# 2.net
KiCad netlist of a schematic drawn in Altium Designer
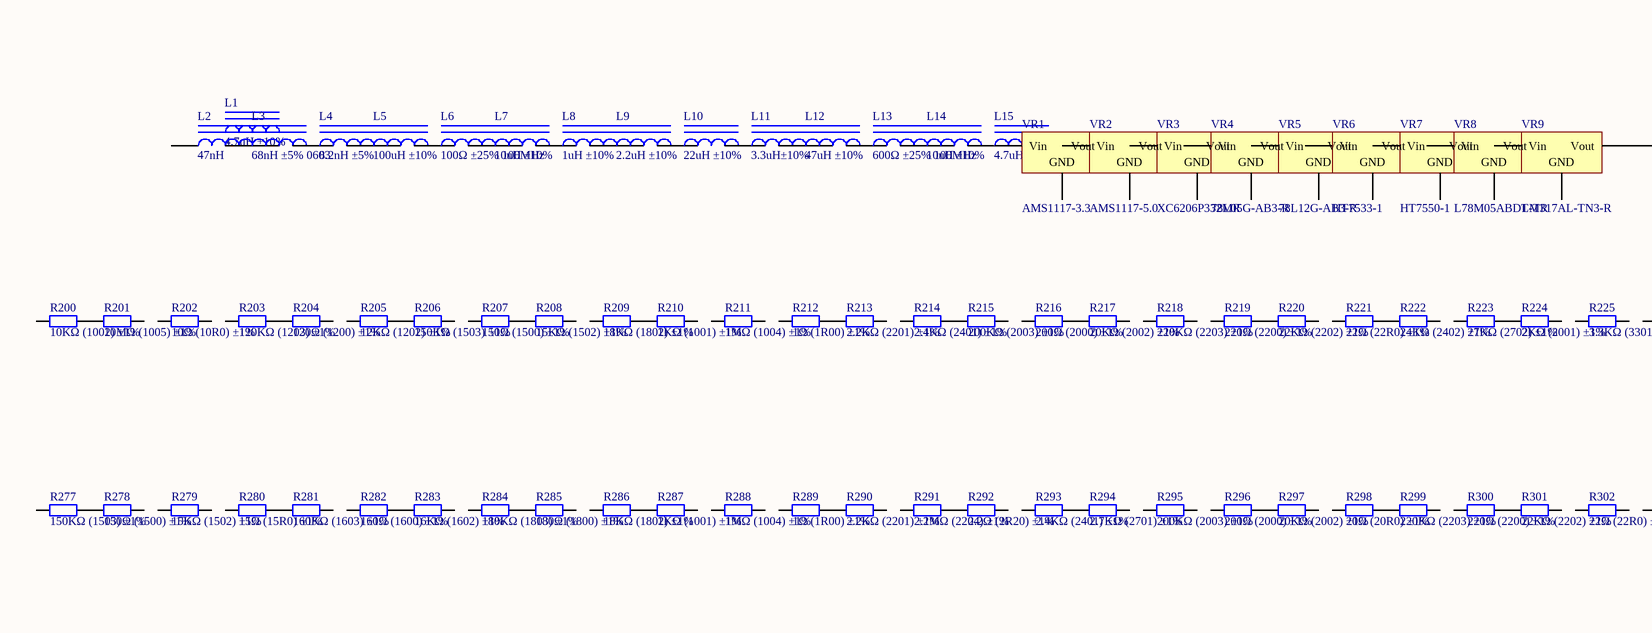
[diagram p0: 2.SchDoc, left]
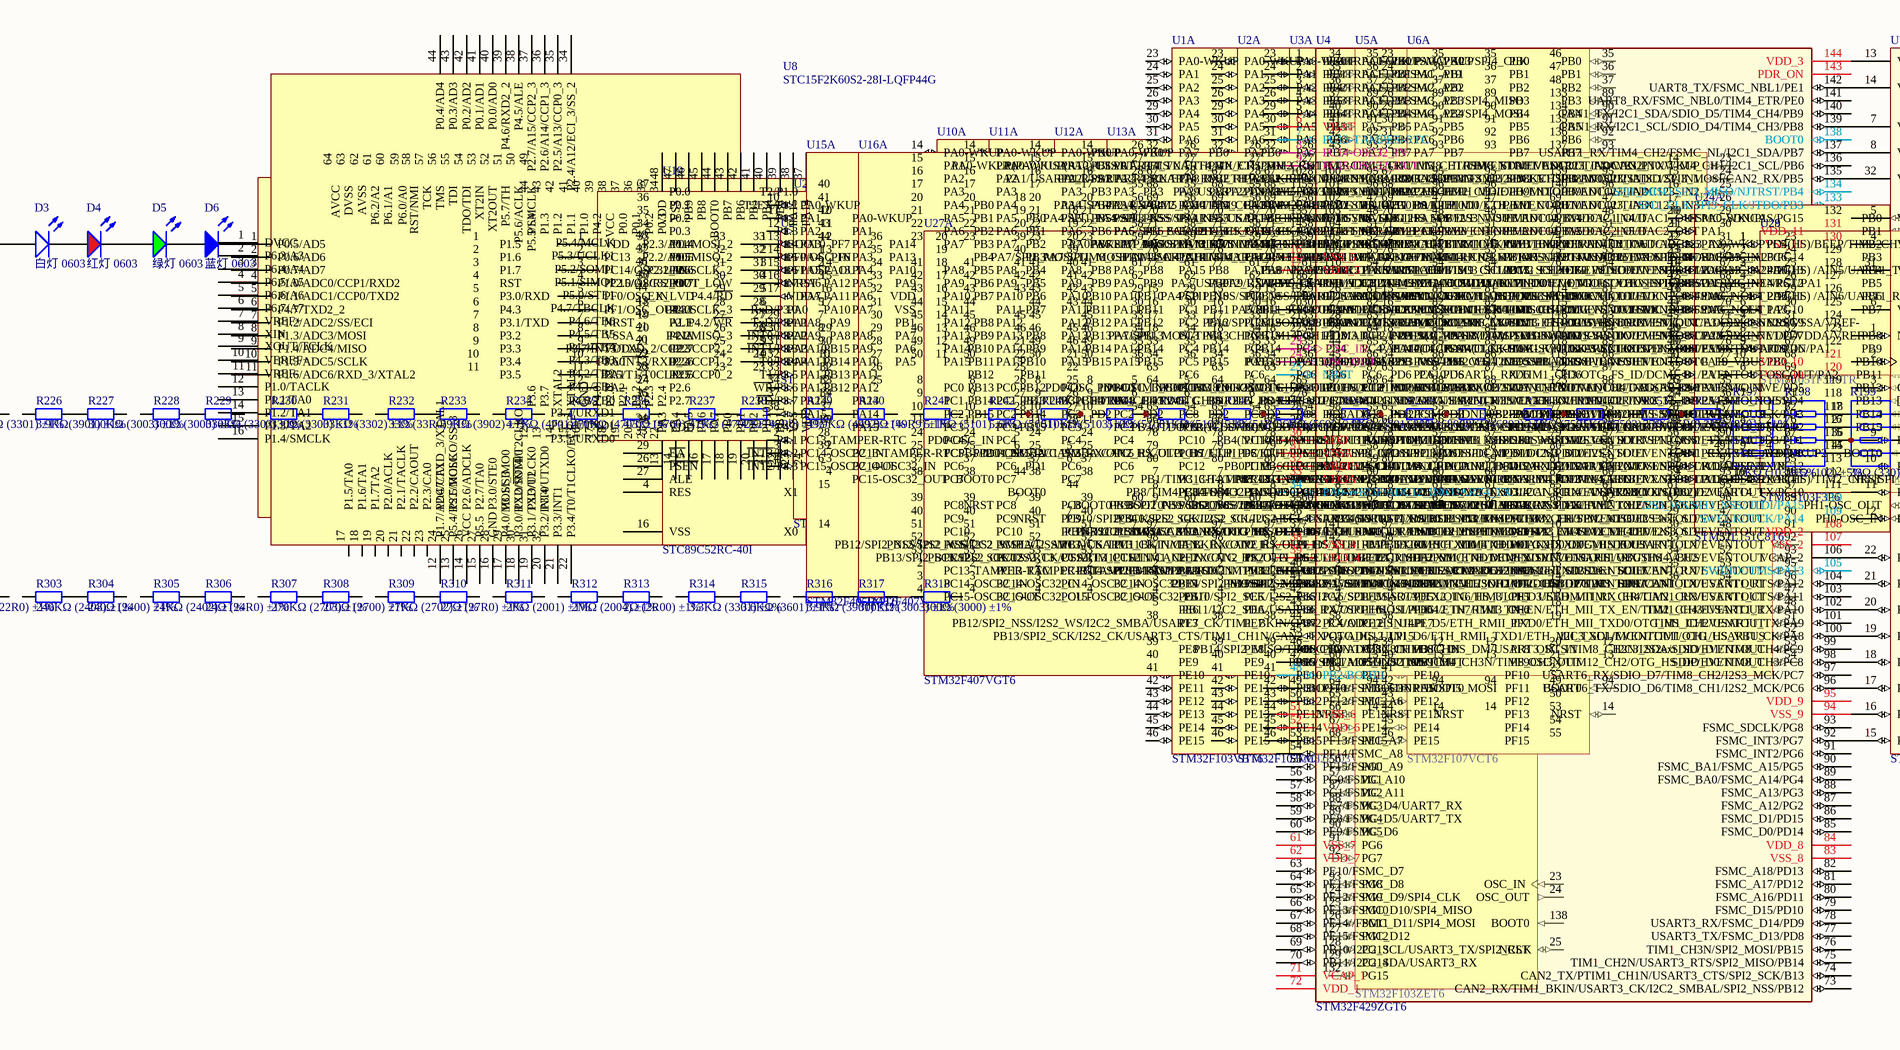
[diagram p1: 2.SchDoc, middle]
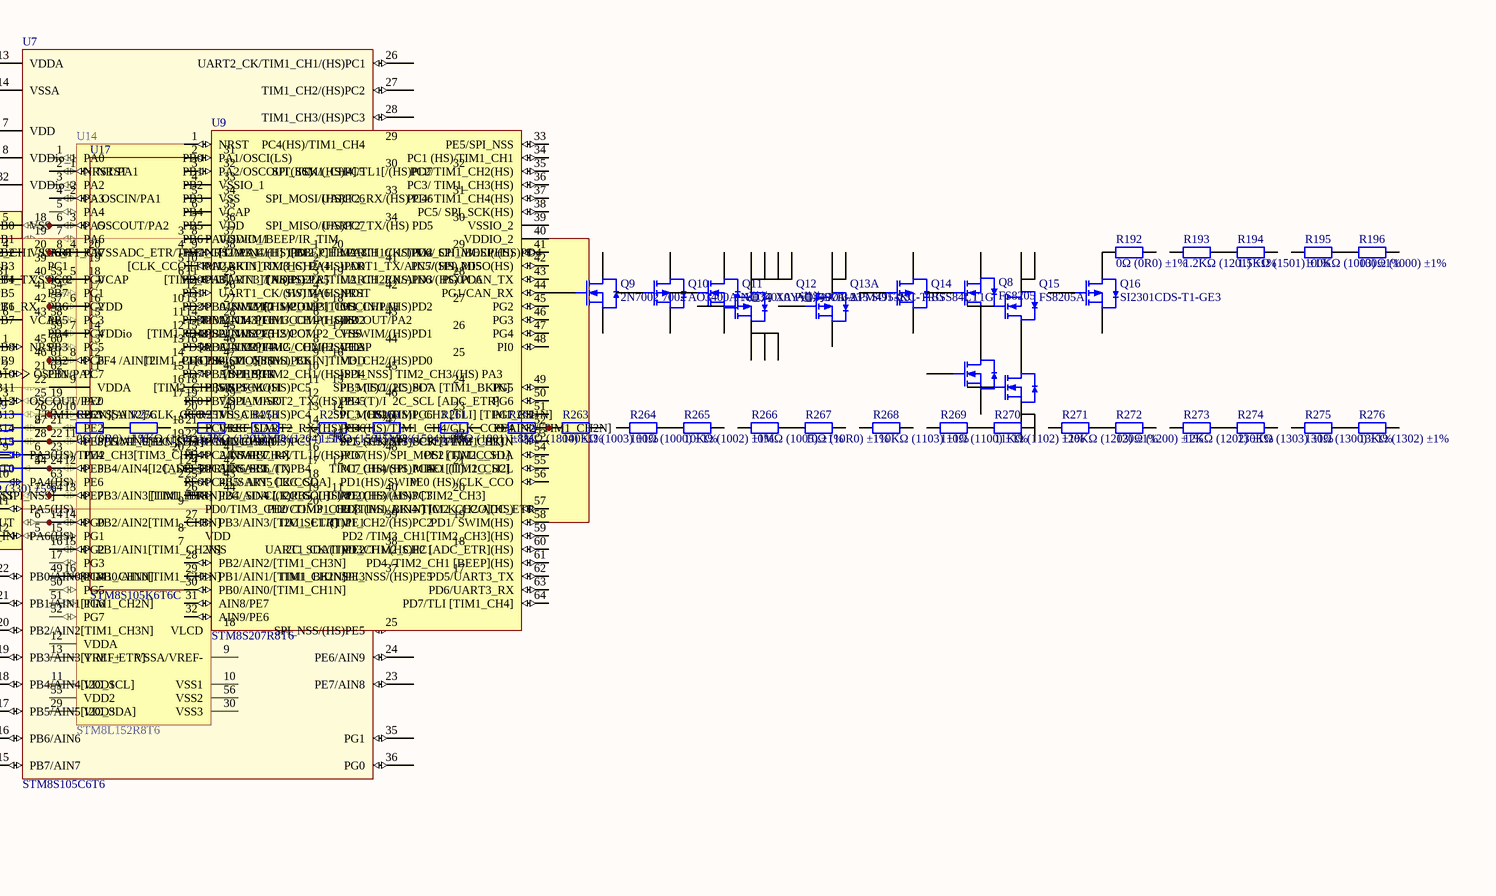
[diagram p2: 2.SchDoc, right]

(export (version "E")
  (design (tool "Eeschema 10.0.6"))
  (components
    (comp (ref "D3")
      (value "白灯 0603")
      (footprint "LC-0603_LED_S1")
      (description "发光二极管")
      (libsource (lib "Miscellaneous Devices LC") (part "0603 白灯"))
    )
    (comp (ref "D4")
      (value "红灯 0603")
      (footprint "LC-0603_LED_S1")
      (description "发光二极管")
      (libsource (lib "Miscellaneous Devices LC") (part "0603 红灯"))
    )
    (comp (ref "D5")
      (value "绿灯 0603")
      (footprint "LC-0603_LED_S1")
      (description "发光二极管")
      (libsource (lib "Miscellaneous Devices LC") (part "0603 绿灯"))
    )
    (comp (ref "D6")
      (value "蓝灯 0603")
      (footprint "LC-0603_LED_S1")
      (description "发光二极管")
      (libsource (lib "Miscellaneous Devices LC") (part "0603 蓝灯"))
    )
    (comp (ref "D7")
      (value "黄灯 0603")
      (footprint "LC-0603_LED_S1")
      (description "发光二极管")
      (libsource (lib "Miscellaneous Devices LC") (part "0603 黄灯"))
    )
    (comp (ref "D8")
      (value "白灯 0805")
      (footprint "LC-0805_LED_S1")
      (description "发光二极管")
      (libsource (lib "Miscellaneous Devices LC") (part "0805 白灯"))
    )
    (comp (ref "D9")
      (value "红灯 0805")
      (footprint "LC-0805_LED_S1")
      (description "发光二极管")
      (libsource (lib "Miscellaneous Devices LC") (part "0805 红灯"))
    )
    (comp (ref "D10")
      (value "翠绿 0805")
      (footprint "LC-0805_LED_S1")
      (description "发光二极管")
      (libsource (lib "Miscellaneous Devices LC") (part "0805 翠绿"))
    )
    (comp (ref "D11")
      (value "蓝灯 0805")
      (footprint "LC-0805_LED_S1")
      (description "发光二极管")
      (libsource (lib "Miscellaneous Devices LC") (part "0805 蓝灯"))
    )
    (comp (ref "D12")
      (value "黄灯 0805")
      (footprint "LC-0805_LED_S1")
      (description "发光二极管")
      (libsource (lib "Miscellaneous Devices LC") (part "0805 黄灯"))
    )
    (comp (ref "L1")
      (value "4.7uH ±10%")
      (footprint "LC-0603_L")
      (description "贴片电感")
      (libsource (lib "Miscellaneous Devices LC") (part "0603 4.7uH 10%"))
    )
    (comp (ref "L2")
      (value "47nH")
      (footprint "LC-0603_L")
      (description "贴片电感")
      (libsource (lib "Miscellaneous Devices LC") (part "0603 47nH"))
    )
    (comp (ref "L3")
      (value "68nH ±5% 0603")
      (footprint "LC-0603_L")
      (description "贴片电感")
      (libsource (lib "Miscellaneous Devices LC") (part "0603 68nH 5% 0603"))
    )
    (comp (ref "L4")
      (value "8.2nH ±5%")
      (footprint "LC-0603_L")
      (description "贴片电感")
      (libsource (lib "Miscellaneous Devices LC") (part "0603 8.2nH 5%"))
    )
    (comp (ref "L5")
      (value "100uH ±10%")
      (footprint "LC-0805_L")
      (description "贴片电感")
      (libsource (lib "Miscellaneous Devices LC") (part "0805 100uH 10%"))
    )
    (comp (ref "L6")
      (value "100Ω ±25% 100MHz")
      (footprint "LC-0805_L")
      (description "贴片磁珠")
      (libsource (lib "Miscellaneous Devices LC") (part "0805 100Ω 25% 100MHz"))
    )
    (comp (ref "L7")
      (value "10uH ±10%")
      (footprint "LC-0805_L")
      (description "贴片电感")
      (libsource (lib "Miscellaneous Devices LC") (part "0805 10uH 10%"))
    )
    (comp (ref "L8")
      (value "1uH ±10%")
      (footprint "LC-0805_L")
      (description "贴片电感")
      (libsource (lib "Miscellaneous Devices LC") (part "0805 1uH 10%"))
    )
    (comp (ref "L9")
      (value "2.2uH ±10%")
      (footprint "LC-0805_L")
      (description "贴片电感")
      (libsource (lib "Miscellaneous Devices LC") (part "0805 2.2uH 10%"))
    )
    (comp (ref "L10")
      (value "22uH ±10%")
      (footprint "LC-0805_L")
      (description "贴片电感")
      (libsource (lib "Miscellaneous Devices LC") (part "0805 22uH 10%"))
    )
    (comp (ref "L11")
      (value "3.3uH±10%")
      (footprint "LC-0805_L")
      (description "贴片电感")
      (libsource (lib "Miscellaneous Devices LC") (part "0805 3.3uH10%"))
    )
    (comp (ref "L12")
      (value "47uH ±10%")
      (footprint "LC-0805_L")
      (description "贴片电感")
      (libsource (lib "Miscellaneous Devices LC") (part "0805 47uH 10%"))
    )
    (comp (ref "L13")
      (value "600Ω ±25% 100MHz")
      (footprint "LC-0805_L")
      (description "贴片磁珠")
      (libsource (lib "Miscellaneous Devices LC") (part "0805 600Ω 25% 100MHz"))
    )
    (comp (ref "L14")
      (value "10uH ±10%")
      (footprint "LC-1206_L")
      (description "贴片电感")
      (libsource (lib "Miscellaneous Devices LC") (part "1206 10uH 10%"))
    )
    (comp (ref "L15")
      (value "4.7uH  ±10%")
      (footprint "LC-1206_L")
      (description "贴片电感")
      (libsource (lib "Miscellaneous Devices LC") (part "1206 4.7uH  10%"))
    )
    (comp (ref "Q8")
      (value "FS8205")
      (footprint "LC-SOT-23-6")
      (description "MOS(场效应管)")
      (libsource (lib "Miscellaneous Devices LC") (part "FS8205"))
    )
    (comp (ref "Q9")
      (value "2N7002 7002")
      (footprint "LC-SOT-23(SOT-23-3)")
      (description "MOS(场效应管)")
      (libsource (lib "Miscellaneous Devices LC") (part "2N7002 7002"))
    )
    (comp (ref "Q10")
      (value "AO3400A N道沟 X0YV1T SOT-23")
      (footprint "LC-SOT-23(SOT-23-3)")
      (description "MOS(场效应管)")
      (libsource (lib "Miscellaneous Devices LC") (part "AO3400A N道沟 X0YV1T SOT-23"))
    )
    (comp (ref "Q11")
      (value "AO3401A P道沟 X13A15 SOT-23")
      (footprint "LC-SOT-23(SOT-23-3)")
      (description "MOS(场效应管)")
      (libsource (lib "Miscellaneous Devices LC") (part "AO3401A P道沟 X13A15 SOT-23"))
    )
    (comp (ref "Q12")
      (value "AO4407A")
      (footprint "LC-SOIC-8_150mil")
      (description "MOS(场效应管)")
      (libsource (lib "Miscellaneous Devices LC") (part "AO4407A"))
    )
    (comp (ref "Q13")
      (value "APM4953KC-TRG")
      (footprint "LC-SOP-8_150mil")
      (description "MOS(场效应管)")
      (libsource (lib "Miscellaneous Devices LC") (part "APM4953KC-TRG"))
    )
    (comp (ref "Q14")
      (value "BSS84LT1G")
      (footprint "LC-SOT-23(SOT-23-3)")
      (description "MOS(场效应管)")
      (libsource (lib "Miscellaneous Devices LC") (part "BSS84LT1G"))
    )
    (comp (ref "Q15")
      (value "FS8205A")
      (footprint "LC-TSSOP-8_3x4.4x065P")
      (description "MOS(场效应管)")
      (libsource (lib "Miscellaneous Devices LC") (part "FS8205A"))
    )
    (comp (ref "Q16")
      (value "SI2301CDS-T1-GE3")
      (footprint "LC-SOT-23(SOT-23-3)")
      (description "MOS(场效应管)")
      (libsource (lib "Miscellaneous Devices LC") (part "SI2301CDS-T1-GE3"))
    )
    (comp (ref "R192")
      (value "0Ω (0R0) ±1%")
      (footprint "LC-0402_R")
      (description "贴片电阻")
      (libsource (lib "Miscellaneous Devices LC") (part "0402 0Ω (0R0) 1%"))
    )
    (comp (ref "R193")
      (value "1.2KΩ (1201) ±1%")
      (footprint "LC-0402_R")
      (description "贴片电阻")
      (libsource (lib "Miscellaneous Devices LC") (part "0402 1.2KΩ (1201) 1%"))
    )
    (comp (ref "R194")
      (value "1.5KΩ (1501) ±1%")
      (footprint "LC-0402_R")
      (description "贴片电阻")
      (libsource (lib "Miscellaneous Devices LC") (part "0402 1.5KΩ (1501) 1%"))
    )
    (comp (ref "R195")
      (value "100KΩ (1003) ±1%")
      (footprint "LC-0402_R")
      (description "贴片电阻")
      (libsource (lib "Miscellaneous Devices LC") (part "0402 100KΩ (1003) 1%"))
    )
    (comp (ref "R196")
      (value "100Ω (1000) ±1%")
      (footprint "LC-0402_R")
      (description "贴片电阻")
      (libsource (lib "Miscellaneous Devices LC") (part "0402 100Ω (1000) 1%"))
    )
    (comp (ref "R197")
      (value "10KΩ (103) ±5%")
      (footprint "LC-0402_Rx4")
      (description "贴片排阻")
      (libsource (lib "Miscellaneous Devices LC") (part "0402*4 10KΩ (103) 5%"))
    )
    (comp (ref "R198")
      (value "1KΩ (102) ±5%")
      (footprint "LC-0402_Rx4")
      (description "贴片排阻")
      (libsource (lib "Miscellaneous Devices LC") (part "0402*4 1KΩ (102) 5%"))
    )
    (comp (ref "R199")
      (value "33Ω (330) ±5%")
      (footprint "LC-0402_Rx4")
      (description "贴片排阻")
      (libsource (lib "Miscellaneous Devices LC") (part "0402*4 33Ω (330) 5%"))
    )
    (comp (ref "R200")
      (value "10KΩ (1002) ±1%")
      (footprint "LC-0402_R")
      (description "贴片电阻")
      (libsource (lib "Miscellaneous Devices LC") (part "0402 10KΩ (1002) 1%"))
    )
    (comp (ref "R201")
      (value "10MΩ (1005) ±1%")
      (footprint "LC-0402_R")
      (description "贴片电阻")
      (libsource (lib "Miscellaneous Devices LC") (part "0402 10MΩ (1005) 1%"))
    )
    (comp (ref "R202")
      (value "10Ω (10R0) ±1%")
      (footprint "LC-0402_R")
      (description "贴片电阻")
      (libsource (lib "Miscellaneous Devices LC") (part "0402 10Ω (10R0) 1%"))
    )
    (comp (ref "R203")
      (value "120KΩ (1203) ±1%")
      (footprint "LC-0402_R")
      (description "贴片电阻")
      (libsource (lib "Miscellaneous Devices LC") (part "0402 120KΩ (1203) 1%"))
    )
    (comp (ref "R204")
      (value "120Ω (1200) ±1%")
      (footprint "LC-0402_R")
      (description "贴片电阻")
      (libsource (lib "Miscellaneous Devices LC") (part "0402 120Ω (1200) 1%"))
    )
    (comp (ref "R205")
      (value "12KΩ (1202) ±1%")
      (footprint "LC-0402_R")
      (description "贴片电阻")
      (libsource (lib "Miscellaneous Devices LC") (part "0402 12KΩ (1202) 1%"))
    )
    (comp (ref "R206")
      (value "150KΩ (1503) ±1%")
      (footprint "LC-0402_R")
      (description "贴片电阻")
      (libsource (lib "Miscellaneous Devices LC") (part "0402 150KΩ (1503) 1%"))
    )
    (comp (ref "R207")
      (value "150Ω (1500) ±1%")
      (footprint "LC-0402_R")
      (description "贴片电阻")
      (libsource (lib "Miscellaneous Devices LC") (part "0402 150Ω (1500) 1%"))
    )
    (comp (ref "R208")
      (value "15KΩ (1502) ±1%")
      (footprint "LC-0402_R")
      (description "贴片电阻")
      (libsource (lib "Miscellaneous Devices LC") (part "0402 15KΩ (1502) 1%"))
    )
    (comp (ref "R209")
      (value "18KΩ (1802) ±1%")
      (footprint "LC-0402_R")
      (description "贴片电阻")
      (libsource (lib "Miscellaneous Devices LC") (part "0402 18KΩ (1802) 1%"))
    )
    (comp (ref "R210")
      (value "1KΩ (1001) ±1%")
      (footprint "LC-0402_R")
      (description "贴片电阻")
      (libsource (lib "Miscellaneous Devices LC") (part "0402 1KΩ (1001) 1%"))
    )
    (comp (ref "R211")
      (value "1MΩ (1004) ±1%")
      (footprint "LC-0402_R")
      (description "贴片电阻")
      (libsource (lib "Miscellaneous Devices LC") (part "0402 1MΩ (1004) 1%"))
    )
    (comp (ref "R212")
      (value "1Ω (1R00) ±1%")
      (footprint "LC-0402_R")
      (description "贴片电阻")
      (libsource (lib "Miscellaneous Devices LC") (part "0402 1Ω (1R00) 1%"))
    )
    (comp (ref "R213")
      (value "2.2KΩ (2201) ±1%")
      (footprint "LC-0402_R")
      (description "贴片电阻")
      (libsource (lib "Miscellaneous Devices LC") (part "0402 2.2KΩ (2201) 1%"))
    )
    (comp (ref "R214")
      (value "2.4KΩ (2401) ±1%")
      (footprint "LC-0402_R")
      (description "贴片电阻")
      (libsource (lib "Miscellaneous Devices LC") (part "0402 2.4KΩ (2401) 1%"))
    )
    (comp (ref "R215")
      (value "200KΩ (2003) ±1%")
      (footprint "LC-0402_R")
      (description "贴片电阻")
      (libsource (lib "Miscellaneous Devices LC") (part "0402 200KΩ (2003) 1%"))
    )
    (comp (ref "R216")
      (value "200Ω (2000) ±1%")
      (footprint "LC-0402_R")
      (description "贴片电阻")
      (libsource (lib "Miscellaneous Devices LC") (part "0402 200Ω (2000) 1%"))
    )
    (comp (ref "R217")
      (value "20KΩ (2002) ±1%")
      (footprint "LC-0402_R")
      (description "贴片电阻")
      (libsource (lib "Miscellaneous Devices LC") (part "0402 20KΩ (2002) 1%"))
    )
    (comp (ref "R218")
      (value "220KΩ (2203) ±1%")
      (footprint "LC-0402_R")
      (description "贴片电阻")
      (libsource (lib "Miscellaneous Devices LC") (part "0402 220KΩ (2203) 1%"))
    )
    (comp (ref "R219")
      (value "220Ω (2200) ±1%")
      (footprint "LC-0402_R")
      (description "贴片电阻")
      (libsource (lib "Miscellaneous Devices LC") (part "0402 220Ω (2200) 1%"))
    )
    (comp (ref "R220")
      (value "22KΩ (2202) ±1%")
      (footprint "LC-0402_R")
      (description "贴片电阻")
      (libsource (lib "Miscellaneous Devices LC") (part "0402 22KΩ (2202) 1%"))
    )
    (comp (ref "R221")
      (value "22Ω (22R0) ±1%")
      (footprint "LC-0402_R")
      (description "贴片电阻")
      (libsource (lib "Miscellaneous Devices LC") (part "0402 22Ω (22R0) 1%"))
    )
    (comp (ref "R222")
      (value "24KΩ (2402) ±1%")
      (footprint "LC-0402_R")
      (description "贴片电阻")
      (libsource (lib "Miscellaneous Devices LC") (part "0402 24KΩ (2402) 1%"))
    )
    (comp (ref "R223")
      (value "27KΩ (2702) ±1%")
      (footprint "LC-0402_R")
      (description "贴片电阻")
      (libsource (lib "Miscellaneous Devices LC") (part "0402 27KΩ (2702) 1%"))
    )
    (comp (ref "R224")
      (value "2KΩ (2001) ±1%")
      (footprint "LC-0402_R")
      (description "贴片电阻")
      (libsource (lib "Miscellaneous Devices LC") (part "0402 2KΩ (2001) 1%"))
    )
    (comp (ref "R225")
      (value "3.3KΩ (3301) ±1%")
      (footprint "LC-0402_R")
      (description "贴片电阻")
      (libsource (lib "Miscellaneous Devices LC") (part "0402 3.3KΩ (3301) 1%"))
    )
    (comp (ref "R226")
      (value "3.9KΩ(3901) ±1%")
      (footprint "LC-0402_R")
      (description "贴片电阻")
      (libsource (lib "Miscellaneous Devices LC") (part "0402 3.9KΩ(3901) 1%"))
    )
    (comp (ref "R227")
      (value "300KΩ (3003) ±1%")
      (footprint "LC-0402_R")
      (description "贴片电阻")
      (libsource (lib "Miscellaneous Devices LC") (part "0402 300KΩ (3003) 1%"))
    )
    (comp (ref "R228")
      (value "300Ω (3000) ±1%")
      (footprint "LC-0402_R")
      (description "贴片电阻")
      (libsource (lib "Miscellaneous Devices LC") (part "0402 300Ω (3000) 1%"))
    )
    (comp (ref "R229")
      (value "330KΩ (3303) ±1%")
      (footprint "LC-0402_R")
      (description "贴片电阻")
      (libsource (lib "Miscellaneous Devices LC") (part "0402 330KΩ (3303) 1%"))
    )
    (comp (ref "R230")
      (value "330Ω (3300) ±1%")
      (footprint "LC-0402_R")
      (description "贴片电阻")
      (libsource (lib "Miscellaneous Devices LC") (part "0402 330Ω (3300) 1%"))
    )
    (comp (ref "R231")
      (value "33KΩ (3302) ±1%")
      (footprint "LC-0402_R")
      (description "贴片电阻")
      (libsource (lib "Miscellaneous Devices LC") (part "0402 33KΩ (3302) 1%"))
    )
    (comp (ref "R232")
      (value "33Ω (33R0) ±1%")
      (footprint "LC-0402_R")
      (description "贴片电阻")
      (libsource (lib "Miscellaneous Devices LC") (part "0402 33Ω (33R0) 1%"))
    )
    (comp (ref "R233")
      (value "39KΩ (3902) ±1%")
      (footprint "LC-0402_R")
      (description "贴片电阻")
      (libsource (lib "Miscellaneous Devices LC") (part "0402 39KΩ (3902) 1%"))
    )
    (comp (ref "R234")
      (value "4.7KΩ (4701) ±1%")
      (footprint "LC-0402_R")
      (description "贴片电阻")
      (libsource (lib "Miscellaneous Devices LC") (part "0402 4.7KΩ (4701) 1%"))
    )
    (comp (ref "R235")
      (value "470KΩ (4703) ±1%")
      (footprint "LC-0402_R")
      (description "贴片电阻")
      (libsource (lib "Miscellaneous Devices LC") (part "0402 470KΩ (4703) 1%"))
    )
    (comp (ref "R236")
      (value "470Ω (4700) ±1%")
      (footprint "LC-0402_R")
      (description "贴片电阻")
      (libsource (lib "Miscellaneous Devices LC") (part "0402 470Ω (4700) 1%"))
    )
    (comp (ref "R237")
      (value "47KΩ (4702) ±1%")
      (footprint "LC-0402_R")
      (description "贴片电阻")
      (libsource (lib "Miscellaneous Devices LC") (part "0402 47KΩ (4702) 1%"))
    )
    (comp (ref "R238")
      (value "47Ω (47R0) ±1%")
      (footprint "LC-0402_R")
      (description "贴片电阻")
      (libsource (lib "Miscellaneous Devices LC") (part "0402 47Ω (47R0) 1%"))
    )
    (comp (ref "R239")
      (value "49.9KΩ (4992) ±1%")
      (footprint "LC-0402_R")
      (description "贴片电阻")
      (libsource (lib "Miscellaneous Devices LC") (part "0402 49.9KΩ (4992) 1%"))
    )
    (comp (ref "R240")
      (value "49.9Ω (49R9) ±1%")
      (footprint "LC-0402_R")
      (description "贴片电阻")
      (libsource (lib "Miscellaneous Devices LC") (part "0402 49.9Ω (49R9) 1%"))
    )
    (comp (ref "R241")
      (value "5.1KΩ (5101) ±1%")
      (footprint "LC-0402_R")
      (description "贴片电阻")
      (libsource (lib "Miscellaneous Devices LC") (part "0402 5.1KΩ (5101) 1%"))
    )
    (comp (ref "R242")
      (value "5.6KΩ (5601) ±1%")
      (footprint "LC-0402_R")
      (description "贴片电阻")
      (libsource (lib "Miscellaneous Devices LC") (part "0402 5.6KΩ (5601) 1%"))
    )
    (comp (ref "R243")
      (value "510KΩ (5103) ±1%")
      (footprint "LC-0402_R")
      (description "贴片电阻")
      (libsource (lib "Miscellaneous Devices LC") (part "0402 510KΩ (5103) 1%"))
    )
    (comp (ref "R244")
      (value "510Ω (5100) ±1%")
      (footprint "LC-0402_R")
      (description "贴片电阻")
      (libsource (lib "Miscellaneous Devices LC") (part "0402 510Ω (5100) 1%"))
    )
    (comp (ref "R245")
      (value "51KΩ (5102) ±1%")
      (footprint "LC-0402_R")
      (description "贴片电阻")
      (libsource (lib "Miscellaneous Devices LC") (part "0402 51KΩ (5102) 1%"))
    )
    (comp (ref "R246")
      (value "51Ω (51R0) ±1%")
      (footprint "LC-0402_R")
      (description "贴片电阻")
      (libsource (lib "Miscellaneous Devices LC") (part "0402 51Ω (51R0) 1%"))
    )
    (comp (ref "R247")
      (value "56KΩ (5602) ±1%")
      (footprint "LC-0402_R")
      (description "贴片电阻")
      (libsource (lib "Miscellaneous Devices LC") (part "0402 56KΩ (5602) 1%"))
    )
    (comp (ref "R248")
      (value "6.8KΩ (6801) ±1%")
      (footprint "LC-0402_R")
      (description "贴片电阻")
      (libsource (lib "Miscellaneous Devices LC") (part "0402 6.8KΩ (6801) 1%"))
    )
    (comp (ref "R249")
      (value "680Ω (6800) ±1%")
      (footprint "LC-0402_R")
      (description "贴片电阻")
      (libsource (lib "Miscellaneous Devices LC") (part "0402 680Ω (6800) 1%"))
    )
    (comp (ref "R250")
      (value "68KΩ (6802) ±1%")
      (footprint "LC-0402_R")
      (description "贴片电阻")
      (libsource (lib "Miscellaneous Devices LC") (part "0402 68KΩ (6802) 1%"))
    )
    (comp (ref "R251")
      (value "7.5KΩ (7501) ±1%")
      (footprint "LC-0402_R")
      (description "贴片电阻")
      (libsource (lib "Miscellaneous Devices LC") (part "0402 7.5KΩ (7501) 1%"))
    )
    (comp (ref "R252")
      (value "75KΩ (7502) ±1%")
      (footprint "LC-0402_R")
      (description "贴片电阻")
      (libsource (lib "Miscellaneous Devices LC") (part "0402 75KΩ (7502) 1%"))
    )
    (comp (ref "R253")
      (value "75Ω (75R0) ±1%")
      (footprint "LC-0402_R")
      (description "贴片电阻")
      (libsource (lib "Miscellaneous Devices LC") (part "0402 75Ω (75R0) 1%"))
    )
    (comp (ref "R254")
      (value "8.2KΩ (8201) ±1%")
      (footprint "LC-0402_R")
      (description "贴片电阻")
      (libsource (lib "Miscellaneous Devices LC") (part "0402 8.2KΩ (8201) 1%"))
    )
    (comp (ref "R255")
      (value "0Ω (0R0) ±1%")
      (footprint "LC-0603_R")
      (description "贴片电阻")
      (libsource (lib "Miscellaneous Devices LC") (part "0603 0Ω (0R0) 1%"))
    )
    (comp (ref "R256")
      (value "1.1KΩ (1101) ±1%")
      (footprint "LC-0603_R")
      (description "贴片电阻")
      (libsource (lib "Miscellaneous Devices LC") (part "0603 1.1KΩ (1101) 1%"))
    )
    (comp (ref "R257")
      (value "1.2KΩ (1201) ±1%")
      (footprint "LC-0603_R")
      (description "贴片电阻")
      (libsource (lib "Miscellaneous Devices LC") (part "0603 1.2KΩ (1201) 1%"))
    )
    (comp (ref "R258")
      (value "1.2MΩ (1204) ±1%")
      (footprint "LC-0603_R")
      (description "贴片电阻")
      (libsource (lib "Miscellaneous Devices LC") (part "0603 1.2MΩ (1204) 1%"))
    )
    (comp (ref "R259")
      (value "1.5KΩ (1501) ±1%")
      (footprint "LC-0603_R")
      (description "贴片电阻")
      (libsource (lib "Miscellaneous Devices LC") (part "0603 1.5KΩ (1501) 1%"))
    )
    (comp (ref "R260")
      (value "1.5MΩ (1504) ±1%")
      (footprint "LC-0603_R")
      (description "贴片电阻")
      (libsource (lib "Miscellaneous Devices LC") (part "0603 1.5MΩ (1504) 1%"))
    )
    (comp (ref "R261")
      (value "1.8KΩ (1801) ±1%")
      (footprint "LC-0603_R")
      (description "贴片电阻")
      (libsource (lib "Miscellaneous Devices LC") (part "0603 1.8KΩ (1801) 1%"))
    )
    (comp (ref "R262")
      (value "1.8MΩ (1804) ±1%")
      (footprint "LC-0603_R")
      (description "贴片电阻")
      (libsource (lib "Miscellaneous Devices LC") (part "0603 1.8MΩ (1804) 1%"))
    )
    (comp (ref "R263")
      (value "100KΩ (1003) ±1%")
      (footprint "LC-0603_R")
      (description "贴片电阻")
      (libsource (lib "Miscellaneous Devices LC") (part "0603 100KΩ (1003) 1%"))
    )
    (comp (ref "R264")
      (value "100Ω (1000) ±1%")
      (footprint "LC-0603_R")
      (description "贴片电阻")
      (libsource (lib "Miscellaneous Devices LC") (part "0603 100Ω (1000) 1%"))
    )
    (comp (ref "R265")
      (value "10KΩ (1002) ±1%")
      (footprint "LC-0603_R")
      (description "贴片电阻")
      (libsource (lib "Miscellaneous Devices LC") (part "0603 10KΩ (1002) 1%"))
    )
    (comp (ref "R266")
      (value "10MΩ (1005) ±1%")
      (footprint "LC-0603_R")
      (description "贴片电阻")
      (libsource (lib "Miscellaneous Devices LC") (part "0603 10MΩ (1005) 1%"))
    )
    (comp (ref "R267")
      (value "10Ω (10R0) ±1%")
      (footprint "LC-0603_R")
      (description "贴片电阻")
      (libsource (lib "Miscellaneous Devices LC") (part "0603 10Ω (10R0) 1%"))
    )
    (comp (ref "R268")
      (value "110KΩ (1103) ±1%")
      (footprint "LC-0603_R")
      (description "贴片电阻")
      (libsource (lib "Miscellaneous Devices LC") (part "0603 110KΩ (1103) 1%"))
    )
    (comp (ref "R269")
      (value "110Ω (1100) ±1%")
      (footprint "LC-0603_R")
      (description "贴片电阻")
      (libsource (lib "Miscellaneous Devices LC") (part "0603 110Ω (1100) 1%"))
    )
    (comp (ref "R270")
      (value "11KΩ (1102) ±1%")
      (footprint "LC-0603_R")
      (description "贴片电阻")
      (libsource (lib "Miscellaneous Devices LC") (part "0603 11KΩ (1102) 1%"))
    )
    (comp (ref "R271")
      (value "120KΩ (1203) ±1%")
      (footprint "LC-0603_R")
      (description "贴片电阻")
      (libsource (lib "Miscellaneous Devices LC") (part "0603 120KΩ (1203) 1%"))
    )
    (comp (ref "R272")
      (value "120Ω (1200) ±1%")
      (footprint "LC-0603_R")
      (description "贴片电阻")
      (libsource (lib "Miscellaneous Devices LC") (part "0603 120Ω (1200) 1%"))
    )
    (comp (ref "R273")
      (value "12KΩ (1202) ±1%")
      (footprint "LC-0603_R")
      (description "贴片电阻")
      (libsource (lib "Miscellaneous Devices LC") (part "0603 12KΩ (1202) 1%"))
    )
    (comp (ref "R274")
      (value "130KΩ (1303) ±1%")
      (footprint "LC-0603_R")
      (description "贴片电阻")
      (libsource (lib "Miscellaneous Devices LC") (part "0603 130KΩ (1303) 1%"))
    )
    (comp (ref "R275")
      (value "130Ω (1300) ±1%")
      (footprint "LC-0603_R")
      (description "贴片电阻")
      (libsource (lib "Miscellaneous Devices LC") (part "0603 130Ω (1300) 1%"))
    )
    (comp (ref "R276")
      (value "13KΩ (1302) ±1%")
      (footprint "LC-0603_R")
      (description "贴片电阻")
      (libsource (lib "Miscellaneous Devices LC") (part "0603 13KΩ (1302) 1%"))
    )
    (comp (ref "R277")
      (value "150KΩ (1503) ±1%")
      (footprint "LC-0603_R")
      (description "贴片电阻")
      (libsource (lib "Miscellaneous Devices LC") (part "0603 150KΩ (1503) 1%"))
    )
    (comp (ref "R278")
      (value "150Ω (1500) ±1%")
      (footprint "LC-0603_R")
      (description "贴片电阻")
      (libsource (lib "Miscellaneous Devices LC") (part "0603 150Ω (1500) 1%"))
    )
    (comp (ref "R279")
      (value "15KΩ (1502) ±1%")
      (footprint "LC-0603_R")
      (description "贴片电阻")
      (libsource (lib "Miscellaneous Devices LC") (part "0603 15KΩ (1502) 1%"))
    )
    (comp (ref "R280")
      (value "15Ω (15R0) ±1%")
      (footprint "LC-0603_R")
      (description "贴片电阻")
      (libsource (lib "Miscellaneous Devices LC") (part "0603 15Ω (15R0) 1%"))
    )
    (comp (ref "R281")
      (value "160KΩ (1603) ±1%")
      (footprint "LC-0603_R")
      (description "贴片电阻")
      (libsource (lib "Miscellaneous Devices LC") (part "0603 160KΩ (1603) 1%"))
    )
    (comp (ref "R282")
      (value "160Ω (1600) ±1%")
      (footprint "LC-0603_R")
      (description "贴片电阻")
      (libsource (lib "Miscellaneous Devices LC") (part "0603 160Ω (1600) 1%"))
    )
    (comp (ref "R283")
      (value "16KΩ (1602) ±1%")
      (footprint "LC-0603_R")
      (description "贴片电阻")
      (libsource (lib "Miscellaneous Devices LC") (part "0603 16KΩ (1602) 1%"))
    )
    (comp (ref "R284")
      (value "180KΩ (1803) ±1%")
      (footprint "LC-0603_R")
      (description "贴片电阻")
      (libsource (lib "Miscellaneous Devices LC") (part "0603 180KΩ (1803) 1%"))
    )
    (comp (ref "R285")
      (value "180Ω (1800) ±1%")
      (footprint "LC-0603_R")
      (description "贴片电阻")
      (libsource (lib "Miscellaneous Devices LC") (part "0603 180Ω (1800) 1%"))
    )
    (comp (ref "R286")
      (value "18KΩ (1802) ±1%")
      (footprint "LC-0603_R")
      (description "贴片电阻")
      (libsource (lib "Miscellaneous Devices LC") (part "0603 18KΩ (1802) 1%"))
    )
    (comp (ref "R287")
      (value "1KΩ (1001) ±1%")
      (footprint "LC-0603_R")
      (description "贴片电阻")
      (libsource (lib "Miscellaneous Devices LC") (part "0603 1KΩ (1001) 1%"))
    )
    (comp (ref "R288")
      (value "1MΩ (1004) ±1%")
      (footprint "LC-0603_R")
      (description "贴片电阻")
      (libsource (lib "Miscellaneous Devices LC") (part "0603 1MΩ (1004) 1%"))
    )
    (comp (ref "R289")
      (value "1Ω (1R00) ±1%")
      (footprint "LC-0603_R")
      (description "贴片电阻")
      (libsource (lib "Miscellaneous Devices LC") (part "0603 1Ω (1R00) 1%"))
    )
    (comp (ref "R290")
      (value "2.2KΩ (2201) ±1%")
      (footprint "LC-0603_R")
      (description "贴片电阻")
      (libsource (lib "Miscellaneous Devices LC") (part "0603 2.2KΩ (2201) 1%"))
    )
    (comp (ref "R291")
      (value "2.2MΩ (2204) ±1%")
      (footprint "LC-0603_R")
      (description "贴片电阻")
      (libsource (lib "Miscellaneous Devices LC") (part "0603 2.2MΩ (2204) 1%"))
    )
    (comp (ref "R292")
      (value "2.2Ω (2R20) ±1%")
      (footprint "LC-0603_R")
      (description "贴片电阻")
      (libsource (lib "Miscellaneous Devices LC") (part "0603 2.2Ω (2R20) 1%"))
    )
    (comp (ref "R293")
      (value "2.4KΩ (2401) ±1%")
      (footprint "LC-0603_R")
      (description "贴片电阻")
      (libsource (lib "Miscellaneous Devices LC") (part "0603 2.4KΩ (2401) 1%"))
    )
    (comp (ref "R294")
      (value "2.7KΩ (2701) ±1%")
      (footprint "LC-0603_R")
      (description "贴片电阻")
      (libsource (lib "Miscellaneous Devices LC") (part "0603 2.7KΩ (2701) 1%"))
    )
    (comp (ref "R295")
      (value "200KΩ (2003) ±1%")
      (footprint "LC-0603_R")
      (description "贴片电阻")
      (libsource (lib "Miscellaneous Devices LC") (part "0603 200KΩ (2003) 1%"))
    )
    (comp (ref "R296")
      (value "200Ω (2000) ±1%")
      (footprint "LC-0603_R")
      (description "贴片电阻")
      (libsource (lib "Miscellaneous Devices LC") (part "0603 200Ω (2000) 1%"))
    )
    (comp (ref "R297")
      (value "20KΩ (2002) ±1%")
      (footprint "LC-0603_R")
      (description "贴片电阻")
      (libsource (lib "Miscellaneous Devices LC") (part "0603 20KΩ (2002) 1%"))
    )
    (comp (ref "R298")
      (value "20Ω (20R0) ±1%")
      (footprint "LC-0603_R")
      (description "贴片电阻")
      (libsource (lib "Miscellaneous Devices LC") (part "0603 20Ω (20R0) 1%"))
    )
    (comp (ref "R299")
      (value "220KΩ (2203) ±1%")
      (footprint "LC-0603_R")
      (description "贴片电阻")
      (libsource (lib "Miscellaneous Devices LC") (part "0603 220KΩ (2203) 1%"))
    )
    (comp (ref "R300")
      (value "220Ω (2200) ±1%")
      (footprint "LC-0603_R")
      (description "贴片电阻")
      (libsource (lib "Miscellaneous Devices LC") (part "0603 220Ω (2200) 1%"))
    )
    (comp (ref "R301")
      (value "22KΩ (2202) ±1%")
      (footprint "LC-0603_R")
      (description "贴片电阻")
      (libsource (lib "Miscellaneous Devices LC") (part "0603 22KΩ (2202) 1%"))
    )
    (comp (ref "R302")
      (value "22Ω (22R0) ±1%")
      (footprint "LC-0603_R")
      (description "贴片电阻")
      (libsource (lib "Miscellaneous Devices LC") (part "0603 22Ω (22R0) 1%"))
    )
    (comp (ref "R303")
      (value "240KΩ (2403) ±1%")
      (footprint "LC-0603_R")
      (description "贴片电阻")
      (libsource (lib "Miscellaneous Devices LC") (part "0603 240KΩ (2403) 1%"))
    )
    (comp (ref "R304")
      (value "240Ω (2400) ±1%")
      (footprint "LC-0603_R")
      (description "贴片电阻")
      (libsource (lib "Miscellaneous Devices LC") (part "0603 240Ω (2400) 1%"))
    )
    (comp (ref "R305")
      (value "24KΩ (2402) ±1%")
      (footprint "LC-0603_R")
      (description "贴片电阻")
      (libsource (lib "Miscellaneous Devices LC") (part "0603 24KΩ (2402) 1%"))
    )
    (comp (ref "R306")
      (value "24Ω (24R0) ±1%")
      (footprint "LC-0603_R")
      (description "贴片电阻")
      (libsource (lib "Miscellaneous Devices LC") (part "0603 24Ω (24R0) 1%"))
    )
    (comp (ref "R307")
      (value "270KΩ (2703) ±1%")
      (footprint "LC-0603_R")
      (description "贴片电阻")
      (libsource (lib "Miscellaneous Devices LC") (part "0603 270KΩ (2703) 1%"))
    )
    (comp (ref "R308")
      (value "270Ω (2700) ±1%")
      (footprint "LC-0603_R")
      (description "贴片电阻")
      (libsource (lib "Miscellaneous Devices LC") (part "0603 270Ω (2700) 1%"))
    )
    (comp (ref "R309")
      (value "27KΩ (2702) ±1%")
      (footprint "LC-0603_R")
      (description "贴片电阻")
      (libsource (lib "Miscellaneous Devices LC") (part "0603 27KΩ (2702) 1%"))
    )
    (comp (ref "R310")
      (value "27Ω (27R0) ±1%")
      (footprint "LC-0603_R")
      (description "贴片电阻")
      (libsource (lib "Miscellaneous Devices LC") (part "0603 27Ω (27R0) 1%"))
    )
    (comp (ref "R311")
      (value "2KΩ (2001) ±1%")
      (footprint "LC-0603_R")
      (description "贴片电阻")
      (libsource (lib "Miscellaneous Devices LC") (part "0603 2KΩ (2001) 1%"))
    )
    (comp (ref "R312")
      (value "2MΩ (2004) ±1%")
      (footprint "LC-0603_R")
      (description "贴片电阻")
      (libsource (lib "Miscellaneous Devices LC") (part "0603 2MΩ (2004) 1%"))
    )
    (comp (ref "R313")
      (value "2Ω (2R00) ±1%")
      (footprint "LC-0603_R")
      (description "贴片电阻")
      (libsource (lib "Miscellaneous Devices LC") (part "0603 2Ω (2R00) 1%"))
    )
    (comp (ref "R314")
      (value "3.3KΩ (3301) ±1%")
      (footprint "LC-0603_R")
      (description "贴片电阻")
      (libsource (lib "Miscellaneous Devices LC") (part "0603 3.3KΩ (3301) 1%"))
    )
    (comp (ref "R315")
      (value "3.6KΩ (3601) ±1%")
      (footprint "LC-0603_R")
      (description "贴片电阻")
      (libsource (lib "Miscellaneous Devices LC") (part "0603 3.6KΩ (3601) 1%"))
    )
    (comp (ref "R316")
      (value "3.9KΩ (3901) ±1%")
      (footprint "LC-0603_R")
      (description "贴片电阻")
      (libsource (lib "Miscellaneous Devices LC") (part "0603 3.9KΩ (3901) 1%"))
    )
    (comp (ref "R317")
      (value "300KΩ (3003) ±1%")
      (footprint "LC-0603_R")
      (description "贴片电阻")
      (libsource (lib "Miscellaneous Devices LC") (part "0603 300KΩ (3003) 1%"))
    )
    (comp (ref "R318")
      (value "300Ω (3000) ±1%")
      (footprint "LC-0603_R")
      (description "贴片电阻")
      (libsource (lib "Miscellaneous Devices LC") (part "0603 300Ω (3000) 1%"))
    )
    (comp (ref "U1")
      (value "STM32F103VBT6")
      (footprint "LC-LQFP-100_14x14x05P")
      (description "ARM")
      (libsource (lib "Miscellaneous Devices LC") (part "STM32F103VBT6"))
    )
    (comp (ref "U2")
      (value "STM32F103VCT6")
      (footprint "LC-LQFP-100_14x14x05P")
      (description "ARM")
      (libsource (lib "Miscellaneous Devices LC") (part "STM32F103VCT6"))
    )
    (comp (ref "U3")
      (value "STM32F103VET6")
      (footprint "LC-LQFP-100_14x14x05P")
      (description "ARM")
      (libsource (lib "Miscellaneous Devices LC") (part "STM32F103VET6"))
    )
    (comp (ref "U4")
      (value "STM32F429ZGT6")
      (footprint "LC-LQFP-144_20x20x05P")
      (description "ARM")
      (libsource (lib "Miscellaneous Devices LC") (part "STM32F429ZGT6"))
    )
    (comp (ref "U5")
      (value "STM32F103ZET6")
      (footprint "LC-LQFP-144_20x20x05P")
      (description "ARM")
      (libsource (lib "Miscellaneous Devices LC") (part "STM32F103ZET6"))
    )
    (comp (ref "U6")
      (value "STM32F107VCT6")
      (footprint "LC-LQFP-100_14x14x05P")
      (description "ARM")
      (libsource (lib "Miscellaneous Devices LC") (part "STM32F107VCT6"))
    )
    (comp (ref "U7")
      (value "STM8S105C6T6")
      (footprint "LC-LQFP-48_7x7x05P")
      (description "MCU")
      (libsource (lib "Miscellaneous Devices LC") (part "STM8S105C6T6"))
    )
    (comp (ref "U8")
      (value "STC15F2K60S2-28I-LQFP44G")
      (footprint "LC-LQFP-44_10x10x08P")
      (description "MCU")
      (libsource (lib "Miscellaneous Devices LC") (part "STC15F2K60S2-28I-LQFP44G"))
    )
    (comp (ref "U9")
      (value "STM8S207R8T6")
      (footprint "LC-LQFP-64_10x10x05P")
      (description "MCU")
      (libsource (lib "Miscellaneous Devices LC") (part "STM8S207R8T6"))
    )
    (comp (ref "U10")
      (value "STM32F103R8T6")
      (footprint "LC-LQFP-64_10x10x05P")
      (description "ARM")
      (libsource (lib "Miscellaneous Devices LC") (part "STM32F103R8T6"))
    )
    (comp (ref "U11")
      (value "STM32F103RBT6")
      (footprint "LC-LQFP-64_10x10x05P")
      (description "ARM")
      (libsource (lib "Miscellaneous Devices LC") (part "STM32F103RBT6"))
    )
    (comp (ref "U12")
      (value "STM32F103RCT6")
      (footprint "LC-LQFP-64_10x10x05P")
      (description "ARM")
      (libsource (lib "Miscellaneous Devices LC") (part "STM32F103RCT6"))
    )
    (comp (ref "U13")
      (value "STM32F103RET6")
      (footprint "LC-LQFP-64_10x10x05P")
      (description "ARM")
      (libsource (lib "Miscellaneous Devices LC") (part "STM32F103RET6"))
    )
    (comp (ref "U14")
      (value "STM8L152R8T6")
      (footprint "LC-LQFP-64_10x10x05P")
      (description "MCU")
      (libsource (lib "Miscellaneous Devices LC") (part "STM8L152R8T6"))
    )
    (comp (ref "U15")
      (value "STM32F405RGT6")
      (footprint "LC-LQFP-64_10x10x05P")
      (description "ARM")
      (libsource (lib "Miscellaneous Devices LC") (part "STM32F405RGT6"))
    )
    (comp (ref "U16")
      (value "STM32F407VET6")
      (footprint "LC-LQFP-100_14x14x05P")
      (description "ARM")
      (libsource (lib "Miscellaneous Devices LC") (part "STM32F407VET6"))
    )
    (comp (ref "U17")
      (value "STM8S105K6T6C")
      (footprint "LC-LQFP-32_7x7x08P")
      (description "MCU")
      (libsource (lib "Miscellaneous Devices LC") (part "STM8S105K6T6C"))
    )
    (comp (ref "U18")
      (value "MSP430F149IPMRG4")
      (footprint "LC-LQFP-64_10x10x05P_Q2")
      (description "MCU")
      (libsource (lib "Miscellaneous Devices LC") (part "MSP430F149IPMRG4"))
    )
    (comp (ref "U19")
      (value "STC89C52RC-40I")
      (footprint "LC-LQFP-44_10x10x08P")
      (description "MCU")
      (libsource (lib "Miscellaneous Devices LC") (part "STC89C52RC-40I"))
    )
    (comp (ref "U20")
      (value "STM32F103C8T6")
      (footprint "LC-LQFP-48_7x7x05P")
      (description "ARM")
      (libsource (lib "Miscellaneous Devices LC") (part "STM32F103C8T6"))
    )
    (comp (ref "U21")
      (value "STM32F030C8T6")
      (footprint "LC-LQFP-48_7x7x05P")
      (description "ARM")
      (libsource (lib "Miscellaneous Devices LC") (part "STM32F030C8T6"))
    )
    (comp (ref "U22")
      (value "STC12C5A60S2-35I")
      (footprint "LC-LQFP-44_10x10x08P")
      (description "MCU")
      (libsource (lib "Miscellaneous Devices LC") (part "STC12C5A60S2-35I"))
    )
    (comp (ref "U23")
      (value "STM32F103CBT6")
      (footprint "LC-LQFP-48_7x7x05P")
      (description "ARM")
      (libsource (lib "Miscellaneous Devices LC") (part "STM32F103CBT6"))
    )
    (comp (ref "U24")
      (value "STM32L151C8T6")
      (footprint "LC-LQFP-48_7x7x05P")
      (description "ARM")
      (libsource (lib "Miscellaneous Devices LC") (part "STM32L151C8T6"))
    )
    (comp (ref "U25")
      (value "STM8L101F3P6")
      (footprint "LC-TSSOP-20")
      (description "MCU")
      (libsource (lib "Miscellaneous Devices LC") (part "STM8L101F3P6"))
    )
    (comp (ref "U26")
      (value "STM32F030F4P6")
      (footprint "LC-TSSOP-20")
      (description "ARM")
      (libsource (lib "Miscellaneous Devices LC") (part "STM32F030F4P6"))
    )
    (comp (ref "U27")
      (value "STM32F407VGT6")
      (footprint "LC-LQFP-100_14x14x05P")
      (description "ARM")
      (libsource (lib "Miscellaneous Devices LC") (part "STM32F407VGT6"))
    )
    (comp (ref "U28")
      (value "STM8S103F3P6")
      (footprint "LC-TSSOP-20")
      (description "MCU")
      (libsource (lib "Miscellaneous Devices LC") (part "STM8S103F3P6"))
    )
    (comp (ref "U29")
      (value "STM8L051F3P6TR")
      (footprint "LC-TSSOP-20")
      (description "MCU")
      (libsource (lib "Miscellaneous Devices LC") (part "STM8L051F3P6TR"))
    )
    (comp (ref "U30")
      (value "STM8S003F3P6")
      (footprint "LC-TSSOP-20")
      (description "MCU")
      (libsource (lib "Miscellaneous Devices LC") (part "STM8S003F3P6"))
    )
    (comp (ref "VR1")
      (value "AMS1117-3.3")
      (footprint "LC-SOT-223")
      (description "低压差线性稳压(LDO)")
      (libsource (lib "Miscellaneous Devices LC") (part "SOT-223 AMS1117-3.3"))
    )
    (comp (ref "VR2")
      (value "AMS1117-5.0")
      (footprint "LC-SOT-223")
      (description "低压差线性稳压(LDO)")
      (libsource (lib "Miscellaneous Devices LC") (part "SOT-223 AMS1117-5.0"))
    )
    (comp (ref "VR3")
      (value "XC6206P332MR")
      (footprint "LC-SOT-23(SOT-23-3)")
      (description "低压差线性稳压(LDO)")
      (libsource (lib "Miscellaneous Devices LC") (part "SOT-23 XC6206P332MR"))
    )
    (comp (ref "VR4")
      (value "78L05G-AB3-R")
      (footprint "LC-SOT-89(SOT-89-3)")
      (description "低压差线性稳压(LDO)")
      (libsource (lib "Miscellaneous Devices LC") (part "SOT-89 78L05G-AB3-R"))
    )
    (comp (ref "VR5")
      (value "78L12G-AB3-R")
      (footprint "LC-SOT-89(SOT-89-3)")
      (description "低压差线性稳压(LDO)")
      (libsource (lib "Miscellaneous Devices LC") (part "SOT-89 78L12G-AB3-R"))
    )
    (comp (ref "VR6")
      (value "HT7533-1")
      (footprint "LC-SOT-89(SOT-89-3)")
      (description "低压差线性稳压(LDO)")
      (libsource (lib "Miscellaneous Devices LC") (part "SOT-89 HT7533-1"))
    )
    (comp (ref "VR7")
      (value "HT7550-1")
      (footprint "LC-SOT-89(SOT-89-3)")
      (description "低压差线性稳压(LDO)")
      (libsource (lib "Miscellaneous Devices LC") (part "SOT-89 HT7550-1"))
    )
    (comp (ref "VR8")
      (value "L78M05ABDT-TR")
      (footprint "LC-TO-252-2-180")
      (description "低压差线性稳压(LDO)")
      (libsource (lib "Miscellaneous Devices LC") (part "TO-252-2 L78M05ABDT-TR"))
    )
    (comp (ref "VR9")
      (value "LM317AL-TN3-R")
      (footprint "LC-TO-252-2-180")
      (description "低压差线性稳压(LDO)")
      (libsource (lib "Miscellaneous Devices LC") (part "TO-252-2 LM317AL-TN3-R"))
    )
  )
  (nets
    (net (code "1") (name "Net-(D4-PadK)") (class "Default")
      (node (ref "D4") (pin "K") (pinfunction "K_K") (pintype "passive"))
      (node (ref "D5") (pin "A") (pinfunction "A_A") (pintype "passive"))
    )
    (net (code "2") (name "Net-(D6-PadK)") (class "Default")
      (node (ref "D6") (pin "K") (pinfunction "K_K") (pintype "passive"))
      (node (ref "D7") (pin "A") (pinfunction "A_A") (pintype "passive"))
    )
    (net (code "3") (name "Net-(D8-PadK)") (class "Default")
      (node (ref "D8") (pin "K") (pinfunction "K_K") (pintype "passive"))
      (node (ref "D9") (pin "A") (pinfunction "A_A") (pintype "passive"))
    )
    (net (code "4") (name "Net-(D10-PadK)") (class "Default")
      (node (ref "D10") (pin "K") (pinfunction "K_K") (pintype "passive"))
      (node (ref "D11") (pin "A") (pinfunction "A_A") (pintype "passive"))
    )
    (net (code "5") (name "Net-(D11-PadK)") (class "Default")
      (node (ref "D11") (pin "K") (pinfunction "K_K") (pintype "passive"))
      (node (ref "D12") (pin "A") (pinfunction "A_A") (pintype "passive"))
    )
    (net (code "6") (name "Net-(Q8-D-Pad2)") (class "Default")
      (node (ref "Q8") (pin "2") (pinfunction "D_2") (pintype "passive"))
      (node (ref "Q8") (pin "5") (pinfunction "D_5") (pintype "passive"))
    )
    (net (code "7") (name "Net-(Q9-G)") (class "Default")
      (node (ref "Q9") (pin "1") (pinfunction "G_1") (pintype "passive"))
      (node (ref "U9") (pin "44") (pinfunction "PG1/CAN_RX_44") (pintype "bidirectional"))
    )
    (net (code "8") (name "Net-(Q15-D-Pad1)") (class "Default")
      (node (ref "Q15") (pin "1") (pinfunction "D_1") (pintype "passive"))
      (node (ref "Q15") (pin "8") (pinfunction "D_8") (pintype "passive"))
    )
    (net (code "9") (name "Net-(Q16-D)") (class "Default")
      (node (ref "Q16") (pin "3") (pinfunction "D_3") (pintype "passive"))
      (node (ref "R192") (pin "1") (pinfunction "1_1") (pintype "passive"))
    )
    (net (code "10") (name "Net-(R193-Pad2)") (class "Default")
      (node (ref "R193") (pin "2") (pinfunction "2_2") (pintype "passive"))
      (node (ref "R194") (pin "1") (pinfunction "1_1") (pintype "passive"))
    )
    (net (code "11") (name "Net-(R195-Pad2)") (class "Default")
      (node (ref "R195") (pin "2") (pinfunction "2_2") (pintype "passive"))
      (node (ref "R196") (pin "1") (pinfunction "1_1") (pintype "passive"))
    )
    (net (code "12") (name "Net-(R200-Pad2)") (class "Default")
      (node (ref "R200") (pin "2") (pinfunction "2_2") (pintype "passive"))
      (node (ref "R201") (pin "1") (pinfunction "1_1") (pintype "passive"))
    )
    (net (code "13") (name "Net-(R203-Pad2)") (class "Default")
      (node (ref "R203") (pin "2") (pinfunction "2_2") (pintype "passive"))
      (node (ref "R204") (pin "1") (pinfunction "1_1") (pintype "passive"))
    )
    (net (code "14") (name "Net-(R205-Pad2)") (class "Default")
      (node (ref "R205") (pin "2") (pinfunction "2_2") (pintype "passive"))
      (node (ref "R206") (pin "1") (pinfunction "1_1") (pintype "passive"))
    )
    (net (code "15") (name "Net-(R207-Pad2)") (class "Default")
      (node (ref "R207") (pin "2") (pinfunction "2_2") (pintype "passive"))
      (node (ref "R208") (pin "1") (pinfunction "1_1") (pintype "passive"))
    )
    (net (code "16") (name "Net-(R209-Pad2)") (class "Default")
      (node (ref "R209") (pin "2") (pinfunction "2_2") (pintype "passive"))
      (node (ref "R210") (pin "1") (pinfunction "1_1") (pintype "passive"))
    )
    (net (code "17") (name "Net-(R212-Pad2)") (class "Default")
      (node (ref "R212") (pin "2") (pinfunction "2_2") (pintype "passive"))
      (node (ref "R213") (pin "1") (pinfunction "1_1") (pintype "passive"))
    )
    (net (code "18") (name "Net-(R214-Pad2)") (class "Default")
      (node (ref "R214") (pin "2") (pinfunction "2_2") (pintype "passive"))
      (node (ref "R215") (pin "1") (pinfunction "1_1") (pintype "passive"))
    )
    (net (code "19") (name "Net-(R216-Pad2)") (class "Default")
      (node (ref "R216") (pin "2") (pinfunction "2_2") (pintype "passive"))
      (node (ref "R217") (pin "1") (pinfunction "1_1") (pintype "passive"))
    )
    (net (code "20") (name "Net-(R219-Pad2)") (class "Default")
      (node (ref "R219") (pin "2") (pinfunction "2_2") (pintype "passive"))
      (node (ref "R220") (pin "1") (pinfunction "1_1") (pintype "passive"))
    )
    (net (code "21") (name "Net-(R221-Pad2)") (class "Default")
      (node (ref "R221") (pin "2") (pinfunction "2_2") (pintype "passive"))
      (node (ref "R222") (pin "1") (pinfunction "1_1") (pintype "passive"))
    )
    (net (code "22") (name "Net-(R223-Pad2)") (class "Default")
      (node (ref "R223") (pin "2") (pinfunction "2_2") (pintype "passive"))
      (node (ref "R224") (pin "1") (pinfunction "1_1") (pintype "passive"))
    )
    (net (code "23") (name "Net-(R226-Pad2)") (class "Default")
      (node (ref "R226") (pin "2") (pinfunction "2_2") (pintype "passive"))
      (node (ref "R227") (pin "1") (pinfunction "1_1") (pintype "passive"))
    )
    (net (code "24") (name "Net-(R228-Pad2)") (class "Default")
      (node (ref "R228") (pin "2") (pinfunction "2_2") (pintype "passive"))
      (node (ref "R229") (pin "1") (pinfunction "1_1") (pintype "passive"))
    )
    (net (code "25") (name "Net-(R230-Pad2)") (class "Default")
      (node (ref "R230") (pin "2") (pinfunction "2_2") (pintype "passive"))
      (node (ref "R231") (pin "1") (pinfunction "1_1") (pintype "passive"))
    )
    (net (code "26") (name "Net-(R232-Pad2)") (class "Default")
      (node (ref "R232") (pin "2") (pinfunction "2_2") (pintype "passive"))
      (node (ref "R233") (pin "1") (pinfunction "1_1") (pintype "passive"))
    )
    (net (code "27") (name "Net-(R235-Pad2)") (class "Default")
      (node (ref "R235") (pin "2") (pinfunction "2_2") (pintype "passive"))
      (node (ref "R236") (pin "1") (pinfunction "1_1") (pintype "passive"))
    )
    (net (code "28") (name "Net-(R237-Pad2)") (class "Default")
      (node (ref "R237") (pin "2") (pinfunction "2_2") (pintype "passive"))
      (node (ref "R238") (pin "1") (pinfunction "1_1") (pintype "passive"))
    )
    (net (code "29") (name "Net-(R239-Pad2)") (class "Default")
      (node (ref "R239") (pin "2") (pinfunction "2_2") (pintype "passive"))
      (node (ref "R240") (pin "1") (pinfunction "1_1") (pintype "passive"))
    )
    (net (code "30") (name "Net-(R255-Pad2)") (class "Default")
      (node (ref "R255") (pin "2") (pinfunction "2_2") (pintype "passive"))
      (node (ref "R256") (pin "1") (pinfunction "1_1") (pintype "passive"))
    )
    (net (code "31") (name "Net-(R257-Pad2)") (class "Default")
      (node (ref "R257") (pin "2") (pinfunction "2_2") (pintype "passive"))
      (node (ref "R258") (pin "1") (pinfunction "1_1") (pintype "passive"))
    )
    (net (code "32") (name "Net-(R259-Pad2)") (class "Default")
      (node (ref "R259") (pin "2") (pinfunction "2_2") (pintype "passive"))
      (node (ref "R260") (pin "1") (pinfunction "1_1") (pintype "passive"))
    )
    (net (code "33") (name "Net-(R264-Pad2)") (class "Default")
      (node (ref "R264") (pin "2") (pinfunction "2_2") (pintype "passive"))
      (node (ref "R265") (pin "1") (pinfunction "1_1") (pintype "passive"))
    )
    (net (code "34") (name "Net-(R266-Pad2)") (class "Default")
      (node (ref "R266") (pin "2") (pinfunction "2_2") (pintype "passive"))
      (node (ref "R267") (pin "1") (pinfunction "1_1") (pintype "passive"))
    )
    (net (code "35") (name "Net-(R269-Pad2)") (class "Default")
      (node (ref "R269") (pin "2") (pinfunction "2_2") (pintype "passive"))
      (node (ref "R270") (pin "1") (pinfunction "1_1") (pintype "passive"))
    )
    (net (code "36") (name "Net-(R271-Pad2)") (class "Default")
      (node (ref "R271") (pin "2") (pinfunction "2_2") (pintype "passive"))
      (node (ref "R272") (pin "1") (pinfunction "1_1") (pintype "passive"))
    )
    (net (code "37") (name "Net-(R273-Pad2)") (class "Default")
      (node (ref "R273") (pin "2") (pinfunction "2_2") (pintype "passive"))
      (node (ref "R274") (pin "1") (pinfunction "1_1") (pintype "passive"))
    )
    (net (code "38") (name "Net-(R275-Pad2)") (class "Default")
      (node (ref "R275") (pin "2") (pinfunction "2_2") (pintype "passive"))
      (node (ref "R276") (pin "1") (pinfunction "1_1") (pintype "passive"))
    )
    (net (code "39") (name "Net-(R277-Pad2)") (class "Default")
      (node (ref "R277") (pin "2") (pinfunction "2_2") (pintype "passive"))
      (node (ref "R278") (pin "1") (pinfunction "1_1") (pintype "passive"))
    )
    (net (code "40") (name "Net-(R280-Pad2)") (class "Default")
      (node (ref "R280") (pin "2") (pinfunction "2_2") (pintype "passive"))
      (node (ref "R281") (pin "1") (pinfunction "1_1") (pintype "passive"))
    )
    (net (code "41") (name "Net-(R282-Pad2)") (class "Default")
      (node (ref "R282") (pin "2") (pinfunction "2_2") (pintype "passive"))
      (node (ref "R283") (pin "1") (pinfunction "1_1") (pintype "passive"))
    )
    (net (code "42") (name "Net-(R284-Pad2)") (class "Default")
      (node (ref "R284") (pin "2") (pinfunction "2_2") (pintype "passive"))
      (node (ref "R285") (pin "1") (pinfunction "1_1") (pintype "passive"))
    )
    (net (code "43") (name "Net-(R286-Pad2)") (class "Default")
      (node (ref "R286") (pin "2") (pinfunction "2_2") (pintype "passive"))
      (node (ref "R287") (pin "1") (pinfunction "1_1") (pintype "passive"))
    )
    (net (code "44") (name "Net-(R289-Pad2)") (class "Default")
      (node (ref "R289") (pin "2") (pinfunction "2_2") (pintype "passive"))
      (node (ref "R290") (pin "1") (pinfunction "1_1") (pintype "passive"))
    )
    (net (code "45") (name "Net-(R291-Pad2)") (class "Default")
      (node (ref "R291") (pin "2") (pinfunction "2_2") (pintype "passive"))
      (node (ref "R292") (pin "1") (pinfunction "1_1") (pintype "passive"))
    )
    (net (code "46") (name "Net-(R293-Pad2)") (class "Default")
      (node (ref "R293") (pin "2") (pinfunction "2_2") (pintype "passive"))
      (node (ref "R294") (pin "1") (pinfunction "1_1") (pintype "passive"))
    )
    (net (code "47") (name "Net-(R296-Pad2)") (class "Default")
      (node (ref "R296") (pin "2") (pinfunction "2_2") (pintype "passive"))
      (node (ref "R297") (pin "1") (pinfunction "1_1") (pintype "passive"))
    )
    (net (code "48") (name "Net-(R298-Pad2)") (class "Default")
      (node (ref "R298") (pin "2") (pinfunction "2_2") (pintype "passive"))
      (node (ref "R299") (pin "1") (pinfunction "1_1") (pintype "passive"))
    )
    (net (code "49") (name "Net-(R300-Pad2)") (class "Default")
      (node (ref "R300") (pin "2") (pinfunction "2_2") (pintype "passive"))
      (node (ref "R301") (pin "1") (pinfunction "1_1") (pintype "passive"))
    )
    (net (code "50") (name "Net-(R303-Pad2)") (class "Default")
      (node (ref "R303") (pin "2") (pinfunction "2_2") (pintype "passive"))
      (node (ref "R304") (pin "1") (pinfunction "1_1") (pintype "passive"))
    )
    (net (code "51") (name "Net-(R305-Pad2)") (class "Default")
      (node (ref "R305") (pin "2") (pinfunction "2_2") (pintype "passive"))
      (node (ref "R306") (pin "1") (pinfunction "1_1") (pintype "passive"))
    )
    (net (code "52") (name "Net-(R307-Pad2)") (class "Default")
      (node (ref "R307") (pin "2") (pinfunction "2_2") (pintype "passive"))
      (node (ref "R308") (pin "1") (pinfunction "1_1") (pintype "passive"))
    )
    (net (code "53") (name "Net-(R309-Pad2)") (class "Default")
      (node (ref "R309") (pin "2") (pinfunction "2_2") (pintype "passive"))
      (node (ref "R310") (pin "1") (pinfunction "1_1") (pintype "passive"))
    )
    (net (code "54") (name "Net-(R312-Pad2)") (class "Default")
      (node (ref "R312") (pin "2") (pinfunction "2_2") (pintype "passive"))
      (node (ref "R313") (pin "1") (pinfunction "1_1") (pintype "passive"))
    )
    (net (code "55") (name "Net-(R314-Pad2)") (class "Default")
      (node (ref "R314") (pin "2") (pinfunction "2_2") (pintype "passive"))
      (node (ref "R315") (pin "1") (pinfunction "1_1") (pintype "passive"))
    )
    (net (code "56") (name "Net-(R316-Pad2)") (class "Default")
      (node (ref "R316") (pin "2") (pinfunction "2_2") (pintype "passive"))
      (node (ref "R317") (pin "1") (pinfunction "1_1") (pintype "passive"))
    )
    (net (code "57") (name "Net-(U1A-BOOT0)") (class "Default")
      (node (ref "U1") (pin "94") (pinfunction "BOOT0_94") (pintype "input"))
      (node (ref "U6") (pin "42") (pinfunction "PE11_42") (pintype "bidirectional"))
    )
    (net (code "58") (name "Net-(U1A-NRST)") (class "Default")
      (node (ref "U1") (pin "14") (pinfunction "NRST_14") (pintype "bidirectional"))
      (node (ref "U6") (pin "44") (pinfunction "PE13_44") (pintype "bidirectional"))
    )
    (net (code "59") (name "Net-(U1A-OSC_IN)") (class "Default")
      (node (ref "U1") (pin "12") (pinfunction "OSC_IN_12") (pintype "input"))
      (node (ref "U6") (pin "39") (pinfunction "PE8_39") (pintype "bidirectional"))
    )
    (net (code "60") (name "Net-(U1A-OSC_OUT)") (class "Default")
      (node (ref "U1") (pin "13") (pinfunction "OSC_OUT_13") (pintype "output"))
      (node (ref "U6") (pin "40") (pinfunction "PE9_40") (pintype "bidirectional"))
    )
    (net (code "61") (name "Net-(U1A-PB0)") (class "Default")
      (node (ref "U1") (pin "35") (pinfunction "PB0_35") (pintype "bidirectional"))
      (node (ref "U6") (pin "23") (pinfunction "PA0-WKUP_23") (pintype "bidirectional"))
    )
    (net (code "62") (name "Net-(U1A-PB1)") (class "Default")
      (node (ref "U1") (pin "36") (pinfunction "PB1_36") (pintype "bidirectional"))
      (node (ref "U6") (pin "24") (pinfunction "PA1_24") (pintype "bidirectional"))
    )
    (net (code "63") (name "Net-(U1A-PB2)") (class "Default")
      (node (ref "U1") (pin "37") (pinfunction "PB2_37") (pintype "bidirectional"))
      (node (ref "U6") (pin "25") (pinfunction "PA2_25") (pintype "bidirectional"))
    )
    (net (code "64") (name "Net-(U1A-PB3)") (class "Default")
      (node (ref "U1") (pin "89") (pinfunction "PB3_89") (pintype "bidirectional"))
      (node (ref "U6") (pin "26") (pinfunction "PA3_26") (pintype "bidirectional"))
    )
    (net (code "65") (name "Net-(U1A-PB4)") (class "Default")
      (node (ref "U1") (pin "90") (pinfunction "PB4_90") (pintype "bidirectional"))
      (node (ref "U6") (pin "29") (pinfunction "PA4_29") (pintype "bidirectional"))
    )
    (net (code "66") (name "Net-(U1A-PB5)") (class "Default")
      (node (ref "U1") (pin "91") (pinfunction "PB5_91") (pintype "bidirectional"))
      (node (ref "U6") (pin "30") (pinfunction "PA5_30") (pintype "bidirectional"))
    )
    (net (code "67") (name "Net-(U1A-PB6)") (class "Default")
      (node (ref "U1") (pin "92") (pinfunction "PB6_92") (pintype "bidirectional"))
      (node (ref "U6") (pin "31") (pinfunction "PA6_31") (pintype "bidirectional"))
    )
    (net (code "68") (name "Net-(U1A-PB7)") (class "Default")
      (node (ref "U1") (pin "93") (pinfunction "PB7_93") (pintype "bidirectional"))
      (node (ref "U6") (pin "32") (pinfunction "PA7_32") (pintype "bidirectional"))
    )
    (net (code "69") (name "Net-(U1A-PB8)") (class "Default")
      (node (ref "U1") (pin "95") (pinfunction "PB8_95") (pintype "bidirectional"))
      (node (ref "U6") (pin "67") (pinfunction "PA8_67") (pintype "bidirectional"))
    )
    (net (code "70") (name "Net-(U1A-PB9)") (class "Default")
      (node (ref "U1") (pin "96") (pinfunction "PB9_96") (pintype "bidirectional"))
      (node (ref "U6") (pin "68") (pinfunction "PA9_68") (pintype "bidirectional"))
    )
    (net (code "71") (name "Net-(U1A-PB10)") (class "Default")
      (node (ref "U1") (pin "47") (pinfunction "PB10_47") (pintype "bidirectional"))
      (node (ref "U6") (pin "69") (pinfunction "PA10_69") (pintype "bidirectional"))
    )
    (net (code "72") (name "Net-(U1A-PB11)") (class "Default")
      (node (ref "U1") (pin "48") (pinfunction "PB11_48") (pintype "bidirectional"))
      (node (ref "U6") (pin "70") (pinfunction "PA11_70") (pintype "bidirectional"))
    )
    (net (code "73") (name "Net-(U1A-PB12)") (class "Default")
      (node (ref "U1") (pin "51") (pinfunction "PB12_51") (pintype "bidirectional"))
      (node (ref "U6") (pin "71") (pinfunction "PA12_71") (pintype "bidirectional"))
    )
    (net (code "74") (name "Net-(U1A-PB13)") (class "Default")
      (node (ref "U1") (pin "52") (pinfunction "PB13_52") (pintype "bidirectional"))
      (node (ref "U6") (pin "72") (pinfunction "PA13_72") (pintype "bidirectional"))
    )
    (net (code "75") (name "Net-(U1A-PB14)") (class "Default")
      (node (ref "U1") (pin "53") (pinfunction "PB14_53") (pintype "bidirectional"))
      (node (ref "U6") (pin "76") (pinfunction "PA14_76") (pintype "bidirectional"))
    )
    (net (code "76") (name "Net-(U1A-PB15)") (class "Default")
      (node (ref "U1") (pin "54") (pinfunction "PB15_54") (pintype "bidirectional"))
      (node (ref "U6") (pin "77") (pinfunction "PA15_77") (pintype "bidirectional"))
    )
    (net (code "77") (name "Net-(U1A-PD0)") (class "Default")
      (node (ref "U1") (pin "81") (pinfunction "PD0_81") (pintype "bidirectional"))
      (node (ref "U6") (pin "15") (pinfunction "PC0_15") (pintype "bidirectional"))
    )
    (net (code "78") (name "Net-(U1A-PD1)") (class "Default")
      (node (ref "U1") (pin "82") (pinfunction "PD1_82") (pintype "bidirectional"))
      (node (ref "U6") (pin "16") (pinfunction "PC1_16") (pintype "bidirectional"))
    )
    (net (code "79") (name "Net-(U1A-PD2)") (class "Default")
      (node (ref "U1") (pin "83") (pinfunction "PD2_83") (pintype "bidirectional"))
      (node (ref "U6") (pin "17") (pinfunction "PC2_17") (pintype "bidirectional"))
    )
    (net (code "80") (name "Net-(U1A-PD3)") (class "Default")
      (node (ref "U1") (pin "84") (pinfunction "PD3_84") (pintype "bidirectional"))
      (node (ref "U6") (pin "18") (pinfunction "PC3_18") (pintype "bidirectional"))
    )
    (net (code "81") (name "Net-(U1A-PD4)") (class "Default")
      (node (ref "U1") (pin "85") (pinfunction "PD4_85") (pintype "bidirectional"))
      (node (ref "U6") (pin "33") (pinfunction "PC4_33") (pintype "bidirectional"))
    )
    (net (code "82") (name "Net-(U1A-PD5)") (class "Default")
      (node (ref "U1") (pin "86") (pinfunction "PD5_86") (pintype "bidirectional"))
      (node (ref "U6") (pin "34") (pinfunction "PC5_34") (pintype "bidirectional"))
    )
    (net (code "83") (name "Net-(U1A-PD6)") (class "Default")
      (node (ref "U1") (pin "87") (pinfunction "PD6_87") (pintype "bidirectional"))
      (node (ref "U6") (pin "63") (pinfunction "PC6_63") (pintype "bidirectional"))
    )
    (net (code "84") (name "Net-(U1A-PD7)") (class "Default")
      (node (ref "U1") (pin "88") (pinfunction "PD7_88") (pintype "bidirectional"))
      (node (ref "U6") (pin "64") (pinfunction "PC7_64") (pintype "bidirectional"))
    )
    (net (code "85") (name "Net-(U1A-PD8)") (class "Default")
      (node (ref "R248") (pin "2") (pinfunction "2_2") (pintype "passive"))
      (node (ref "U1") (pin "55") (pinfunction "PD8_55") (pintype "bidirectional"))
      (node (ref "U6") (pin "65") (pinfunction "PC8_65") (pintype "bidirectional"))
    )
    (net (code "86") (name "Net-(U1A-PD9)") (class "Default")
      (node (ref "U1") (pin "56") (pinfunction "PD9_56") (pintype "bidirectional"))
      (node (ref "U6") (pin "66") (pinfunction "PC9_66") (pintype "bidirectional"))
    )
    (net (code "87") (name "Net-(U1A-PD10)") (class "Default")
      (node (ref "U1") (pin "57") (pinfunction "PD10_57") (pintype "bidirectional"))
      (node (ref "U6") (pin "78") (pinfunction "PC10_78") (pintype "bidirectional"))
    )
    (net (code "88") (name "Net-(U1A-PD11)") (class "Default")
      (node (ref "U1") (pin "58") (pinfunction "PD11_58") (pintype "bidirectional"))
      (node (ref "U6") (pin "79") (pinfunction "PC11_79") (pintype "bidirectional"))
    )
    (net (code "89") (name "Net-(U1A-PD12)") (class "Default")
      (node (ref "U1") (pin "59") (pinfunction "PD12_59") (pintype "bidirectional"))
      (node (ref "U6") (pin "80") (pinfunction "PC12_80") (pintype "bidirectional"))
    )
    (net (code "90") (name "Net-(U1A-PD13)") (class "Default")
      (node (ref "U1") (pin "60") (pinfunction "PD13_60") (pintype "bidirectional"))
      (node (ref "U6") (pin "7") (pinfunction "PC13-TAMPER-RTC_7") (pintype "bidirectional"))
    )
    (net (code "91") (name "Net-(U1A-PD14)") (class "Default")
      (node (ref "U1") (pin "61") (pinfunction "PD14_61") (pintype "bidirectional"))
      (node (ref "U6") (pin "8") (pinfunction "PC14-OSC32_IN_8") (pintype "bidirectional"))
    )
    (net (code "92") (name "Net-(U1A-PD15)") (class "Default")
      (node (ref "U1") (pin "62") (pinfunction "PD15_62") (pintype "bidirectional"))
      (node (ref "U6") (pin "9") (pinfunction "PC15-OSC32_OUT_9") (pintype "bidirectional"))
    )
    (net (code "93") (name "Net-(U2A-PC8)") (class "Default")
      (node (ref "R246") (pin "1") (pinfunction "1_1") (pintype "passive"))
      (node (ref "U2") (pin "65") (pinfunction "PC8_65") (pintype "bidirectional"))
    )
    (net (code "94") (name "Net-(U2A-PD8)") (class "Default")
      (node (ref "R249") (pin "2") (pinfunction "2_2") (pintype "passive"))
      (node (ref "R250") (pin "1") (pinfunction "1_1") (pintype "passive"))
      (node (ref "U2") (pin "55") (pinfunction "PD8_55") (pintype "bidirectional"))
    )
    (net (code "95") (name "Net-(U3A-PD8)") (class "Default")
      (node (ref "R250") (pin "2") (pinfunction "2_2") (pintype "passive"))
      (node (ref "U3") (pin "55") (pinfunction "PD8_55") (pintype "bidirectional"))
    )
    (net (code "96") (name "Net-(U4-CAN1_RX{slash}FSMC_D2{slash}PD0)") (class "Default")
      (node (ref "R198") (pin "5") (pinfunction "5_5") (pintype "passive"))
      (node (ref "U4") (pin "114") (pinfunction "CAN1_RX/FSMC_D2/PD0_114") (pintype "bidirectional"))
    )
    (net (code "97") (name "Net-(U4-CAN1_RX{slash}I2C1_SCL{slash}SDIO_D4{slash}TIM4_CH3{slash}PB8)") (class "Default")
      (node (ref "U4") (pin "139") (pinfunction "CAN1_RX/I2C1_SCL/SDIO_D4/TIM4_CH3/PB8_139") (pintype "bidirectional"))
      (node (ref "U7") (pin "7") (pinfunction "VDD_7") (pintype "power_in"))
    )
    (net (code "98") (name "Net-(U4-CAN1_TX{slash}FSMC_D3{slash}PD1)") (class "Default")
      (node (ref "R198") (pin "6") (pinfunction "6_6") (pintype "passive"))
      (node (ref "U4") (pin "115") (pinfunction "CAN1_TX/FSMC_D3/PD1_115") (pintype "bidirectional"))
      (node (ref "U7") (pin "9") (pinfunction "PA3(HS)/TIM2_CH3[TIM3_CH1]_9") (pintype "bidirectional"))
    )
    (net (code "99") (name "Net-(U4-FSMC_INT3{slash}PG7)") (class "Default")
      (node (ref "U4") (pin "92") (pinfunction "FSMC_INT3/PG7_92") (pintype "bidirectional"))
      (node (ref "U7") (pin "15") (pinfunction "PB7/AIN7_15") (pintype "bidirectional"))
    )
    (net (code "100") (name "Net-(U4-FSMC_NCE2{slash}FSMC_NE1{slash}PD7)") (class "Default")
      (node (ref "U4") (pin "123") (pinfunction "FSMC_NCE2/FSMC_NE1/PD7_123") (pintype "bidirectional"))
      (node (ref "U7") (pin "1") (pinfunction "NRST_1") (pintype "bidirectional"))
    )
    (net (code "101") (name "Net-(U4-FSMC_NE3{slash}FSMC_NCE4_1{slash}PG10)") (class "Default")
      (node (ref "U4") (pin "125") (pinfunction "FSMC_NE3/FSMC_NCE4_1/PG10_125") (pintype "bidirectional"))
      (node (ref "U7") (pin "6") (pinfunction "VCAP_6") (pintype "power_in"))
    )
    (net (code "102") (name "Net-(U4-FSMC_SDCKE1{slash}SPI1_MOSI{slash}I2S3_SD{slash}SPI3_MOSI{slash}CAN2_RX{slash}PB5)") (class "Default")
      (node (ref "U4") (pin "135") (pinfunction "FSMC_SDCKE1/SPI1_MOSI/I2S3_SD/SPI3_MOSI/CAN2_RX/PB5_135") (pintype "bidirectional"))
      (node (ref "U7") (pin "32") (pinfunction "VDDio_2_32") (pintype "power_in"))
    )
    (net (code "103") (name "Net-(U4-FSMC_SDNCAS{slash}PG15)") (class "Default")
      (node (ref "U4") (pin "132") (pinfunction "FSMC_SDNCAS/PG15_132") (pintype "passive"))
      (node (ref "U7") (pin "5") (pinfunction "VSS_5") (pintype "power_in"))
    )
    (net (code "104") (name "Net-(U4-I2C3_SCL{slash}MCO1{slash}TIM1_CH1{slash}USART1_CK{slash}PA8)") (class "Default")
      (node (ref "U4") (pin "100") (pinfunction "I2C3_SCL/MCO1/TIM1_CH1/USART1_CK/PA8_100") (pintype "bidirectional"))
      (node (ref "U7") (pin "19") (pinfunction "PB3/AIN3[TIM1_ETR]_19") (pintype "bidirectional"))
    )
    (net (code "105") (name "Net-(U4-SDIO_CMD{slash}UART5_RX{slash}{slash}TIM3_ETR{slash}PD2)") (class "Default")
      (node (ref "R198") (pin "7") (pinfunction "7_7") (pintype "passive"))
      (node (ref "U4") (pin "116") (pinfunction "SDIO_CMD/UART5_RX//TIM3_ETR/PD2_116") (pintype "bidirectional"))
    )
    (net (code "106") (name "Net-(U4-SDIO_D0{slash}TIM8_CH3{slash}PC8)") (class "Default")
      (node (ref "U4") (pin "98") (pinfunction "SDIO_D0/TIM8_CH3/PC8_98") (pintype "bidirectional"))
      (node (ref "U7") (pin "18") (pinfunction "PB4/AIN4[I2C_SCL]_18") (pintype "bidirectional"))
    )
    (net (code "107") (name "Net-(U4-SPI2_CLK{slash}FSMC_CLK{slash}PD3)") (class "Default")
      (node (ref "R198") (pin "8") (pinfunction "8_8") (pintype "passive"))
      (node (ref "U4") (pin "117") (pinfunction "SPI2_CLK/FSMC_CLK/PD3_117") (pintype "bidirectional"))
    )
    (net (code "108") (name "Net-(U4-SPI3_MOSI{slash}SDIO_CK{slash}UART5_TX{slash}PC12)") (class "Default")
      (node (ref "U4") (pin "113") (pinfunction "SPI3_MOSI/SDIO_CK/UART5_TX/PC12_113") (pintype "bidirectional"))
      (node (ref "U7") (pin "10") (pinfunction "PA4(HS)_10") (pintype "bidirectional"))
    )
    (net (code "109") (name "Net-(U4-SPI6_CLK{slash}FSMC_A24{slash}PG13)") (class "Default")
      (node (ref "U4") (pin "128") (pinfunction "SPI6_CLK/FSMC_A24/PG13_128") (pintype "bidirectional"))
      (node (ref "U7") (pin "31") (pinfunction "VSSio_2_31") (pintype "power_in"))
    )
    (net (code "110") (name "Net-(U4-SWCLK{slash}JTCK{slash}PA14)") (class "Default")
      (node (ref "U4") (pin "109") (pinfunction "SWCLK/JTCK/PA14_109") (pintype "bidirectional"))
      (node (ref "U7") (pin "12") (pinfunction "PA6(HS)_12") (pintype "bidirectional"))
    )
    (net (code "111") (name "Net-(U4-TIM1_CH3{slash}USART1_RX{slash}PA10)") (class "Default")
      (node (ref "U4") (pin "102") (pinfunction "TIM1_CH3/USART1_RX/PA10_102") (pintype "bidirectional"))
      (node (ref "U7") (pin "20") (pinfunction "PB2/AIN2[TIM1_CH3N]_20") (pintype "bidirectional"))
    )
    (net (code "112") (name "Net-(U4-UART8_TX{slash}FSMC_NBL1{slash}PE1)") (class "Default")
      (node (ref "U4") (pin "142") (pinfunction "UART8_TX/FSMC_NBL1/PE1_142") (pintype "bidirectional"))
      (node (ref "U7") (pin "14") (pinfunction "VSSA_14") (pintype "power_in"))
    )
    (net (code "113") (name "Net-(U4-USART1_RX{slash}TIM4_CH2{slash}FSMC_NL{slash}I2C1_SDA{slash}PB7)") (class "Default")
      (node (ref "U4") (pin "137") (pinfunction "USART1_RX/TIM4_CH2/FSMC_NL/I2C1_SDA/PB7_137") (pintype "bidirectional"))
      (node (ref "U7") (pin "8") (pinfunction "VDDio_1_8") (pintype "power_in"))
    )
    (net (code "114") (name "Net-(U4-USART2_TX{slash}FSMC_NWE{slash}PD5)") (class "Default")
      (node (ref "U4") (pin "119") (pinfunction "USART2_TX/FSMC_NWE/PD5_119") (pintype "bidirectional"))
      (node (ref "U7") (pin "3") (pinfunction "OSCOUT/PA2_3") (pintype "bidirectional"))
    )
    (net (code "115") (name "Net-(U4-USART3_TX{slash}SDIO_D2{slash}UART4_TX{slash}PC10)") (class "Default")
      (node (ref "U4") (pin "111") (pinfunction "USART3_TX/SDIO_D2/UART4_TX/PC10_111") (pintype "bidirectional"))
      (node (ref "U7") (pin "11") (pinfunction "PA5(HS)_11") (pintype "bidirectional"))
    )
    (net (code "116") (name "Net-(U4-USART6_TX{slash}SDIO_D6{slash}TIM8_CH1{slash}I2S2_MCK{slash}PC6)") (class "Default")
      (node (ref "U4") (pin "96") (pinfunction "USART6_TX/SDIO_D6/TIM8_CH1/I2S2_MCK/PC6_96") (pintype "bidirectional"))
      (node (ref "U7") (pin "17") (pinfunction "PB5/AIN5[I2C_SDA]_17") (pintype "bidirectional"))
    )
    (net (code "117") (name "Net-(U4-USBDP{slash}TIM1_ETR{slash}CAN1_TX{slash}USART1_RTS{slash}PA12)") (class "Default")
      (node (ref "U4") (pin "104") (pinfunction "USBDP/TIM1_ETR/CAN1_TX/USART1_RTS/PA12_104") (pintype "bidirectional"))
      (node (ref "U7") (pin "21") (pinfunction "PB1/AIN1[TIM1_CH2N]_21") (pintype "bidirectional"))
    )
    (net (code "118") (name "Net-(U4-VCAP_2)") (class "Default")
      (node (ref "U4") (pin "106") (pinfunction "VCAP_2_106") (pintype "tri_state"))
      (node (ref "U7") (pin "22") (pinfunction "PB0/AIN0[TIM1_CH1N]_22") (pintype "bidirectional"))
    )
    (net (code "119") (name "Net-(U4-VDD_3)") (class "Default")
      (node (ref "U4") (pin "144") (pinfunction "VDD_3_144") (pintype "power_in"))
      (node (ref "U7") (pin "13") (pinfunction "VDDA_13") (pintype "power_in"))
    )
    (net (code "120") (name "Net-(U4-VDD_10)") (class "Default")
      (node (ref "U4") (pin "121") (pinfunction "VDD_10_121") (pintype "power_in"))
      (node (ref "U7") (pin "2") (pinfunction "OSCIN/PA1_2") (pintype "bidirectional"))
    )
    (net (code "121") (name "Net-(U4-VSS_9)") (class "Default")
      (node (ref "U4") (pin "94") (pinfunction "VSS_9_94") (pintype "power_in"))
      (node (ref "U7") (pin "16") (pinfunction "PB6/AIN6_16") (pintype "bidirectional"))
    )
    (net (code "122") (name "Net-(U4-VSS_11)") (class "Default")
      (node (ref "U4") (pin "130") (pinfunction "VSS_11_130") (pintype "power_in"))
      (node (ref "U7") (pin "4") (pinfunction "VSSio_1_4") (pintype "power_in"))
    )
    (net (code "123") (name "Net-(U5A-PC8)") (class "Default")
      (node (ref "R248") (pin "1") (pinfunction "1_1") (pintype "passive"))
      (node (ref "U5") (pin "98") (pinfunction "PC8_98") (pintype "bidirectional"))
    )
    (net (code "124") (name "Net-(U5A-PD8)") (class "Default")
      (node (ref "R251") (pin "2") (pinfunction "2_2") (pintype "passive"))
      (node (ref "R252") (pin "1") (pinfunction "1_1") (pintype "passive"))
      (node (ref "U5") (pin "77") (pinfunction "PD8_77") (pintype "bidirectional"))
    )
    (net (code "125") (name "Net-(U6A-PD8)") (class "Default")
      (node (ref "R252") (pin "2") (pinfunction "2_2") (pintype "passive"))
      (node (ref "U6") (pin "55") (pinfunction "PD8_55") (pintype "bidirectional"))
    )
    (net (code "126") (name "Net-(U7-UART2_RX{slash}(HS)_PD6)") (class "Default")
      (node (ref "R260") (pin "2") (pinfunction "2_2") (pintype "passive"))
      (node (ref "U7") (pin "47") (pinfunction "UART2_RX/(HS)_PD6_47") (pintype "bidirectional"))
    )
    (net (code "127") (name "Net-(U9-PE4)") (class "Default")
      (node (ref "R262") (pin "2") (pinfunction "2_2") (pintype "passive"))
      (node (ref "R263") (pin "1") (pinfunction "1_1") (pintype "passive"))
      (node (ref "U9") (pin "52") (pinfunction "PE4_52") (pintype "bidirectional"))
    )
    (net (code "128") (name "Net-(U9-VREF)") (class "Default")
      (node (ref "R257") (pin "1") (pinfunction "1_1") (pintype "passive"))
      (node (ref "U9") (pin "21") (pinfunction "VREF_21") (pintype "power_in"))
    )
    (net (code "129") (name "Net-(U10A-BOOT0)") (class "Default")
      (node (ref "U1") (pin "9") (pinfunction "PC15-OSC32_OUT_9") (pintype "bidirectional"))
      (node (ref "U10") (pin "60") (pinfunction "BOOT0_60") (pintype "input"))
    )
    (net (code "130") (name "Net-(U10A-NRST)") (class "Default")
      (node (ref "U1") (pin "97") (pinfunction "PE0_97") (pintype "bidirectional"))
      (node (ref "U10") (pin "7") (pinfunction "NRST_7") (pintype "bidirectional"))
    )
    (net (code "131") (name "Net-(U10A-PB0)") (class "Default")
      (node (ref "U1") (pin "32") (pinfunction "PA7_32") (pintype "bidirectional"))
      (node (ref "U10") (pin "26") (pinfunction "PB0_26") (pintype "bidirectional"))
    )
    (net (code "132") (name "Net-(U10A-PB2)") (class "Default")
      (node (ref "U1") (pin "67") (pinfunction "PA8_67") (pintype "bidirectional"))
      (node (ref "U10") (pin "28") (pinfunction "PB2_28") (pintype "bidirectional"))
    )
    (net (code "133") (name "Net-(U10A-PB3)") (class "Default")
      (node (ref "U1") (pin "68") (pinfunction "PA9_68") (pintype "bidirectional"))
      (node (ref "U10") (pin "55") (pinfunction "PB3_55") (pintype "bidirectional"))
    )
    (net (code "134") (name "Net-(U10A-PB4)") (class "Default")
      (node (ref "U1") (pin "69") (pinfunction "PA10_69") (pintype "bidirectional"))
      (node (ref "U10") (pin "56") (pinfunction "PB4_56") (pintype "bidirectional"))
    )
    (net (code "135") (name "Net-(U10A-PB5)") (class "Default")
      (node (ref "U1") (pin "70") (pinfunction "PA11_70") (pintype "bidirectional"))
      (node (ref "U10") (pin "57") (pinfunction "PB5_57") (pintype "bidirectional"))
    )
    (net (code "136") (name "Net-(U10A-PB6)") (class "Default")
      (node (ref "U1") (pin "71") (pinfunction "PA12_71") (pintype "bidirectional"))
      (node (ref "U10") (pin "58") (pinfunction "PB6_58") (pintype "bidirectional"))
    )
    (net (code "137") (name "Net-(U10A-PB7)") (class "Default")
      (node (ref "U1") (pin "72") (pinfunction "PA13_72") (pintype "bidirectional"))
      (node (ref "U10") (pin "59") (pinfunction "PB7_59") (pintype "bidirectional"))
    )
    (net (code "138") (name "Net-(U10A-PB8)") (class "Default")
      (node (ref "U1") (pin "77") (pinfunction "PA15_77") (pintype "bidirectional"))
      (node (ref "U10") (pin "61") (pinfunction "PB8_61") (pintype "bidirectional"))
    )
    (net (code "139") (name "Net-(U10A-PB10)") (class "Default")
      (node (ref "U1") (pin "15") (pinfunction "PC0_15") (pintype "bidirectional"))
      (node (ref "U10") (pin "29") (pinfunction "PB10_29") (pintype "bidirectional"))
    )
    (net (code "140") (name "Net-(U10A-PB11)") (class "Default")
      (node (ref "U1") (pin "16") (pinfunction "PC1_16") (pintype "bidirectional"))
      (node (ref "U10") (pin "30") (pinfunction "PB11_30") (pintype "bidirectional"))
    )
    (net (code "141") (name "Net-(U10A-PB12)") (class "Default")
      (node (ref "U1") (pin "17") (pinfunction "PC2_17") (pintype "bidirectional"))
      (node (ref "U10") (pin "33") (pinfunction "PB12_33") (pintype "bidirectional"))
    )
    (net (code "142") (name "Net-(U10A-PB13)") (class "Default")
      (node (ref "U1") (pin "18") (pinfunction "PC3_18") (pintype "bidirectional"))
      (node (ref "U10") (pin "34") (pinfunction "PB13_34") (pintype "bidirectional"))
    )
    (net (code "143") (name "Net-(U10A-PB14)") (class "Default")
      (node (ref "U1") (pin "33") (pinfunction "PC4_33") (pintype "bidirectional"))
      (node (ref "U10") (pin "35") (pinfunction "PB14_35") (pintype "bidirectional"))
    )
    (net (code "144") (name "Net-(U10A-PB15)") (class "Default")
      (node (ref "U1") (pin "34") (pinfunction "PC5_34") (pintype "bidirectional"))
      (node (ref "U10") (pin "36") (pinfunction "PB15_36") (pintype "bidirectional"))
    )
    (net (code "145") (name "Net-(U10A-PC2)") (class "Default")
      (node (ref "R241") (pin "1") (pinfunction "1_1") (pintype "passive"))
      (node (ref "U10") (pin "10") (pinfunction "PC2_10") (pintype "bidirectional"))
    )
    (net (code "146") (name "Net-(U10A-PC15-OSC32_OUT)") (class "Default")
      (node (ref "R318") (pin "1") (pinfunction "1_1") (pintype "passive"))
      (node (ref "U10") (pin "4") (pinfunction "PC15-OSC32_OUT_4") (pintype "bidirectional"))
    )
    (net (code "147") (name "Net-(U10A-PD0-OSC_IN)") (class "Default")
      (node (ref "U1") (pin "64") (pinfunction "PC7_64") (pintype "bidirectional"))
      (node (ref "U10") (pin "5") (pinfunction "PD0-OSC_IN_5") (pintype "bidirectional"))
    )
    (net (code "148") (name "Net-(U10A-PD2)") (class "Default")
      (node (ref "R244") (pin "2") (pinfunction "2_2") (pintype "passive"))
      (node (ref "R245") (pin "1") (pinfunction "1_1") (pintype "passive"))
      (node (ref "U1") (pin "65") (pinfunction "PC8_65") (pintype "bidirectional"))
      (node (ref "U10") (pin "54") (pinfunction "PD2_54") (pintype "bidirectional"))
    )
    (net (code "149") (name "Net-(U11A-PA7)") (class "Default")
      (node (ref "U11") (pin "23") (pinfunction "PA7_23") (pintype "bidirectional"))
      (node (ref "U26") (pin "20") (pinfunction "PA14_20") (pintype "passive"))
    )
    (net (code "150") (name "Net-(U11A-PA8)") (class "Default")
      (node (ref "U11") (pin "41") (pinfunction "PA8_41") (pintype "bidirectional"))
      (node (ref "U26") (pin "18") (pinfunction "PA10_18") (pintype "passive"))
    )
    (net (code "151") (name "Net-(U11A-PA9)") (class "Default")
      (node (ref "U11") (pin "42") (pinfunction "PA9_42") (pintype "bidirectional"))
      (node (ref "U26") (pin "17") (pinfunction "PA9_17") (pintype "passive"))
    )
    (net (code "152") (name "Net-(U11A-PA10)") (class "Default")
      (node (ref "U11") (pin "43") (pinfunction "PA10_43") (pintype "bidirectional"))
      (node (ref "U26") (pin "16") (pinfunction "VDD_16") (pintype "passive"))
    )
    (net (code "153") (name "Net-(U11A-PA11)") (class "Default")
      (node (ref "U11") (pin "44") (pinfunction "PA11_44") (pintype "bidirectional"))
      (node (ref "U26") (pin "15") (pinfunction "VSS_15") (pintype "passive"))
    )
    (net (code "154") (name "Net-(U11A-PA12)") (class "Default")
      (node (ref "U11") (pin "45") (pinfunction "PA12_45") (pintype "bidirectional"))
      (node (ref "U26") (pin "14") (pinfunction "PB1_14") (pintype "passive"))
    )
    (net (code "155") (name "Net-(U11A-PA13)") (class "Default")
      (node (ref "U11") (pin "46") (pinfunction "PA13_46") (pintype "bidirectional"))
      (node (ref "U26") (pin "13") (pinfunction "PA7_13") (pintype "passive"))
    )
    (net (code "156") (name "Net-(U11A-PA14)") (class "Default")
      (node (ref "U11") (pin "49") (pinfunction "PA14_49") (pintype "bidirectional"))
      (node (ref "U26") (pin "12") (pinfunction "PA6_12") (pintype "passive"))
    )
    (net (code "157") (name "Net-(U11A-PA15)") (class "Default")
      (node (ref "U11") (pin "50") (pinfunction "PA15_50") (pintype "bidirectional"))
      (node (ref "U26") (pin "11") (pinfunction "PA5_11") (pintype "passive"))
    )
    (net (code "158") (name "Net-(U11A-PC2)") (class "Default")
      (node (ref "R241") (pin "2") (pinfunction "2_2") (pintype "passive"))
      (node (ref "U11") (pin "10") (pinfunction "PC2_10") (pintype "bidirectional"))
    )
    (net (code "159") (name "Net-(U11A-PC15-OSC32_OUT)") (class "Default")
      (node (ref "R318") (pin "2") (pinfunction "2_2") (pintype "passive"))
      (node (ref "U11") (pin "4") (pinfunction "PC15-OSC32_OUT_4") (pintype "bidirectional"))
    )
    (net (code "160") (name "Net-(U11A-PD2)") (class "Default")
      (node (ref "R245") (pin "2") (pinfunction "2_2") (pintype "passive"))
      (node (ref "U11") (pin "54") (pinfunction "PD2_54") (pintype "bidirectional"))
    )
    (net (code "161") (name "Net-(U12A-BOOT0)") (class "Default")
      (node (ref "U12") (pin "60") (pinfunction "BOOT0_60") (pintype "input"))
      (node (ref "U3") (pin "9") (pinfunction "PC15-OSC32_OUT_9") (pintype "bidirectional"))
    )
    (net (code "162") (name "Net-(U12A-NRST)") (class "Default")
      (node (ref "U12") (pin "7") (pinfunction "NRST_7") (pintype "bidirectional"))
      (node (ref "U3") (pin "97") (pinfunction "PE0_97") (pintype "bidirectional"))
    )
    (net (code "163") (name "Net-(U12A-PA4)") (class "Default")
      (node (ref "U12") (pin "20") (pinfunction "PA4_20") (pintype "bidirectional"))
      (node (ref "U20") (pin "18") (pinfunction "PB0_18") (pintype "bidirectional"))
    )
    (net (code "164") (name "Net-(U12A-PA5)") (class "Default")
      (node (ref "U12") (pin "21") (pinfunction "PA5_21") (pintype "bidirectional"))
      (node (ref "U20") (pin "19") (pinfunction "PB1_19") (pintype "bidirectional"))
    )
    (net (code "165") (name "Net-(U12A-PA6)") (class "Default")
      (node (ref "U12") (pin "22") (pinfunction "PA6_22") (pintype "bidirectional"))
      (node (ref "U20") (pin "20") (pinfunction "PB2_20") (pintype "bidirectional"))
    )
    (net (code "166") (name "Net-(U12A-PA7)") (class "Default")
      (node (ref "U12") (pin "23") (pinfunction "PA7_23") (pintype "bidirectional"))
      (node (ref "U20") (pin "39") (pinfunction "PB3_39") (pintype "bidirectional"))
    )
    (net (code "167") (name "Net-(U12A-PA8)") (class "Default")
      (node (ref "U12") (pin "41") (pinfunction "PA8_41") (pintype "bidirectional"))
      (node (ref "U20") (pin "41") (pinfunction "PB5_41") (pintype "bidirectional"))
    )
    (net (code "168") (name "Net-(U12A-PA9)") (class "Default")
      (node (ref "U12") (pin "42") (pinfunction "PA9_42") (pintype "bidirectional"))
      (node (ref "U20") (pin "42") (pinfunction "PB6_42") (pintype "bidirectional"))
    )
    (net (code "169") (name "Net-(U12A-PA10)") (class "Default")
      (node (ref "U12") (pin "43") (pinfunction "PA10_43") (pintype "bidirectional"))
      (node (ref "U20") (pin "43") (pinfunction "PB7_43") (pintype "bidirectional"))
    )
    (net (code "170") (name "Net-(U12A-PA12)") (class "Default")
      (node (ref "U12") (pin "45") (pinfunction "PA12_45") (pintype "bidirectional"))
      (node (ref "U20") (pin "45") (pinfunction "PB8_45") (pintype "bidirectional"))
    )
    (net (code "171") (name "Net-(U12A-PA13)") (class "Default")
      (node (ref "U12") (pin "46") (pinfunction "PA13_46") (pintype "bidirectional"))
      (node (ref "U20") (pin "46") (pinfunction "PB9_46") (pintype "bidirectional"))
    )
    (net (code "172") (name "Net-(U12A-PA14)") (class "Default")
      (node (ref "U12") (pin "49") (pinfunction "PA14_49") (pintype "bidirectional"))
      (node (ref "U20") (pin "21") (pinfunction "PB10_21") (pintype "bidirectional"))
    )
    (net (code "173") (name "Net-(U12A-PA15)") (class "Default")
      (node (ref "U12") (pin "50") (pinfunction "PA15_50") (pintype "bidirectional"))
      (node (ref "U20") (pin "22") (pinfunction "PB11_22") (pintype "bidirectional"))
    )
    (net (code "174") (name "Net-(U12A-PB0)") (class "Default")
      (node (ref "U12") (pin "26") (pinfunction "PB0_26") (pintype "bidirectional"))
      (node (ref "U3") (pin "32") (pinfunction "PA7_32") (pintype "bidirectional"))
    )
    (net (code "175") (name "Net-(U12A-PB2)") (class "Default")
      (node (ref "U12") (pin "28") (pinfunction "PB2_28") (pintype "bidirectional"))
      (node (ref "U3") (pin "67") (pinfunction "PA8_67") (pintype "bidirectional"))
    )
    (net (code "176") (name "Net-(U12A-PB3)") (class "Default")
      (node (ref "U12") (pin "55") (pinfunction "PB3_55") (pintype "bidirectional"))
      (node (ref "U3") (pin "68") (pinfunction "PA9_68") (pintype "bidirectional"))
    )
    (net (code "177") (name "Net-(U12A-PB4)") (class "Default")
      (node (ref "U12") (pin "56") (pinfunction "PB4_56") (pintype "bidirectional"))
      (node (ref "U3") (pin "69") (pinfunction "PA10_69") (pintype "bidirectional"))
    )
    (net (code "178") (name "Net-(U12A-PB5)") (class "Default")
      (node (ref "U12") (pin "57") (pinfunction "PB5_57") (pintype "bidirectional"))
      (node (ref "U3") (pin "70") (pinfunction "PA11_70") (pintype "bidirectional"))
    )
    (net (code "179") (name "Net-(U12A-PB6)") (class "Default")
      (node (ref "U12") (pin "58") (pinfunction "PB6_58") (pintype "bidirectional"))
      (node (ref "U3") (pin "71") (pinfunction "PA12_71") (pintype "bidirectional"))
    )
    (net (code "180") (name "Net-(U12A-PB7)") (class "Default")
      (node (ref "U12") (pin "59") (pinfunction "PB7_59") (pintype "bidirectional"))
      (node (ref "U3") (pin "72") (pinfunction "PA13_72") (pintype "bidirectional"))
    )
    (net (code "181") (name "Net-(U12A-PB8)") (class "Default")
      (node (ref "U12") (pin "61") (pinfunction "PB8_61") (pintype "bidirectional"))
      (node (ref "U3") (pin "77") (pinfunction "PA15_77") (pintype "bidirectional"))
    )
    (net (code "182") (name "Net-(U12A-PB10)") (class "Default")
      (node (ref "U12") (pin "29") (pinfunction "PB10_29") (pintype "bidirectional"))
      (node (ref "U3") (pin "15") (pinfunction "PC0_15") (pintype "bidirectional"))
    )
    (net (code "183") (name "Net-(U12A-PB11)") (class "Default")
      (node (ref "U12") (pin "30") (pinfunction "PB11_30") (pintype "bidirectional"))
      (node (ref "U3") (pin "16") (pinfunction "PC1_16") (pintype "bidirectional"))
    )
    (net (code "184") (name "Net-(U12A-PB12)") (class "Default")
      (node (ref "U12") (pin "33") (pinfunction "PB12_33") (pintype "bidirectional"))
      (node (ref "U3") (pin "17") (pinfunction "PC2_17") (pintype "bidirectional"))
    )
    (net (code "185") (name "Net-(U12A-PB13)") (class "Default")
      (node (ref "U12") (pin "34") (pinfunction "PB13_34") (pintype "bidirectional"))
      (node (ref "U3") (pin "18") (pinfunction "PC3_18") (pintype "bidirectional"))
    )
    (net (code "186") (name "Net-(U12A-PB14)") (class "Default")
      (node (ref "U12") (pin "35") (pinfunction "PB14_35") (pintype "bidirectional"))
      (node (ref "U3") (pin "33") (pinfunction "PC4_33") (pintype "bidirectional"))
    )
    (net (code "187") (name "Net-(U12A-PB15)") (class "Default")
      (node (ref "U12") (pin "36") (pinfunction "PB15_36") (pintype "bidirectional"))
      (node (ref "U3") (pin "34") (pinfunction "PC5_34") (pintype "bidirectional"))
    )
    (net (code "188") (name "Net-(U12A-PC0)") (class "Default")
      (node (ref "U12") (pin "8") (pinfunction "PC0_8") (pintype "bidirectional"))
      (node (ref "U20") (pin "26") (pinfunction "PB13_26") (pintype "bidirectional"))
    )
    (net (code "189") (name "Net-(U12A-PC1)") (class "Default")
      (node (ref "U12") (pin "9") (pinfunction "PC1_9") (pintype "bidirectional"))
      (node (ref "U20") (pin "27") (pinfunction "PB14_27") (pintype "bidirectional"))
    )
    (net (code "190") (name "Net-(U12A-PC2)") (class "Default")
      (node (ref "R242") (pin "2") (pinfunction "2_2") (pintype "passive"))
      (node (ref "R243") (pin "1") (pinfunction "1_1") (pintype "passive"))
      (node (ref "U12") (pin "10") (pinfunction "PC2_10") (pintype "bidirectional"))
      (node (ref "U20") (pin "28") (pinfunction "PB15_28") (pintype "bidirectional"))
    )
    (net (code "191") (name "Net-(U12A-PC4)") (class "Default")
      (node (ref "U12") (pin "24") (pinfunction "PC4_24") (pintype "bidirectional"))
      (node (ref "U20") (pin "5") (pinfunction "PD0-OSC_IN_5") (pintype "bidirectional"))
    )
    (net (code "192") (name "Net-(U12A-PC5)") (class "Default")
      (node (ref "U12") (pin "25") (pinfunction "PC5_25") (pintype "bidirectional"))
      (node (ref "U20") (pin "6") (pinfunction "PD1_6") (pintype "bidirectional"))
    )
    (net (code "193") (name "Net-(U12A-PC7)") (class "Default")
      (node (ref "U12") (pin "38") (pinfunction "PC7_38") (pintype "bidirectional"))
      (node (ref "U20") (pin "44") (pinfunction "BOOT0_44") (pintype "input"))
    )
    (net (code "194") (name "Net-(U12A-PC8)") (class "Default")
      (node (ref "U12") (pin "39") (pinfunction "PC8_39") (pintype "bidirectional"))
      (node (ref "U20") (pin "7") (pinfunction "NRST_7") (pintype "bidirectional"))
    )
    (net (code "195") (name "Net-(U12A-PD0-OSC_IN)") (class "Default")
      (node (ref "U12") (pin "5") (pinfunction "PD0-OSC_IN_5") (pintype "bidirectional"))
      (node (ref "U3") (pin "64") (pinfunction "PC7_64") (pintype "bidirectional"))
    )
    (net (code "196") (name "Net-(U12A-PD2)") (class "Default")
      (node (ref "R246") (pin "2") (pinfunction "2_2") (pintype "passive"))
      (node (ref "R247") (pin "1") (pinfunction "1_1") (pintype "passive"))
      (node (ref "U12") (pin "54") (pinfunction "PD2_54") (pintype "bidirectional"))
      (node (ref "U3") (pin "65") (pinfunction "PC8_65") (pintype "bidirectional"))
    )
    (net (code "197") (name "Net-(U13A-PA5)") (class "Default")
      (node (ref "U13") (pin "21") (pinfunction "PA5_21") (pintype "bidirectional"))
      (node (ref "U23") (pin "18") (pinfunction "PB0_18") (pintype "bidirectional"))
    )
    (net (code "198") (name "Net-(U13A-PA6)") (class "Default")
      (node (ref "U13") (pin "22") (pinfunction "PA6_22") (pintype "bidirectional"))
      (node (ref "U23") (pin "19") (pinfunction "PB1_19") (pintype "bidirectional"))
    )
    (net (code "199") (name "Net-(U13A-PA7)") (class "Default")
      (node (ref "U13") (pin "23") (pinfunction "PA7_23") (pintype "bidirectional"))
      (node (ref "U23") (pin "20") (pinfunction "PB2_20") (pintype "bidirectional"))
    )
    (net (code "200") (name "Net-(U13A-PA8)") (class "Default")
      (node (ref "U13") (pin "41") (pinfunction "PA8_41") (pintype "bidirectional"))
      (node (ref "U23") (pin "40") (pinfunction "PB4_40") (pintype "bidirectional"))
    )
    (net (code "201") (name "Net-(U13A-PA9)") (class "Default")
      (node (ref "U13") (pin "42") (pinfunction "PA9_42") (pintype "bidirectional"))
      (node (ref "U23") (pin "41") (pinfunction "PB5_41") (pintype "bidirectional"))
    )
    (net (code "202") (name "Net-(U13A-PA10)") (class "Default")
      (node (ref "U13") (pin "43") (pinfunction "PA10_43") (pintype "bidirectional"))
      (node (ref "U23") (pin "42") (pinfunction "PB6_42") (pintype "bidirectional"))
    )
    (net (code "203") (name "Net-(U13A-PA11)") (class "Default")
      (node (ref "U13") (pin "44") (pinfunction "PA11_44") (pintype "bidirectional"))
      (node (ref "U23") (pin "43") (pinfunction "PB7_43") (pintype "bidirectional"))
    )
    (net (code "204") (name "Net-(U13A-PA13)") (class "Default")
      (node (ref "U13") (pin "46") (pinfunction "PA13_46") (pintype "bidirectional"))
      (node (ref "U23") (pin "45") (pinfunction "PB8_45") (pintype "bidirectional"))
    )
    (net (code "205") (name "Net-(U13A-PA14)") (class "Default")
      (node (ref "U13") (pin "49") (pinfunction "PA14_49") (pintype "bidirectional"))
      (node (ref "U23") (pin "46") (pinfunction "PB9_46") (pintype "bidirectional"))
    )
    (net (code "206") (name "Net-(U13A-PA15)") (class "Default")
      (node (ref "U13") (pin "50") (pinfunction "PA15_50") (pintype "bidirectional"))
      (node (ref "U23") (pin "21") (pinfunction "PB10_21") (pintype "bidirectional"))
    )
    (net (code "207") (name "Net-(U13A-PC0)") (class "Default")
      (node (ref "U13") (pin "8") (pinfunction "PC0_8") (pintype "bidirectional"))
      (node (ref "U23") (pin "25") (pinfunction "PB12_25") (pintype "bidirectional"))
    )
    (net (code "208") (name "Net-(U13A-PC1)") (class "Default")
      (node (ref "U13") (pin "9") (pinfunction "PC1_9") (pintype "bidirectional"))
      (node (ref "U23") (pin "26") (pinfunction "PB13_26") (pintype "bidirectional"))
    )
    (net (code "209") (name "Net-(U13A-PC2)") (class "Default")
      (node (ref "R243") (pin "2") (pinfunction "2_2") (pintype "passive"))
      (node (ref "U13") (pin "10") (pinfunction "PC2_10") (pintype "bidirectional"))
      (node (ref "U23") (pin "27") (pinfunction "PB14_27") (pintype "bidirectional"))
    )
    (net (code "210") (name "Net-(U13A-PC3)") (class "Default")
      (node (ref "U13") (pin "11") (pinfunction "PC3_11") (pintype "bidirectional"))
      (node (ref "U23") (pin "28") (pinfunction "PB15_28") (pintype "bidirectional"))
    )
    (net (code "211") (name "Net-(U13A-PC5)") (class "Default")
      (node (ref "U13") (pin "25") (pinfunction "PC5_25") (pintype "bidirectional"))
      (node (ref "U23") (pin "5") (pinfunction "PD0-OSC_IN_5") (pintype "bidirectional"))
    )
    (net (code "212") (name "Net-(U13A-PC6)") (class "Default")
      (node (ref "U13") (pin "37") (pinfunction "PC6_37") (pintype "bidirectional"))
      (node (ref "U23") (pin "6") (pinfunction "PD1_6") (pintype "bidirectional"))
    )
    (net (code "213") (name "Net-(U13A-PC9)") (class "Default")
      (node (ref "U13") (pin "40") (pinfunction "PC9_40") (pintype "bidirectional"))
      (node (ref "U23") (pin "7") (pinfunction "NRST_7") (pintype "bidirectional"))
    )
    (net (code "214") (name "Net-(U13A-PD2)") (class "Default")
      (node (ref "R247") (pin "2") (pinfunction "2_2") (pintype "passive"))
      (node (ref "U13") (pin "54") (pinfunction "PD2_54") (pintype "bidirectional"))
    )
    (net (code "215") (name "Net-(U14-NRST{slash}PA1)") (class "Default")
      (node (ref "U14") (pin "2") (pinfunction "NRST/PA1_2") (pintype "bidirectional"))
      (node (ref "U17") (pin "1") (pinfunction "NRST_1") (pintype "bidirectional"))
    )
    (net (code "216") (name "Net-(U14-PA3)") (class "Default")
      (node (ref "U14") (pin "4") (pinfunction "PA3_4") (pintype "bidirectional"))
      (node (ref "U17") (pin "2") (pinfunction "OSCIN/PA1_2") (pintype "bidirectional"))
    )
    (net (code "217") (name "Net-(U14-PA5)") (class "Default")
      (node (ref "U14") (pin "6") (pinfunction "PA5_6") (pintype "bidirectional"))
      (node (ref "U17") (pin "3") (pinfunction "OSCOUT/PA2_3") (pintype "bidirectional"))
      (node (ref "U24") (pin "18") (pinfunction "PB0_18") (pintype "bidirectional"))
    )
    (net (code "218") (name "Net-(U14-PA6)") (class "Default")
      (node (ref "U14") (pin "7") (pinfunction "PA6_7") (pintype "bidirectional"))
      (node (ref "U24") (pin "19") (pinfunction "PB1_19") (pintype "bidirectional"))
    )
    (net (code "219") (name "Net-(U14-PA7)") (class "Default")
      (node (ref "U14") (pin "8") (pinfunction "PA7_8") (pintype "bidirectional"))
      (node (ref "U17") (pin "4") (pinfunction "VSS_4") (pintype "power_in"))
      (node (ref "U24") (pin "20") (pinfunction "PB2_20") (pintype "bidirectional"))
    )
    (net (code "220") (name "Net-(U14-PC0)") (class "Default")
      (node (ref "U14") (pin "53") (pinfunction "PC0_53") (pintype "bidirectional"))
      (node (ref "U17") (pin "5") (pinfunction "VCAP_5") (pintype "power_in"))
      (node (ref "U24") (pin "40") (pinfunction "PB4_40") (pintype "bidirectional"))
    )
    (net (code "221") (name "Net-(U14-PC1)") (class "Default")
      (node (ref "U14") (pin "54") (pinfunction "PC1_54") (pintype "bidirectional"))
      (node (ref "U24") (pin "41") (pinfunction "PB5_41") (pintype "bidirectional"))
    )
    (net (code "222") (name "Net-(U14-PC2)") (class "Default")
      (node (ref "U14") (pin "57") (pinfunction "PC2_57") (pintype "bidirectional"))
      (node (ref "U17") (pin "6") (pinfunction "VDD_6") (pintype "power_in"))
      (node (ref "U24") (pin "42") (pinfunction "PB6_42") (pintype "bidirectional"))
    )
    (net (code "223") (name "Net-(U14-PC3)") (class "Default")
      (node (ref "U14") (pin "58") (pinfunction "PC3_58") (pintype "bidirectional"))
      (node (ref "U24") (pin "43") (pinfunction "PB7_43") (pintype "bidirectional"))
    )
    (net (code "224") (name "Net-(U14-PC4)") (class "Default")
      (node (ref "U14") (pin "59") (pinfunction "PC4_59") (pintype "bidirectional"))
      (node (ref "U17") (pin "7") (pinfunction "VDDio_7") (pintype "power_in"))
    )
    (net (code "225") (name "Net-(U14-PC5)") (class "Default")
      (node (ref "U14") (pin "60") (pinfunction "PC5_60") (pintype "bidirectional"))
      (node (ref "U24") (pin "45") (pinfunction "PB8_45") (pintype "bidirectional"))
    )
    (net (code "226") (name "Net-(U14-PC6)") (class "Default")
      (node (ref "U14") (pin "61") (pinfunction "PC6_61") (pintype "bidirectional"))
      (node (ref "U17") (pin "8") (pinfunction "PF4_/AIN12_8") (pintype "bidirectional"))
      (node (ref "U24") (pin "46") (pinfunction "PB9_46") (pintype "bidirectional"))
    )
    (net (code "227") (name "Net-(U14-PC7)") (class "Default")
      (node (ref "U14") (pin "62") (pinfunction "PC7_62") (pintype "bidirectional"))
      (node (ref "U24") (pin "21") (pinfunction "PB10_21") (pintype "bidirectional"))
    )
    (net (code "228") (name "Net-(U14-PE0)") (class "Default")
      (node (ref "U14") (pin "19") (pinfunction "PE0_19") (pintype "bidirectional"))
      (node (ref "U24") (pin "25") (pinfunction "PB12_25") (pintype "bidirectional"))
    )
    (net (code "229") (name "Net-(U14-PE1)") (class "Default")
      (node (ref "U14") (pin "20") (pinfunction "PE1_20") (pintype "bidirectional"))
      (node (ref "U17") (pin "10") (pinfunction "VSSA_10") (pintype "power_in"))
      (node (ref "U24") (pin "26") (pinfunction "PB13_26") (pintype "bidirectional"))
    )
    (net (code "230") (name "Net-(U14-PE2)") (class "Default")
      (node (ref "R199") (pin "8") (pinfunction "8_8") (pintype "passive"))
      (node (ref "U14") (pin "21") (pinfunction "PE2_21") (pintype "bidirectional"))
      (node (ref "U24") (pin "27") (pinfunction "PB14_27") (pintype "bidirectional"))
    )
    (net (code "231") (name "Net-(U14-PE3)") (class "Default")
      (node (ref "R199") (pin "7") (pinfunction "7_7") (pintype "passive"))
      (node (ref "U14") (pin "22") (pinfunction "PE3_22") (pintype "bidirectional"))
      (node (ref "U17") (pin "11") (pinfunction "PB5/AIN5[I2C_SDA]_11") (pintype "bidirectional"))
      (node (ref "U24") (pin "28") (pinfunction "PB15_28") (pintype "bidirectional"))
    )
    (net (code "232") (name "Net-(U14-PE4)") (class "Default")
      (node (ref "R199") (pin "6") (pinfunction "6_6") (pintype "passive"))
      (node (ref "U14") (pin "23") (pinfunction "PE4_23") (pintype "bidirectional"))
    )
    (net (code "233") (name "Net-(U14-PE5)") (class "Default")
      (node (ref "R199") (pin "5") (pinfunction "5_5") (pintype "passive"))
      (node (ref "U14") (pin "24") (pinfunction "PE5_24") (pintype "bidirectional"))
      (node (ref "U17") (pin "12") (pinfunction "PB4/AIN4[I2C_SCL]_12") (pintype "bidirectional"))
      (node (ref "U24") (pin "44") (pinfunction "BOOT0_44") (pintype "input"))
    )
    (net (code "234") (name "Net-(U14-PE7)") (class "Default")
      (node (ref "U14") (pin "64") (pinfunction "PE7_64") (pintype "bidirectional"))
      (node (ref "U17") (pin "13") (pinfunction "PB3/AIN3[TIM1_ETR]_13") (pintype "bidirectional"))
      (node (ref "U24") (pin "7") (pinfunction "NRST_7") (pintype "bidirectional"))
    )
    (net (code "235") (name "Net-(U14-PG0)") (class "Default")
      (node (ref "U14") (pin "14") (pinfunction "PG0_14") (pintype "bidirectional"))
      (node (ref "U17") (pin "14") (pinfunction "PB2/AIN2[TIM1_CH3N]_14") (pintype "bidirectional"))
      (node (ref "U24") (pin "6") (pinfunction "PH1-OSC_OUT_6") (pintype "bidirectional"))
    )
    (net (code "236") (name "Net-(U14-PG1)") (class "Default")
      (node (ref "U14") (pin "15") (pinfunction "PG1_15") (pintype "bidirectional"))
      (node (ref "U24") (pin "5") (pinfunction "PH0-OSC_IN_5") (pintype "bidirectional"))
    )
    (net (code "237") (name "Net-(U14-PG2)") (class "Default")
      (node (ref "U14") (pin "16") (pinfunction "PG2_16") (pintype "bidirectional"))
      (node (ref "U17") (pin "15") (pinfunction "PB1/AIN1[TIM1_CH2N]_15") (pintype "bidirectional"))
    )
    (net (code "238") (name "Net-(U14-PG4)") (class "Default")
      (node (ref "U14") (pin "49") (pinfunction "PG4_49") (pintype "bidirectional"))
      (node (ref "U17") (pin "16") (pinfunction "PB0/AIN0[TIM1_CH1N]_16") (pintype "bidirectional"))
    )
    (net (code "239") (name "Net-(U15A-PB2-BOOT1(PB2){slash}EVENTOUT)") (class "Default")
      (node (ref "R253") (pin "2") (pinfunction "2_2") (pintype "passive"))
      (node (ref "R254") (pin "1") (pinfunction "1_1") (pintype "passive"))
      (node (ref "U15") (pin "28") (pinfunction "PB2-BOOT1(PB2)/EVENTOUT_28") (pintype "bidirectional"))
    )
    (net (code "240") (name "Net-(U16A-PB2-BOOT1(PB2){slash}EVENTOUT)") (class "Default")
      (node (ref "R254") (pin "2") (pinfunction "2_2") (pintype "passive"))
      (node (ref "U16") (pin "37") (pinfunction "PB2-BOOT1(PB2)/EVENTOUT_37") (pintype "bidirectional"))
    )
    (net (code "241") (name "Net-(U17-VDDA)") (class "Default")
      (node (ref "U17") (pin "9") (pinfunction "VDDA_9") (pintype "power_in"))
      (node (ref "U24") (pin "22") (pinfunction "PB11_22") (pintype "bidirectional"))
    )
    (net (code "242") (name "Net-(U25-PC0{slash}I2C_SDA)") (class "Default")
      (node (ref "R256") (pin "2") (pinfunction "2_2") (pintype "passive"))
      (node (ref "U25") (pin "18") (pinfunction "PC0/I2C_SDA_18") (pintype "bidirectional"))
    )
    (net (code "243") (name "Net-(U27A-PA13(JTMS-SWDIO){slash}JTMS-SWDIO{slash}EVENTOUT)") (class "Default")
      (node (ref "R197") (pin "8") (pinfunction "8_8") (pintype "passive"))
      (node (ref "U27") (pin "72") (pinfunction "PA13(JTMS-SWDIO)/JTMS-SWDIO/EVENTOUT_72") (pintype "bidirectional"))
    )
    (net (code "244") (name "Net-(U27A-PA14(JTCK-SWCLK){slash}JTCK-SWCLK{slash}EVENTOUT)") (class "Default")
      (node (ref "R197") (pin "7") (pinfunction "7_7") (pintype "passive"))
      (node (ref "U27") (pin "76") (pinfunction "PA14(JTCK-SWCLK)/JTCK-SWCLK/EVENTOUT_76") (pintype "bidirectional"))
    )
    (net (code "245") (name "Net-(U27A-PA15(JTDI){slash}JTDI{slash}SPI3_NSS{slash}I2S3_WS{slash}TIM2_CH1_ETR{slash}SPI1_NSS{slash}EVENTOUT)") (class "Default")
      (node (ref "R197") (pin "6") (pinfunction "6_6") (pintype "passive"))
      (node (ref "U27") (pin "77") (pinfunction "PA15(JTDI)/JTDI/SPI3_NSS/I2S3_WS/TIM2_CH1_ETR/SPI1_NSS/EVENTOUT_77") (pintype "bidirectional"))
    )
    (net (code "246") (name "Net-(U28-NRST)") (class "Default")
      (node (ref "U28") (pin "4") (pinfunction "NRST_4") (pintype "bidirectional"))
      (node (ref "U29") (pin "7") (pinfunction "VSS/VSSA/VREF-_7") (pintype "passive"))
    )
    (net (code "247") (name "Net-(U28-OSCIN{slash}PA1)") (class "Default")
      (node (ref "U28") (pin "5") (pinfunction "OSCIN/PA1_5") (pintype "bidirectional"))
      (node (ref "U29") (pin "9") (pinfunction "PD0_9") (pintype "passive"))
    )
    (net (code "248") (name "Net-(U28-PD4(HS){slash}BEEP{slash}TIM2_CH1__{slash}UART1_CK)") (class "Default")
      (node (ref "U28") (pin "1") (pinfunction "PD4(HS)/BEEP/TIM2_CH1__/UART1_CK_1") (pintype "bidirectional"))
      (node (ref "U29") (pin "1") (pinfunction "PC5_1") (pintype "passive"))
    )
    (net (code "249") (name "Net-(U28-PD5(HS)_{slash}AIN5{slash}UART1_TX)") (class "Default")
      (node (ref "U28") (pin "2") (pinfunction "PD5(HS)_/AIN5/UART1_TX_2") (pintype "bidirectional"))
      (node (ref "U29") (pin "3") (pinfunction "PA0_3") (pintype "passive"))
    )
    (net (code "250") (name "Net-(U28-PD6(HS)_{slash}AIN6{slash}UART1_RX)") (class "Default")
      (node (ref "U28") (pin "3") (pinfunction "PD6(HS)_/AIN6/UART1_RX_3") (pintype "bidirectional"))
      (node (ref "U29") (pin "5") (pinfunction "PA2_5") (pintype "passive"))
    )
    (net (code "251") (name "Net-(U30-PC4_(HS){slash}TIM1_CH4{slash}CLK_CCO{slash}AIN2{slash}[TIM1_CH2N])") (class "Default")
      (node (ref "R258") (pin "2") (pinfunction "2_2") (pintype "passive"))
      (node (ref "U30") (pin "14") (pinfunction "PC4_(HS)/TIM1_CH4/CLK_CCO/AIN2/[TIM1_CH2N]_14") (pintype "passive"))
    )
    (net (code "252") (name "Net-(VR1-Vout)") (class "Default")
      (node (ref "VR1") (pin "2") (pinfunction "Vout_2") (pintype "passive"))
      (node (ref "VR3") (pin "3") (pinfunction "Vin_3") (pintype "passive"))
    )
    (net (code "253") (name "Net-(VR9-Vout)") (class "Default")
      (node (ref "D3") (pin "A") (pinfunction "A_A") (pintype "passive"))
      (node (ref "VR9") (pin "2") (pinfunction "Vout_2") (pintype "passive"))
    )
    (net (code "254") (name "unconnected-(D3-PadK)") (class "Default")
      (node (ref "D3") (pin "K") (pinfunction "K_K") (pintype "passive"))
    )
    (net (code "255") (name "unconnected-(D4-PadA)") (class "Default")
      (node (ref "D4") (pin "A") (pinfunction "A_A") (pintype "passive"))
    )
    (net (code "256") (name "unconnected-(D5-PadK)") (class "Default")
      (node (ref "D5") (pin "K") (pinfunction "K_K") (pintype "passive"))
    )
    (net (code "257") (name "unconnected-(D6-PadA)") (class "Default")
      (node (ref "D6") (pin "A") (pinfunction "A_A") (pintype "passive"))
    )
    (net (code "258") (name "unconnected-(D7-PadK)") (class "Default")
      (node (ref "D7") (pin "K") (pinfunction "K_K") (pintype "passive"))
    )
    (net (code "259") (name "unconnected-(D8-PadA)") (class "Default")
      (node (ref "D8") (pin "A") (pinfunction "A_A") (pintype "passive"))
    )
    (net (code "260") (name "unconnected-(D9-PadK)") (class "Default")
      (node (ref "D9") (pin "K") (pinfunction "K_K") (pintype "passive"))
    )
    (net (code "261") (name "unconnected-(D10-PadA)") (class "Default")
      (node (ref "D10") (pin "A") (pinfunction "A_A") (pintype "passive"))
    )
    (net (code "262") (name "unconnected-(D12-PadK)") (class "Default")
      (node (ref "D12") (pin "K") (pinfunction "K_K") (pintype "passive"))
    )
    (net (code "263") (name "unconnected-(L1-Pad1)") (class "Default")
      (node (ref "L1") (pin "1") (pinfunction "1_1") (pintype "passive"))
    )
    (net (code "264") (name "unconnected-(L1-Pad2)") (class "Default")
      (node (ref "L1") (pin "2") (pinfunction "2_2") (pintype "passive"))
    )
    (net (code "265") (name "unconnected-(L2-Pad1)") (class "Default")
      (node (ref "L2") (pin "1") (pinfunction "1_1") (pintype "passive"))
    )
    (net (code "266") (name "unconnected-(L2-Pad2)") (class "Default")
      (node (ref "L2") (pin "2") (pinfunction "2_2") (pintype "passive"))
    )
    (net (code "267") (name "unconnected-(L3-Pad1)") (class "Default")
      (node (ref "L3") (pin "1") (pinfunction "1_1") (pintype "passive"))
    )
    (net (code "268") (name "unconnected-(L3-Pad2)") (class "Default")
      (node (ref "L3") (pin "2") (pinfunction "2_2") (pintype "passive"))
    )
    (net (code "269") (name "unconnected-(L4-Pad1)") (class "Default")
      (node (ref "L4") (pin "1") (pinfunction "1_1") (pintype "passive"))
    )
    (net (code "270") (name "unconnected-(L4-Pad2)") (class "Default")
      (node (ref "L4") (pin "2") (pinfunction "2_2") (pintype "passive"))
    )
    (net (code "271") (name "unconnected-(L5-Pad1)") (class "Default")
      (node (ref "L5") (pin "1") (pinfunction "1_1") (pintype "passive"))
    )
    (net (code "272") (name "unconnected-(L5-Pad2)") (class "Default")
      (node (ref "L5") (pin "2") (pinfunction "2_2") (pintype "passive"))
    )
    (net (code "273") (name "unconnected-(L6-Pad1)") (class "Default")
      (node (ref "L6") (pin "1") (pinfunction "1_1") (pintype "passive"))
    )
    (net (code "274") (name "unconnected-(L6-Pad2)") (class "Default")
      (node (ref "L6") (pin "2") (pinfunction "2_2") (pintype "passive"))
    )
    (net (code "275") (name "unconnected-(L7-Pad1)") (class "Default")
      (node (ref "L7") (pin "1") (pinfunction "1_1") (pintype "passive"))
    )
    (net (code "276") (name "unconnected-(L7-Pad2)") (class "Default")
      (node (ref "L7") (pin "2") (pinfunction "2_2") (pintype "passive"))
    )
    (net (code "277") (name "unconnected-(L8-Pad1)") (class "Default")
      (node (ref "L8") (pin "1") (pinfunction "1_1") (pintype "passive"))
    )
    (net (code "278") (name "unconnected-(L8-Pad2)") (class "Default")
      (node (ref "L8") (pin "2") (pinfunction "2_2") (pintype "passive"))
    )
    (net (code "279") (name "unconnected-(L9-Pad1)") (class "Default")
      (node (ref "L9") (pin "1") (pinfunction "1_1") (pintype "passive"))
    )
    (net (code "280") (name "unconnected-(L9-Pad2)") (class "Default")
      (node (ref "L9") (pin "2") (pinfunction "2_2") (pintype "passive"))
    )
    (net (code "281") (name "unconnected-(L10-Pad1)") (class "Default")
      (node (ref "L10") (pin "1") (pinfunction "1_1") (pintype "passive"))
    )
    (net (code "282") (name "unconnected-(L10-Pad2)") (class "Default")
      (node (ref "L10") (pin "2") (pinfunction "2_2") (pintype "passive"))
    )
    (net (code "283") (name "unconnected-(L11-Pad1)") (class "Default")
      (node (ref "L11") (pin "1") (pinfunction "1_1") (pintype "passive"))
    )
    (net (code "284") (name "unconnected-(L11-Pad2)") (class "Default")
      (node (ref "L11") (pin "2") (pinfunction "2_2") (pintype "passive"))
    )
    (net (code "285") (name "unconnected-(L12-Pad1)") (class "Default")
      (node (ref "L12") (pin "1") (pinfunction "1_1") (pintype "passive"))
    )
    (net (code "286") (name "unconnected-(L12-Pad2)") (class "Default")
      (node (ref "L12") (pin "2") (pinfunction "2_2") (pintype "passive"))
    )
    (net (code "287") (name "unconnected-(L13-Pad1)") (class "Default")
      (node (ref "L13") (pin "1") (pinfunction "1_1") (pintype "passive"))
    )
    (net (code "288") (name "unconnected-(L13-Pad2)") (class "Default")
      (node (ref "L13") (pin "2") (pinfunction "2_2") (pintype "passive"))
    )
    (net (code "289") (name "unconnected-(L14-Pad1)") (class "Default")
      (node (ref "L14") (pin "1") (pinfunction "1_1") (pintype "passive"))
    )
    (net (code "290") (name "unconnected-(L14-Pad2)") (class "Default")
      (node (ref "L14") (pin "2") (pinfunction "2_2") (pintype "passive"))
    )
    (net (code "291") (name "unconnected-(L15-Pad1)") (class "Default")
      (node (ref "L15") (pin "1") (pinfunction "1_1") (pintype "passive"))
    )
    (net (code "292") (name "unconnected-(L15-Pad2)") (class "Default")
      (node (ref "L15") (pin "2") (pinfunction "2_2") (pintype "passive"))
    )
    (net (code "293") (name "unconnected-(Q8-G-Pad1)") (class "Default")
      (node (ref "Q8") (pin "1") (pinfunction "G_1") (pintype "passive"))
    )
    (net (code "294") (name "unconnected-(Q8-G-Pad4)") (class "Default")
      (node (ref "Q8") (pin "4") (pinfunction "G_4") (pintype "passive"))
    )
    (net (code "295") (name "unconnected-(Q8-S-Pad1)") (class "Default")
      (node (ref "Q8") (pin "1") (pinfunction "S_1") (pintype "passive"))
    )
    (net (code "296") (name "unconnected-(Q8-S-Pad3)") (class "Default")
      (node (ref "Q8") (pin "3") (pinfunction "S_3") (pintype "passive"))
    )
    (net (code "297") (name "unconnected-(Q9-D-Pad3)") (class "Default")
      (node (ref "Q9") (pin "3") (pinfunction "D_3") (pintype "passive"))
    )
    (net (code "298") (name "unconnected-(Q9-S-Pad2)") (class "Default")
      (node (ref "Q9") (pin "2") (pinfunction "S_2") (pintype "passive"))
    )
    (net (code "299") (name "unconnected-(Q10-D-Pad3)") (class "Default")
      (node (ref "Q10") (pin "3") (pinfunction "D_3") (pintype "passive"))
    )
    (net (code "300") (name "unconnected-(Q10-G-Pad1)") (class "Default")
      (node (ref "Q10") (pin "1") (pinfunction "G_1") (pintype "passive"))
    )
    (net (code "301") (name "unconnected-(Q10-S-Pad2)") (class "Default")
      (node (ref "Q10") (pin "2") (pinfunction "S_2") (pintype "passive"))
    )
    (net (code "302") (name "unconnected-(Q11-D-Pad3)") (class "Default")
      (node (ref "Q11") (pin "3") (pinfunction "D_3") (pintype "passive"))
    )
    (net (code "303") (name "unconnected-(Q11-G-Pad1)") (class "Default")
      (node (ref "Q11") (pin "1") (pinfunction "G_1") (pintype "passive"))
    )
    (net (code "304") (name "unconnected-(Q11-S-Pad2)") (class "Default")
      (node (ref "Q11") (pin "2") (pinfunction "S_2") (pintype "passive"))
    )
    (net (code "305") (name "unconnected-(Q12-D-Pad5)") (class "Default")
      (node (ref "Q12") (pin "5") (pinfunction "D_5") (pintype "passive"))
    )
    (net (code "306") (name "unconnected-(Q12-D-Pad6)") (class "Default")
      (node (ref "Q12") (pin "6") (pinfunction "D_6") (pintype "passive"))
    )
    (net (code "307") (name "unconnected-(Q12-D-Pad7)") (class "Default")
      (node (ref "Q12") (pin "7") (pinfunction "D_7") (pintype "passive"))
    )
    (net (code "308") (name "unconnected-(Q12-D-Pad8)") (class "Default")
      (node (ref "Q12") (pin "8") (pinfunction "D_8") (pintype "passive"))
    )
    (net (code "309") (name "unconnected-(Q12-G-Pad4)") (class "Default")
      (node (ref "Q12") (pin "4") (pinfunction "G_4") (pintype "passive"))
    )
    (net (code "310") (name "unconnected-(Q12-S-Pad1)") (class "Default")
      (node (ref "Q12") (pin "1") (pinfunction "S_1") (pintype "passive"))
    )
    (net (code "311") (name "unconnected-(Q12-S-Pad2)") (class "Default")
      (node (ref "Q12") (pin "2") (pinfunction "S_2") (pintype "passive"))
    )
    (net (code "312") (name "unconnected-(Q12-S-Pad3)") (class "Default")
      (node (ref "Q12") (pin "3") (pinfunction "S_3") (pintype "passive"))
    )
    (net (code "313") (name "unconnected-(Q13A-D-Pad7)") (class "Default")
      (node (ref "Q13") (pin "7") (pinfunction "D_7") (pintype "passive"))
    )
    (net (code "314") (name "unconnected-(Q13A-D-Pad8)") (class "Default")
      (node (ref "Q13") (pin "8") (pinfunction "D_8") (pintype "passive"))
    )
    (net (code "315") (name "unconnected-(Q13A-G-Pad2)") (class "Default")
      (node (ref "Q13") (pin "2") (pinfunction "G_2") (pintype "passive"))
    )
    (net (code "316") (name "unconnected-(Q13A-S-Pad1)") (class "Default")
      (node (ref "Q13") (pin "1") (pinfunction "S_1") (pintype "passive"))
    )
    (net (code "317") (name "unconnected-(Q14-D-Pad3)") (class "Default")
      (node (ref "Q14") (pin "3") (pinfunction "D_3") (pintype "passive"))
    )
    (net (code "318") (name "unconnected-(Q14-G-Pad1)") (class "Default")
      (node (ref "Q14") (pin "1") (pinfunction "G_1") (pintype "passive"))
    )
    (net (code "319") (name "unconnected-(Q14-S-Pad2)") (class "Default")
      (node (ref "Q14") (pin "2") (pinfunction "S_2") (pintype "passive"))
    )
    (net (code "320") (name "unconnected-(Q15-G-Pad4)") (class "Default")
      (node (ref "Q15") (pin "4") (pinfunction "G_4") (pintype "passive"))
    )
    (net (code "321") (name "unconnected-(Q15-G-Pad5)") (class "Default")
      (node (ref "Q15") (pin "5") (pinfunction "G_5") (pintype "passive"))
    )
    (net (code "322") (name "unconnected-(Q15-S-Pad2)") (class "Default")
      (node (ref "Q15") (pin "2") (pinfunction "S_2") (pintype "passive"))
    )
    (net (code "323") (name "unconnected-(Q15-S-Pad3)") (class "Default")
      (node (ref "Q15") (pin "3") (pinfunction "S_3") (pintype "passive"))
    )
    (net (code "324") (name "unconnected-(Q15-S-Pad6)") (class "Default")
      (node (ref "Q15") (pin "6") (pinfunction "S_6") (pintype "passive"))
    )
    (net (code "325") (name "unconnected-(Q15-S-Pad7)") (class "Default")
      (node (ref "Q15") (pin "7") (pinfunction "S_7") (pintype "passive"))
    )
    (net (code "326") (name "unconnected-(Q16-G-Pad1)") (class "Default")
      (node (ref "Q16") (pin "1") (pinfunction "G_1") (pintype "passive"))
    )
    (net (code "327") (name "unconnected-(Q16-S-Pad2)") (class "Default")
      (node (ref "Q16") (pin "2") (pinfunction "S_2") (pintype "passive"))
    )
    (net (code "328") (name "unconnected-(R192-Pad2)") (class "Default")
      (node (ref "R192") (pin "2") (pinfunction "2_2") (pintype "passive"))
    )
    (net (code "329") (name "unconnected-(R193-Pad1)") (class "Default")
      (node (ref "R193") (pin "1") (pinfunction "1_1") (pintype "passive"))
    )
    (net (code "330") (name "unconnected-(R194-Pad2)") (class "Default")
      (node (ref "R194") (pin "2") (pinfunction "2_2") (pintype "passive"))
    )
    (net (code "331") (name "unconnected-(R195-Pad1)") (class "Default")
      (node (ref "R195") (pin "1") (pinfunction "1_1") (pintype "passive"))
    )
    (net (code "332") (name "unconnected-(R196-Pad2)") (class "Default")
      (node (ref "R196") (pin "2") (pinfunction "2_2") (pintype "passive"))
    )
    (net (code "333") (name "unconnected-(R197-Pad1)") (class "Default")
      (node (ref "R197") (pin "1") (pinfunction "1_1") (pintype "passive"))
    )
    (net (code "334") (name "unconnected-(R197-Pad2)") (class "Default")
      (node (ref "R197") (pin "2") (pinfunction "2_2") (pintype "passive"))
    )
    (net (code "335") (name "unconnected-(R197-Pad3)") (class "Default")
      (node (ref "R197") (pin "3") (pinfunction "3_3") (pintype "passive"))
    )
    (net (code "336") (name "unconnected-(R197-Pad4)") (class "Default")
      (node (ref "R197") (pin "4") (pinfunction "4_4") (pintype "passive"))
    )
    (net (code "337") (name "unconnected-(R197-Pad5)") (class "Default")
      (node (ref "R197") (pin "5") (pinfunction "5_5") (pintype "passive"))
    )
    (net (code "338") (name "unconnected-(R198-Pad1)") (class "Default")
      (node (ref "R198") (pin "1") (pinfunction "1_1") (pintype "passive"))
    )
    (net (code "339") (name "unconnected-(R198-Pad2)") (class "Default")
      (node (ref "R198") (pin "2") (pinfunction "2_2") (pintype "passive"))
    )
    (net (code "340") (name "unconnected-(R198-Pad3)") (class "Default")
      (node (ref "R198") (pin "3") (pinfunction "3_3") (pintype "passive"))
    )
    (net (code "341") (name "unconnected-(R198-Pad4)") (class "Default")
      (node (ref "R198") (pin "4") (pinfunction "4_4") (pintype "passive"))
    )
    (net (code "342") (name "unconnected-(R199-Pad1)") (class "Default")
      (node (ref "R199") (pin "1") (pinfunction "1_1") (pintype "passive"))
    )
    (net (code "343") (name "unconnected-(R199-Pad2)") (class "Default")
      (node (ref "R199") (pin "2") (pinfunction "2_2") (pintype "passive"))
    )
    (net (code "344") (name "unconnected-(R199-Pad3)") (class "Default")
      (node (ref "R199") (pin "3") (pinfunction "3_3") (pintype "passive"))
    )
    (net (code "345") (name "unconnected-(R199-Pad4)") (class "Default")
      (node (ref "R199") (pin "4") (pinfunction "4_4") (pintype "passive"))
    )
    (net (code "346") (name "unconnected-(R200-Pad1)") (class "Default")
      (node (ref "R200") (pin "1") (pinfunction "1_1") (pintype "passive"))
    )
    (net (code "347") (name "unconnected-(R201-Pad2)") (class "Default")
      (node (ref "R201") (pin "2") (pinfunction "2_2") (pintype "passive"))
    )
    (net (code "348") (name "unconnected-(R202-Pad1)") (class "Default")
      (node (ref "R202") (pin "1") (pinfunction "1_1") (pintype "passive"))
    )
    (net (code "349") (name "unconnected-(R202-Pad2)") (class "Default")
      (node (ref "R202") (pin "2") (pinfunction "2_2") (pintype "passive"))
    )
    (net (code "350") (name "unconnected-(R203-Pad1)") (class "Default")
      (node (ref "R203") (pin "1") (pinfunction "1_1") (pintype "passive"))
    )
    (net (code "351") (name "unconnected-(R204-Pad2)") (class "Default")
      (node (ref "R204") (pin "2") (pinfunction "2_2") (pintype "passive"))
    )
    (net (code "352") (name "unconnected-(R205-Pad1)") (class "Default")
      (node (ref "R205") (pin "1") (pinfunction "1_1") (pintype "passive"))
    )
    (net (code "353") (name "unconnected-(R206-Pad2)") (class "Default")
      (node (ref "R206") (pin "2") (pinfunction "2_2") (pintype "passive"))
    )
    (net (code "354") (name "unconnected-(R207-Pad1)") (class "Default")
      (node (ref "R207") (pin "1") (pinfunction "1_1") (pintype "passive"))
    )
    (net (code "355") (name "unconnected-(R208-Pad2)") (class "Default")
      (node (ref "R208") (pin "2") (pinfunction "2_2") (pintype "passive"))
    )
    (net (code "356") (name "unconnected-(R209-Pad1)") (class "Default")
      (node (ref "R209") (pin "1") (pinfunction "1_1") (pintype "passive"))
    )
    (net (code "357") (name "unconnected-(R210-Pad2)") (class "Default")
      (node (ref "R210") (pin "2") (pinfunction "2_2") (pintype "passive"))
    )
    (net (code "358") (name "unconnected-(R211-Pad1)") (class "Default")
      (node (ref "R211") (pin "1") (pinfunction "1_1") (pintype "passive"))
    )
    (net (code "359") (name "unconnected-(R211-Pad2)") (class "Default")
      (node (ref "R211") (pin "2") (pinfunction "2_2") (pintype "passive"))
    )
    (net (code "360") (name "unconnected-(R212-Pad1)") (class "Default")
      (node (ref "R212") (pin "1") (pinfunction "1_1") (pintype "passive"))
    )
    (net (code "361") (name "unconnected-(R213-Pad2)") (class "Default")
      (node (ref "R213") (pin "2") (pinfunction "2_2") (pintype "passive"))
    )
    (net (code "362") (name "unconnected-(R214-Pad1)") (class "Default")
      (node (ref "R214") (pin "1") (pinfunction "1_1") (pintype "passive"))
    )
    (net (code "363") (name "unconnected-(R215-Pad2)") (class "Default")
      (node (ref "R215") (pin "2") (pinfunction "2_2") (pintype "passive"))
    )
    (net (code "364") (name "unconnected-(R216-Pad1)") (class "Default")
      (node (ref "R216") (pin "1") (pinfunction "1_1") (pintype "passive"))
    )
    (net (code "365") (name "unconnected-(R217-Pad2)") (class "Default")
      (node (ref "R217") (pin "2") (pinfunction "2_2") (pintype "passive"))
    )
    (net (code "366") (name "unconnected-(R218-Pad1)") (class "Default")
      (node (ref "R218") (pin "1") (pinfunction "1_1") (pintype "passive"))
    )
    (net (code "367") (name "unconnected-(R218-Pad2)") (class "Default")
      (node (ref "R218") (pin "2") (pinfunction "2_2") (pintype "passive"))
    )
    (net (code "368") (name "unconnected-(R219-Pad1)") (class "Default")
      (node (ref "R219") (pin "1") (pinfunction "1_1") (pintype "passive"))
    )
    (net (code "369") (name "unconnected-(R220-Pad2)") (class "Default")
      (node (ref "R220") (pin "2") (pinfunction "2_2") (pintype "passive"))
    )
    (net (code "370") (name "unconnected-(R221-Pad1)") (class "Default")
      (node (ref "R221") (pin "1") (pinfunction "1_1") (pintype "passive"))
    )
    (net (code "371") (name "unconnected-(R222-Pad2)") (class "Default")
      (node (ref "R222") (pin "2") (pinfunction "2_2") (pintype "passive"))
    )
    (net (code "372") (name "unconnected-(R223-Pad1)") (class "Default")
      (node (ref "R223") (pin "1") (pinfunction "1_1") (pintype "passive"))
    )
    (net (code "373") (name "unconnected-(R224-Pad2)") (class "Default")
      (node (ref "R224") (pin "2") (pinfunction "2_2") (pintype "passive"))
    )
    (net (code "374") (name "unconnected-(R225-Pad1)") (class "Default")
      (node (ref "R225") (pin "1") (pinfunction "1_1") (pintype "passive"))
    )
    (net (code "375") (name "unconnected-(R225-Pad2)") (class "Default")
      (node (ref "R225") (pin "2") (pinfunction "2_2") (pintype "passive"))
    )
    (net (code "376") (name "unconnected-(R226-Pad1)") (class "Default")
      (node (ref "R226") (pin "1") (pinfunction "1_1") (pintype "passive"))
    )
    (net (code "377") (name "unconnected-(R227-Pad2)") (class "Default")
      (node (ref "R227") (pin "2") (pinfunction "2_2") (pintype "passive"))
    )
    (net (code "378") (name "unconnected-(R228-Pad1)") (class "Default")
      (node (ref "R228") (pin "1") (pinfunction "1_1") (pintype "passive"))
    )
    (net (code "379") (name "unconnected-(R229-Pad2)") (class "Default")
      (node (ref "R229") (pin "2") (pinfunction "2_2") (pintype "passive"))
    )
    (net (code "380") (name "unconnected-(R230-Pad1)") (class "Default")
      (node (ref "R230") (pin "1") (pinfunction "1_1") (pintype "passive"))
    )
    (net (code "381") (name "unconnected-(R231-Pad2)") (class "Default")
      (node (ref "R231") (pin "2") (pinfunction "2_2") (pintype "passive"))
    )
    (net (code "382") (name "unconnected-(R232-Pad1)") (class "Default")
      (node (ref "R232") (pin "1") (pinfunction "1_1") (pintype "passive"))
    )
    (net (code "383") (name "unconnected-(R233-Pad2)") (class "Default")
      (node (ref "R233") (pin "2") (pinfunction "2_2") (pintype "passive"))
    )
    (net (code "384") (name "unconnected-(R234-Pad1)") (class "Default")
      (node (ref "R234") (pin "1") (pinfunction "1_1") (pintype "passive"))
    )
    (net (code "385") (name "unconnected-(R234-Pad2)") (class "Default")
      (node (ref "R234") (pin "2") (pinfunction "2_2") (pintype "passive"))
    )
    (net (code "386") (name "unconnected-(R235-Pad1)") (class "Default")
      (node (ref "R235") (pin "1") (pinfunction "1_1") (pintype "passive"))
    )
    (net (code "387") (name "unconnected-(R236-Pad2)") (class "Default")
      (node (ref "R236") (pin "2") (pinfunction "2_2") (pintype "passive"))
    )
    (net (code "388") (name "unconnected-(R237-Pad1)") (class "Default")
      (node (ref "R237") (pin "1") (pinfunction "1_1") (pintype "passive"))
    )
    (net (code "389") (name "unconnected-(R238-Pad2)") (class "Default")
      (node (ref "R238") (pin "2") (pinfunction "2_2") (pintype "passive"))
    )
    (net (code "390") (name "unconnected-(R239-Pad1)") (class "Default")
      (node (ref "R239") (pin "1") (pinfunction "1_1") (pintype "passive"))
    )
    (net (code "391") (name "unconnected-(R240-Pad2)") (class "Default")
      (node (ref "R240") (pin "2") (pinfunction "2_2") (pintype "passive"))
    )
    (net (code "392") (name "unconnected-(R242-Pad1)") (class "Default")
      (node (ref "R242") (pin "1") (pinfunction "1_1") (pintype "passive"))
    )
    (net (code "393") (name "unconnected-(R244-Pad1)") (class "Default")
      (node (ref "R244") (pin "1") (pinfunction "1_1") (pintype "passive"))
    )
    (net (code "394") (name "unconnected-(R249-Pad1)") (class "Default")
      (node (ref "R249") (pin "1") (pinfunction "1_1") (pintype "passive"))
    )
    (net (code "395") (name "unconnected-(R251-Pad1)") (class "Default")
      (node (ref "R251") (pin "1") (pinfunction "1_1") (pintype "passive"))
    )
    (net (code "396") (name "unconnected-(R253-Pad1)") (class "Default")
      (node (ref "R253") (pin "1") (pinfunction "1_1") (pintype "passive"))
    )
    (net (code "397") (name "unconnected-(R255-Pad1)") (class "Default")
      (node (ref "R255") (pin "1") (pinfunction "1_1") (pintype "passive"))
    )
    (net (code "398") (name "unconnected-(R259-Pad1)") (class "Default")
      (node (ref "R259") (pin "1") (pinfunction "1_1") (pintype "passive"))
    )
    (net (code "399") (name "unconnected-(R261-Pad1)") (class "Default")
      (node (ref "R261") (pin "1") (pinfunction "1_1") (pintype "passive"))
    )
    (net (code "400") (name "unconnected-(R261-Pad2)") (class "Default")
      (node (ref "R261") (pin "2") (pinfunction "2_2") (pintype "passive"))
    )
    (net (code "401") (name "unconnected-(R262-Pad1)") (class "Default")
      (node (ref "R262") (pin "1") (pinfunction "1_1") (pintype "passive"))
    )
    (net (code "402") (name "unconnected-(R263-Pad2)") (class "Default")
      (node (ref "R263") (pin "2") (pinfunction "2_2") (pintype "passive"))
    )
    (net (code "403") (name "unconnected-(R264-Pad1)") (class "Default")
      (node (ref "R264") (pin "1") (pinfunction "1_1") (pintype "passive"))
    )
    (net (code "404") (name "unconnected-(R265-Pad2)") (class "Default")
      (node (ref "R265") (pin "2") (pinfunction "2_2") (pintype "passive"))
    )
    (net (code "405") (name "unconnected-(R266-Pad1)") (class "Default")
      (node (ref "R266") (pin "1") (pinfunction "1_1") (pintype "passive"))
    )
    (net (code "406") (name "unconnected-(R267-Pad2)") (class "Default")
      (node (ref "R267") (pin "2") (pinfunction "2_2") (pintype "passive"))
    )
    (net (code "407") (name "unconnected-(R268-Pad1)") (class "Default")
      (node (ref "R268") (pin "1") (pinfunction "1_1") (pintype "passive"))
    )
    (net (code "408") (name "unconnected-(R268-Pad2)") (class "Default")
      (node (ref "R268") (pin "2") (pinfunction "2_2") (pintype "passive"))
    )
    (net (code "409") (name "unconnected-(R269-Pad1)") (class "Default")
      (node (ref "R269") (pin "1") (pinfunction "1_1") (pintype "passive"))
    )
    (net (code "410") (name "unconnected-(R270-Pad2)") (class "Default")
      (node (ref "R270") (pin "2") (pinfunction "2_2") (pintype "passive"))
    )
    (net (code "411") (name "unconnected-(R271-Pad1)") (class "Default")
      (node (ref "R271") (pin "1") (pinfunction "1_1") (pintype "passive"))
    )
    (net (code "412") (name "unconnected-(R272-Pad2)") (class "Default")
      (node (ref "R272") (pin "2") (pinfunction "2_2") (pintype "passive"))
    )
    (net (code "413") (name "unconnected-(R273-Pad1)") (class "Default")
      (node (ref "R273") (pin "1") (pinfunction "1_1") (pintype "passive"))
    )
    (net (code "414") (name "unconnected-(R274-Pad2)") (class "Default")
      (node (ref "R274") (pin "2") (pinfunction "2_2") (pintype "passive"))
    )
    (net (code "415") (name "unconnected-(R275-Pad1)") (class "Default")
      (node (ref "R275") (pin "1") (pinfunction "1_1") (pintype "passive"))
    )
    (net (code "416") (name "unconnected-(R276-Pad2)") (class "Default")
      (node (ref "R276") (pin "2") (pinfunction "2_2") (pintype "passive"))
    )
    (net (code "417") (name "unconnected-(R277-Pad1)") (class "Default")
      (node (ref "R277") (pin "1") (pinfunction "1_1") (pintype "passive"))
    )
    (net (code "418") (name "unconnected-(R278-Pad2)") (class "Default")
      (node (ref "R278") (pin "2") (pinfunction "2_2") (pintype "passive"))
    )
    (net (code "419") (name "unconnected-(R279-Pad1)") (class "Default")
      (node (ref "R279") (pin "1") (pinfunction "1_1") (pintype "passive"))
    )
    (net (code "420") (name "unconnected-(R279-Pad2)") (class "Default")
      (node (ref "R279") (pin "2") (pinfunction "2_2") (pintype "passive"))
    )
    (net (code "421") (name "unconnected-(R280-Pad1)") (class "Default")
      (node (ref "R280") (pin "1") (pinfunction "1_1") (pintype "passive"))
    )
    (net (code "422") (name "unconnected-(R281-Pad2)") (class "Default")
      (node (ref "R281") (pin "2") (pinfunction "2_2") (pintype "passive"))
    )
    (net (code "423") (name "unconnected-(R282-Pad1)") (class "Default")
      (node (ref "R282") (pin "1") (pinfunction "1_1") (pintype "passive"))
    )
    (net (code "424") (name "unconnected-(R283-Pad2)") (class "Default")
      (node (ref "R283") (pin "2") (pinfunction "2_2") (pintype "passive"))
    )
    (net (code "425") (name "unconnected-(R284-Pad1)") (class "Default")
      (node (ref "R284") (pin "1") (pinfunction "1_1") (pintype "passive"))
    )
    (net (code "426") (name "unconnected-(R285-Pad2)") (class "Default")
      (node (ref "R285") (pin "2") (pinfunction "2_2") (pintype "passive"))
    )
    (net (code "427") (name "unconnected-(R286-Pad1)") (class "Default")
      (node (ref "R286") (pin "1") (pinfunction "1_1") (pintype "passive"))
    )
    (net (code "428") (name "unconnected-(R287-Pad2)") (class "Default")
      (node (ref "R287") (pin "2") (pinfunction "2_2") (pintype "passive"))
    )
    (net (code "429") (name "unconnected-(R288-Pad1)") (class "Default")
      (node (ref "R288") (pin "1") (pinfunction "1_1") (pintype "passive"))
    )
    (net (code "430") (name "unconnected-(R288-Pad2)") (class "Default")
      (node (ref "R288") (pin "2") (pinfunction "2_2") (pintype "passive"))
    )
    (net (code "431") (name "unconnected-(R289-Pad1)") (class "Default")
      (node (ref "R289") (pin "1") (pinfunction "1_1") (pintype "passive"))
    )
    (net (code "432") (name "unconnected-(R290-Pad2)") (class "Default")
      (node (ref "R290") (pin "2") (pinfunction "2_2") (pintype "passive"))
    )
    (net (code "433") (name "unconnected-(R291-Pad1)") (class "Default")
      (node (ref "R291") (pin "1") (pinfunction "1_1") (pintype "passive"))
    )
    (net (code "434") (name "unconnected-(R292-Pad2)") (class "Default")
      (node (ref "R292") (pin "2") (pinfunction "2_2") (pintype "passive"))
    )
    (net (code "435") (name "unconnected-(R293-Pad1)") (class "Default")
      (node (ref "R293") (pin "1") (pinfunction "1_1") (pintype "passive"))
    )
    (net (code "436") (name "unconnected-(R294-Pad2)") (class "Default")
      (node (ref "R294") (pin "2") (pinfunction "2_2") (pintype "passive"))
    )
    (net (code "437") (name "unconnected-(R295-Pad1)") (class "Default")
      (node (ref "R295") (pin "1") (pinfunction "1_1") (pintype "passive"))
    )
    (net (code "438") (name "unconnected-(R295-Pad2)") (class "Default")
      (node (ref "R295") (pin "2") (pinfunction "2_2") (pintype "passive"))
    )
    (net (code "439") (name "unconnected-(R296-Pad1)") (class "Default")
      (node (ref "R296") (pin "1") (pinfunction "1_1") (pintype "passive"))
    )
    (net (code "440") (name "unconnected-(R297-Pad2)") (class "Default")
      (node (ref "R297") (pin "2") (pinfunction "2_2") (pintype "passive"))
    )
    (net (code "441") (name "unconnected-(R298-Pad1)") (class "Default")
      (node (ref "R298") (pin "1") (pinfunction "1_1") (pintype "passive"))
    )
    (net (code "442") (name "unconnected-(R299-Pad2)") (class "Default")
      (node (ref "R299") (pin "2") (pinfunction "2_2") (pintype "passive"))
    )
    (net (code "443") (name "unconnected-(R300-Pad1)") (class "Default")
      (node (ref "R300") (pin "1") (pinfunction "1_1") (pintype "passive"))
    )
    (net (code "444") (name "unconnected-(R301-Pad2)") (class "Default")
      (node (ref "R301") (pin "2") (pinfunction "2_2") (pintype "passive"))
    )
    (net (code "445") (name "unconnected-(R302-Pad1)") (class "Default")
      (node (ref "R302") (pin "1") (pinfunction "1_1") (pintype "passive"))
    )
    (net (code "446") (name "unconnected-(R302-Pad2)") (class "Default")
      (node (ref "R302") (pin "2") (pinfunction "2_2") (pintype "passive"))
    )
    (net (code "447") (name "unconnected-(R303-Pad1)") (class "Default")
      (node (ref "R303") (pin "1") (pinfunction "1_1") (pintype "passive"))
    )
    (net (code "448") (name "unconnected-(R304-Pad2)") (class "Default")
      (node (ref "R304") (pin "2") (pinfunction "2_2") (pintype "passive"))
    )
    (net (code "449") (name "unconnected-(R305-Pad1)") (class "Default")
      (node (ref "R305") (pin "1") (pinfunction "1_1") (pintype "passive"))
    )
    (net (code "450") (name "unconnected-(R306-Pad2)") (class "Default")
      (node (ref "R306") (pin "2") (pinfunction "2_2") (pintype "passive"))
    )
    (net (code "451") (name "unconnected-(R307-Pad1)") (class "Default")
      (node (ref "R307") (pin "1") (pinfunction "1_1") (pintype "passive"))
    )
    (net (code "452") (name "unconnected-(R308-Pad2)") (class "Default")
      (node (ref "R308") (pin "2") (pinfunction "2_2") (pintype "passive"))
    )
    (net (code "453") (name "unconnected-(R309-Pad1)") (class "Default")
      (node (ref "R309") (pin "1") (pinfunction "1_1") (pintype "passive"))
    )
    (net (code "454") (name "unconnected-(R310-Pad2)") (class "Default")
      (node (ref "R310") (pin "2") (pinfunction "2_2") (pintype "passive"))
    )
    (net (code "455") (name "unconnected-(R311-Pad1)") (class "Default")
      (node (ref "R311") (pin "1") (pinfunction "1_1") (pintype "passive"))
    )
    (net (code "456") (name "unconnected-(R311-Pad2)") (class "Default")
      (node (ref "R311") (pin "2") (pinfunction "2_2") (pintype "passive"))
    )
    (net (code "457") (name "unconnected-(R312-Pad1)") (class "Default")
      (node (ref "R312") (pin "1") (pinfunction "1_1") (pintype "passive"))
    )
    (net (code "458") (name "unconnected-(R313-Pad2)") (class "Default")
      (node (ref "R313") (pin "2") (pinfunction "2_2") (pintype "passive"))
    )
    (net (code "459") (name "unconnected-(R314-Pad1)") (class "Default")
      (node (ref "R314") (pin "1") (pinfunction "1_1") (pintype "passive"))
    )
    (net (code "460") (name "unconnected-(R315-Pad2)") (class "Default")
      (node (ref "R315") (pin "2") (pinfunction "2_2") (pintype "passive"))
    )
    (net (code "461") (name "unconnected-(R316-Pad1)") (class "Default")
      (node (ref "R316") (pin "1") (pinfunction "1_1") (pintype "passive"))
    )
    (net (code "462") (name "unconnected-(R317-Pad2)") (class "Default")
      (node (ref "R317") (pin "2") (pinfunction "2_2") (pintype "passive"))
    )
    (net (code "463") (name "unconnected-(U1A-PA0-WKUP-Pad23)") (class "Default")
      (node (ref "U1") (pin "23") (pinfunction "PA0-WKUP_23") (pintype "bidirectional"))
    )
    (net (code "464") (name "unconnected-(U1A-PA1-Pad24)") (class "Default")
      (node (ref "U1") (pin "24") (pinfunction "PA1_24") (pintype "bidirectional"))
    )
    (net (code "465") (name "unconnected-(U1A-PA2-Pad25)") (class "Default")
      (node (ref "U1") (pin "25") (pinfunction "PA2_25") (pintype "bidirectional"))
    )
    (net (code "466") (name "unconnected-(U1A-PA3-Pad26)") (class "Default")
      (node (ref "U1") (pin "26") (pinfunction "PA3_26") (pintype "bidirectional"))
    )
    (net (code "467") (name "unconnected-(U1A-PA4-Pad29)") (class "Default")
      (node (ref "U1") (pin "29") (pinfunction "PA4_29") (pintype "bidirectional"))
    )
    (net (code "468") (name "unconnected-(U1A-PA5-Pad30)") (class "Default")
      (node (ref "U1") (pin "30") (pinfunction "PA5_30") (pintype "bidirectional"))
    )
    (net (code "469") (name "unconnected-(U1A-PA6-Pad31)") (class "Default")
      (node (ref "U1") (pin "31") (pinfunction "PA6_31") (pintype "bidirectional"))
    )
    (net (code "470") (name "unconnected-(U1A-PA14-Pad76)") (class "Default")
      (node (ref "U1") (pin "76") (pinfunction "PA14_76") (pintype "bidirectional"))
    )
    (net (code "471") (name "unconnected-(U1A-PC6-Pad63)") (class "Default")
      (node (ref "U1") (pin "63") (pinfunction "PC6_63") (pintype "bidirectional"))
    )
    (net (code "472") (name "unconnected-(U1A-PC9-Pad66)") (class "Default")
      (node (ref "U1") (pin "66") (pinfunction "PC9_66") (pintype "bidirectional"))
    )
    (net (code "473") (name "unconnected-(U1A-PC10-Pad78)") (class "Default")
      (node (ref "U1") (pin "78") (pinfunction "PC10_78") (pintype "bidirectional"))
    )
    (net (code "474") (name "unconnected-(U1A-PC11-Pad79)") (class "Default")
      (node (ref "U1") (pin "79") (pinfunction "PC11_79") (pintype "bidirectional"))
    )
    (net (code "475") (name "unconnected-(U1A-PC12-Pad80)") (class "Default")
      (node (ref "U1") (pin "80") (pinfunction "PC12_80") (pintype "bidirectional"))
    )
    (net (code "476") (name "unconnected-(U1A-PC13-TAMPER-RTC-Pad7)") (class "Default")
      (node (ref "U1") (pin "7") (pinfunction "PC13-TAMPER-RTC_7") (pintype "bidirectional"))
    )
    (net (code "477") (name "unconnected-(U1A-PC14-OSC32_IN-Pad8)") (class "Default")
      (node (ref "U1") (pin "8") (pinfunction "PC14-OSC32_IN_8") (pintype "bidirectional"))
    )
    (net (code "478") (name "unconnected-(U1A-PE1-Pad98)") (class "Default")
      (node (ref "U1") (pin "98") (pinfunction "PE1_98") (pintype "bidirectional"))
    )
    (net (code "479") (name "unconnected-(U1A-PE2-Pad1)") (class "Default")
      (node (ref "U1") (pin "1") (pinfunction "PE2_1") (pintype "bidirectional"))
    )
    (net (code "480") (name "unconnected-(U1A-PE3-Pad2)") (class "Default")
      (node (ref "U1") (pin "2") (pinfunction "PE3_2") (pintype "bidirectional"))
    )
    (net (code "481") (name "unconnected-(U1A-PE4-Pad3)") (class "Default")
      (node (ref "U1") (pin "3") (pinfunction "PE4_3") (pintype "bidirectional"))
    )
    (net (code "482") (name "unconnected-(U1A-PE5-Pad4)") (class "Default")
      (node (ref "U1") (pin "4") (pinfunction "PE5_4") (pintype "bidirectional"))
    )
    (net (code "483") (name "unconnected-(U1A-PE6-Pad5)") (class "Default")
      (node (ref "U1") (pin "5") (pinfunction "PE6_5") (pintype "bidirectional"))
    )
    (net (code "484") (name "unconnected-(U1A-PE7-Pad38)") (class "Default")
      (node (ref "U1") (pin "38") (pinfunction "PE7_38") (pintype "bidirectional"))
    )
    (net (code "485") (name "unconnected-(U1A-PE8-Pad39)") (class "Default")
      (node (ref "U1") (pin "39") (pinfunction "PE8_39") (pintype "bidirectional"))
    )
    (net (code "486") (name "unconnected-(U1A-PE9-Pad40)") (class "Default")
      (node (ref "U1") (pin "40") (pinfunction "PE9_40") (pintype "bidirectional"))
    )
    (net (code "487") (name "unconnected-(U1A-PE10-Pad41)") (class "Default")
      (node (ref "U1") (pin "41") (pinfunction "PE10_41") (pintype "bidirectional"))
    )
    (net (code "488") (name "unconnected-(U1A-PE11-Pad42)") (class "Default")
      (node (ref "U1") (pin "42") (pinfunction "PE11_42") (pintype "bidirectional"))
    )
    (net (code "489") (name "unconnected-(U1A-PE12-Pad43)") (class "Default")
      (node (ref "U1") (pin "43") (pinfunction "PE12_43") (pintype "bidirectional"))
    )
    (net (code "490") (name "unconnected-(U1A-PE13-Pad44)") (class "Default")
      (node (ref "U1") (pin "44") (pinfunction "PE13_44") (pintype "bidirectional"))
    )
    (net (code "491") (name "unconnected-(U1A-PE14-Pad45)") (class "Default")
      (node (ref "U1") (pin "45") (pinfunction "PE14_45") (pintype "bidirectional"))
    )
    (net (code "492") (name "unconnected-(U1A-PE15-Pad46)") (class "Default")
      (node (ref "U1") (pin "46") (pinfunction "PE15_46") (pintype "bidirectional"))
    )
    (net (code "493") (name "unconnected-(U2A-BOOT0-Pad94)") (class "Default")
      (node (ref "U2") (pin "94") (pinfunction "BOOT0_94") (pintype "input"))
    )
    (net (code "494") (name "unconnected-(U2A-NRST-Pad14)") (class "Default")
      (node (ref "U2") (pin "14") (pinfunction "NRST_14") (pintype "bidirectional"))
    )
    (net (code "495") (name "unconnected-(U2A-OSC_IN-Pad12)") (class "Default")
      (node (ref "U2") (pin "12") (pinfunction "OSC_IN_12") (pintype "input"))
    )
    (net (code "496") (name "unconnected-(U2A-OSC_OUT-Pad13)") (class "Default")
      (node (ref "U2") (pin "13") (pinfunction "OSC_OUT_13") (pintype "output"))
    )
    (net (code "497") (name "unconnected-(U2A-PA0-WKUP-Pad23)") (class "Default")
      (node (ref "U2") (pin "23") (pinfunction "PA0-WKUP_23") (pintype "bidirectional"))
    )
    (net (code "498") (name "unconnected-(U2A-PA1-Pad24)") (class "Default")
      (node (ref "U2") (pin "24") (pinfunction "PA1_24") (pintype "bidirectional"))
    )
    (net (code "499") (name "unconnected-(U2A-PA2-Pad25)") (class "Default")
      (node (ref "U2") (pin "25") (pinfunction "PA2_25") (pintype "bidirectional"))
    )
    (net (code "500") (name "unconnected-(U2A-PA3-Pad26)") (class "Default")
      (node (ref "U2") (pin "26") (pinfunction "PA3_26") (pintype "bidirectional"))
    )
    (net (code "501") (name "unconnected-(U2A-PA4-Pad29)") (class "Default")
      (node (ref "U2") (pin "29") (pinfunction "PA4_29") (pintype "bidirectional"))
    )
    (net (code "502") (name "unconnected-(U2A-PA5-Pad30)") (class "Default")
      (node (ref "U2") (pin "30") (pinfunction "PA5_30") (pintype "bidirectional"))
    )
    (net (code "503") (name "unconnected-(U2A-PA6-Pad31)") (class "Default")
      (node (ref "U2") (pin "31") (pinfunction "PA6_31") (pintype "bidirectional"))
    )
    (net (code "504") (name "unconnected-(U2A-PA7-Pad32)") (class "Default")
      (node (ref "U2") (pin "32") (pinfunction "PA7_32") (pintype "bidirectional"))
    )
    (net (code "505") (name "unconnected-(U2A-PA8-Pad67)") (class "Default")
      (node (ref "U2") (pin "67") (pinfunction "PA8_67") (pintype "bidirectional"))
    )
    (net (code "506") (name "unconnected-(U2A-PA9-Pad68)") (class "Default")
      (node (ref "U2") (pin "68") (pinfunction "PA9_68") (pintype "bidirectional"))
    )
    (net (code "507") (name "unconnected-(U2A-PA10-Pad69)") (class "Default")
      (node (ref "U2") (pin "69") (pinfunction "PA10_69") (pintype "bidirectional"))
    )
    (net (code "508") (name "unconnected-(U2A-PA11-Pad70)") (class "Default")
      (node (ref "U2") (pin "70") (pinfunction "PA11_70") (pintype "bidirectional"))
    )
    (net (code "509") (name "unconnected-(U2A-PA12-Pad71)") (class "Default")
      (node (ref "U2") (pin "71") (pinfunction "PA12_71") (pintype "bidirectional"))
    )
    (net (code "510") (name "unconnected-(U2A-PA13-Pad72)") (class "Default")
      (node (ref "U2") (pin "72") (pinfunction "PA13_72") (pintype "bidirectional"))
    )
    (net (code "511") (name "unconnected-(U2A-PA14-Pad76)") (class "Default")
      (node (ref "U2") (pin "76") (pinfunction "PA14_76") (pintype "bidirectional"))
    )
    (net (code "512") (name "unconnected-(U2A-PA15-Pad77)") (class "Default")
      (node (ref "U2") (pin "77") (pinfunction "PA15_77") (pintype "bidirectional"))
    )
    (net (code "513") (name "unconnected-(U2A-PB0-Pad35)") (class "Default")
      (node (ref "U2") (pin "35") (pinfunction "PB0_35") (pintype "bidirectional"))
    )
    (net (code "514") (name "unconnected-(U2A-PB1-Pad36)") (class "Default")
      (node (ref "U2") (pin "36") (pinfunction "PB1_36") (pintype "bidirectional"))
    )
    (net (code "515") (name "unconnected-(U2A-PB2-Pad37)") (class "Default")
      (node (ref "U2") (pin "37") (pinfunction "PB2_37") (pintype "bidirectional"))
    )
    (net (code "516") (name "unconnected-(U2A-PB3-Pad89)") (class "Default")
      (node (ref "U2") (pin "89") (pinfunction "PB3_89") (pintype "bidirectional"))
    )
    (net (code "517") (name "unconnected-(U2A-PB4-Pad90)") (class "Default")
      (node (ref "U2") (pin "90") (pinfunction "PB4_90") (pintype "bidirectional"))
    )
    (net (code "518") (name "unconnected-(U2A-PB5-Pad91)") (class "Default")
      (node (ref "U2") (pin "91") (pinfunction "PB5_91") (pintype "bidirectional"))
    )
    (net (code "519") (name "unconnected-(U2A-PB6-Pad92)") (class "Default")
      (node (ref "U2") (pin "92") (pinfunction "PB6_92") (pintype "bidirectional"))
    )
    (net (code "520") (name "unconnected-(U2A-PB7-Pad93)") (class "Default")
      (node (ref "U2") (pin "93") (pinfunction "PB7_93") (pintype "bidirectional"))
    )
    (net (code "521") (name "unconnected-(U2A-PB8-Pad95)") (class "Default")
      (node (ref "U2") (pin "95") (pinfunction "PB8_95") (pintype "bidirectional"))
    )
    (net (code "522") (name "unconnected-(U2A-PB9-Pad96)") (class "Default")
      (node (ref "U2") (pin "96") (pinfunction "PB9_96") (pintype "bidirectional"))
    )
    (net (code "523") (name "unconnected-(U2A-PB10-Pad47)") (class "Default")
      (node (ref "U2") (pin "47") (pinfunction "PB10_47") (pintype "bidirectional"))
    )
    (net (code "524") (name "unconnected-(U2A-PB11-Pad48)") (class "Default")
      (node (ref "U2") (pin "48") (pinfunction "PB11_48") (pintype "bidirectional"))
    )
    (net (code "525") (name "unconnected-(U2A-PB12-Pad51)") (class "Default")
      (node (ref "U2") (pin "51") (pinfunction "PB12_51") (pintype "bidirectional"))
    )
    (net (code "526") (name "unconnected-(U2A-PB13-Pad52)") (class "Default")
      (node (ref "U2") (pin "52") (pinfunction "PB13_52") (pintype "bidirectional"))
    )
    (net (code "527") (name "unconnected-(U2A-PB14-Pad53)") (class "Default")
      (node (ref "U2") (pin "53") (pinfunction "PB14_53") (pintype "bidirectional"))
    )
    (net (code "528") (name "unconnected-(U2A-PB15-Pad54)") (class "Default")
      (node (ref "U2") (pin "54") (pinfunction "PB15_54") (pintype "bidirectional"))
    )
    (net (code "529") (name "unconnected-(U2A-PC0-Pad15)") (class "Default")
      (node (ref "U2") (pin "15") (pinfunction "PC0_15") (pintype "bidirectional"))
    )
    (net (code "530") (name "unconnected-(U2A-PC1-Pad16)") (class "Default")
      (node (ref "U2") (pin "16") (pinfunction "PC1_16") (pintype "bidirectional"))
    )
    (net (code "531") (name "unconnected-(U2A-PC2-Pad17)") (class "Default")
      (node (ref "U2") (pin "17") (pinfunction "PC2_17") (pintype "bidirectional"))
    )
    (net (code "532") (name "unconnected-(U2A-PC3-Pad18)") (class "Default")
      (node (ref "U2") (pin "18") (pinfunction "PC3_18") (pintype "bidirectional"))
    )
    (net (code "533") (name "unconnected-(U2A-PC4-Pad33)") (class "Default")
      (node (ref "U2") (pin "33") (pinfunction "PC4_33") (pintype "bidirectional"))
    )
    (net (code "534") (name "unconnected-(U2A-PC5-Pad34)") (class "Default")
      (node (ref "U2") (pin "34") (pinfunction "PC5_34") (pintype "bidirectional"))
    )
    (net (code "535") (name "unconnected-(U2A-PC6-Pad63)") (class "Default")
      (node (ref "U2") (pin "63") (pinfunction "PC6_63") (pintype "bidirectional"))
    )
    (net (code "536") (name "unconnected-(U2A-PC7-Pad64)") (class "Default")
      (node (ref "U2") (pin "64") (pinfunction "PC7_64") (pintype "bidirectional"))
    )
    (net (code "537") (name "unconnected-(U2A-PC9-Pad66)") (class "Default")
      (node (ref "U2") (pin "66") (pinfunction "PC9_66") (pintype "bidirectional"))
    )
    (net (code "538") (name "unconnected-(U2A-PC10-Pad78)") (class "Default")
      (node (ref "U2") (pin "78") (pinfunction "PC10_78") (pintype "bidirectional"))
    )
    (net (code "539") (name "unconnected-(U2A-PC11-Pad79)") (class "Default")
      (node (ref "U2") (pin "79") (pinfunction "PC11_79") (pintype "bidirectional"))
    )
    (net (code "540") (name "unconnected-(U2A-PC12-Pad80)") (class "Default")
      (node (ref "U2") (pin "80") (pinfunction "PC12_80") (pintype "bidirectional"))
    )
    (net (code "541") (name "unconnected-(U2A-PC13-TAMPER-RTC-Pad7)") (class "Default")
      (node (ref "U2") (pin "7") (pinfunction "PC13-TAMPER-RTC_7") (pintype "bidirectional"))
    )
    (net (code "542") (name "unconnected-(U2A-PC14-OSC32_IN-Pad8)") (class "Default")
      (node (ref "U2") (pin "8") (pinfunction "PC14-OSC32_IN_8") (pintype "bidirectional"))
    )
    (net (code "543") (name "unconnected-(U2A-PC15-OSC32_OUT-Pad9)") (class "Default")
      (node (ref "U2") (pin "9") (pinfunction "PC15-OSC32_OUT_9") (pintype "bidirectional"))
    )
    (net (code "544") (name "unconnected-(U2A-PD0-Pad81)") (class "Default")
      (node (ref "U2") (pin "81") (pinfunction "PD0_81") (pintype "bidirectional"))
    )
    (net (code "545") (name "unconnected-(U2A-PD1-Pad82)") (class "Default")
      (node (ref "U2") (pin "82") (pinfunction "PD1_82") (pintype "bidirectional"))
    )
    (net (code "546") (name "unconnected-(U2A-PD2-Pad83)") (class "Default")
      (node (ref "U2") (pin "83") (pinfunction "PD2_83") (pintype "bidirectional"))
    )
    (net (code "547") (name "unconnected-(U2A-PD3-Pad84)") (class "Default")
      (node (ref "U2") (pin "84") (pinfunction "PD3_84") (pintype "bidirectional"))
    )
    (net (code "548") (name "unconnected-(U2A-PD4-Pad85)") (class "Default")
      (node (ref "U2") (pin "85") (pinfunction "PD4_85") (pintype "bidirectional"))
    )
    (net (code "549") (name "unconnected-(U2A-PD5-Pad86)") (class "Default")
      (node (ref "U2") (pin "86") (pinfunction "PD5_86") (pintype "bidirectional"))
    )
    (net (code "550") (name "unconnected-(U2A-PD6-Pad87)") (class "Default")
      (node (ref "U2") (pin "87") (pinfunction "PD6_87") (pintype "bidirectional"))
    )
    (net (code "551") (name "unconnected-(U2A-PD7-Pad88)") (class "Default")
      (node (ref "U2") (pin "88") (pinfunction "PD7_88") (pintype "bidirectional"))
    )
    (net (code "552") (name "unconnected-(U2A-PD9-Pad56)") (class "Default")
      (node (ref "U2") (pin "56") (pinfunction "PD9_56") (pintype "bidirectional"))
    )
    (net (code "553") (name "unconnected-(U2A-PD10-Pad57)") (class "Default")
      (node (ref "U2") (pin "57") (pinfunction "PD10_57") (pintype "bidirectional"))
    )
    (net (code "554") (name "unconnected-(U2A-PD11-Pad58)") (class "Default")
      (node (ref "U2") (pin "58") (pinfunction "PD11_58") (pintype "bidirectional"))
    )
    (net (code "555") (name "unconnected-(U2A-PD12-Pad59)") (class "Default")
      (node (ref "U2") (pin "59") (pinfunction "PD12_59") (pintype "bidirectional"))
    )
    (net (code "556") (name "unconnected-(U2A-PD13-Pad60)") (class "Default")
      (node (ref "U2") (pin "60") (pinfunction "PD13_60") (pintype "bidirectional"))
    )
    (net (code "557") (name "unconnected-(U2A-PD14-Pad61)") (class "Default")
      (node (ref "U2") (pin "61") (pinfunction "PD14_61") (pintype "bidirectional"))
    )
    (net (code "558") (name "unconnected-(U2A-PD15-Pad62)") (class "Default")
      (node (ref "U2") (pin "62") (pinfunction "PD15_62") (pintype "bidirectional"))
    )
    (net (code "559") (name "unconnected-(U2A-PE0-Pad97)") (class "Default")
      (node (ref "U2") (pin "97") (pinfunction "PE0_97") (pintype "bidirectional"))
    )
    (net (code "560") (name "unconnected-(U2A-PE1-Pad98)") (class "Default")
      (node (ref "U2") (pin "98") (pinfunction "PE1_98") (pintype "bidirectional"))
    )
    (net (code "561") (name "unconnected-(U2A-PE2-Pad1)") (class "Default")
      (node (ref "U2") (pin "1") (pinfunction "PE2_1") (pintype "bidirectional"))
    )
    (net (code "562") (name "unconnected-(U2A-PE3-Pad2)") (class "Default")
      (node (ref "U2") (pin "2") (pinfunction "PE3_2") (pintype "bidirectional"))
    )
    (net (code "563") (name "unconnected-(U2A-PE4-Pad3)") (class "Default")
      (node (ref "U2") (pin "3") (pinfunction "PE4_3") (pintype "bidirectional"))
    )
    (net (code "564") (name "unconnected-(U2A-PE5-Pad4)") (class "Default")
      (node (ref "U2") (pin "4") (pinfunction "PE5_4") (pintype "bidirectional"))
    )
    (net (code "565") (name "unconnected-(U2A-PE6-Pad5)") (class "Default")
      (node (ref "U2") (pin "5") (pinfunction "PE6_5") (pintype "bidirectional"))
    )
    (net (code "566") (name "unconnected-(U2A-PE7-Pad38)") (class "Default")
      (node (ref "U2") (pin "38") (pinfunction "PE7_38") (pintype "bidirectional"))
    )
    (net (code "567") (name "unconnected-(U2A-PE8-Pad39)") (class "Default")
      (node (ref "U2") (pin "39") (pinfunction "PE8_39") (pintype "bidirectional"))
    )
    (net (code "568") (name "unconnected-(U2A-PE9-Pad40)") (class "Default")
      (node (ref "U2") (pin "40") (pinfunction "PE9_40") (pintype "bidirectional"))
    )
    (net (code "569") (name "unconnected-(U2A-PE10-Pad41)") (class "Default")
      (node (ref "U2") (pin "41") (pinfunction "PE10_41") (pintype "bidirectional"))
    )
    (net (code "570") (name "unconnected-(U2A-PE11-Pad42)") (class "Default")
      (node (ref "U2") (pin "42") (pinfunction "PE11_42") (pintype "bidirectional"))
    )
    (net (code "571") (name "unconnected-(U2A-PE12-Pad43)") (class "Default")
      (node (ref "U2") (pin "43") (pinfunction "PE12_43") (pintype "bidirectional"))
    )
    (net (code "572") (name "unconnected-(U2A-PE13-Pad44)") (class "Default")
      (node (ref "U2") (pin "44") (pinfunction "PE13_44") (pintype "bidirectional"))
    )
    (net (code "573") (name "unconnected-(U2A-PE14-Pad45)") (class "Default")
      (node (ref "U2") (pin "45") (pinfunction "PE14_45") (pintype "bidirectional"))
    )
    (net (code "574") (name "unconnected-(U2A-PE15-Pad46)") (class "Default")
      (node (ref "U2") (pin "46") (pinfunction "PE15_46") (pintype "bidirectional"))
    )
    (net (code "575") (name "unconnected-(U3A-BOOT0-Pad94)") (class "Default")
      (node (ref "U3") (pin "94") (pinfunction "BOOT0_94") (pintype "input"))
    )
    (net (code "576") (name "unconnected-(U3A-NRST-Pad14)") (class "Default")
      (node (ref "U3") (pin "14") (pinfunction "NRST_14") (pintype "bidirectional"))
    )
    (net (code "577") (name "unconnected-(U3A-OSC_IN-Pad12)") (class "Default")
      (node (ref "U3") (pin "12") (pinfunction "OSC_IN_12") (pintype "input"))
    )
    (net (code "578") (name "unconnected-(U3A-OSC_OUT-Pad13)") (class "Default")
      (node (ref "U3") (pin "13") (pinfunction "OSC_OUT_13") (pintype "output"))
    )
    (net (code "579") (name "unconnected-(U3A-PA0-WKUP-Pad23)") (class "Default")
      (node (ref "U3") (pin "23") (pinfunction "PA0-WKUP_23") (pintype "bidirectional"))
    )
    (net (code "580") (name "unconnected-(U3A-PA1-Pad24)") (class "Default")
      (node (ref "U3") (pin "24") (pinfunction "PA1_24") (pintype "bidirectional"))
    )
    (net (code "581") (name "unconnected-(U3A-PA2-Pad25)") (class "Default")
      (node (ref "U3") (pin "25") (pinfunction "PA2_25") (pintype "bidirectional"))
    )
    (net (code "582") (name "unconnected-(U3A-PA3-Pad26)") (class "Default")
      (node (ref "U3") (pin "26") (pinfunction "PA3_26") (pintype "bidirectional"))
    )
    (net (code "583") (name "unconnected-(U3A-PA4-Pad29)") (class "Default")
      (node (ref "U3") (pin "29") (pinfunction "PA4_29") (pintype "bidirectional"))
    )
    (net (code "584") (name "unconnected-(U3A-PA5-Pad30)") (class "Default")
      (node (ref "U3") (pin "30") (pinfunction "PA5_30") (pintype "bidirectional"))
    )
    (net (code "585") (name "unconnected-(U3A-PA6-Pad31)") (class "Default")
      (node (ref "U3") (pin "31") (pinfunction "PA6_31") (pintype "bidirectional"))
    )
    (net (code "586") (name "unconnected-(U3A-PA14-Pad76)") (class "Default")
      (node (ref "U3") (pin "76") (pinfunction "PA14_76") (pintype "bidirectional"))
    )
    (net (code "587") (name "unconnected-(U3A-PB0-Pad35)") (class "Default")
      (node (ref "U3") (pin "35") (pinfunction "PB0_35") (pintype "bidirectional"))
    )
    (net (code "588") (name "unconnected-(U3A-PB1-Pad36)") (class "Default")
      (node (ref "U3") (pin "36") (pinfunction "PB1_36") (pintype "bidirectional"))
    )
    (net (code "589") (name "unconnected-(U3A-PB2-Pad37)") (class "Default")
      (node (ref "U3") (pin "37") (pinfunction "PB2_37") (pintype "bidirectional"))
    )
    (net (code "590") (name "unconnected-(U3A-PB3-Pad89)") (class "Default")
      (node (ref "U3") (pin "89") (pinfunction "PB3_89") (pintype "bidirectional"))
    )
    (net (code "591") (name "unconnected-(U3A-PB4-Pad90)") (class "Default")
      (node (ref "U3") (pin "90") (pinfunction "PB4_90") (pintype "bidirectional"))
    )
    (net (code "592") (name "unconnected-(U3A-PB5-Pad91)") (class "Default")
      (node (ref "U3") (pin "91") (pinfunction "PB5_91") (pintype "bidirectional"))
    )
    (net (code "593") (name "unconnected-(U3A-PB6-Pad92)") (class "Default")
      (node (ref "U3") (pin "92") (pinfunction "PB6_92") (pintype "bidirectional"))
    )
    (net (code "594") (name "unconnected-(U3A-PB7-Pad93)") (class "Default")
      (node (ref "U3") (pin "93") (pinfunction "PB7_93") (pintype "bidirectional"))
    )
    (net (code "595") (name "unconnected-(U3A-PB8-Pad95)") (class "Default")
      (node (ref "U3") (pin "95") (pinfunction "PB8_95") (pintype "bidirectional"))
    )
    (net (code "596") (name "unconnected-(U3A-PB9-Pad96)") (class "Default")
      (node (ref "U3") (pin "96") (pinfunction "PB9_96") (pintype "bidirectional"))
    )
    (net (code "597") (name "unconnected-(U3A-PB10-Pad47)") (class "Default")
      (node (ref "U3") (pin "47") (pinfunction "PB10_47") (pintype "bidirectional"))
    )
    (net (code "598") (name "unconnected-(U3A-PB11-Pad48)") (class "Default")
      (node (ref "U3") (pin "48") (pinfunction "PB11_48") (pintype "bidirectional"))
    )
    (net (code "599") (name "unconnected-(U3A-PB12-Pad51)") (class "Default")
      (node (ref "U3") (pin "51") (pinfunction "PB12_51") (pintype "bidirectional"))
    )
    (net (code "600") (name "unconnected-(U3A-PB13-Pad52)") (class "Default")
      (node (ref "U3") (pin "52") (pinfunction "PB13_52") (pintype "bidirectional"))
    )
    (net (code "601") (name "unconnected-(U3A-PB14-Pad53)") (class "Default")
      (node (ref "U3") (pin "53") (pinfunction "PB14_53") (pintype "bidirectional"))
    )
    (net (code "602") (name "unconnected-(U3A-PB15-Pad54)") (class "Default")
      (node (ref "U3") (pin "54") (pinfunction "PB15_54") (pintype "bidirectional"))
    )
    (net (code "603") (name "unconnected-(U3A-PC6-Pad63)") (class "Default")
      (node (ref "U3") (pin "63") (pinfunction "PC6_63") (pintype "bidirectional"))
    )
    (net (code "604") (name "unconnected-(U3A-PC9-Pad66)") (class "Default")
      (node (ref "U3") (pin "66") (pinfunction "PC9_66") (pintype "bidirectional"))
    )
    (net (code "605") (name "unconnected-(U3A-PC10-Pad78)") (class "Default")
      (node (ref "U3") (pin "78") (pinfunction "PC10_78") (pintype "bidirectional"))
    )
    (net (code "606") (name "unconnected-(U3A-PC11-Pad79)") (class "Default")
      (node (ref "U3") (pin "79") (pinfunction "PC11_79") (pintype "bidirectional"))
    )
    (net (code "607") (name "unconnected-(U3A-PC12-Pad80)") (class "Default")
      (node (ref "U3") (pin "80") (pinfunction "PC12_80") (pintype "bidirectional"))
    )
    (net (code "608") (name "unconnected-(U3A-PC13-TAMPER-RTC-Pad7)") (class "Default")
      (node (ref "U3") (pin "7") (pinfunction "PC13-TAMPER-RTC_7") (pintype "bidirectional"))
    )
    (net (code "609") (name "unconnected-(U3A-PC14-OSC32_IN-Pad8)") (class "Default")
      (node (ref "U3") (pin "8") (pinfunction "PC14-OSC32_IN_8") (pintype "bidirectional"))
    )
    (net (code "610") (name "unconnected-(U3A-PD0-Pad81)") (class "Default")
      (node (ref "U3") (pin "81") (pinfunction "PD0_81") (pintype "bidirectional"))
    )
    (net (code "611") (name "unconnected-(U3A-PD1-Pad82)") (class "Default")
      (node (ref "U3") (pin "82") (pinfunction "PD1_82") (pintype "bidirectional"))
    )
    (net (code "612") (name "unconnected-(U3A-PD2-Pad83)") (class "Default")
      (node (ref "U3") (pin "83") (pinfunction "PD2_83") (pintype "bidirectional"))
    )
    (net (code "613") (name "unconnected-(U3A-PD3-Pad84)") (class "Default")
      (node (ref "U3") (pin "84") (pinfunction "PD3_84") (pintype "bidirectional"))
    )
    (net (code "614") (name "unconnected-(U3A-PD4-Pad85)") (class "Default")
      (node (ref "U3") (pin "85") (pinfunction "PD4_85") (pintype "bidirectional"))
    )
    (net (code "615") (name "unconnected-(U3A-PD5-Pad86)") (class "Default")
      (node (ref "U3") (pin "86") (pinfunction "PD5_86") (pintype "bidirectional"))
    )
    (net (code "616") (name "unconnected-(U3A-PD6-Pad87)") (class "Default")
      (node (ref "U3") (pin "87") (pinfunction "PD6_87") (pintype "bidirectional"))
    )
    (net (code "617") (name "unconnected-(U3A-PD7-Pad88)") (class "Default")
      (node (ref "U3") (pin "88") (pinfunction "PD7_88") (pintype "bidirectional"))
    )
    (net (code "618") (name "unconnected-(U3A-PD9-Pad56)") (class "Default")
      (node (ref "U3") (pin "56") (pinfunction "PD9_56") (pintype "bidirectional"))
    )
    (net (code "619") (name "unconnected-(U3A-PD10-Pad57)") (class "Default")
      (node (ref "U3") (pin "57") (pinfunction "PD10_57") (pintype "bidirectional"))
    )
    (net (code "620") (name "unconnected-(U3A-PD11-Pad58)") (class "Default")
      (node (ref "U3") (pin "58") (pinfunction "PD11_58") (pintype "bidirectional"))
    )
    (net (code "621") (name "unconnected-(U3A-PD12-Pad59)") (class "Default")
      (node (ref "U3") (pin "59") (pinfunction "PD12_59") (pintype "bidirectional"))
    )
    (net (code "622") (name "unconnected-(U3A-PD13-Pad60)") (class "Default")
      (node (ref "U3") (pin "60") (pinfunction "PD13_60") (pintype "bidirectional"))
    )
    (net (code "623") (name "unconnected-(U3A-PD14-Pad61)") (class "Default")
      (node (ref "U3") (pin "61") (pinfunction "PD14_61") (pintype "bidirectional"))
    )
    (net (code "624") (name "unconnected-(U3A-PD15-Pad62)") (class "Default")
      (node (ref "U3") (pin "62") (pinfunction "PD15_62") (pintype "bidirectional"))
    )
    (net (code "625") (name "unconnected-(U3A-PE1-Pad98)") (class "Default")
      (node (ref "U3") (pin "98") (pinfunction "PE1_98") (pintype "bidirectional"))
    )
    (net (code "626") (name "unconnected-(U3A-PE2-Pad1)") (class "Default")
      (node (ref "U3") (pin "1") (pinfunction "PE2_1") (pintype "bidirectional"))
    )
    (net (code "627") (name "unconnected-(U3A-PE3-Pad2)") (class "Default")
      (node (ref "U3") (pin "2") (pinfunction "PE3_2") (pintype "bidirectional"))
    )
    (net (code "628") (name "unconnected-(U3A-PE4-Pad3)") (class "Default")
      (node (ref "U3") (pin "3") (pinfunction "PE4_3") (pintype "bidirectional"))
    )
    (net (code "629") (name "unconnected-(U3A-PE5-Pad4)") (class "Default")
      (node (ref "U3") (pin "4") (pinfunction "PE5_4") (pintype "bidirectional"))
    )
    (net (code "630") (name "unconnected-(U3A-PE6-Pad5)") (class "Default")
      (node (ref "U3") (pin "5") (pinfunction "PE6_5") (pintype "bidirectional"))
    )
    (net (code "631") (name "unconnected-(U3A-PE7-Pad38)") (class "Default")
      (node (ref "U3") (pin "38") (pinfunction "PE7_38") (pintype "bidirectional"))
    )
    (net (code "632") (name "unconnected-(U3A-PE8-Pad39)") (class "Default")
      (node (ref "U3") (pin "39") (pinfunction "PE8_39") (pintype "bidirectional"))
    )
    (net (code "633") (name "unconnected-(U3A-PE9-Pad40)") (class "Default")
      (node (ref "U3") (pin "40") (pinfunction "PE9_40") (pintype "bidirectional"))
    )
    (net (code "634") (name "unconnected-(U3A-PE10-Pad41)") (class "Default")
      (node (ref "U3") (pin "41") (pinfunction "PE10_41") (pintype "bidirectional"))
    )
    (net (code "635") (name "unconnected-(U3A-PE11-Pad42)") (class "Default")
      (node (ref "U3") (pin "42") (pinfunction "PE11_42") (pintype "bidirectional"))
    )
    (net (code "636") (name "unconnected-(U3A-PE12-Pad43)") (class "Default")
      (node (ref "U3") (pin "43") (pinfunction "PE12_43") (pintype "bidirectional"))
    )
    (net (code "637") (name "unconnected-(U3A-PE13-Pad44)") (class "Default")
      (node (ref "U3") (pin "44") (pinfunction "PE13_44") (pintype "bidirectional"))
    )
    (net (code "638") (name "unconnected-(U3A-PE14-Pad45)") (class "Default")
      (node (ref "U3") (pin "45") (pinfunction "PE14_45") (pintype "bidirectional"))
    )
    (net (code "639") (name "unconnected-(U3A-PE15-Pad46)") (class "Default")
      (node (ref "U3") (pin "46") (pinfunction "PE15_46") (pintype "bidirectional"))
    )
    (net (code "640") (name "unconnected-(U4-BOOT0-Pad138)") (class "Default")
      (node (ref "U4") (pin "138") (pinfunction "BOOT0_138") (pintype "bidirectional"))
    )
    (net (code "641") (name "unconnected-(U4-CAN1_TX{slash}I2C1_SDA{slash}SDIO_D5{slash}TIM4_CH4{slash}PB9-Pad140)") (class "Default")
      (node (ref "U4") (pin "140") (pinfunction "CAN1_TX/I2C1_SDA/SDIO_D5/TIM4_CH4/PB9_140") (pintype "bidirectional"))
    )
    (net (code "642") (name "unconnected-(U4-CAN2_RX{slash}TIM1_BKIN{slash}USART3_CK{slash}I2C2_SMBAL{slash}SPI2_NSS{slash}PB12-Pad73)") (class "Default")
      (node (ref "U4") (pin "73") (pinfunction "CAN2_RX/TIM1_BKIN/USART3_CK/I2C2_SMBAL/SPI2_NSS/PB12_73") (pintype "bidirectional"))
    )
    (net (code "643") (name "unconnected-(U4-CAN2_TX{slash}PTIM1_CH1N{slash}USART3_CTS{slash}SPI2_SCK{slash}B13-Pad74)") (class "Default")
      (node (ref "U4") (pin "74") (pinfunction "CAN2_TX/PTIM1_CH1N/USART3_CTS/SPI2_SCK/B13_74") (pintype "bidirectional"))
    )
    (net (code "644") (name "unconnected-(U4-FSMC_A12{slash}PG2-Pad87)") (class "Default")
      (node (ref "U4") (pin "87") (pinfunction "FSMC_A12/PG2_87") (pintype "bidirectional"))
    )
    (net (code "645") (name "unconnected-(U4-FSMC_A13{slash}PG3-Pad88)") (class "Default")
      (node (ref "U4") (pin "88") (pinfunction "FSMC_A13/PG3_88") (pintype "bidirectional"))
    )
    (net (code "646") (name "unconnected-(U4-FSMC_A16{slash}PD11-Pad80)") (class "Default")
      (node (ref "U4") (pin "80") (pinfunction "FSMC_A16/PD11_80") (pintype "bidirectional"))
    )
    (net (code "647") (name "unconnected-(U4-FSMC_A17{slash}PD12-Pad81)") (class "Default")
      (node (ref "U4") (pin "81") (pinfunction "FSMC_A17/PD12_81") (pintype "bidirectional"))
    )
    (net (code "648") (name "unconnected-(U4-FSMC_A18{slash}PD13-Pad82)") (class "Default")
      (node (ref "U4") (pin "82") (pinfunction "FSMC_A18/PD13_82") (pintype "bidirectional"))
    )
    (net (code "649") (name "unconnected-(U4-FSMC_BA0{slash}FSMC_A14{slash}PG4-Pad89)") (class "Default")
      (node (ref "U4") (pin "89") (pinfunction "FSMC_BA0/FSMC_A14/PG4_89") (pintype "bidirectional"))
    )
    (net (code "650") (name "unconnected-(U4-FSMC_BA1{slash}FSMC_A15{slash}PG5-Pad90)") (class "Default")
      (node (ref "U4") (pin "90") (pinfunction "FSMC_BA1/FSMC_A15/PG5_90") (pintype "bidirectional"))
    )
    (net (code "651") (name "unconnected-(U4-FSMC_D0{slash}PD14-Pad85)") (class "Default")
      (node (ref "U4") (pin "85") (pinfunction "FSMC_D0/PD14_85") (pintype "bidirectional"))
    )
    (net (code "652") (name "unconnected-(U4-FSMC_D1{slash}PD15-Pad86)") (class "Default")
      (node (ref "U4") (pin "86") (pinfunction "FSMC_D1/PD15_86") (pintype "bidirectional"))
    )
    (net (code "653") (name "unconnected-(U4-FSMC_D15{slash}PD10-Pad79)") (class "Default")
      (node (ref "U4") (pin "79") (pinfunction "FSMC_D15/PD10_79") (pintype "bidirectional"))
    )
    (net (code "654") (name "unconnected-(U4-FSMC_INT2{slash}PG6-Pad91)") (class "Default")
      (node (ref "U4") (pin "91") (pinfunction "FSMC_INT2/PG6_91") (pintype "bidirectional"))
    )
    (net (code "655") (name "unconnected-(U4-FSMC_NCE4_2{slash}PG11-Pad126)") (class "Default")
      (node (ref "U4") (pin "126") (pinfunction "FSMC_NCE4_2/PG11_126") (pintype "bidirectional"))
    )
    (net (code "656") (name "unconnected-(U4-FSMC_NOE{slash}PD4-Pad118)") (class "Default")
      (node (ref "U4") (pin "118") (pinfunction "FSMC_NOE/PD4_118") (pintype "bidirectional"))
    )
    (net (code "657") (name "unconnected-(U4-FSMC_SDCLK{slash}PG8-Pad93)") (class "Default")
      (node (ref "U4") (pin "93") (pinfunction "FSMC_SDCLK/PG8_93") (pintype "bidirectional"))
    )
    (net (code "658") (name "unconnected-(U4-FSMC_SDNE1{slash}USART1_TX{slash}CAN2_TX{slash}TIM4_CH1{slash}I2C1_SCL{slash}PB6-Pad136)") (class "Default")
      (node (ref "U4") (pin "136") (pinfunction "FSMC_SDNE1/USART1_TX/CAN2_TX/TIM4_CH1/I2C1_SCL/PB6_136") (pintype "bidirectional"))
    )
    (net (code "659") (name "unconnected-(U4-I2C3_SDA{slash}SDIO_D1{slash}TIM8_CH4{slash}PC9-Pad99)") (class "Default")
      (node (ref "U4") (pin "99") (pinfunction "I2C3_SDA/SDIO_D1/TIM8_CH4/PC9_99") (pintype "bidirectional"))
    )
    (net (code "660") (name "unconnected-(U4-I2S3_WS{slash}SPI3_NSS{slash}{slash}JTDI{slash}PA15-Pad110)") (class "Default")
      (node (ref "U4") (pin "110") (pinfunction "I2S3_WS/SPI3_NSS//JTDI/PA15_110") (pintype "bidirectional"))
    )
    (net (code "661") (name "unconnected-(U4-NRST-Pad25)") (class "Default")
      (node (ref "U4") (pin "25") (pinfunction "NRST_25") (pintype "bidirectional"))
    )
    (net (code "662") (name "unconnected-(U4-OSC_IN-Pad23)") (class "Default")
      (node (ref "U4") (pin "23") (pinfunction "OSC_IN_23") (pintype "input"))
    )
    (net (code "663") (name "unconnected-(U4-OSC_OUT-Pad24)") (class "Default")
      (node (ref "U4") (pin "24") (pinfunction "OSC_OUT_24") (pintype "output"))
    )
    (net (code "664") (name "unconnected-(U4-PA0-WKUP{slash}ADC12_IN0{slash}UART4_TX-Pad34)") (class "Default")
      (node (ref "U4") (pin "34") (pinfunction "PA0-WKUP/ADC12_IN0/UART4_TX_34") (pintype "bidirectional"))
    )
    (net (code "665") (name "unconnected-(U4-PA1{slash}USART2_RTS{slash}ADC12_IN1{slash}UART4_RX-Pad35)") (class "Default")
      (node (ref "U4") (pin "35") (pinfunction "PA1/USART2_RTS/ADC12_IN1/UART4_RX_35") (pintype "bidirectional"))
    )
    (net (code "666") (name "unconnected-(U4-PA2{slash}USART2_TX{slash}ADC12_IN2{slash}TIM2_CH3-Pad36)") (class "Default")
      (node (ref "U4") (pin "36") (pinfunction "PA2/USART2_TX/ADC12_IN2/TIM2_CH3_36") (pintype "bidirectional"))
    )
    (net (code "667") (name "unconnected-(U4-PA3{slash}USART2_RX{slash}ADC12_IN3{slash}TIM2_CH4-Pad37)") (class "Default")
      (node (ref "U4") (pin "37") (pinfunction "PA3/USART2_RX/ADC12_IN3/TIM2_CH4_37") (pintype "bidirectional"))
    )
    (net (code "668") (name "unconnected-(U4-PA4{slash}SPI1_NSS{slash}USART2_CK{slash}ADC12_IN4-Pad40)") (class "Default")
      (node (ref "U4") (pin "40") (pinfunction "PA4/SPI1_NSS/USART2_CK/ADC12_IN4_40") (pintype "bidirectional"))
    )
    (net (code "669") (name "unconnected-(U4-PA5{slash}SPI1_SCK{slash}ADC12_IN5-Pad41)") (class "Default")
      (node (ref "U4") (pin "41") (pinfunction "PA5/SPI1_SCK/ADC12_IN5_41") (pintype "bidirectional"))
    )
    (net (code "670") (name "unconnected-(U4-PA6{slash}SPI1_MISO{slash}ADC12_IN6{slash}TIM3_CH1-Pad42)") (class "Default")
      (node (ref "U4") (pin "42") (pinfunction "PA6/SPI1_MISO/ADC12_IN6/TIM3_CH1_42") (pintype "bidirectional"))
    )
    (net (code "671") (name "unconnected-(U4-PA7{slash}SPI1_MOSI{slash}ADC12_IN7{slash}TIM3_CH2-Pad43)") (class "Default")
      (node (ref "U4") (pin "43") (pinfunction "PA7/SPI1_MOSI/ADC12_IN7/TIM3_CH2_43") (pintype "bidirectional"))
    )
    (net (code "672") (name "unconnected-(U4-PB0{slash}ADC_IN8{slash}TIM3_CH3-Pad46)") (class "Default")
      (node (ref "U4") (pin "46") (pinfunction "PB0/ADC_IN8/TIM3_CH3_46") (pintype "bidirectional"))
    )
    (net (code "673") (name "unconnected-(U4-PB1{slash}ADC_IN9{slash}TIM3_CH4-Pad47)") (class "Default")
      (node (ref "U4") (pin "47") (pinfunction "PB1/ADC_IN9/TIM3_CH4_47") (pintype "bidirectional"))
    )
    (net (code "674") (name "unconnected-(U4-PB2{slash}BOOT1-Pad48)") (class "Default")
      (node (ref "U4") (pin "48") (pinfunction "PB2/BOOT1_48") (pintype "bidirectional"))
    )
    (net (code "675") (name "unconnected-(U4-PB10{slash}I2C2_SCL{slash}USART3_TX{slash}SPI2_CLK-Pad69)") (class "Default")
      (node (ref "U4") (pin "69") (pinfunction "PB10/I2C2_SCL/USART3_TX/SPI2_CLK_69") (pintype "bidirectional"))
    )
    (net (code "676") (name "unconnected-(U4-PB11{slash}I2C2_SDA{slash}USART3_RX-Pad70)") (class "Default")
      (node (ref "U4") (pin "70") (pinfunction "PB11/I2C2_SDA/USART3_RX_70") (pintype "bidirectional"))
    )
    (net (code "677") (name "unconnected-(U4-PC0{slash}ADC12_IN10{slash}FSMC_SDNWE-Pad26)") (class "Default")
      (node (ref "U4") (pin "26") (pinfunction "PC0/ADC12_IN10/FSMC_SDNWE_26") (pintype "bidirectional"))
    )
    (net (code "678") (name "unconnected-(U4-PC1{slash}ADC12_IN11-Pad27)") (class "Default")
      (node (ref "U4") (pin "27") (pinfunction "PC1/ADC12_IN11_27") (pintype "bidirectional"))
    )
    (net (code "679") (name "unconnected-(U4-PC2{slash}ADC12_IN12{slash}FSMC_SDNE0{slash}SPI2_MISO-Pad28)") (class "Default")
      (node (ref "U4") (pin "28") (pinfunction "PC2/ADC12_IN12/FSMC_SDNE0/SPI2_MISO_28") (pintype "bidirectional"))
    )
    (net (code "680") (name "unconnected-(U4-PC3{slash}ADC12_IN13{slash}FSMC_SDCKE0{slash}SPI2_MOSI-Pad29)") (class "Default")
      (node (ref "U4") (pin "29") (pinfunction "PC3/ADC12_IN13/FSMC_SDCKE0/SPI2_MOSI_29") (pintype "bidirectional"))
    )
    (net (code "681") (name "unconnected-(U4-PC4{slash}ADC12_IN14-Pad44)") (class "Default")
      (node (ref "U4") (pin "44") (pinfunction "PC4/ADC12_IN14_44") (pintype "bidirectional"))
    )
    (net (code "682") (name "unconnected-(U4-PC5{slash}ADC12_IN15-Pad45)") (class "Default")
      (node (ref "U4") (pin "45") (pinfunction "PC5/ADC12_IN15_45") (pintype "bidirectional"))
    )
    (net (code "683") (name "unconnected-(U4-PC13-TAMPER-RTC-Pad7)") (class "Default")
      (node (ref "U4") (pin "7") (pinfunction "PC13-TAMPER-RTC_7") (pintype "bidirectional"))
    )
    (net (code "684") (name "unconnected-(U4-PC14-OSC32_IN-Pad8)") (class "Default")
      (node (ref "U4") (pin "8") (pinfunction "PC14-OSC32_IN_8") (pintype "bidirectional"))
    )
    (net (code "685") (name "unconnected-(U4-PC15-OSC32_OUT-Pad9)") (class "Default")
      (node (ref "U4") (pin "9") (pinfunction "PC15-OSC32_OUT_9") (pintype "bidirectional"))
    )
    (net (code "686") (name "unconnected-(U4-PDR_ON-Pad143)") (class "Default")
      (node (ref "U4") (pin "143") (pinfunction "PDR_ON_143") (pintype "power_in"))
    )
    (net (code "687") (name "unconnected-(U4-PE2{slash}TRACECLK{slash}FSMC_A23{slash}SPI4_CLK-Pad1)") (class "Default")
      (node (ref "U4") (pin "1") (pinfunction "PE2/TRACECLK/FSMC_A23/SPI4_CLK_1") (pintype "bidirectional"))
    )
    (net (code "688") (name "unconnected-(U4-PE3{slash}TRACED0{slash}FSMC_A19-Pad2)") (class "Default")
      (node (ref "U4") (pin "2") (pinfunction "PE3/TRACED0/FSMC_A19_2") (pintype "bidirectional"))
    )
    (net (code "689") (name "unconnected-(U4-PE4{slash}TRACED1{slash}FSMC_A20-Pad3)") (class "Default")
      (node (ref "U4") (pin "3") (pinfunction "PE4/TRACED1/FSMC_A20_3") (pintype "bidirectional"))
    )
    (net (code "690") (name "unconnected-(U4-PE5{slash}TRACED2{slash}FSMC_A21{slash}SPI4_MISO-Pad4)") (class "Default")
      (node (ref "U4") (pin "4") (pinfunction "PE5/TRACED2/FSMC_A21/SPI4_MISO_4") (pintype "bidirectional"))
    )
    (net (code "691") (name "unconnected-(U4-PE6{slash}TRACED3{slash}FSMC_A22{slash}SPI4_MOSI-Pad5)") (class "Default")
      (node (ref "U4") (pin "5") (pinfunction "PE6/TRACED3/FSMC_A22/SPI4_MOSI_5") (pintype "bidirectional"))
    )
    (net (code "692") (name "unconnected-(U4-PE7{slash}FSMC_D4{slash}UART7_RX-Pad58)") (class "Default")
      (node (ref "U4") (pin "58") (pinfunction "PE7/FSMC_D4/UART7_RX_58") (pintype "bidirectional"))
    )
    (net (code "693") (name "unconnected-(U4-PE8{slash}FSMC_D5{slash}UART7_TX-Pad59)") (class "Default")
      (node (ref "U4") (pin "59") (pinfunction "PE8/FSMC_D5/UART7_TX_59") (pintype "bidirectional"))
    )
    (net (code "694") (name "unconnected-(U4-PE9{slash}FSMC_D6-Pad60)") (class "Default")
      (node (ref "U4") (pin "60") (pinfunction "PE9/FSMC_D6_60") (pintype "bidirectional"))
    )
    (net (code "695") (name "unconnected-(U4-PE10{slash}FSMC_D7-Pad63)") (class "Default")
      (node (ref "U4") (pin "63") (pinfunction "PE10/FSMC_D7_63") (pintype "bidirectional"))
    )
    (net (code "696") (name "unconnected-(U4-PE11{slash}FSMC_D8-Pad64)") (class "Default")
      (node (ref "U4") (pin "64") (pinfunction "PE11/FSMC_D8_64") (pintype "bidirectional"))
    )
    (net (code "697") (name "unconnected-(U4-PE12{slash}FSMC_D9{slash}SPI4_CLK-Pad65)") (class "Default")
      (node (ref "U4") (pin "65") (pinfunction "PE12/FSMC_D9/SPI4_CLK_65") (pintype "bidirectional"))
    )
    (net (code "698") (name "unconnected-(U4-PE13{slash}FSMC_D10{slash}SPI4_MISO-Pad66)") (class "Default")
      (node (ref "U4") (pin "66") (pinfunction "PE13/FSMC_D10/SPI4_MISO_66") (pintype "bidirectional"))
    )
    (net (code "699") (name "unconnected-(U4-PE14{slash}{slash}FSMC_D11{slash}SPI4_MOSI-Pad67)") (class "Default")
      (node (ref "U4") (pin "67") (pinfunction "PE14//FSMC_D11/SPI4_MOSI_67") (pintype "bidirectional"))
    )
    (net (code "700") (name "unconnected-(U4-PE15{slash}FSMC_D12-Pad68)") (class "Default")
      (node (ref "U4") (pin "68") (pinfunction "PE15/FSMC_D12_68") (pintype "bidirectional"))
    )
    (net (code "701") (name "unconnected-(U4-PF0{slash}FSMC_A0{slash}I2C2_SDA-Pad10)") (class "Default")
      (node (ref "U4") (pin "10") (pinfunction "PF0/FSMC_A0/I2C2_SDA_10") (pintype "bidirectional"))
    )
    (net (code "702") (name "unconnected-(U4-PF1{slash}FSMC_A1{slash}I2C2_SCL-Pad11)") (class "Default")
      (node (ref "U4") (pin "11") (pinfunction "PF1/FSMC_A1/I2C2_SCL_11") (pintype "bidirectional"))
    )
    (net (code "703") (name "unconnected-(U4-PF2{slash}FSMC_A2-Pad12)") (class "Default")
      (node (ref "U4") (pin "12") (pinfunction "PF2/FSMC_A2_12") (pintype "bidirectional"))
    )
    (net (code "704") (name "unconnected-(U4-PF3{slash}FSMC_A3-Pad13)") (class "Default")
      (node (ref "U4") (pin "13") (pinfunction "PF3/FSMC_A3_13") (pintype "bidirectional"))
    )
    (net (code "705") (name "unconnected-(U4-PF4{slash}FSMC_A4-Pad14)") (class "Default")
      (node (ref "U4") (pin "14") (pinfunction "PF4/FSMC_A4_14") (pintype "bidirectional"))
    )
    (net (code "706") (name "unconnected-(U4-PF5{slash}FSMC_A5-Pad15)") (class "Default")
      (node (ref "U4") (pin "15") (pinfunction "PF5/FSMC_A5_15") (pintype "bidirectional"))
    )
    (net (code "707") (name "unconnected-(U4-PF6{slash}ADC3_IN4{slash}FSMC_NIORD{slash}UART7_RX-Pad18)") (class "Default")
      (node (ref "U4") (pin "18") (pinfunction "PF6/ADC3_IN4/FSMC_NIORD/UART7_RX_18") (pintype "bidirectional"))
    )
    (net (code "708") (name "unconnected-(U4-PF7{slash}ADC3_IN5{slash}FSMC_NREG{slash}UART7_TX{slash}SPI5_SCK-Pad19)") (class "Default")
      (node (ref "U4") (pin "19") (pinfunction "PF7/ADC3_IN5/FSMC_NREG/UART7_TX/SPI5_SCK_19") (pintype "bidirectional"))
    )
    (net (code "709") (name "unconnected-(U4-PF8{slash}ADC3_IN6{slash}FSMC_NIOWR{slash}SPI5_MISO-Pad20)") (class "Default")
      (node (ref "U4") (pin "20") (pinfunction "PF8/ADC3_IN6/FSMC_NIOWR/SPI5_MISO_20") (pintype "bidirectional"))
    )
    (net (code "710") (name "unconnected-(U4-PF9{slash}ADC3_IN7{slash}FSMC_CD{slash}SPI5_MOSI-Pad21)") (class "Default")
      (node (ref "U4") (pin "21") (pinfunction "PF9/ADC3_IN7/FSMC_CD/SPI5_MOSI_21") (pintype "bidirectional"))
    )
    (net (code "711") (name "unconnected-(U4-PF10{slash}ADC3_IN8{slash}FSMC_INTR-Pad22)") (class "Default")
      (node (ref "U4") (pin "22") (pinfunction "PF10/ADC3_IN8/FSMC_INTR_22") (pintype "bidirectional"))
    )
    (net (code "712") (name "unconnected-(U4-PF11{slash}FSMC_SDNRAS{slash}SPI5_MOSI-Pad49)") (class "Default")
      (node (ref "U4") (pin "49") (pinfunction "PF11/FSMC_SDNRAS/SPI5_MOSI_49") (pintype "bidirectional"))
    )
    (net (code "713") (name "unconnected-(U4-PF12{slash}FSMC_A6-Pad50)") (class "Default")
      (node (ref "U4") (pin "50") (pinfunction "PF12/FSMC_A6_50") (pintype "bidirectional"))
    )
    (net (code "714") (name "unconnected-(U4-PF13{slash}FSMC_A7-Pad53)") (class "Default")
      (node (ref "U4") (pin "53") (pinfunction "PF13/FSMC_A7_53") (pintype "bidirectional"))
    )
    (net (code "715") (name "unconnected-(U4-PF14{slash}FSMC_A8-Pad54)") (class "Default")
      (node (ref "U4") (pin "54") (pinfunction "PF14/FSMC_A8_54") (pintype "bidirectional"))
    )
    (net (code "716") (name "unconnected-(U4-PF15{slash}FSMC_A9-Pad55)") (class "Default")
      (node (ref "U4") (pin "55") (pinfunction "PF15/FSMC_A9_55") (pintype "bidirectional"))
    )
    (net (code "717") (name "unconnected-(U4-PG0{slash}FSMC_A10-Pad56)") (class "Default")
      (node (ref "U4") (pin "56") (pinfunction "PG0/FSMC_A10_56") (pintype "bidirectional"))
    )
    (net (code "718") (name "unconnected-(U4-PG1{slash}FSMC_A11-Pad57)") (class "Default")
      (node (ref "U4") (pin "57") (pinfunction "PG1/FSMC_A11_57") (pintype "bidirectional"))
    )
    (net (code "719") (name "unconnected-(U4-SPI1_CLK{slash}SPI3_CLK{slash}JTDO{slash}PB3-Pad133)") (class "Default")
      (node (ref "U4") (pin "133") (pinfunction "SPI1_CLK/SPI3_CLK/JTDO/PB3_133") (pintype "bidirectional"))
    )
    (net (code "720") (name "unconnected-(U4-SPI1_MISO{slash}SPI3_MISO{slash}NJTRST{slash}PB4-Pad134)") (class "Default")
      (node (ref "U4") (pin "134") (pinfunction "SPI1_MISO/SPI3_MISO/NJTRST/PB4_134") (pintype "bidirectional"))
    )
    (net (code "721") (name "unconnected-(U4-SPI6_MISO{slash}FSMC_NE4{slash}PG12-Pad127)") (class "Default")
      (node (ref "U4") (pin "127") (pinfunction "SPI6_MISO/FSMC_NE4/PG12_127") (pintype "bidirectional"))
    )
    (net (code "722") (name "unconnected-(U4-SWDIO{slash}JTMS{slash}PA13-Pad105)") (class "Default")
      (node (ref "U4") (pin "105") (pinfunction "SWDIO/JTMS/PA13_105") (pintype "bidirectional"))
    )
    (net (code "723") (name "unconnected-(U4-TIM1_CH2N{slash}USART3_RTS{slash}SPI2_MISO{slash}PB14-Pad75)") (class "Default")
      (node (ref "U4") (pin "75") (pinfunction "TIM1_CH2N/USART3_RTS/SPI2_MISO/PB14_75") (pintype "bidirectional"))
    )
    (net (code "724") (name "unconnected-(U4-TIM1_CH2{slash}USART1_TX{slash}PA9-Pad101)") (class "Default")
      (node (ref "U4") (pin "101") (pinfunction "TIM1_CH2/USART1_TX/PA9_101") (pintype "bidirectional"))
    )
    (net (code "725") (name "unconnected-(U4-TIM1_CH3N{slash}SPI2_MOSI{slash}PB15-Pad76)") (class "Default")
      (node (ref "U4") (pin "76") (pinfunction "TIM1_CH3N/SPI2_MOSI/PB15_76") (pintype "bidirectional"))
    )
    (net (code "726") (name "unconnected-(U4-UART8_RX{slash}FSMC_NBL0{slash}TIM4_ETR{slash}PE0-Pad141)") (class "Default")
      (node (ref "U4") (pin "141") (pinfunction "UART8_RX/FSMC_NBL0/TIM4_ETR/PE0_141") (pintype "bidirectional"))
    )
    (net (code "727") (name "unconnected-(U4-USART2_RX{slash}SPI3_MOSI{slash}FSMC_NWAIT{slash}PD6-Pad122)") (class "Default")
      (node (ref "U4") (pin "122") (pinfunction "USART2_RX/SPI3_MOSI/FSMC_NWAIT/PD6_122") (pintype "bidirectional"))
    )
    (net (code "728") (name "unconnected-(U4-USART3_RX{slash}FSMC_D14{slash}PD9-Pad78)") (class "Default")
      (node (ref "U4") (pin "78") (pinfunction "USART3_RX/FSMC_D14/PD9_78") (pintype "bidirectional"))
    )
    (net (code "729") (name "unconnected-(U4-USART3_RX{slash}SDIO_D3{slash}UART4_RX{slash}PC11-Pad112)") (class "Default")
      (node (ref "U4") (pin "112") (pinfunction "USART3_RX/SDIO_D3/UART4_RX/PC11_112") (pintype "bidirectional"))
    )
    (net (code "730") (name "unconnected-(U4-USART3_TX{slash}FSMC_D13{slash}PD8-Pad77)") (class "Default")
      (node (ref "U4") (pin "77") (pinfunction "USART3_TX/FSMC_D13/PD8_77") (pintype "bidirectional"))
    )
    (net (code "731") (name "unconnected-(U4-USART6_RX{slash}FSMC_NCE3{slash}FSMC_NE2{slash}PG9-Pad124)") (class "Default")
      (node (ref "U4") (pin "124") (pinfunction "USART6_RX/FSMC_NCE3/FSMC_NE2/PG9_124") (pintype "bidirectional"))
    )
    (net (code "732") (name "unconnected-(U4-USART6_RX{slash}SDIO_D7{slash}TIM8_CH2{slash}I2S3_MCK{slash}PC7-Pad97)") (class "Default")
      (node (ref "U4") (pin "97") (pinfunction "USART6_RX/SDIO_D7/TIM8_CH2/I2S3_MCK/PC7_97") (pintype "bidirectional"))
    )
    (net (code "733") (name "unconnected-(U4-USART6_TX{slash}SPI6_MOSI{slash}FSMC_A25{slash}PG14-Pad129)") (class "Default")
      (node (ref "U4") (pin "129") (pinfunction "USART6_TX/SPI6_MOSI/FSMC_A25/PG14_129") (pintype "bidirectional"))
    )
    (net (code "734") (name "unconnected-(U4-USBDM{slash}TIM1_CH4{slash}CAN1_RX{slash}USART1_CTS{slash}PA11-Pad103)") (class "Default")
      (node (ref "U4") (pin "103") (pinfunction "USBDM/TIM1_CH4/CAN1_RX/USART1_CTS/PA11_103") (pintype "bidirectional"))
    )
    (net (code "735") (name "unconnected-(U4-VBAT-Pad6)") (class "Default")
      (node (ref "U4") (pin "6") (pinfunction "VBAT_6") (pintype "power_in"))
    )
    (net (code "736") (name "unconnected-(U4-VCAP_1-Pad71)") (class "Default")
      (node (ref "U4") (pin "71") (pinfunction "VCAP_1_71") (pintype "power_in"))
    )
    (net (code "737") (name "unconnected-(U4-VDD-Pad30)") (class "Default")
      (node (ref "U4") (pin "30") (pinfunction "VDD_30") (pintype "power_in"))
    )
    (net (code "738") (name "unconnected-(U4-VDDA-Pad33)") (class "Default")
      (node (ref "U4") (pin "33") (pinfunction "VDDA_33") (pintype "power_in"))
    )
    (net (code "739") (name "unconnected-(U4-VDD_1-Pad72)") (class "Default")
      (node (ref "U4") (pin "72") (pinfunction "VDD_1_72") (pintype "power_in"))
    )
    (net (code "740") (name "unconnected-(U4-VDD_2-Pad108)") (class "Default")
      (node (ref "U4") (pin "108") (pinfunction "VDD_2_108") (pintype "power_in"))
    )
    (net (code "741") (name "unconnected-(U4-VDD_4-Pad39)") (class "Default")
      (node (ref "U4") (pin "39") (pinfunction "VDD_4_39") (pintype "power_in"))
    )
    (net (code "742") (name "unconnected-(U4-VDD_5-Pad17)") (class "Default")
      (node (ref "U4") (pin "17") (pinfunction "VDD_5_17") (pintype "power_in"))
    )
    (net (code "743") (name "unconnected-(U4-VDD_6-Pad52)") (class "Default")
      (node (ref "U4") (pin "52") (pinfunction "VDD_6_52") (pintype "power_in"))
    )
    (net (code "744") (name "unconnected-(U4-VDD_7-Pad62)") (class "Default")
      (node (ref "U4") (pin "62") (pinfunction "VDD_7_62") (pintype "power_in"))
    )
    (net (code "745") (name "unconnected-(U4-VDD_8-Pad84)") (class "Default")
      (node (ref "U4") (pin "84") (pinfunction "VDD_8_84") (pintype "power_in"))
    )
    (net (code "746") (name "unconnected-(U4-VDD_9-Pad95)") (class "Default")
      (node (ref "U4") (pin "95") (pinfunction "VDD_9_95") (pintype "power_in"))
    )
    (net (code "747") (name "unconnected-(U4-VDD_11-Pad131)") (class "Default")
      (node (ref "U4") (pin "131") (pinfunction "VDD_11_131") (pintype "power_in"))
    )
    (net (code "748") (name "unconnected-(U4-VREF+-Pad32)") (class "Default")
      (node (ref "U4") (pin "32") (pinfunction "VREF+_32") (pintype "power_in"))
    )
    (net (code "749") (name "unconnected-(U4-VSSA-Pad31)") (class "Default")
      (node (ref "U4") (pin "31") (pinfunction "VSSA_31") (pintype "power_in"))
    )
    (net (code "750") (name "unconnected-(U4-VSS_2-Pad107)") (class "Default")
      (node (ref "U4") (pin "107") (pinfunction "VSS_2_107") (pintype "power_in"))
    )
    (net (code "751") (name "unconnected-(U4-VSS_4-Pad38)") (class "Default")
      (node (ref "U4") (pin "38") (pinfunction "VSS_4_38") (pintype "power_in"))
    )
    (net (code "752") (name "unconnected-(U4-VSS_5-Pad16)") (class "Default")
      (node (ref "U4") (pin "16") (pinfunction "VSS_5_16") (pintype "power_in"))
    )
    (net (code "753") (name "unconnected-(U4-VSS_6-Pad51)") (class "Default")
      (node (ref "U4") (pin "51") (pinfunction "VSS_6_51") (pintype "power_in"))
    )
    (net (code "754") (name "unconnected-(U4-VSS_7-Pad61)") (class "Default")
      (node (ref "U4") (pin "61") (pinfunction "VSS_7_61") (pintype "power_in"))
    )
    (net (code "755") (name "unconnected-(U4-VSS_8-Pad83)") (class "Default")
      (node (ref "U4") (pin "83") (pinfunction "VSS_8_83") (pintype "power_in"))
    )
    (net (code "756") (name "unconnected-(U4-VSS_10-Pad120)") (class "Default")
      (node (ref "U4") (pin "120") (pinfunction "VSS_10_120") (pintype "power_in"))
    )
    (net (code "757") (name "unconnected-(U5A-BOOT0-Pad138)") (class "Default")
      (node (ref "U5") (pin "138") (pinfunction "BOOT0_138") (pintype "input"))
    )
    (net (code "758") (name "unconnected-(U5A-NRST-Pad25)") (class "Default")
      (node (ref "U5") (pin "25") (pinfunction "NRST_25") (pintype "bidirectional"))
    )
    (net (code "759") (name "unconnected-(U5A-OSC_IN-Pad23)") (class "Default")
      (node (ref "U5") (pin "23") (pinfunction "OSC_IN_23") (pintype "input"))
    )
    (net (code "760") (name "unconnected-(U5A-OSC_OUT-Pad24)") (class "Default")
      (node (ref "U5") (pin "24") (pinfunction "OSC_OUT_24") (pintype "output"))
    )
    (net (code "761") (name "unconnected-(U5A-PA0-WKUP-Pad34)") (class "Default")
      (node (ref "U5") (pin "34") (pinfunction "PA0-WKUP_34") (pintype "bidirectional"))
    )
    (net (code "762") (name "unconnected-(U5A-PA1-Pad35)") (class "Default")
      (node (ref "U5") (pin "35") (pinfunction "PA1_35") (pintype "bidirectional"))
    )
    (net (code "763") (name "unconnected-(U5A-PA2-Pad36)") (class "Default")
      (node (ref "U5") (pin "36") (pinfunction "PA2_36") (pintype "bidirectional"))
    )
    (net (code "764") (name "unconnected-(U5A-PA3-Pad37)") (class "Default")
      (node (ref "U5") (pin "37") (pinfunction "PA3_37") (pintype "bidirectional"))
    )
    (net (code "765") (name "unconnected-(U5A-PA4-Pad40)") (class "Default")
      (node (ref "U5") (pin "40") (pinfunction "PA4_40") (pintype "bidirectional"))
    )
    (net (code "766") (name "unconnected-(U5A-PA5-Pad41)") (class "Default")
      (node (ref "U5") (pin "41") (pinfunction "PA5_41") (pintype "bidirectional"))
    )
    (net (code "767") (name "unconnected-(U5A-PA6-Pad42)") (class "Default")
      (node (ref "U5") (pin "42") (pinfunction "PA6_42") (pintype "bidirectional"))
    )
    (net (code "768") (name "unconnected-(U5A-PA7-Pad43)") (class "Default")
      (node (ref "U5") (pin "43") (pinfunction "PA7_43") (pintype "bidirectional"))
    )
    (net (code "769") (name "unconnected-(U5A-PA8-Pad100)") (class "Default")
      (node (ref "U5") (pin "100") (pinfunction "PA8_100") (pintype "bidirectional"))
    )
    (net (code "770") (name "unconnected-(U5A-PA9-Pad101)") (class "Default")
      (node (ref "U5") (pin "101") (pinfunction "PA9_101") (pintype "bidirectional"))
    )
    (net (code "771") (name "unconnected-(U5A-PA10-Pad102)") (class "Default")
      (node (ref "U5") (pin "102") (pinfunction "PA10_102") (pintype "bidirectional"))
    )
    (net (code "772") (name "unconnected-(U5A-PA11-Pad103)") (class "Default")
      (node (ref "U5") (pin "103") (pinfunction "PA11_103") (pintype "bidirectional"))
    )
    (net (code "773") (name "unconnected-(U5A-PA12-Pad104)") (class "Default")
      (node (ref "U5") (pin "104") (pinfunction "PA12_104") (pintype "bidirectional"))
    )
    (net (code "774") (name "unconnected-(U5A-PA13-Pad105)") (class "Default")
      (node (ref "U5") (pin "105") (pinfunction "PA13_105") (pintype "bidirectional"))
    )
    (net (code "775") (name "unconnected-(U5A-PA14-Pad109)") (class "Default")
      (node (ref "U5") (pin "109") (pinfunction "PA14_109") (pintype "bidirectional"))
    )
    (net (code "776") (name "unconnected-(U5A-PA15-Pad110)") (class "Default")
      (node (ref "U5") (pin "110") (pinfunction "PA15_110") (pintype "bidirectional"))
    )
    (net (code "777") (name "unconnected-(U5A-PB0-Pad46)") (class "Default")
      (node (ref "U5") (pin "46") (pinfunction "PB0_46") (pintype "bidirectional"))
    )
    (net (code "778") (name "unconnected-(U5A-PB1-Pad47)") (class "Default")
      (node (ref "U5") (pin "47") (pinfunction "PB1_47") (pintype "bidirectional"))
    )
    (net (code "779") (name "unconnected-(U5A-PB2-Pad48)") (class "Default")
      (node (ref "U5") (pin "48") (pinfunction "PB2_48") (pintype "bidirectional"))
    )
    (net (code "780") (name "unconnected-(U5A-PB3-Pad133)") (class "Default")
      (node (ref "U5") (pin "133") (pinfunction "PB3_133") (pintype "bidirectional"))
    )
    (net (code "781") (name "unconnected-(U5A-PB4-Pad134)") (class "Default")
      (node (ref "U5") (pin "134") (pinfunction "PB4_134") (pintype "bidirectional"))
    )
    (net (code "782") (name "unconnected-(U5A-PB5-Pad135)") (class "Default")
      (node (ref "U5") (pin "135") (pinfunction "PB5_135") (pintype "bidirectional"))
    )
    (net (code "783") (name "unconnected-(U5A-PB6-Pad136)") (class "Default")
      (node (ref "U5") (pin "136") (pinfunction "PB6_136") (pintype "bidirectional"))
    )
    (net (code "784") (name "unconnected-(U5A-PB7-Pad137)") (class "Default")
      (node (ref "U5") (pin "137") (pinfunction "PB7_137") (pintype "bidirectional"))
    )
    (net (code "785") (name "unconnected-(U5A-PB8-Pad139)") (class "Default")
      (node (ref "U5") (pin "139") (pinfunction "PB8_139") (pintype "bidirectional"))
    )
    (net (code "786") (name "unconnected-(U5A-PB9-Pad140)") (class "Default")
      (node (ref "U5") (pin "140") (pinfunction "PB9_140") (pintype "bidirectional"))
    )
    (net (code "787") (name "unconnected-(U5A-PB10-Pad69)") (class "Default")
      (node (ref "U5") (pin "69") (pinfunction "PB10_69") (pintype "bidirectional"))
    )
    (net (code "788") (name "unconnected-(U5A-PB11-Pad70)") (class "Default")
      (node (ref "U5") (pin "70") (pinfunction "PB11_70") (pintype "bidirectional"))
    )
    (net (code "789") (name "unconnected-(U5A-PB12-Pad73)") (class "Default")
      (node (ref "U5") (pin "73") (pinfunction "PB12_73") (pintype "bidirectional"))
    )
    (net (code "790") (name "unconnected-(U5A-PB13-Pad74)") (class "Default")
      (node (ref "U5") (pin "74") (pinfunction "PB13_74") (pintype "bidirectional"))
    )
    (net (code "791") (name "unconnected-(U5A-PB14-Pad75)") (class "Default")
      (node (ref "U5") (pin "75") (pinfunction "PB14_75") (pintype "bidirectional"))
    )
    (net (code "792") (name "unconnected-(U5A-PB15-Pad76)") (class "Default")
      (node (ref "U5") (pin "76") (pinfunction "PB15_76") (pintype "bidirectional"))
    )
    (net (code "793") (name "unconnected-(U5A-PC0-Pad26)") (class "Default")
      (node (ref "U5") (pin "26") (pinfunction "PC0_26") (pintype "bidirectional"))
    )
    (net (code "794") (name "unconnected-(U5A-PC1-Pad27)") (class "Default")
      (node (ref "U5") (pin "27") (pinfunction "PC1_27") (pintype "bidirectional"))
    )
    (net (code "795") (name "unconnected-(U5A-PC2-Pad28)") (class "Default")
      (node (ref "U5") (pin "28") (pinfunction "PC2_28") (pintype "bidirectional"))
    )
    (net (code "796") (name "unconnected-(U5A-PC3-Pad29)") (class "Default")
      (node (ref "U5") (pin "29") (pinfunction "PC3_29") (pintype "bidirectional"))
    )
    (net (code "797") (name "unconnected-(U5A-PC4-Pad44)") (class "Default")
      (node (ref "U5") (pin "44") (pinfunction "PC4_44") (pintype "bidirectional"))
    )
    (net (code "798") (name "unconnected-(U5A-PC5-Pad45)") (class "Default")
      (node (ref "U5") (pin "45") (pinfunction "PC5_45") (pintype "bidirectional"))
    )
    (net (code "799") (name "unconnected-(U5A-PC6-Pad96)") (class "Default")
      (node (ref "U5") (pin "96") (pinfunction "PC6_96") (pintype "bidirectional"))
    )
    (net (code "800") (name "unconnected-(U5A-PC7-Pad97)") (class "Default")
      (node (ref "U5") (pin "97") (pinfunction "PC7_97") (pintype "bidirectional"))
    )
    (net (code "801") (name "unconnected-(U5A-PC9-Pad99)") (class "Default")
      (node (ref "U5") (pin "99") (pinfunction "PC9_99") (pintype "bidirectional"))
    )
    (net (code "802") (name "unconnected-(U5A-PC10-Pad111)") (class "Default")
      (node (ref "U5") (pin "111") (pinfunction "PC10_111") (pintype "bidirectional"))
    )
    (net (code "803") (name "unconnected-(U5A-PC11-Pad112)") (class "Default")
      (node (ref "U5") (pin "112") (pinfunction "PC11_112") (pintype "bidirectional"))
    )
    (net (code "804") (name "unconnected-(U5A-PC12-Pad113)") (class "Default")
      (node (ref "U5") (pin "113") (pinfunction "PC12_113") (pintype "bidirectional"))
    )
    (net (code "805") (name "unconnected-(U5A-PC13-TAMPER-RTC-Pad7)") (class "Default")
      (node (ref "U5") (pin "7") (pinfunction "PC13-TAMPER-RTC_7") (pintype "bidirectional"))
    )
    (net (code "806") (name "unconnected-(U5A-PC14-OSC32_IN-Pad8)") (class "Default")
      (node (ref "U5") (pin "8") (pinfunction "PC14-OSC32_IN_8") (pintype "bidirectional"))
    )
    (net (code "807") (name "unconnected-(U5A-PC15-OSC32_OUT-Pad9)") (class "Default")
      (node (ref "U5") (pin "9") (pinfunction "PC15-OSC32_OUT_9") (pintype "bidirectional"))
    )
    (net (code "808") (name "unconnected-(U5A-PD0-Pad114)") (class "Default")
      (node (ref "U5") (pin "114") (pinfunction "PD0_114") (pintype "bidirectional"))
    )
    (net (code "809") (name "unconnected-(U5A-PD1-Pad115)") (class "Default")
      (node (ref "U5") (pin "115") (pinfunction "PD1_115") (pintype "bidirectional"))
    )
    (net (code "810") (name "unconnected-(U5A-PD2-Pad116)") (class "Default")
      (node (ref "U5") (pin "116") (pinfunction "PD2_116") (pintype "bidirectional"))
    )
    (net (code "811") (name "unconnected-(U5A-PD3-Pad117)") (class "Default")
      (node (ref "U5") (pin "117") (pinfunction "PD3_117") (pintype "bidirectional"))
    )
    (net (code "812") (name "unconnected-(U5A-PD4-Pad118)") (class "Default")
      (node (ref "U5") (pin "118") (pinfunction "PD4_118") (pintype "bidirectional"))
    )
    (net (code "813") (name "unconnected-(U5A-PD5-Pad119)") (class "Default")
      (node (ref "U5") (pin "119") (pinfunction "PD5_119") (pintype "bidirectional"))
    )
    (net (code "814") (name "unconnected-(U5A-PD6-Pad122)") (class "Default")
      (node (ref "U5") (pin "122") (pinfunction "PD6_122") (pintype "bidirectional"))
    )
    (net (code "815") (name "unconnected-(U5A-PD7-Pad123)") (class "Default")
      (node (ref "U5") (pin "123") (pinfunction "PD7_123") (pintype "bidirectional"))
    )
    (net (code "816") (name "unconnected-(U5A-PD9-Pad78)") (class "Default")
      (node (ref "U5") (pin "78") (pinfunction "PD9_78") (pintype "bidirectional"))
    )
    (net (code "817") (name "unconnected-(U5A-PD10-Pad79)") (class "Default")
      (node (ref "U5") (pin "79") (pinfunction "PD10_79") (pintype "bidirectional"))
    )
    (net (code "818") (name "unconnected-(U5A-PD11-Pad80)") (class "Default")
      (node (ref "U5") (pin "80") (pinfunction "PD11_80") (pintype "bidirectional"))
    )
    (net (code "819") (name "unconnected-(U5A-PD12-Pad81)") (class "Default")
      (node (ref "U5") (pin "81") (pinfunction "PD12_81") (pintype "bidirectional"))
    )
    (net (code "820") (name "unconnected-(U5A-PD13-Pad82)") (class "Default")
      (node (ref "U5") (pin "82") (pinfunction "PD13_82") (pintype "bidirectional"))
    )
    (net (code "821") (name "unconnected-(U5A-PD14-Pad85)") (class "Default")
      (node (ref "U5") (pin "85") (pinfunction "PD14_85") (pintype "bidirectional"))
    )
    (net (code "822") (name "unconnected-(U5A-PD15-Pad86)") (class "Default")
      (node (ref "U5") (pin "86") (pinfunction "PD15_86") (pintype "bidirectional"))
    )
    (net (code "823") (name "unconnected-(U5A-PE0-Pad141)") (class "Default")
      (node (ref "U5") (pin "141") (pinfunction "PE0_141") (pintype "bidirectional"))
    )
    (net (code "824") (name "unconnected-(U5A-PE1-Pad142)") (class "Default")
      (node (ref "U5") (pin "142") (pinfunction "PE1_142") (pintype "bidirectional"))
    )
    (net (code "825") (name "unconnected-(U5A-PE2-Pad1)") (class "Default")
      (node (ref "U5") (pin "1") (pinfunction "PE2_1") (pintype "bidirectional"))
    )
    (net (code "826") (name "unconnected-(U5A-PE3-Pad2)") (class "Default")
      (node (ref "U5") (pin "2") (pinfunction "PE3_2") (pintype "bidirectional"))
    )
    (net (code "827") (name "unconnected-(U5A-PE4-Pad3)") (class "Default")
      (node (ref "U5") (pin "3") (pinfunction "PE4_3") (pintype "bidirectional"))
    )
    (net (code "828") (name "unconnected-(U5A-PE5-Pad4)") (class "Default")
      (node (ref "U5") (pin "4") (pinfunction "PE5_4") (pintype "bidirectional"))
    )
    (net (code "829") (name "unconnected-(U5A-PE6-Pad5)") (class "Default")
      (node (ref "U5") (pin "5") (pinfunction "PE6_5") (pintype "bidirectional"))
    )
    (net (code "830") (name "unconnected-(U5A-PE7-Pad58)") (class "Default")
      (node (ref "U5") (pin "58") (pinfunction "PE7_58") (pintype "bidirectional"))
    )
    (net (code "831") (name "unconnected-(U5A-PE8-Pad59)") (class "Default")
      (node (ref "U5") (pin "59") (pinfunction "PE8_59") (pintype "bidirectional"))
    )
    (net (code "832") (name "unconnected-(U5A-PE9-Pad60)") (class "Default")
      (node (ref "U5") (pin "60") (pinfunction "PE9_60") (pintype "bidirectional"))
    )
    (net (code "833") (name "unconnected-(U5A-PE10-Pad63)") (class "Default")
      (node (ref "U5") (pin "63") (pinfunction "PE10_63") (pintype "bidirectional"))
    )
    (net (code "834") (name "unconnected-(U5A-PE11-Pad64)") (class "Default")
      (node (ref "U5") (pin "64") (pinfunction "PE11_64") (pintype "bidirectional"))
    )
    (net (code "835") (name "unconnected-(U5A-PE12-Pad65)") (class "Default")
      (node (ref "U5") (pin "65") (pinfunction "PE12_65") (pintype "bidirectional"))
    )
    (net (code "836") (name "unconnected-(U5A-PE13-Pad66)") (class "Default")
      (node (ref "U5") (pin "66") (pinfunction "PE13_66") (pintype "bidirectional"))
    )
    (net (code "837") (name "unconnected-(U5A-PE14-Pad67)") (class "Default")
      (node (ref "U5") (pin "67") (pinfunction "PE14_67") (pintype "bidirectional"))
    )
    (net (code "838") (name "unconnected-(U5A-PE15-Pad68)") (class "Default")
      (node (ref "U5") (pin "68") (pinfunction "PE15_68") (pintype "bidirectional"))
    )
    (net (code "839") (name "unconnected-(U5A-PF0-Pad10)") (class "Default")
      (node (ref "U5") (pin "10") (pinfunction "PF0_10") (pintype "bidirectional"))
    )
    (net (code "840") (name "unconnected-(U5A-PF1-Pad11)") (class "Default")
      (node (ref "U5") (pin "11") (pinfunction "PF1_11") (pintype "bidirectional"))
    )
    (net (code "841") (name "unconnected-(U5A-PF2-Pad12)") (class "Default")
      (node (ref "U5") (pin "12") (pinfunction "PF2_12") (pintype "bidirectional"))
    )
    (net (code "842") (name "unconnected-(U5A-PF3-Pad13)") (class "Default")
      (node (ref "U5") (pin "13") (pinfunction "PF3_13") (pintype "bidirectional"))
    )
    (net (code "843") (name "unconnected-(U5A-PF4-Pad14)") (class "Default")
      (node (ref "U5") (pin "14") (pinfunction "PF4_14") (pintype "bidirectional"))
    )
    (net (code "844") (name "unconnected-(U5A-PF5-Pad15)") (class "Default")
      (node (ref "U5") (pin "15") (pinfunction "PF5_15") (pintype "bidirectional"))
    )
    (net (code "845") (name "unconnected-(U5A-PF6-Pad18)") (class "Default")
      (node (ref "U5") (pin "18") (pinfunction "PF6_18") (pintype "bidirectional"))
    )
    (net (code "846") (name "unconnected-(U5A-PF7-Pad19)") (class "Default")
      (node (ref "U5") (pin "19") (pinfunction "PF7_19") (pintype "bidirectional"))
    )
    (net (code "847") (name "unconnected-(U5A-PF8-Pad20)") (class "Default")
      (node (ref "U5") (pin "20") (pinfunction "PF8_20") (pintype "bidirectional"))
    )
    (net (code "848") (name "unconnected-(U5A-PF9-Pad21)") (class "Default")
      (node (ref "U5") (pin "21") (pinfunction "PF9_21") (pintype "bidirectional"))
    )
    (net (code "849") (name "unconnected-(U5A-PF10-Pad22)") (class "Default")
      (node (ref "U5") (pin "22") (pinfunction "PF10_22") (pintype "bidirectional"))
    )
    (net (code "850") (name "unconnected-(U5A-PF11-Pad49)") (class "Default")
      (node (ref "U5") (pin "49") (pinfunction "PF11_49") (pintype "bidirectional"))
    )
    (net (code "851") (name "unconnected-(U5A-PF12-Pad50)") (class "Default")
      (node (ref "U5") (pin "50") (pinfunction "PF12_50") (pintype "bidirectional"))
    )
    (net (code "852") (name "unconnected-(U5A-PF13-Pad53)") (class "Default")
      (node (ref "U5") (pin "53") (pinfunction "PF13_53") (pintype "bidirectional"))
    )
    (net (code "853") (name "unconnected-(U5A-PF14-Pad54)") (class "Default")
      (node (ref "U5") (pin "54") (pinfunction "PF14_54") (pintype "bidirectional"))
    )
    (net (code "854") (name "unconnected-(U5A-PF15-Pad55)") (class "Default")
      (node (ref "U5") (pin "55") (pinfunction "PF15_55") (pintype "bidirectional"))
    )
    (net (code "855") (name "unconnected-(U5A-PG0-Pad56)") (class "Default")
      (node (ref "U5") (pin "56") (pinfunction "PG0_56") (pintype "bidirectional"))
    )
    (net (code "856") (name "unconnected-(U5A-PG1-Pad57)") (class "Default")
      (node (ref "U5") (pin "57") (pinfunction "PG1_57") (pintype "bidirectional"))
    )
    (net (code "857") (name "unconnected-(U5A-PG2-Pad87)") (class "Default")
      (node (ref "U5") (pin "87") (pinfunction "PG2_87") (pintype "bidirectional"))
    )
    (net (code "858") (name "unconnected-(U5A-PG3-Pad88)") (class "Default")
      (node (ref "U5") (pin "88") (pinfunction "PG3_88") (pintype "bidirectional"))
    )
    (net (code "859") (name "unconnected-(U5A-PG4-Pad89)") (class "Default")
      (node (ref "U5") (pin "89") (pinfunction "PG4_89") (pintype "bidirectional"))
    )
    (net (code "860") (name "unconnected-(U5A-PG5-Pad90)") (class "Default")
      (node (ref "U5") (pin "90") (pinfunction "PG5_90") (pintype "bidirectional"))
    )
    (net (code "861") (name "unconnected-(U5A-PG6-Pad91)") (class "Default")
      (node (ref "U5") (pin "91") (pinfunction "PG6_91") (pintype "bidirectional"))
    )
    (net (code "862") (name "unconnected-(U5A-PG7-Pad92)") (class "Default")
      (node (ref "U5") (pin "92") (pinfunction "PG7_92") (pintype "bidirectional"))
    )
    (net (code "863") (name "unconnected-(U5A-PG8-Pad93)") (class "Default")
      (node (ref "U5") (pin "93") (pinfunction "PG8_93") (pintype "bidirectional"))
    )
    (net (code "864") (name "unconnected-(U5A-PG9-Pad124)") (class "Default")
      (node (ref "U5") (pin "124") (pinfunction "PG9_124") (pintype "bidirectional"))
    )
    (net (code "865") (name "unconnected-(U5A-PG10-Pad125)") (class "Default")
      (node (ref "U5") (pin "125") (pinfunction "PG10_125") (pintype "bidirectional"))
    )
    (net (code "866") (name "unconnected-(U5A-PG11-Pad126)") (class "Default")
      (node (ref "U5") (pin "126") (pinfunction "PG11_126") (pintype "bidirectional"))
    )
    (net (code "867") (name "unconnected-(U5A-PG12-Pad127)") (class "Default")
      (node (ref "U5") (pin "127") (pinfunction "PG12_127") (pintype "bidirectional"))
    )
    (net (code "868") (name "unconnected-(U5A-PG13-Pad128)") (class "Default")
      (node (ref "U5") (pin "128") (pinfunction "PG13_128") (pintype "bidirectional"))
    )
    (net (code "869") (name "unconnected-(U5A-PG14-Pad129)") (class "Default")
      (node (ref "U5") (pin "129") (pinfunction "PG14_129") (pintype "bidirectional"))
    )
    (net (code "870") (name "unconnected-(U5A-PG15-Pad132)") (class "Default")
      (node (ref "U5") (pin "132") (pinfunction "PG15_132") (pintype "bidirectional"))
    )
    (net (code "871") (name "unconnected-(U6A-BOOT0-Pad94)") (class "Default")
      (node (ref "U6") (pin "94") (pinfunction "BOOT0_94") (pintype "input"))
    )
    (net (code "872") (name "unconnected-(U6A-NRST-Pad14)") (class "Default")
      (node (ref "U6") (pin "14") (pinfunction "NRST_14") (pintype "bidirectional"))
    )
    (net (code "873") (name "unconnected-(U6A-OSC_IN-Pad12)") (class "Default")
      (node (ref "U6") (pin "12") (pinfunction "OSC_IN_12") (pintype "input"))
    )
    (net (code "874") (name "unconnected-(U6A-OSC_OUT-Pad13)") (class "Default")
      (node (ref "U6") (pin "13") (pinfunction "OSC_OUT_13") (pintype "output"))
    )
    (net (code "875") (name "unconnected-(U6A-PB0-Pad35)") (class "Default")
      (node (ref "U6") (pin "35") (pinfunction "PB0_35") (pintype "bidirectional"))
    )
    (net (code "876") (name "unconnected-(U6A-PB1-Pad36)") (class "Default")
      (node (ref "U6") (pin "36") (pinfunction "PB1_36") (pintype "bidirectional"))
    )
    (net (code "877") (name "unconnected-(U6A-PB2-Pad37)") (class "Default")
      (node (ref "U6") (pin "37") (pinfunction "PB2_37") (pintype "bidirectional"))
    )
    (net (code "878") (name "unconnected-(U6A-PB3-Pad89)") (class "Default")
      (node (ref "U6") (pin "89") (pinfunction "PB3_89") (pintype "bidirectional"))
    )
    (net (code "879") (name "unconnected-(U6A-PB4-Pad90)") (class "Default")
      (node (ref "U6") (pin "90") (pinfunction "PB4_90") (pintype "bidirectional"))
    )
    (net (code "880") (name "unconnected-(U6A-PB5-Pad91)") (class "Default")
      (node (ref "U6") (pin "91") (pinfunction "PB5_91") (pintype "bidirectional"))
    )
    (net (code "881") (name "unconnected-(U6A-PB6-Pad92)") (class "Default")
      (node (ref "U6") (pin "92") (pinfunction "PB6_92") (pintype "bidirectional"))
    )
    (net (code "882") (name "unconnected-(U6A-PB7-Pad93)") (class "Default")
      (node (ref "U6") (pin "93") (pinfunction "PB7_93") (pintype "bidirectional"))
    )
    (net (code "883") (name "unconnected-(U6A-PB8-Pad95)") (class "Default")
      (node (ref "U6") (pin "95") (pinfunction "PB8_95") (pintype "bidirectional"))
    )
    (net (code "884") (name "unconnected-(U6A-PB9-Pad96)") (class "Default")
      (node (ref "U6") (pin "96") (pinfunction "PB9_96") (pintype "bidirectional"))
    )
    (net (code "885") (name "unconnected-(U6A-PB10-Pad47)") (class "Default")
      (node (ref "U6") (pin "47") (pinfunction "PB10_47") (pintype "bidirectional"))
    )
    (net (code "886") (name "unconnected-(U6A-PB11-Pad48)") (class "Default")
      (node (ref "U6") (pin "48") (pinfunction "PB11_48") (pintype "bidirectional"))
    )
    (net (code "887") (name "unconnected-(U6A-PB12-Pad51)") (class "Default")
      (node (ref "U6") (pin "51") (pinfunction "PB12_51") (pintype "bidirectional"))
    )
    (net (code "888") (name "unconnected-(U6A-PB13-Pad52)") (class "Default")
      (node (ref "U6") (pin "52") (pinfunction "PB13_52") (pintype "bidirectional"))
    )
    (net (code "889") (name "unconnected-(U6A-PB14-Pad53)") (class "Default")
      (node (ref "U6") (pin "53") (pinfunction "PB14_53") (pintype "bidirectional"))
    )
    (net (code "890") (name "unconnected-(U6A-PB15-Pad54)") (class "Default")
      (node (ref "U6") (pin "54") (pinfunction "PB15_54") (pintype "bidirectional"))
    )
    (net (code "891") (name "unconnected-(U6A-PD0-Pad81)") (class "Default")
      (node (ref "U6") (pin "81") (pinfunction "PD0_81") (pintype "bidirectional"))
    )
    (net (code "892") (name "unconnected-(U6A-PD1-Pad82)") (class "Default")
      (node (ref "U6") (pin "82") (pinfunction "PD1_82") (pintype "bidirectional"))
    )
    (net (code "893") (name "unconnected-(U6A-PD2-Pad83)") (class "Default")
      (node (ref "U6") (pin "83") (pinfunction "PD2_83") (pintype "bidirectional"))
    )
    (net (code "894") (name "unconnected-(U6A-PD3-Pad84)") (class "Default")
      (node (ref "U6") (pin "84") (pinfunction "PD3_84") (pintype "bidirectional"))
    )
    (net (code "895") (name "unconnected-(U6A-PD4-Pad85)") (class "Default")
      (node (ref "U6") (pin "85") (pinfunction "PD4_85") (pintype "bidirectional"))
    )
    (net (code "896") (name "unconnected-(U6A-PD5-Pad86)") (class "Default")
      (node (ref "U6") (pin "86") (pinfunction "PD5_86") (pintype "bidirectional"))
    )
    (net (code "897") (name "unconnected-(U6A-PD6-Pad87)") (class "Default")
      (node (ref "U6") (pin "87") (pinfunction "PD6_87") (pintype "bidirectional"))
    )
    (net (code "898") (name "unconnected-(U6A-PD7-Pad88)") (class "Default")
      (node (ref "U6") (pin "88") (pinfunction "PD7_88") (pintype "bidirectional"))
    )
    (net (code "899") (name "unconnected-(U6A-PD9-Pad56)") (class "Default")
      (node (ref "U6") (pin "56") (pinfunction "PD9_56") (pintype "bidirectional"))
    )
    (net (code "900") (name "unconnected-(U6A-PD10-Pad57)") (class "Default")
      (node (ref "U6") (pin "57") (pinfunction "PD10_57") (pintype "bidirectional"))
    )
    (net (code "901") (name "unconnected-(U6A-PD11-Pad58)") (class "Default")
      (node (ref "U6") (pin "58") (pinfunction "PD11_58") (pintype "bidirectional"))
    )
    (net (code "902") (name "unconnected-(U6A-PD12-Pad59)") (class "Default")
      (node (ref "U6") (pin "59") (pinfunction "PD12_59") (pintype "bidirectional"))
    )
    (net (code "903") (name "unconnected-(U6A-PD13-Pad60)") (class "Default")
      (node (ref "U6") (pin "60") (pinfunction "PD13_60") (pintype "bidirectional"))
    )
    (net (code "904") (name "unconnected-(U6A-PD14-Pad61)") (class "Default")
      (node (ref "U6") (pin "61") (pinfunction "PD14_61") (pintype "bidirectional"))
    )
    (net (code "905") (name "unconnected-(U6A-PD15-Pad62)") (class "Default")
      (node (ref "U6") (pin "62") (pinfunction "PD15_62") (pintype "bidirectional"))
    )
    (net (code "906") (name "unconnected-(U6A-PE0-Pad97)") (class "Default")
      (node (ref "U6") (pin "97") (pinfunction "PE0_97") (pintype "bidirectional"))
    )
    (net (code "907") (name "unconnected-(U6A-PE1-Pad98)") (class "Default")
      (node (ref "U6") (pin "98") (pinfunction "PE1_98") (pintype "bidirectional"))
    )
    (net (code "908") (name "unconnected-(U6A-PE2-Pad1)") (class "Default")
      (node (ref "U6") (pin "1") (pinfunction "PE2_1") (pintype "bidirectional"))
    )
    (net (code "909") (name "unconnected-(U6A-PE3-Pad2)") (class "Default")
      (node (ref "U6") (pin "2") (pinfunction "PE3_2") (pintype "bidirectional"))
    )
    (net (code "910") (name "unconnected-(U6A-PE4-Pad3)") (class "Default")
      (node (ref "U6") (pin "3") (pinfunction "PE4_3") (pintype "bidirectional"))
    )
    (net (code "911") (name "unconnected-(U6A-PE5-Pad4)") (class "Default")
      (node (ref "U6") (pin "4") (pinfunction "PE5_4") (pintype "bidirectional"))
    )
    (net (code "912") (name "unconnected-(U6A-PE6-Pad5)") (class "Default")
      (node (ref "U6") (pin "5") (pinfunction "PE6_5") (pintype "bidirectional"))
    )
    (net (code "913") (name "unconnected-(U6A-PE7-Pad38)") (class "Default")
      (node (ref "U6") (pin "38") (pinfunction "PE7_38") (pintype "bidirectional"))
    )
    (net (code "914") (name "unconnected-(U6A-PE10-Pad41)") (class "Default")
      (node (ref "U6") (pin "41") (pinfunction "PE10_41") (pintype "bidirectional"))
    )
    (net (code "915") (name "unconnected-(U6A-PE12-Pad43)") (class "Default")
      (node (ref "U6") (pin "43") (pinfunction "PE12_43") (pintype "bidirectional"))
    )
    (net (code "916") (name "unconnected-(U6A-PE14-Pad45)") (class "Default")
      (node (ref "U6") (pin "45") (pinfunction "PE14_45") (pintype "bidirectional"))
    )
    (net (code "917") (name "unconnected-(U6A-PE15-Pad46)") (class "Default")
      (node (ref "U6") (pin "46") (pinfunction "PE15_46") (pintype "bidirectional"))
    )
    (net (code "918") (name "unconnected-(U7-CLK_CCO(HS){slash}PE0-Pad40)") (class "Default")
      (node (ref "U7") (pin "40") (pinfunction "CLK_CCO(HS)/PE0_40") (pintype "bidirectional"))
    )
    (net (code "919") (name "unconnected-(U7-I2C_SCL{slash}(T)PE1-Pad39)") (class "Default")
      (node (ref "U7") (pin "39") (pinfunction "I2C_SCL/(T)PE1_39") (pintype "bidirectional"))
    )
    (net (code "920") (name "unconnected-(U7-I2C_SDA(T)PE2-Pad38)") (class "Default")
      (node (ref "U7") (pin "38") (pinfunction "I2C_SDA(T)PE2_38") (pintype "bidirectional"))
    )
    (net (code "921") (name "unconnected-(U7-PC4(HS){slash}TIM1_CH4-Pad29)") (class "Default")
      (node (ref "U7") (pin "29") (pinfunction "PC4(HS)/TIM1_CH4_29") (pintype "bidirectional"))
    )
    (net (code "922") (name "unconnected-(U7-PE6{slash}AIN9-Pad24)") (class "Default")
      (node (ref "U7") (pin "24") (pinfunction "PE6/AIN9_24") (pintype "bidirectional"))
    )
    (net (code "923") (name "unconnected-(U7-PE7{slash}AIN8-Pad23)") (class "Default")
      (node (ref "U7") (pin "23") (pinfunction "PE7/AIN8_23") (pintype "bidirectional"))
    )
    (net (code "924") (name "unconnected-(U7-PG0-Pad36)") (class "Default")
      (node (ref "U7") (pin "36") (pinfunction "PG0_36") (pintype "bidirectional"))
    )
    (net (code "925") (name "unconnected-(U7-PG1-Pad35)") (class "Default")
      (node (ref "U7") (pin "35") (pinfunction "PG1_35") (pintype "bidirectional"))
    )
    (net (code "926") (name "unconnected-(U7-SPI_MISO{slash}(HS)PC7-Pad34)") (class "Default")
      (node (ref "U7") (pin "34") (pinfunction "SPI_MISO/(HS)PC7_34") (pintype "bidirectional"))
    )
    (net (code "927") (name "unconnected-(U7-SPI_MOSI{slash}(HS)PC6-Pad33)") (class "Default")
      (node (ref "U7") (pin "33") (pinfunction "SPI_MOSI/(HS)PC6_33") (pintype "bidirectional"))
    )
    (net (code "928") (name "unconnected-(U7-SPI_NSS{slash}(HS)PE5-Pad25)") (class "Default")
      (node (ref "U7") (pin "25") (pinfunction "SPI_NSS/(HS)PE5_25") (pintype "bidirectional"))
    )
    (net (code "929") (name "unconnected-(U7-SPI_SCK{slash}(HS)PC5-Pad30)") (class "Default")
      (node (ref "U7") (pin "30") (pinfunction "SPI_SCK/(HS)PC5_30") (pintype "bidirectional"))
    )
    (net (code "930") (name "unconnected-(U7-SWIM{slash}(HS)PD1-Pad42)") (class "Default")
      (node (ref "U7") (pin "42") (pinfunction "SWIM/(HS)PD1_42") (pintype "bidirectional"))
    )
    (net (code "931") (name "unconnected-(U7-TIM1_BKIN{slash}PE3-Pad37)") (class "Default")
      (node (ref "U7") (pin "37") (pinfunction "TIM1_BKIN/PE3_37") (pintype "bidirectional"))
    )
    (net (code "932") (name "unconnected-(U7-TIM1_CH2{slash}(HS)PC2-Pad27)") (class "Default")
      (node (ref "U7") (pin "27") (pinfunction "TIM1_CH2/(HS)PC2_27") (pintype "bidirectional"))
    )
    (net (code "933") (name "unconnected-(U7-TIM1_CH3{slash}(HS)PC3-Pad28)") (class "Default")
      (node (ref "U7") (pin "28") (pinfunction "TIM1_CH3/(HS)PC3_28") (pintype "bidirectional"))
    )
    (net (code "934") (name "unconnected-(U7-TIM1_CH4]{slash}TL1[{slash}(HS)PD7-Pad48)") (class "Default")
      (node (ref "U7") (pin "48") (pinfunction "TIM1_CH4]/TL1[/(HS)PD7_48") (pintype "bidirectional"))
    )
    (net (code "935") (name "unconnected-(U7-UART2_CK{slash}TIM1_CH1{slash}(HS)PC1-Pad26)") (class "Default")
      (node (ref "U7") (pin "26") (pinfunction "UART2_CK/TIM1_CH1/(HS)PC1_26") (pintype "bidirectional"))
    )
    (net (code "936") (name "unconnected-(U7-UART2_TX{slash}(HS)_PD5-Pad46)") (class "Default")
      (node (ref "U7") (pin "46") (pinfunction "UART2_TX/(HS)_PD5_46") (pintype "bidirectional"))
    )
    (net (code "937") (name "unconnected-(U7-[ADC_ETR]TIM2_CH2{slash}(HS)PD3-Pad44)") (class "Default")
      (node (ref "U7") (pin "44") (pinfunction "[ADC_ETR]TIM2_CH2/(HS)PD3_44") (pintype "bidirectional"))
    )
    (net (code "938") (name "unconnected-(U7-[BEEP]TIM2_CH1{slash}(HS)PD4-Pad45)") (class "Default")
      (node (ref "U7") (pin "45") (pinfunction "[BEEP]TIM2_CH1/(HS)PD4_45") (pintype "bidirectional"))
    )
    (net (code "939") (name "unconnected-(U7-[CLK_CCO][TIM1_BKIN]TIM3_CH2{slash}(HS)PD0-Pad41)") (class "Default")
      (node (ref "U7") (pin "41") (pinfunction "[CLK_CCO][TIM1_BKIN]TIM3_CH2/(HS)PD0_41") (pintype "bidirectional"))
    )
    (net (code "940") (name "unconnected-(U7-[TIM2_CH3]TIM3_CH1{slash}(HS)PD2-Pad43)") (class "Default")
      (node (ref "U7") (pin "43") (pinfunction "[TIM2_CH3]TIM3_CH1/(HS)PD2_43") (pintype "bidirectional"))
    )
    (net (code "941") (name "unconnected-(U8-GND-Pad16)") (class "Default")
      (node (ref "U8") (pin "16") (pinfunction "GND_16") (pintype "passive"))
    )
    (net (code "942") (name "unconnected-(U8-P0.0{slash}AD0-Pad40)") (class "Default")
      (node (ref "U8") (pin "40") (pinfunction "P0.0/AD0_40") (pintype "passive"))
    )
    (net (code "943") (name "unconnected-(U8-P0.1{slash}AD1-Pad41)") (class "Default")
      (node (ref "U8") (pin "41") (pinfunction "P0.1/AD1_41") (pintype "passive"))
    )
    (net (code "944") (name "unconnected-(U8-P0.2{slash}AD2-Pad42)") (class "Default")
      (node (ref "U8") (pin "42") (pinfunction "P0.2/AD2_42") (pintype "passive"))
    )
    (net (code "945") (name "unconnected-(U8-P0.3{slash}AD3-Pad43)") (class "Default")
      (node (ref "U8") (pin "43") (pinfunction "P0.3/AD3_43") (pintype "passive"))
    )
    (net (code "946") (name "unconnected-(U8-P0.4{slash}AD4-Pad44)") (class "Default")
      (node (ref "U8") (pin "44") (pinfunction "P0.4/AD4_44") (pintype "passive"))
    )
    (net (code "947") (name "unconnected-(U8-P0.5{slash}AD5-Pad1)") (class "Default")
      (node (ref "U8") (pin "1") (pinfunction "P0.5/AD5_1") (pintype "passive"))
    )
    (net (code "948") (name "unconnected-(U8-P0.6{slash}AD6-Pad2)") (class "Default")
      (node (ref "U8") (pin "2") (pinfunction "P0.6/AD6_2") (pintype "passive"))
    )
    (net (code "949") (name "unconnected-(U8-P0.7{slash}AD7-Pad3)") (class "Default")
      (node (ref "U8") (pin "3") (pinfunction "P0.7/AD7_3") (pintype "passive"))
    )
    (net (code "950") (name "unconnected-(U8-P1.0{slash}ADC0{slash}CCP1{slash}RXD2-Pad4)") (class "Default")
      (node (ref "U8") (pin "4") (pinfunction "P1.0/ADC0/CCP1/RXD2_4") (pintype "passive"))
    )
    (net (code "951") (name "unconnected-(U8-P1.1{slash}ADC1{slash}CCP0{slash}TXD2-Pad5)") (class "Default")
      (node (ref "U8") (pin "5") (pinfunction "P1.1/ADC1/CCP0/TXD2_5") (pintype "passive"))
    )
    (net (code "952") (name "unconnected-(U8-P1.2{slash}ADC2{slash}SS{slash}ECI-Pad7)") (class "Default")
      (node (ref "U8") (pin "7") (pinfunction "P1.2/ADC2/SS/ECI_7") (pintype "passive"))
    )
    (net (code "953") (name "unconnected-(U8-P1.3{slash}ADC3{slash}MOSI-Pad8)") (class "Default")
      (node (ref "U8") (pin "8") (pinfunction "P1.3/ADC3/MOSI_8") (pintype "passive"))
    )
    (net (code "954") (name "unconnected-(U8-P1.4{slash}ADC4{slash}MISO-Pad9)") (class "Default")
      (node (ref "U8") (pin "9") (pinfunction "P1.4/ADC4/MISO_9") (pintype "passive"))
    )
    (net (code "955") (name "unconnected-(U8-P1.5{slash}ADC5{slash}SCLK-Pad10)") (class "Default")
      (node (ref "U8") (pin "10") (pinfunction "P1.5/ADC5/SCLK_10") (pintype "passive"))
    )
    (net (code "956") (name "unconnected-(U8-P1.6{slash}ADC6{slash}RXD_3{slash}XTAL2-Pad11)") (class "Default")
      (node (ref "U8") (pin "11") (pinfunction "P1.6/ADC6/RXD_3/XTAL2_11") (pintype "passive"))
    )
    (net (code "957") (name "unconnected-(U8-P1.7{slash}ADC7{slash}TXD_3{slash}XTAL1-Pad12)") (class "Default")
      (node (ref "U8") (pin "12") (pinfunction "P1.7/ADC7/TXD_3/XTAL1_12") (pintype "passive"))
    )
    (net (code "958") (name "unconnected-(U8-P2.0{slash}A8{slash}RSTOUT_LOW-Pad30)") (class "Default")
      (node (ref "U8") (pin "30") (pinfunction "P2.0/A8/RSTOUT_LOW_30") (pintype "passive"))
    )
    (net (code "959") (name "unconnected-(U8-P2.1{slash}A9{slash}SCLK_2-Pad31)") (class "Default")
      (node (ref "U8") (pin "31") (pinfunction "P2.1/A9/SCLK_2_31") (pintype "passive"))
    )
    (net (code "960") (name "unconnected-(U8-P2.2{slash}A10{slash}MISO_2-Pad32)") (class "Default")
      (node (ref "U8") (pin "32") (pinfunction "P2.2/A10/MISO_2_32") (pintype "passive"))
    )
    (net (code "961") (name "unconnected-(U8-P2.3{slash}A11{slash}MOSI_2-Pad33)") (class "Default")
      (node (ref "U8") (pin "33") (pinfunction "P2.3/A11/MOSI_2_33") (pintype "passive"))
    )
    (net (code "962") (name "unconnected-(U8-P2.4{slash}A12{slash}ECI_3{slash}SS_2-Pad34)") (class "Default")
      (node (ref "U8") (pin "34") (pinfunction "P2.4/A12/ECI_3/SS_2_34") (pintype "passive"))
    )
    (net (code "963") (name "unconnected-(U8-P2.5{slash}A13{slash}CCP0_3-Pad35)") (class "Default")
      (node (ref "U8") (pin "35") (pinfunction "P2.5/A13/CCP0_3_35") (pintype "passive"))
    )
    (net (code "964") (name "unconnected-(U8-P2.6{slash}A14{slash}CCP1_3-Pad36)") (class "Default")
      (node (ref "U8") (pin "36") (pinfunction "P2.6/A14/CCP1_3_36") (pintype "passive"))
    )
    (net (code "965") (name "unconnected-(U8-P2.7{slash}A15{slash}CCP2_3-Pad37)") (class "Default")
      (node (ref "U8") (pin "37") (pinfunction "P2.7/A15/CCP2_3_37") (pintype "passive"))
    )
    (net (code "966") (name "unconnected-(U8-P3.0{slash}RXD{slash}~{INT4}{slash}T2CLKO-Pad18)") (class "Default")
      (node (ref "U8") (pin "18") (pinfunction "P3.0/RXD/~{INT4}/T2CLKO_18") (pintype "passive"))
    )
    (net (code "967") (name "unconnected-(U8-P3.1{slash}TXD{slash}T2-Pad19)") (class "Default")
      (node (ref "U8") (pin "19") (pinfunction "P3.1/TXD/T2_19") (pintype "passive"))
    )
    (net (code "968") (name "unconnected-(U8-P3.2{slash}INT0-Pad20)") (class "Default")
      (node (ref "U8") (pin "20") (pinfunction "P3.2/INT0_20") (pintype "passive"))
    )
    (net (code "969") (name "unconnected-(U8-P3.3{slash}INT1-Pad21)") (class "Default")
      (node (ref "U8") (pin "21") (pinfunction "P3.3/INT1_21") (pintype "passive"))
    )
    (net (code "970") (name "unconnected-(U8-P3.4{slash}T0{slash}T1CLKO{slash}ECI_2-Pad22)") (class "Default")
      (node (ref "U8") (pin "22") (pinfunction "P3.4/T0/T1CLKO/ECI_2_22") (pintype "passive"))
    )
    (net (code "971") (name "unconnected-(U8-P3.5{slash}T1{slash}T0CLKO{slash}CCP0_2-Pad23)") (class "Default")
      (node (ref "U8") (pin "23") (pinfunction "P3.5/T1/T0CLKO/CCP0_2_23") (pintype "passive"))
    )
    (net (code "972") (name "unconnected-(U8-P3.6{slash}~{INT2}{slash}RXD_2{slash}CCP1_2-Pad24)") (class "Default")
      (node (ref "U8") (pin "24") (pinfunction "P3.6/~{INT2}/RXD_2/CCP1_2_24") (pintype "passive"))
    )
    (net (code "973") (name "unconnected-(U8-P3.7{slash}~{INT3}{slash}TXD_2{slash}CCP2{slash}CCP2_2-Pad25)") (class "Default")
      (node (ref "U8") (pin "25") (pinfunction "P3.7/~{INT3}/TXD_2/CCP2/CCP2_2_25") (pintype "passive"))
    )
    (net (code "974") (name "unconnected-(U8-P4.0{slash}MOSI_3-Pad17)") (class "Default")
      (node (ref "U8") (pin "17") (pinfunction "P4.0/MOSI_3_17") (pintype "passive"))
    )
    (net (code "975") (name "unconnected-(U8-P4.1{slash}MISO_3-Pad26)") (class "Default")
      (node (ref "U8") (pin "26") (pinfunction "P4.1/MISO_3_26") (pintype "passive"))
    )
    (net (code "976") (name "unconnected-(U8-P4.2{slash}~{WR}-Pad27)") (class "Default")
      (node (ref "U8") (pin "27") (pinfunction "P4.2/~{WR}_27") (pintype "passive"))
    )
    (net (code "977") (name "unconnected-(U8-P4.3{slash}SCLK_3-Pad28)") (class "Default")
      (node (ref "U8") (pin "28") (pinfunction "P4.3/SCLK_3_28") (pintype "passive"))
    )
    (net (code "978") (name "unconnected-(U8-P4.4{slash}~{RD}-Pad29)") (class "Default")
      (node (ref "U8") (pin "29") (pinfunction "P4.4/~{RD}_29") (pintype "passive"))
    )
    (net (code "979") (name "unconnected-(U8-P4.5{slash}ALE-Pad38)") (class "Default")
      (node (ref "U8") (pin "38") (pinfunction "P4.5/ALE_38") (pintype "passive"))
    )
    (net (code "980") (name "unconnected-(U8-P4.6{slash}RXD2_2-Pad39)") (class "Default")
      (node (ref "U8") (pin "39") (pinfunction "P4.6/RXD2_2_39") (pintype "passive"))
    )
    (net (code "981") (name "unconnected-(U8-P4.7{slash}TXD2_2-Pad6)") (class "Default")
      (node (ref "U8") (pin "6") (pinfunction "P4.7/TXD2_2_6") (pintype "passive"))
    )
    (net (code "982") (name "unconnected-(U8-P5.4{slash}RST{slash}MCLKO{slash}SS_3-Pad13)") (class "Default")
      (node (ref "U8") (pin "13") (pinfunction "P5.4/RST/MCLKO/SS_3_13") (pintype "passive"))
    )
    (net (code "983") (name "unconnected-(U8-P5.5-Pad15)") (class "Default")
      (node (ref "U8") (pin "15") (pinfunction "P5.5_15") (pintype "passive"))
    )
    (net (code "984") (name "unconnected-(U8-VCC-Pad14)") (class "Default")
      (node (ref "U8") (pin "14") (pinfunction "VCC_14") (pintype "passive"))
    )
    (net (code "985") (name "unconnected-(U9-AIN6{slash}PB6-Pad24)") (class "Default")
      (node (ref "U9") (pin "24") (pinfunction "AIN6/PB6_24") (pintype "bidirectional"))
    )
    (net (code "986") (name "unconnected-(U9-AIN7{slash}PB7-Pad23)") (class "Default")
      (node (ref "U9") (pin "23") (pinfunction "AIN7/PB7_23") (pintype "bidirectional"))
    )
    (net (code "987") (name "unconnected-(U9-AIN8{slash}PE7-Pad31)") (class "Default")
      (node (ref "U9") (pin "31") (pinfunction "AIN8/PE7_31") (pintype "bidirectional"))
    )
    (net (code "988") (name "unconnected-(U9-AIN9{slash}PE6-Pad32)") (class "Default")
      (node (ref "U9") (pin "32") (pinfunction "AIN9/PE6_32") (pintype "bidirectional"))
    )
    (net (code "989") (name "unconnected-(U9-AIN10{slash}PF0-Pad22)") (class "Default")
      (node (ref "U9") (pin "22") (pinfunction "AIN10/\r\nPF0_22") (pintype "bidirectional"))
    )
    (net (code "990") (name "unconnected-(U9-AIN11{slash}PF3-Pad17)") (class "Default")
      (node (ref "U9") (pin "17") (pinfunction "AIN11/PF3_17") (pintype "bidirectional"))
    )
    (net (code "991") (name "unconnected-(U9-AIN12{slash}PF4-Pad16)") (class "Default")
      (node (ref "U9") (pin "16") (pinfunction "AIN12/PF4_16") (pintype "bidirectional"))
    )
    (net (code "992") (name "unconnected-(U9-AIN13{slash}PF5-Pad15)") (class "Default")
      (node (ref "U9") (pin "15") (pinfunction "AIN13/PF5_15") (pintype "bidirectional"))
    )
    (net (code "993") (name "unconnected-(U9-AIN14{slash}PF6-Pad14)") (class "Default")
      (node (ref "U9") (pin "14") (pinfunction "AIN14/PF6_14") (pintype "bidirectional"))
    )
    (net (code "994") (name "unconnected-(U9-AIN15{slash}PF7-Pad13)") (class "Default")
      (node (ref "U9") (pin "13") (pinfunction "AIN15/PF7_13") (pintype "bidirectional"))
    )
    (net (code "995") (name "unconnected-(U9-NRST-Pad1)") (class "Default")
      (node (ref "U9") (pin "1") (pinfunction "NRST_1") (pintype "bidirectional"))
    )
    (net (code "996") (name "unconnected-(U9-PA1{slash}OSCI(LS)-Pad2)") (class "Default")
      (node (ref "U9") (pin "2") (pinfunction "PA1/OSCI(LS)_2") (pintype "bidirectional"))
    )
    (net (code "997") (name "unconnected-(U9-PA2{slash}OSCOUT(LS)-Pad3)") (class "Default")
      (node (ref "U9") (pin "3") (pinfunction "PA2/OSCOUT(LS)_3") (pintype "bidirectional"))
    )
    (net (code "998") (name "unconnected-(U9-PB0{slash}AIN0{slash}[TIM1_CH1N]-Pad30)") (class "Default")
      (node (ref "U9") (pin "30") (pinfunction "PB0/AIN0/[TIM1_CH1N]_30") (pintype "bidirectional"))
    )
    (net (code "999") (name "unconnected-(U9-PB1{slash}AIN1{slash}[TIM1_CH2N]-Pad29)") (class "Default")
      (node (ref "U9") (pin "29") (pinfunction "PB1/AIN1/[TIM1_CH2N]_29") (pintype "bidirectional"))
    )
    (net (code "1000") (name "unconnected-(U9-PB2{slash}AIN2{slash}[TIM1_CH3N]-Pad28)") (class "Default")
      (node (ref "U9") (pin "28") (pinfunction "PB2/AIN2/[TIM1_CH3N]_28") (pintype "bidirectional"))
    )
    (net (code "1001") (name "unconnected-(U9-PB3{slash}AIN3{slash}[TIM1_ETR]-Pad27)") (class "Default")
      (node (ref "U9") (pin "27") (pinfunction "PB3/AIN3/[TIM1_ETR]_27") (pintype "bidirectional"))
    )
    (net (code "1002") (name "unconnected-(U9-PB4{slash}AIN4_[_I2C_SCL]-Pad26)") (class "Default")
      (node (ref "U9") (pin "26") (pinfunction "PB4/AIN4_[_I2C_SCL]_26") (pintype "bidirectional"))
    )
    (net (code "1003") (name "unconnected-(U9-PB5{slash}_AIN5_[I2C_SDA]-Pad25)") (class "Default")
      (node (ref "U9") (pin "25") (pinfunction "PB5/_AIN5_[I2C_SDA]_25") (pintype "bidirectional"))
    )
    (net (code "1004") (name "unconnected-(U9-PC1_(HS){slash}TIM1_CH1-Pad34)") (class "Default")
      (node (ref "U9") (pin "34") (pinfunction "PC1_(HS)/TIM1_CH1_34") (pintype "bidirectional"))
    )
    (net (code "1005") (name "unconnected-(U9-PC2{slash}TIM1_CH2(HS)-Pad35)") (class "Default")
      (node (ref "U9") (pin "35") (pinfunction "PC2/TIM1_CH2(HS)_35") (pintype "bidirectional"))
    )
    (net (code "1006") (name "unconnected-(U9-PC3{slash}_TIM1_CH3(HS)-Pad36)") (class "Default")
      (node (ref "U9") (pin "36") (pinfunction "PC3/_TIM1_CH3(HS)_36") (pintype "bidirectional"))
    )
    (net (code "1007") (name "unconnected-(U9-PC4{slash}_TIM1_CH4(HS)-Pad37)") (class "Default")
      (node (ref "U9") (pin "37") (pinfunction "PC4/_TIM1_CH4(HS)_37") (pintype "bidirectional"))
    )
    (net (code "1008") (name "unconnected-(U9-PC5{slash}_SPI_SCK(HS)-Pad38)") (class "Default")
      (node (ref "U9") (pin "38") (pinfunction "PC5/_SPI_SCK(HS)_38") (pintype "bidirectional"))
    )
    (net (code "1009") (name "unconnected-(U9-PC6{slash}_SPI_MOSI(HS)-Pad41)") (class "Default")
      (node (ref "U9") (pin "41") (pinfunction "PC6/_SPI_MOSI(HS)_41") (pintype "bidirectional"))
    )
    (net (code "1010") (name "unconnected-(U9-PC7{slash}_SPI_MISO(HS)-Pad42)") (class "Default")
      (node (ref "U9") (pin "42") (pinfunction "PC7/_SPI_MISO(HS)_42") (pintype "bidirectional"))
    )
    (net (code "1011") (name "unconnected-(U9-PD0_{slash}TIM3_CH2_[TIM1_BKIN]_[CLK_CCO](HS)-Pad57)") (class "Default")
      (node (ref "U9") (pin "57") (pinfunction "PD0_/TIM3_CH2_[TIM1_BKIN]_[CLK_CCO](HS)_57") (pintype "bidirectional"))
    )
    (net (code "1012") (name "unconnected-(U9-PD1{slash}_SWIM(HS)-Pad58)") (class "Default")
      (node (ref "U9") (pin "58") (pinfunction "PD1/_SWIM(HS)_58") (pintype "bidirectional"))
    )
    (net (code "1013") (name "unconnected-(U9-PD2_{slash}TIM3_CH1[TIM2_CH3](HS)-Pad59)") (class "Default")
      (node (ref "U9") (pin "59") (pinfunction "PD2_/TIM3_CH1[TIM2_CH3](HS)_59") (pintype "bidirectional"))
    )
    (net (code "1014") (name "unconnected-(U9-PD3_{slash}TIM2_CH2_[ADC_ETR](HS)-Pad60)") (class "Default")
      (node (ref "U9") (pin "60") (pinfunction "PD3_/TIM2_CH2_[ADC_ETR](HS)_60") (pintype "bidirectional"))
    )
    (net (code "1015") (name "unconnected-(U9-PD4_{slash}TIM2_CH1_[BEEP](HS)-Pad61)") (class "Default")
      (node (ref "U9") (pin "61") (pinfunction "PD4_/TIM2_CH1_[BEEP](HS)_61") (pintype "bidirectional"))
    )
    (net (code "1016") (name "unconnected-(U9-PD5{slash}UART3_TX-Pad62)") (class "Default")
      (node (ref "U9") (pin "62") (pinfunction "PD5/UART3_TX_62") (pintype "bidirectional"))
    )
    (net (code "1017") (name "unconnected-(U9-PD6{slash}UART3_RX-Pad63)") (class "Default")
      (node (ref "U9") (pin "63") (pinfunction "PD6/UART3_RX_63") (pintype "bidirectional"))
    )
    (net (code "1018") (name "unconnected-(U9-PD7{slash}TLI_[TIM1_CH4]-Pad64)") (class "Default")
      (node (ref "U9") (pin "64") (pinfunction "PD7/TLI_[TIM1_CH4]_64") (pintype "bidirectional"))
    )
    (net (code "1019") (name "unconnected-(U9-PE0_(HS){slash}CLK_CCO-Pad56)") (class "Default")
      (node (ref "U9") (pin "56") (pinfunction "PE0_(HS)/CLK_CCO_56") (pintype "bidirectional"))
    )
    (net (code "1020") (name "unconnected-(U9-PE1_(T){slash}I2C_SCL-Pad55)") (class "Default")
      (node (ref "U9") (pin "55") (pinfunction "PE1_(T)/I2C_SCL_55") (pintype "bidirectional"))
    )
    (net (code "1021") (name "unconnected-(U9-PE2_(T){slash}I2C_SDA-Pad54)") (class "Default")
      (node (ref "U9") (pin "54") (pinfunction "PE2_(T)/I2C_SDA_54") (pintype "bidirectional"))
    )
    (net (code "1022") (name "unconnected-(U9-PE3{slash}TIM1_BKIN-Pad53)") (class "Default")
      (node (ref "U9") (pin "53") (pinfunction "PE3/TIM1_BKIN_53") (pintype "bidirectional"))
    )
    (net (code "1023") (name "unconnected-(U9-PE5{slash}SPI_NSS-Pad33)") (class "Default")
      (node (ref "U9") (pin "33") (pinfunction "PE5/SPI_NSS_33") (pintype "bidirectional"))
    )
    (net (code "1024") (name "unconnected-(U9-PG0{slash}CAN_TX-Pad43)") (class "Default")
      (node (ref "U9") (pin "43") (pinfunction "PG0/CAN_TX_43") (pintype "bidirectional"))
    )
    (net (code "1025") (name "unconnected-(U9-PG2-Pad45)") (class "Default")
      (node (ref "U9") (pin "45") (pinfunction "PG2_45") (pintype "bidirectional"))
    )
    (net (code "1026") (name "unconnected-(U9-PG3-Pad46)") (class "Default")
      (node (ref "U9") (pin "46") (pinfunction "PG3_46") (pintype "bidirectional"))
    )
    (net (code "1027") (name "unconnected-(U9-PG4-Pad47)") (class "Default")
      (node (ref "U9") (pin "47") (pinfunction "PG4_47") (pintype "bidirectional"))
    )
    (net (code "1028") (name "unconnected-(U9-PG5-Pad49)") (class "Default")
      (node (ref "U9") (pin "49") (pinfunction "PG5_49") (pintype "bidirectional"))
    )
    (net (code "1029") (name "unconnected-(U9-PG6-Pad50)") (class "Default")
      (node (ref "U9") (pin "50") (pinfunction "PG6_50") (pintype "bidirectional"))
    )
    (net (code "1030") (name "unconnected-(U9-PG7-Pad51)") (class "Default")
      (node (ref "U9") (pin "51") (pinfunction "PG7_51") (pintype "bidirectional"))
    )
    (net (code "1031") (name "unconnected-(U9-PI0-Pad48)") (class "Default")
      (node (ref "U9") (pin "48") (pinfunction "PI0_48") (pintype "bidirectional"))
    )
    (net (code "1032") (name "unconnected-(U9-UART1_CK{slash}(HS)_PA6-Pad12)") (class "Default")
      (node (ref "U9") (pin "12") (pinfunction "UART1_CK/(HS)_PA6_12") (pintype "bidirectional"))
    )
    (net (code "1033") (name "unconnected-(U9-UART1_RX{slash}(HS)_PA4-Pad10)") (class "Default")
      (node (ref "U9") (pin "10") (pinfunction "UART1_RX/(HS)_PA4_10") (pintype "bidirectional"))
    )
    (net (code "1034") (name "unconnected-(U9-UART1_TX{slash}(HS)_PA5-Pad11)") (class "Default")
      (node (ref "U9") (pin "11") (pinfunction "UART1_TX/(HS)_PA5_11") (pintype "bidirectional"))
    )
    (net (code "1035") (name "unconnected-(U9-VCAP-Pad6)") (class "Default")
      (node (ref "U9") (pin "6") (pinfunction "VCAP_6") (pintype "power_in"))
    )
    (net (code "1036") (name "unconnected-(U9-VDD-Pad7)") (class "Default")
      (node (ref "U9") (pin "7") (pinfunction "VDD_7") (pintype "power_in"))
    )
    (net (code "1037") (name "unconnected-(U9-VDDA-Pad19)") (class "Default")
      (node (ref "U9") (pin "19") (pinfunction "VDDA_19") (pintype "power_in"))
    )
    (net (code "1038") (name "unconnected-(U9-VDDIO_1-Pad8)") (class "Default")
      (node (ref "U9") (pin "8") (pinfunction "VDDIO_1_8") (pintype "power_in"))
    )
    (net (code "1039") (name "unconnected-(U9-VDDIO_2-Pad40)") (class "Default")
      (node (ref "U9") (pin "40") (pinfunction "VDDIO_2_40") (pintype "power_in"))
    )
    (net (code "1040") (name "unconnected-(U9-VREF+-Pad18)") (class "Default")
      (node (ref "U9") (pin "18") (pinfunction "VREF+_18") (pintype "power_in"))
    )
    (net (code "1041") (name "unconnected-(U9-VSS-Pad5)") (class "Default")
      (node (ref "U9") (pin "5") (pinfunction "VSS_5") (pintype "power_in"))
    )
    (net (code "1042") (name "unconnected-(U9-VSSA-Pad20)") (class "Default")
      (node (ref "U9") (pin "20") (pinfunction "VSSA_20") (pintype "power_in"))
    )
    (net (code "1043") (name "unconnected-(U9-VSSIO_1-Pad4)") (class "Default")
      (node (ref "U9") (pin "4") (pinfunction "VSSIO_1_4") (pintype "power_in"))
    )
    (net (code "1044") (name "unconnected-(U9-VSSIO_2-Pad39)") (class "Default")
      (node (ref "U9") (pin "39") (pinfunction "VSSIO_2_39") (pintype "power_in"))
    )
    (net (code "1045") (name "unconnected-(U9-[TIM3_CH1]_TIM2_CH3{slash}PA3-Pad9)") (class "Default")
      (node (ref "U9") (pin "9") (pinfunction "[TIM3_CH1]_TIM2_CH3/PA3_9") (pintype "bidirectional"))
    )
    (net (code "1046") (name "unconnected-(U10A-PA0-WKUP-Pad14)") (class "Default")
      (node (ref "U10") (pin "14") (pinfunction "PA0-WKUP_14") (pintype "bidirectional"))
    )
    (net (code "1047") (name "unconnected-(U10A-PA1-Pad15)") (class "Default")
      (node (ref "U10") (pin "15") (pinfunction "PA1_15") (pintype "bidirectional"))
    )
    (net (code "1048") (name "unconnected-(U10A-PA2-Pad16)") (class "Default")
      (node (ref "U10") (pin "16") (pinfunction "PA2_16") (pintype "bidirectional"))
    )
    (net (code "1049") (name "unconnected-(U10A-PA3-Pad17)") (class "Default")
      (node (ref "U10") (pin "17") (pinfunction "PA3_17") (pintype "bidirectional"))
    )
    (net (code "1050") (name "unconnected-(U10A-PA4-Pad20)") (class "Default")
      (node (ref "U10") (pin "20") (pinfunction "PA4_20") (pintype "bidirectional"))
    )
    (net (code "1051") (name "unconnected-(U10A-PA5-Pad21)") (class "Default")
      (node (ref "U10") (pin "21") (pinfunction "PA5_21") (pintype "bidirectional"))
    )
    (net (code "1052") (name "unconnected-(U10A-PA6-Pad22)") (class "Default")
      (node (ref "U10") (pin "22") (pinfunction "PA6_22") (pintype "bidirectional"))
    )
    (net (code "1053") (name "unconnected-(U10A-PA7-Pad23)") (class "Default")
      (node (ref "U10") (pin "23") (pinfunction "PA7_23") (pintype "bidirectional"))
    )
    (net (code "1054") (name "unconnected-(U10A-PA8-Pad41)") (class "Default")
      (node (ref "U10") (pin "41") (pinfunction "PA8_41") (pintype "bidirectional"))
    )
    (net (code "1055") (name "unconnected-(U10A-PA9-Pad42)") (class "Default")
      (node (ref "U10") (pin "42") (pinfunction "PA9_42") (pintype "bidirectional"))
    )
    (net (code "1056") (name "unconnected-(U10A-PA10-Pad43)") (class "Default")
      (node (ref "U10") (pin "43") (pinfunction "PA10_43") (pintype "bidirectional"))
    )
    (net (code "1057") (name "unconnected-(U10A-PA11-Pad44)") (class "Default")
      (node (ref "U10") (pin "44") (pinfunction "PA11_44") (pintype "bidirectional"))
    )
    (net (code "1058") (name "unconnected-(U10A-PA12-Pad45)") (class "Default")
      (node (ref "U10") (pin "45") (pinfunction "PA12_45") (pintype "bidirectional"))
    )
    (net (code "1059") (name "unconnected-(U10A-PA13-Pad46)") (class "Default")
      (node (ref "U10") (pin "46") (pinfunction "PA13_46") (pintype "bidirectional"))
    )
    (net (code "1060") (name "unconnected-(U10A-PA14-Pad49)") (class "Default")
      (node (ref "U10") (pin "49") (pinfunction "PA14_49") (pintype "bidirectional"))
    )
    (net (code "1061") (name "unconnected-(U10A-PA15-Pad50)") (class "Default")
      (node (ref "U10") (pin "50") (pinfunction "PA15_50") (pintype "bidirectional"))
    )
    (net (code "1062") (name "unconnected-(U10A-PB1-Pad27)") (class "Default")
      (node (ref "U10") (pin "27") (pinfunction "PB1_27") (pintype "bidirectional"))
    )
    (net (code "1063") (name "unconnected-(U10A-PB9-Pad62)") (class "Default")
      (node (ref "U10") (pin "62") (pinfunction "PB9_62") (pintype "bidirectional"))
    )
    (net (code "1064") (name "unconnected-(U10A-PC0-Pad8)") (class "Default")
      (node (ref "U10") (pin "8") (pinfunction "PC0_8") (pintype "bidirectional"))
    )
    (net (code "1065") (name "unconnected-(U10A-PC1-Pad9)") (class "Default")
      (node (ref "U10") (pin "9") (pinfunction "PC1_9") (pintype "bidirectional"))
    )
    (net (code "1066") (name "unconnected-(U10A-PC3-Pad11)") (class "Default")
      (node (ref "U10") (pin "11") (pinfunction "PC3_11") (pintype "bidirectional"))
    )
    (net (code "1067") (name "unconnected-(U10A-PC4-Pad24)") (class "Default")
      (node (ref "U10") (pin "24") (pinfunction "PC4_24") (pintype "bidirectional"))
    )
    (net (code "1068") (name "unconnected-(U10A-PC5-Pad25)") (class "Default")
      (node (ref "U10") (pin "25") (pinfunction "PC5_25") (pintype "bidirectional"))
    )
    (net (code "1069") (name "unconnected-(U10A-PC6-Pad37)") (class "Default")
      (node (ref "U10") (pin "37") (pinfunction "PC6_37") (pintype "bidirectional"))
    )
    (net (code "1070") (name "unconnected-(U10A-PC7-Pad38)") (class "Default")
      (node (ref "U10") (pin "38") (pinfunction "PC7_38") (pintype "bidirectional"))
    )
    (net (code "1071") (name "unconnected-(U10A-PC8-Pad39)") (class "Default")
      (node (ref "U10") (pin "39") (pinfunction "PC8_39") (pintype "bidirectional"))
    )
    (net (code "1072") (name "unconnected-(U10A-PC9-Pad40)") (class "Default")
      (node (ref "U10") (pin "40") (pinfunction "PC9_40") (pintype "bidirectional"))
    )
    (net (code "1073") (name "unconnected-(U10A-PC10-Pad51)") (class "Default")
      (node (ref "U10") (pin "51") (pinfunction "PC10_51") (pintype "bidirectional"))
    )
    (net (code "1074") (name "unconnected-(U10A-PC11-Pad52)") (class "Default")
      (node (ref "U10") (pin "52") (pinfunction "PC11_52") (pintype "bidirectional"))
    )
    (net (code "1075") (name "unconnected-(U10A-PC12-Pad53)") (class "Default")
      (node (ref "U10") (pin "53") (pinfunction "PC12_53") (pintype "bidirectional"))
    )
    (net (code "1076") (name "unconnected-(U10A-PC13-TAMPER-RTC-Pad2)") (class "Default")
      (node (ref "U10") (pin "2") (pinfunction "PC13-TAMPER-RTC_2") (pintype "bidirectional"))
    )
    (net (code "1077") (name "unconnected-(U10A-PC14-OSC32_IN-Pad3)") (class "Default")
      (node (ref "U10") (pin "3") (pinfunction "PC14-OSC32_IN_3") (pintype "bidirectional"))
    )
    (net (code "1078") (name "unconnected-(U10A-PD1-Pad6)") (class "Default")
      (node (ref "U10") (pin "6") (pinfunction "PD1_6") (pintype "bidirectional"))
    )
    (net (code "1079") (name "unconnected-(U11A-BOOT0-Pad60)") (class "Default")
      (node (ref "U11") (pin "60") (pinfunction "BOOT0_60") (pintype "input"))
    )
    (net (code "1080") (name "unconnected-(U11A-NRST-Pad7)") (class "Default")
      (node (ref "U11") (pin "7") (pinfunction "NRST_7") (pintype "bidirectional"))
    )
    (net (code "1081") (name "unconnected-(U11A-PA0-WKUP-Pad14)") (class "Default")
      (node (ref "U11") (pin "14") (pinfunction "PA0-WKUP_14") (pintype "bidirectional"))
    )
    (net (code "1082") (name "unconnected-(U11A-PA1-Pad15)") (class "Default")
      (node (ref "U11") (pin "15") (pinfunction "PA1_15") (pintype "bidirectional"))
    )
    (net (code "1083") (name "unconnected-(U11A-PA2-Pad16)") (class "Default")
      (node (ref "U11") (pin "16") (pinfunction "PA2_16") (pintype "bidirectional"))
    )
    (net (code "1084") (name "unconnected-(U11A-PA3-Pad17)") (class "Default")
      (node (ref "U11") (pin "17") (pinfunction "PA3_17") (pintype "bidirectional"))
    )
    (net (code "1085") (name "unconnected-(U11A-PA4-Pad20)") (class "Default")
      (node (ref "U11") (pin "20") (pinfunction "PA4_20") (pintype "bidirectional"))
    )
    (net (code "1086") (name "unconnected-(U11A-PA5-Pad21)") (class "Default")
      (node (ref "U11") (pin "21") (pinfunction "PA5_21") (pintype "bidirectional"))
    )
    (net (code "1087") (name "unconnected-(U11A-PA6-Pad22)") (class "Default")
      (node (ref "U11") (pin "22") (pinfunction "PA6_22") (pintype "bidirectional"))
    )
    (net (code "1088") (name "unconnected-(U11A-PB0-Pad26)") (class "Default")
      (node (ref "U11") (pin "26") (pinfunction "PB0_26") (pintype "bidirectional"))
    )
    (net (code "1089") (name "unconnected-(U11A-PB1-Pad27)") (class "Default")
      (node (ref "U11") (pin "27") (pinfunction "PB1_27") (pintype "bidirectional"))
    )
    (net (code "1090") (name "unconnected-(U11A-PB2-Pad28)") (class "Default")
      (node (ref "U11") (pin "28") (pinfunction "PB2_28") (pintype "bidirectional"))
    )
    (net (code "1091") (name "unconnected-(U11A-PB3-Pad55)") (class "Default")
      (node (ref "U11") (pin "55") (pinfunction "PB3_55") (pintype "bidirectional"))
    )
    (net (code "1092") (name "unconnected-(U11A-PB4-Pad56)") (class "Default")
      (node (ref "U11") (pin "56") (pinfunction "PB4_56") (pintype "bidirectional"))
    )
    (net (code "1093") (name "unconnected-(U11A-PB5-Pad57)") (class "Default")
      (node (ref "U11") (pin "57") (pinfunction "PB5_57") (pintype "bidirectional"))
    )
    (net (code "1094") (name "unconnected-(U11A-PB6-Pad58)") (class "Default")
      (node (ref "U11") (pin "58") (pinfunction "PB6_58") (pintype "bidirectional"))
    )
    (net (code "1095") (name "unconnected-(U11A-PB7-Pad59)") (class "Default")
      (node (ref "U11") (pin "59") (pinfunction "PB7_59") (pintype "bidirectional"))
    )
    (net (code "1096") (name "unconnected-(U11A-PB8-Pad61)") (class "Default")
      (node (ref "U11") (pin "61") (pinfunction "PB8_61") (pintype "bidirectional"))
    )
    (net (code "1097") (name "unconnected-(U11A-PB9-Pad62)") (class "Default")
      (node (ref "U11") (pin "62") (pinfunction "PB9_62") (pintype "bidirectional"))
    )
    (net (code "1098") (name "unconnected-(U11A-PB10-Pad29)") (class "Default")
      (node (ref "U11") (pin "29") (pinfunction "PB10_29") (pintype "bidirectional"))
    )
    (net (code "1099") (name "unconnected-(U11A-PB11-Pad30)") (class "Default")
      (node (ref "U11") (pin "30") (pinfunction "PB11_30") (pintype "bidirectional"))
    )
    (net (code "1100") (name "unconnected-(U11A-PB12-Pad33)") (class "Default")
      (node (ref "U11") (pin "33") (pinfunction "PB12_33") (pintype "bidirectional"))
    )
    (net (code "1101") (name "unconnected-(U11A-PB13-Pad34)") (class "Default")
      (node (ref "U11") (pin "34") (pinfunction "PB13_34") (pintype "bidirectional"))
    )
    (net (code "1102") (name "unconnected-(U11A-PB14-Pad35)") (class "Default")
      (node (ref "U11") (pin "35") (pinfunction "PB14_35") (pintype "bidirectional"))
    )
    (net (code "1103") (name "unconnected-(U11A-PB15-Pad36)") (class "Default")
      (node (ref "U11") (pin "36") (pinfunction "PB15_36") (pintype "bidirectional"))
    )
    (net (code "1104") (name "unconnected-(U11A-PC0-Pad8)") (class "Default")
      (node (ref "U11") (pin "8") (pinfunction "PC0_8") (pintype "bidirectional"))
    )
    (net (code "1105") (name "unconnected-(U11A-PC1-Pad9)") (class "Default")
      (node (ref "U11") (pin "9") (pinfunction "PC1_9") (pintype "bidirectional"))
    )
    (net (code "1106") (name "unconnected-(U11A-PC3-Pad11)") (class "Default")
      (node (ref "U11") (pin "11") (pinfunction "PC3_11") (pintype "bidirectional"))
    )
    (net (code "1107") (name "unconnected-(U11A-PC4-Pad24)") (class "Default")
      (node (ref "U11") (pin "24") (pinfunction "PC4_24") (pintype "bidirectional"))
    )
    (net (code "1108") (name "unconnected-(U11A-PC5-Pad25)") (class "Default")
      (node (ref "U11") (pin "25") (pinfunction "PC5_25") (pintype "bidirectional"))
    )
    (net (code "1109") (name "unconnected-(U11A-PC6-Pad37)") (class "Default")
      (node (ref "U11") (pin "37") (pinfunction "PC6_37") (pintype "bidirectional"))
    )
    (net (code "1110") (name "unconnected-(U11A-PC7-Pad38)") (class "Default")
      (node (ref "U11") (pin "38") (pinfunction "PC7_38") (pintype "bidirectional"))
    )
    (net (code "1111") (name "unconnected-(U11A-PC8-Pad39)") (class "Default")
      (node (ref "U11") (pin "39") (pinfunction "PC8_39") (pintype "bidirectional"))
    )
    (net (code "1112") (name "unconnected-(U11A-PC9-Pad40)") (class "Default")
      (node (ref "U11") (pin "40") (pinfunction "PC9_40") (pintype "bidirectional"))
    )
    (net (code "1113") (name "unconnected-(U11A-PC10-Pad51)") (class "Default")
      (node (ref "U11") (pin "51") (pinfunction "PC10_51") (pintype "bidirectional"))
    )
    (net (code "1114") (name "unconnected-(U11A-PC11-Pad52)") (class "Default")
      (node (ref "U11") (pin "52") (pinfunction "PC11_52") (pintype "bidirectional"))
    )
    (net (code "1115") (name "unconnected-(U11A-PC12-Pad53)") (class "Default")
      (node (ref "U11") (pin "53") (pinfunction "PC12_53") (pintype "bidirectional"))
    )
    (net (code "1116") (name "unconnected-(U11A-PC13-TAMPER-RTC-Pad2)") (class "Default")
      (node (ref "U11") (pin "2") (pinfunction "PC13-TAMPER-RTC_2") (pintype "bidirectional"))
    )
    (net (code "1117") (name "unconnected-(U11A-PC14-OSC32_IN-Pad3)") (class "Default")
      (node (ref "U11") (pin "3") (pinfunction "PC14-OSC32_IN_3") (pintype "bidirectional"))
    )
    (net (code "1118") (name "unconnected-(U11A-PD0-OSC_IN-Pad5)") (class "Default")
      (node (ref "U11") (pin "5") (pinfunction "PD0-OSC_IN_5") (pintype "bidirectional"))
    )
    (net (code "1119") (name "unconnected-(U11A-PD1-Pad6)") (class "Default")
      (node (ref "U11") (pin "6") (pinfunction "PD1_6") (pintype "bidirectional"))
    )
    (net (code "1120") (name "unconnected-(U12A-PA0-WKUP-Pad14)") (class "Default")
      (node (ref "U12") (pin "14") (pinfunction "PA0-WKUP_14") (pintype "bidirectional"))
    )
    (net (code "1121") (name "unconnected-(U12A-PA1-Pad15)") (class "Default")
      (node (ref "U12") (pin "15") (pinfunction "PA1_15") (pintype "bidirectional"))
    )
    (net (code "1122") (name "unconnected-(U12A-PA2-Pad16)") (class "Default")
      (node (ref "U12") (pin "16") (pinfunction "PA2_16") (pintype "bidirectional"))
    )
    (net (code "1123") (name "unconnected-(U12A-PA3-Pad17)") (class "Default")
      (node (ref "U12") (pin "17") (pinfunction "PA3_17") (pintype "bidirectional"))
    )
    (net (code "1124") (name "unconnected-(U12A-PA11-Pad44)") (class "Default")
      (node (ref "U12") (pin "44") (pinfunction "PA11_44") (pintype "bidirectional"))
    )
    (net (code "1125") (name "unconnected-(U12A-PB1-Pad27)") (class "Default")
      (node (ref "U12") (pin "27") (pinfunction "PB1_27") (pintype "bidirectional"))
    )
    (net (code "1126") (name "unconnected-(U12A-PB9-Pad62)") (class "Default")
      (node (ref "U12") (pin "62") (pinfunction "PB9_62") (pintype "bidirectional"))
    )
    (net (code "1127") (name "unconnected-(U12A-PC3-Pad11)") (class "Default")
      (node (ref "U12") (pin "11") (pinfunction "PC3_11") (pintype "bidirectional"))
    )
    (net (code "1128") (name "unconnected-(U12A-PC6-Pad37)") (class "Default")
      (node (ref "U12") (pin "37") (pinfunction "PC6_37") (pintype "bidirectional"))
    )
    (net (code "1129") (name "unconnected-(U12A-PC9-Pad40)") (class "Default")
      (node (ref "U12") (pin "40") (pinfunction "PC9_40") (pintype "bidirectional"))
    )
    (net (code "1130") (name "unconnected-(U12A-PC10-Pad51)") (class "Default")
      (node (ref "U12") (pin "51") (pinfunction "PC10_51") (pintype "bidirectional"))
    )
    (net (code "1131") (name "unconnected-(U12A-PC11-Pad52)") (class "Default")
      (node (ref "U12") (pin "52") (pinfunction "PC11_52") (pintype "bidirectional"))
    )
    (net (code "1132") (name "unconnected-(U12A-PC12-Pad53)") (class "Default")
      (node (ref "U12") (pin "53") (pinfunction "PC12_53") (pintype "bidirectional"))
    )
    (net (code "1133") (name "unconnected-(U12A-PC13-TAMPER-RTC-Pad2)") (class "Default")
      (node (ref "U12") (pin "2") (pinfunction "PC13-TAMPER-RTC_2") (pintype "bidirectional"))
    )
    (net (code "1134") (name "unconnected-(U12A-PC14-OSC32_IN-Pad3)") (class "Default")
      (node (ref "U12") (pin "3") (pinfunction "PC14-OSC32_IN_3") (pintype "bidirectional"))
    )
    (net (code "1135") (name "unconnected-(U12A-PC15-OSC32_OUT-Pad4)") (class "Default")
      (node (ref "U12") (pin "4") (pinfunction "PC15-OSC32_OUT_4") (pintype "bidirectional"))
    )
    (net (code "1136") (name "unconnected-(U12A-PD1-Pad6)") (class "Default")
      (node (ref "U12") (pin "6") (pinfunction "PD1_6") (pintype "bidirectional"))
    )
    (net (code "1137") (name "unconnected-(U13A-BOOT0-Pad60)") (class "Default")
      (node (ref "U13") (pin "60") (pinfunction "BOOT0_60") (pintype "input"))
    )
    (net (code "1138") (name "unconnected-(U13A-NRST-Pad7)") (class "Default")
      (node (ref "U13") (pin "7") (pinfunction "NRST_7") (pintype "bidirectional"))
    )
    (net (code "1139") (name "unconnected-(U13A-PA0-WKUP-Pad14)") (class "Default")
      (node (ref "U13") (pin "14") (pinfunction "PA0-WKUP_14") (pintype "bidirectional"))
    )
    (net (code "1140") (name "unconnected-(U13A-PA1-Pad15)") (class "Default")
      (node (ref "U13") (pin "15") (pinfunction "PA1_15") (pintype "bidirectional"))
    )
    (net (code "1141") (name "unconnected-(U13A-PA2-Pad16)") (class "Default")
      (node (ref "U13") (pin "16") (pinfunction "PA2_16") (pintype "bidirectional"))
    )
    (net (code "1142") (name "unconnected-(U13A-PA3-Pad17)") (class "Default")
      (node (ref "U13") (pin "17") (pinfunction "PA3_17") (pintype "bidirectional"))
    )
    (net (code "1143") (name "unconnected-(U13A-PA4-Pad20)") (class "Default")
      (node (ref "U13") (pin "20") (pinfunction "PA4_20") (pintype "bidirectional"))
    )
    (net (code "1144") (name "unconnected-(U13A-PA12-Pad45)") (class "Default")
      (node (ref "U13") (pin "45") (pinfunction "PA12_45") (pintype "bidirectional"))
    )
    (net (code "1145") (name "unconnected-(U13A-PB0-Pad26)") (class "Default")
      (node (ref "U13") (pin "26") (pinfunction "PB0_26") (pintype "bidirectional"))
    )
    (net (code "1146") (name "unconnected-(U13A-PB1-Pad27)") (class "Default")
      (node (ref "U13") (pin "27") (pinfunction "PB1_27") (pintype "bidirectional"))
    )
    (net (code "1147") (name "unconnected-(U13A-PB2-Pad28)") (class "Default")
      (node (ref "U13") (pin "28") (pinfunction "PB2_28") (pintype "bidirectional"))
    )
    (net (code "1148") (name "unconnected-(U13A-PB3-Pad55)") (class "Default")
      (node (ref "U13") (pin "55") (pinfunction "PB3_55") (pintype "bidirectional"))
    )
    (net (code "1149") (name "unconnected-(U13A-PB4-Pad56)") (class "Default")
      (node (ref "U13") (pin "56") (pinfunction "PB4_56") (pintype "bidirectional"))
    )
    (net (code "1150") (name "unconnected-(U13A-PB5-Pad57)") (class "Default")
      (node (ref "U13") (pin "57") (pinfunction "PB5_57") (pintype "bidirectional"))
    )
    (net (code "1151") (name "unconnected-(U13A-PB6-Pad58)") (class "Default")
      (node (ref "U13") (pin "58") (pinfunction "PB6_58") (pintype "bidirectional"))
    )
    (net (code "1152") (name "unconnected-(U13A-PB7-Pad59)") (class "Default")
      (node (ref "U13") (pin "59") (pinfunction "PB7_59") (pintype "bidirectional"))
    )
    (net (code "1153") (name "unconnected-(U13A-PB8-Pad61)") (class "Default")
      (node (ref "U13") (pin "61") (pinfunction "PB8_61") (pintype "bidirectional"))
    )
    (net (code "1154") (name "unconnected-(U13A-PB9-Pad62)") (class "Default")
      (node (ref "U13") (pin "62") (pinfunction "PB9_62") (pintype "bidirectional"))
    )
    (net (code "1155") (name "unconnected-(U13A-PB10-Pad29)") (class "Default")
      (node (ref "U13") (pin "29") (pinfunction "PB10_29") (pintype "bidirectional"))
    )
    (net (code "1156") (name "unconnected-(U13A-PB11-Pad30)") (class "Default")
      (node (ref "U13") (pin "30") (pinfunction "PB11_30") (pintype "bidirectional"))
    )
    (net (code "1157") (name "unconnected-(U13A-PB12-Pad33)") (class "Default")
      (node (ref "U13") (pin "33") (pinfunction "PB12_33") (pintype "bidirectional"))
    )
    (net (code "1158") (name "unconnected-(U13A-PB13-Pad34)") (class "Default")
      (node (ref "U13") (pin "34") (pinfunction "PB13_34") (pintype "bidirectional"))
    )
    (net (code "1159") (name "unconnected-(U13A-PB14-Pad35)") (class "Default")
      (node (ref "U13") (pin "35") (pinfunction "PB14_35") (pintype "bidirectional"))
    )
    (net (code "1160") (name "unconnected-(U13A-PB15-Pad36)") (class "Default")
      (node (ref "U13") (pin "36") (pinfunction "PB15_36") (pintype "bidirectional"))
    )
    (net (code "1161") (name "unconnected-(U13A-PC4-Pad24)") (class "Default")
      (node (ref "U13") (pin "24") (pinfunction "PC4_24") (pintype "bidirectional"))
    )
    (net (code "1162") (name "unconnected-(U13A-PC7-Pad38)") (class "Default")
      (node (ref "U13") (pin "38") (pinfunction "PC7_38") (pintype "bidirectional"))
    )
    (net (code "1163") (name "unconnected-(U13A-PC8-Pad39)") (class "Default")
      (node (ref "U13") (pin "39") (pinfunction "PC8_39") (pintype "bidirectional"))
    )
    (net (code "1164") (name "unconnected-(U13A-PC10-Pad51)") (class "Default")
      (node (ref "U13") (pin "51") (pinfunction "PC10_51") (pintype "bidirectional"))
    )
    (net (code "1165") (name "unconnected-(U13A-PC11-Pad52)") (class "Default")
      (node (ref "U13") (pin "52") (pinfunction "PC11_52") (pintype "bidirectional"))
    )
    (net (code "1166") (name "unconnected-(U13A-PC12-Pad53)") (class "Default")
      (node (ref "U13") (pin "53") (pinfunction "PC12_53") (pintype "bidirectional"))
    )
    (net (code "1167") (name "unconnected-(U13A-PC13-TAMPER-RTC-Pad2)") (class "Default")
      (node (ref "U13") (pin "2") (pinfunction "PC13-TAMPER-RTC_2") (pintype "bidirectional"))
    )
    (net (code "1168") (name "unconnected-(U13A-PC14-OSC32_IN-Pad3)") (class "Default")
      (node (ref "U13") (pin "3") (pinfunction "PC14-OSC32_IN_3") (pintype "bidirectional"))
    )
    (net (code "1169") (name "unconnected-(U13A-PC15-OSC32_OUT-Pad4)") (class "Default")
      (node (ref "U13") (pin "4") (pinfunction "PC15-OSC32_OUT_4") (pintype "bidirectional"))
    )
    (net (code "1170") (name "unconnected-(U13A-PD0-OSC_IN-Pad5)") (class "Default")
      (node (ref "U13") (pin "5") (pinfunction "PD0-OSC_IN_5") (pintype "bidirectional"))
    )
    (net (code "1171") (name "unconnected-(U13A-PD1-Pad6)") (class "Default")
      (node (ref "U13") (pin "6") (pinfunction "PD1_6") (pintype "bidirectional"))
    )
    (net (code "1172") (name "unconnected-(U14-PA0-Pad1)") (class "Default")
      (node (ref "U14") (pin "1") (pinfunction "PA0_1") (pintype "bidirectional"))
    )
    (net (code "1173") (name "unconnected-(U14-PA2-Pad3)") (class "Default")
      (node (ref "U14") (pin "3") (pinfunction "PA2_3") (pintype "bidirectional"))
    )
    (net (code "1174") (name "unconnected-(U14-PA4-Pad5)") (class "Default")
      (node (ref "U14") (pin "5") (pinfunction "PA4_5") (pintype "bidirectional"))
    )
    (net (code "1175") (name "unconnected-(U14-PB0-Pad31)") (class "Default")
      (node (ref "U14") (pin "31") (pinfunction "PB0_31") (pintype "bidirectional"))
    )
    (net (code "1176") (name "unconnected-(U14-PB1-Pad32)") (class "Default")
      (node (ref "U14") (pin "32") (pinfunction "PB1_32") (pintype "bidirectional"))
    )
    (net (code "1177") (name "unconnected-(U14-PB2-Pad33)") (class "Default")
      (node (ref "U14") (pin "33") (pinfunction "PB2_33") (pintype "bidirectional"))
    )
    (net (code "1178") (name "unconnected-(U14-PB3-Pad34)") (class "Default")
      (node (ref "U14") (pin "34") (pinfunction "PB3_34") (pintype "bidirectional"))
    )
    (net (code "1179") (name "unconnected-(U14-PB4-Pad35)") (class "Default")
      (node (ref "U14") (pin "35") (pinfunction "PB4_35") (pintype "bidirectional"))
    )
    (net (code "1180") (name "unconnected-(U14-PB5-Pad36)") (class "Default")
      (node (ref "U14") (pin "36") (pinfunction "PB5_36") (pintype "bidirectional"))
    )
    (net (code "1181") (name "unconnected-(U14-PB6-Pad37)") (class "Default")
      (node (ref "U14") (pin "37") (pinfunction "PB6_37") (pintype "bidirectional"))
    )
    (net (code "1182") (name "unconnected-(U14-PB7-Pad38)") (class "Default")
      (node (ref "U14") (pin "38") (pinfunction "PB7_38") (pintype "bidirectional"))
    )
    (net (code "1183") (name "unconnected-(U14-PD0-Pad25)") (class "Default")
      (node (ref "U14") (pin "25") (pinfunction "PD0_25") (pintype "bidirectional"))
    )
    (net (code "1184") (name "unconnected-(U14-PD1-Pad26)") (class "Default")
      (node (ref "U14") (pin "26") (pinfunction "PD1_26") (pintype "bidirectional"))
    )
    (net (code "1185") (name "unconnected-(U14-PD2-Pad27)") (class "Default")
      (node (ref "U14") (pin "27") (pinfunction "PD2_27") (pintype "bidirectional"))
    )
    (net (code "1186") (name "unconnected-(U14-PD3-Pad28)") (class "Default")
      (node (ref "U14") (pin "28") (pinfunction "PD3_28") (pintype "bidirectional"))
    )
    (net (code "1187") (name "unconnected-(U14-PD4-Pad45)") (class "Default")
      (node (ref "U14") (pin "45") (pinfunction "PD4_45") (pintype "bidirectional"))
    )
    (net (code "1188") (name "unconnected-(U14-PD5-Pad46)") (class "Default")
      (node (ref "U14") (pin "46") (pinfunction "PD5_46") (pintype "bidirectional"))
    )
    (net (code "1189") (name "unconnected-(U14-PD6-Pad47)") (class "Default")
      (node (ref "U14") (pin "47") (pinfunction "PD6_47") (pintype "bidirectional"))
    )
    (net (code "1190") (name "unconnected-(U14-PD7-Pad48)") (class "Default")
      (node (ref "U14") (pin "48") (pinfunction "PD7_48") (pintype "bidirectional"))
    )
    (net (code "1191") (name "unconnected-(U14-PE6-Pad63)") (class "Default")
      (node (ref "U14") (pin "63") (pinfunction "PE6_63") (pintype "bidirectional"))
    )
    (net (code "1192") (name "unconnected-(U14-PF0-Pad39)") (class "Default")
      (node (ref "U14") (pin "39") (pinfunction "PF0_39") (pintype "bidirectional"))
    )
    (net (code "1193") (name "unconnected-(U14-PF1-Pad40)") (class "Default")
      (node (ref "U14") (pin "40") (pinfunction "PF1_40") (pintype "bidirectional"))
    )
    (net (code "1194") (name "unconnected-(U14-PF4-Pad41)") (class "Default")
      (node (ref "U14") (pin "41") (pinfunction "PF4_41") (pintype "bidirectional"))
    )
    (net (code "1195") (name "unconnected-(U14-PF5-Pad42)") (class "Default")
      (node (ref "U14") (pin "42") (pinfunction "PF5_42") (pintype "bidirectional"))
    )
    (net (code "1196") (name "unconnected-(U14-PF6-Pad43)") (class "Default")
      (node (ref "U14") (pin "43") (pinfunction "PF6_43") (pintype "bidirectional"))
    )
    (net (code "1197") (name "unconnected-(U14-PF7-Pad44)") (class "Default")
      (node (ref "U14") (pin "44") (pinfunction "PF7_44") (pintype "bidirectional"))
    )
    (net (code "1198") (name "unconnected-(U14-PG3-Pad17)") (class "Default")
      (node (ref "U14") (pin "17") (pinfunction "PG3_17") (pintype "bidirectional"))
    )
    (net (code "1199") (name "unconnected-(U14-PG5-Pad50)") (class "Default")
      (node (ref "U14") (pin "50") (pinfunction "PG5_50") (pintype "bidirectional"))
    )
    (net (code "1200") (name "unconnected-(U14-PG6-Pad51)") (class "Default")
      (node (ref "U14") (pin "51") (pinfunction "PG6_51") (pintype "bidirectional"))
    )
    (net (code "1201") (name "unconnected-(U14-PG7-Pad52)") (class "Default")
      (node (ref "U14") (pin "52") (pinfunction "PG7_52") (pintype "bidirectional"))
    )
    (net (code "1202") (name "unconnected-(U14-VDD1-Pad11)") (class "Default")
      (node (ref "U14") (pin "11") (pinfunction "VDD1_11") (pintype "power_in"))
    )
    (net (code "1203") (name "unconnected-(U14-VDD2-Pad55)") (class "Default")
      (node (ref "U14") (pin "55") (pinfunction "VDD2_55") (pintype "power_in"))
    )
    (net (code "1204") (name "unconnected-(U14-VDD3-Pad29)") (class "Default")
      (node (ref "U14") (pin "29") (pinfunction "VDD3_29") (pintype "power_in"))
    )
    (net (code "1205") (name "unconnected-(U14-VDDA-Pad12)") (class "Default")
      (node (ref "U14") (pin "12") (pinfunction "VDDA_12") (pintype "power_in"))
    )
    (net (code "1206") (name "unconnected-(U14-VLCD-Pad18)") (class "Default")
      (node (ref "U14") (pin "18") (pinfunction "VLCD_18") (pintype "passive"))
    )
    (net (code "1207") (name "unconnected-(U14-VREF+-Pad13)") (class "Default")
      (node (ref "U14") (pin "13") (pinfunction "VREF+_13") (pintype "power_in"))
    )
    (net (code "1208") (name "unconnected-(U14-VSS1-Pad10)") (class "Default")
      (node (ref "U14") (pin "10") (pinfunction "VSS1_10") (pintype "power_in"))
    )
    (net (code "1209") (name "unconnected-(U14-VSS2-Pad56)") (class "Default")
      (node (ref "U14") (pin "56") (pinfunction "VSS2_56") (pintype "power_in"))
    )
    (net (code "1210") (name "unconnected-(U14-VSS3-Pad30)") (class "Default")
      (node (ref "U14") (pin "30") (pinfunction "VSS3_30") (pintype "power_in"))
    )
    (net (code "1211") (name "unconnected-(U14-VSSA{slash}VREF--Pad9)") (class "Default")
      (node (ref "U14") (pin "9") (pinfunction "VSSA/VREF-_9") (pintype "power_in"))
    )
    (net (code "1212") (name "unconnected-(U15A-PA0-WKUP(PA0){slash}USART2_CTS{slash}UART4_TX{slash}ETH_MII_CRS{slash}TIM2_CH1_ETR{slash}TIM5_CH1{slash}TIM8_ETR{slash}EVENTOUT{slash}ADC123_IN0{slash}WKUP-Pad14)") (class "Default")
      (node (ref "U15") (pin "14") (pinfunction "PA0-WKUP(PA0)/USART2_CTS/UART4_TX/ETH_MII_CRS/TIM2_CH1_ETR/TIM5_CH1/TIM8_ETR/EVENTOUT/ADC123_IN0/WKUP_14") (pintype "bidirectional"))
    )
    (net (code "1213") (name "unconnected-(U15A-PA1{slash}USART2_RTS{slash}UART4_RX{slash}ETH_RMII_REF_CLK{slash}ETH_MII_RX_CLK{slash}TIM5_CH2{slash}TIM2_CH2{slash}EVENTOUT{slash}ADC123_IN1-Pad15)") (class "Default")
      (node (ref "U15") (pin "15") (pinfunction "PA1/USART2_RTS/UART4_RX/ETH_RMII_REF_CLK/ETH_MII_RX_CLK/TIM5_CH2/TIM2_CH2/EVENTOUT/ADC123_IN1_15") (pintype "bidirectional"))
    )
    (net (code "1214") (name "unconnected-(U15A-PA2{slash}USART2_TX{slash}TIM5_CH3{slash}TIM9_CH1{slash}TIM2_CH3{slash}ETH_MDIO{slash}EVENTOUT{slash}ADC123_IN2-Pad16)") (class "Default")
      (node (ref "U15") (pin "16") (pinfunction "PA2/USART2_TX/TIM5_CH3/TIM9_CH1/TIM2_CH3/ETH_MDIO/EVENTOUT/ADC123_IN2_16") (pintype "bidirectional"))
    )
    (net (code "1215") (name "unconnected-(U15A-PA3{slash}USART2_RX{slash}TIM5_CH4{slash}TIM9_CH2{slash}TIM2_CH4{slash}OTG_HS_ULPI_D0{slash}ETH_MII_COL{slash}EVENTOUT{slash}ADC123_IN3-Pad17)") (class "Default")
      (node (ref "U15") (pin "17") (pinfunction "PA3/USART2_RX/TIM5_CH4/TIM9_CH2/TIM2_CH4/OTG_HS_ULPI_D0/ETH_MII_COL/EVENTOUT/ADC123_IN3_17") (pintype "bidirectional"))
    )
    (net (code "1216") (name "unconnected-(U15A-PA4{slash}SPI1_NSS{slash}SPI3_NSS{slash}USART2_CK{slash}DCMI_HSYNC{slash}OTG_HS_SOF{slash}I2S3_WS{slash}EVENTOUT{slash}ADC12_IN4{slash}DAC1_OUT-Pad20)") (class "Default")
      (node (ref "U15") (pin "20") (pinfunction "PA4/SPI1_NSS/SPI3_NSS/USART2_CK/DCMI_HSYNC/OTG_HS_SOF/I2S3_WS/EVENTOUT/ADC12_IN4/DAC1_OUT_20") (pintype "bidirectional"))
    )
    (net (code "1217") (name "unconnected-(U15A-PA5{slash}SPI1_SCK{slash}OTG_HS_ULPI_CK{slash}TIM2_CH1_ETR{slash}TIM8_CHIN{slash}EVENTOUT{slash}ADC12_IN5{slash}DAC2_OUT-Pad21)") (class "Default")
      (node (ref "U15") (pin "21") (pinfunction "PA5/SPI1_SCK/OTG_HS_ULPI_CK/TIM2_CH1_ETR/TIM8_CHIN/EVENTOUT/ADC12_IN5/DAC2_OUT_21") (pintype "bidirectional"))
    )
    (net (code "1218") (name "unconnected-(U15A-PA6{slash}SPI1_MISO{slash}TIM8_BKIN{slash}TIM13_CH1{slash}DCMI_PIXCLK{slash}TIM3_CH1{slash}TIM1_BKIN{slash}EVENTOUT{slash}ADC12_IN6-Pad22)") (class "Default")
      (node (ref "U15") (pin "22") (pinfunction "PA6/SPI1_MISO/TIM8_BKIN/TIM13_CH1/DCMI_PIXCLK/TIM3_CH1/TIM1_BKIN/EVENTOUT/ADC12_IN6_22") (pintype "bidirectional"))
    )
    (net (code "1219") (name "unconnected-(U15A-PA7{slash}SPI1_MOSI{slash}TIM8_CH1N{slash}TIM14_CH1{slash}TIM3_CH2{slash}ETH_MII_RX_DV{slash}TIM1_CH1N{slash}RMII_CRS_DV{slash}EVENTOUT{slash}ADC12_IN7-Pad23)") (class "Default")
      (node (ref "U15") (pin "23") (pinfunction "PA7/SPI1_MOSI/TIM8_CH1N/TIM14_CH1/TIM3_CH2/ETH_MII_RX_DV/TIM1_CH1N/RMII_CRS_DV/EVENTOUT/ADC12_IN7_23") (pintype "bidirectional"))
    )
    (net (code "1220") (name "unconnected-(U15A-PA8{slash}MCO1{slash}USART1_CK{slash}TIM1_CH1{slash}I2C3_SCL{slash}OTG_FS_SOF{slash}EVENTOUT-Pad41)") (class "Default")
      (node (ref "U15") (pin "41") (pinfunction "PA8/MCO1/USART1_CK/TIM1_CH1/I2C3_SCL/OTG_FS_SOF/EVENTOUT_41") (pintype "bidirectional"))
    )
    (net (code "1221") (name "unconnected-(U15A-PA9{slash}USART1_TX{slash}TIM1_CH2{slash}I2C3_SMBA{slash}DCMI_D0{slash}EVENTOUT{slash}OTG_FS_VBUS-Pad42)") (class "Default")
      (node (ref "U15") (pin "42") (pinfunction "PA9/USART1_TX/TIM1_CH2/I2C3_SMBA/DCMI_D0/EVENTOUT/OTG_FS_VBUS_42") (pintype "bidirectional"))
    )
    (net (code "1222") (name "unconnected-(U15A-PA10{slash}USART1_RX{slash}TIM1_CH3{slash}OTG_FS_ID{slash}DCMI_D1{slash}EVENTOUT-Pad43)") (class "Default")
      (node (ref "U15") (pin "43") (pinfunction "PA10/USART1_RX/TIM1_CH3/OTG_FS_ID/DCMI_D1/EVENTOUT_43") (pintype "bidirectional"))
    )
    (net (code "1223") (name "unconnected-(U15A-PA11{slash}USART1_CTS{slash}CAN1_RX{slash}TIM1_CH4{slash}OTG_FS_DM{slash}EVENTOUT-Pad44)") (class "Default")
      (node (ref "U15") (pin "44") (pinfunction "PA11/USART1_CTS/CAN1_RX/TIM1_CH4/OTG_FS_DM/EVENTOUT_44") (pintype "bidirectional"))
    )
    (net (code "1224") (name "unconnected-(U15A-PA12{slash}USART1_RTS{slash}CAN1_TX{slash}TIM1_ETR{slash}OTG_FS_DP{slash}EVENTOUT-Pad45)") (class "Default")
      (node (ref "U15") (pin "45") (pinfunction "PA12/USART1_RTS/CAN1_TX/TIM1_ETR/OTG_FS_DP/EVENTOUT_45") (pintype "bidirectional"))
    )
    (net (code "1225") (name "unconnected-(U15A-PA13(JTMS-SWDIO){slash}JTMS-SWDIO{slash}EVENTOUT-Pad46)") (class "Default")
      (node (ref "U15") (pin "46") (pinfunction "PA13(JTMS-SWDIO)/JTMS-SWDIO/EVENTOUT_46") (pintype "bidirectional"))
    )
    (net (code "1226") (name "unconnected-(U15A-PA14(JTCK-SWCLK){slash}JTCK-SWCLK{slash}EVENTOUT-Pad49)") (class "Default")
      (node (ref "U15") (pin "49") (pinfunction "PA14(JTCK-SWCLK)/JTCK-SWCLK/EVENTOUT_49") (pintype "bidirectional"))
    )
    (net (code "1227") (name "unconnected-(U15A-PA15(JTDI){slash}JTDI{slash}SPI3_NSS{slash}I2S3_WS{slash}TIM2_CH1_ETR{slash}SPI1_NSS{slash}EVENTOUT-Pad50)") (class "Default")
      (node (ref "U15") (pin "50") (pinfunction "PA15(JTDI)/JTDI/SPI3_NSS/I2S3_WS/TIM2_CH1_ETR/SPI1_NSS/EVENTOUT_50") (pintype "bidirectional"))
    )
    (net (code "1228") (name "unconnected-(U15A-PB0{slash}TIM3_CH3{slash}TIM8_CH2N{slash}OTG_HS_ULPI_D1{slash}ETH_MII_RXD2{slash}TIM1_CH2N{slash}EVENTOUT{slash}ADC12_IN8-Pad26)") (class "Default")
      (node (ref "U15") (pin "26") (pinfunction "PB0/TIM3_CH3/TIM8_CH2N/OTG_HS_ULPI_D1/ETH_MII_RXD2/TIM1_CH2N/EVENTOUT/ADC12_IN8_26") (pintype "bidirectional"))
    )
    (net (code "1229") (name "unconnected-(U15A-PB1{slash}TIM3_CH4{slash}TIM8_CH3N{slash}OTG_HS_ULPI_D2{slash}ETH_MII_RXD3{slash}OTG_HS_INTN{slash}TIM1_CH3N{slash}EVENTOUT{slash}ADC12_IN9-Pad27)") (class "Default")
      (node (ref "U15") (pin "27") (pinfunction "PB1/TIM3_CH4/TIM8_CH3N/OTG_HS_ULPI_D2/ETH_MII_RXD3/OTG_HS_INTN/TIM1_CH3N/EVENTOUT/ADC12_IN9_27") (pintype "bidirectional"))
    )
    (net (code "1230") (name "unconnected-(U15A-PB3(JTDO{slash}TRACESWO){slash}JTDO{slash}TRACESWO{slash}SPI3_SCK{slash}I2S3_CK{slash}TIM2_CH2{slash}SPI1_SCK{slash}EVENTOUT-Pad55)") (class "Default")
      (node (ref "U15") (pin "55") (pinfunction "PB3(JTDO/TRACESWO)/JTDO/TRACESWO/SPI3_SCK/I2S3_CK/TIM2_CH2/SPI1_SCK/EVENTOUT_55") (pintype "bidirectional"))
    )
    (net (code "1231") (name "unconnected-(U15A-PB4(NJTRST){slash}NJTRST{slash}SPI3_MISO{slash}TIM3_CH1{slash}SPI1_MISO{slash}I2S3ext_SD{slash}EVENTOUT-Pad56)") (class "Default")
      (node (ref "U15") (pin "56") (pinfunction "PB4(NJTRST)/NJTRST/SPI3_MISO/TIM3_CH1/SPI1_MISO/I2S3ext_SD/EVENTOUT_56") (pintype "bidirectional"))
    )
    (net (code "1232") (name "unconnected-(U15A-PB5{slash}I2C1_SMBA{slash}CAN2_RX{slash}OTG_HS_ULPI_D7{slash}ETH_PPS_OUT{slash}TIM3_CH2{slash}SPI1_MOSI{slash}SPI3_MOSI{slash}DCMI_D10{slash}I2S3_SD{slash}EVENTOUT-Pad57)") (class "Default")
      (node (ref "U15") (pin "57") (pinfunction "PB5/I2C1_SMBA/CAN2_RX/OTG_HS_ULPI_D7/ETH_PPS_OUT/TIM3_CH2/SPI1_MOSI/SPI3_MOSI/DCMI_D10/I2S3_SD/EVENTOUT_57") (pintype "bidirectional"))
    )
    (net (code "1233") (name "unconnected-(U15A-PB6{slash}I2C1_SCL{slash}TIM4_CH1{slash}CAN2_TX{slash}DCMI_D5{slash}USART1_TX{slash}EVENTOUT-Pad58)") (class "Default")
      (node (ref "U15") (pin "58") (pinfunction "PB6/I2C1_SCL/TIM4_CH1/CAN2_TX/DCMI_D5/USART1_TX/EVENTOUT_58") (pintype "bidirectional"))
    )
    (net (code "1234") (name "unconnected-(U15A-PB7{slash}I2C1_SDA{slash}FSMC_NL{slash}DCMI_VSYNC{slash}USART1_RX{slash}TIM4_CH2{slash}EVENTOUT-Pad59)") (class "Default")
      (node (ref "U15") (pin "59") (pinfunction "PB7/I2C1_SDA/FSMC_NL/DCMI_VSYNC/USART1_RX/TIM4_CH2/EVENTOUT_59") (pintype "bidirectional"))
    )
    (net (code "1235") (name "unconnected-(U15A-PB8{slash}TIM4_CH3{slash}SDIO_D4{slash}TIM10_CH1{slash}DCMI_D6{slash}ETH_MII_TXD3{slash}I2C1_SCL{slash}CAN1_RX{slash}EVENTOUT-Pad61)") (class "Default")
      (node (ref "U15") (pin "61") (pinfunction "PB8/TIM4_CH3/SDIO_D4/TIM10_CH1/DCMI_D6/ETH_MII_TXD3/I2C1_SCL/CAN1_RX/EVENTOUT_61") (pintype "bidirectional"))
    )
    (net (code "1236") (name "unconnected-(U15A-PB9{slash}SPI2_NSS{slash}I2S2_WS{slash}TIM4_CH4{slash}TIM11_CH1{slash}SDIO_D5{slash}DCMI_D7{slash}I2C1_SDA{slash}CAN1_TX{slash}EVENTOUT-Pad62)") (class "Default")
      (node (ref "U15") (pin "62") (pinfunction "PB9/SPI2_NSS/I2S2_WS/TIM4_CH4/TIM11_CH1/SDIO_D5/DCMI_D7/I2C1_SDA/CAN1_TX/EVENTOUT_62") (pintype "bidirectional"))
    )
    (net (code "1237") (name "unconnected-(U15A-PB10{slash}SPI2_SCK{slash}I2S2_CK{slash}I2C2_SCL{slash}USART3_TX{slash}OTG_HS_ULPI_D3{slash}ETH_MII_RX_ER{slash}TIM2_CH3{slash}EVENTOUT-Pad29)") (class "Default")
      (node (ref "U15") (pin "29") (pinfunction "PB10/SPI2_SCK/I2S2_CK/I2C2_SCL/USART3_TX/OTG_HS_ULPI_D3/ETH_MII_RX_ER/TIM2_CH3/EVENTOUT_29") (pintype "bidirectional"))
    )
    (net (code "1238") (name "unconnected-(U15A-PB11{slash}I2C2_SDA{slash}USART3_RX{slash}OTG_HS_ULPI_D4{slash}ETH_RMII_TX_EN{slash}ETH_MII_TX_EN{slash}TIM2_CH4{slash}EVENTOUT-Pad30)") (class "Default")
      (node (ref "U15") (pin "30") (pinfunction "PB11/I2C2_SDA/USART3_RX/OTG_HS_ULPI_D4/ETH_RMII_TX_EN/ETH_MII_TX_EN/TIM2_CH4/EVENTOUT_30") (pintype "bidirectional"))
    )
    (net (code "1239") (name "unconnected-(U15A-PB12{slash}SPI2_NSS{slash}I2S2_WS{slash}I2C2_SMBA{slash}USART3_CK{slash}TIM1_BKIN{slash}CAN2_RX{slash}OTG_HS_ULPI_D5{slash}ETH_RMII_TXD0{slash}ETH_MII_TXD0{slash}OTG_HS_ID{slash}EVENTOUT-Pad33)") (class "Default")
      (node (ref "U15") (pin "33") (pinfunction "PB12/SPI2_NSS/I2S2_WS/I2C2_SMBA/USART3_CK/TIM1_BKIN/CAN2_RX/OTG_HS_ULPI_D5/ETH_RMII_TXD0/ETH_MII_TXD0/OTG_HS_ID/EVENTOUT_33") (pintype "bidirectional"))
    )
    (net (code "1240") (name "unconnected-(U15A-PB13{slash}SPI2_SCK{slash}I2S2_CK{slash}USART3_CTS{slash}TIM1_CH1N{slash}CAN2_TX{slash}OTG_HS_ULPI_D6{slash}ETH_RMII_TXD1{slash}ETH_MII_TXD1{slash}EVENTOUT{slash}OTG_HS_VBUS-Pad34)") (class "Default")
      (node (ref "U15") (pin "34") (pinfunction "PB13/SPI2_SCK/I2S2_CK/USART3_CTS/TIM1_CH1N/CAN2_TX/OTG_HS_ULPI_D6/ETH_RMII_TXD1/ETH_MII_TXD1/EVENTOUT/OTG_HS_VBUS_34") (pintype "bidirectional"))
    )
    (net (code "1241") (name "unconnected-(U15A-PB14{slash}SPI2_MISO{slash}TIM1_CH2N{slash}TIM12_CH1{slash}OTG_HS_DM{slash}USART3_RTS{slash}TIM8_CH2N{slash}I2S2ext_SD{slash}EVENTOUT-Pad35)") (class "Default")
      (node (ref "U15") (pin "35") (pinfunction "PB14/SPI2_MISO/TIM1_CH2N/TIM12_CH1/OTG_HS_DM/USART3_RTS/TIM8_CH2N/I2S2ext_SD/EVENTOUT_35") (pintype "bidirectional"))
    )
    (net (code "1242") (name "unconnected-(U15A-PB15{slash}SPI2_MOSI{slash}I2S2_SD{slash}TIM1_CH3N{slash}TIM8_CH3N{slash}TIM12_CH2{slash}OTG_HS_DP{slash}EVENTOUT-Pad36)") (class "Default")
      (node (ref "U15") (pin "36") (pinfunction "PB15/SPI2_MOSI/I2S2_SD/TIM1_CH3N/TIM8_CH3N/TIM12_CH2/OTG_HS_DP/EVENTOUT_36") (pintype "bidirectional"))
    )
    (net (code "1243") (name "unconnected-(U16A-PA0-WKUP(PA0){slash}USART2_CTS{slash}UART4_TX{slash}ETH_MII_CRS{slash}TIM2_CH1_ETR{slash}TIM5_CH1{slash}TIM8_ETR{slash}EVENTOUT{slash}ADC123_IN0{slash}WKUP-Pad23)") (class "Default")
      (node (ref "U16") (pin "23") (pinfunction "PA0-WKUP(PA0)/USART2_CTS/UART4_TX/ETH_MII_CRS/TIM2_CH1_ETR/TIM5_CH1/TIM8_ETR/EVENTOUT/ADC123_IN0/WKUP_23") (pintype "bidirectional"))
    )
    (net (code "1244") (name "unconnected-(U16A-PA1{slash}USART2_RTS{slash}UART4_RX{slash}ETH_RMII_REF_CLK{slash}ETH_MII_RX_CLK{slash}TIM5_CH2{slash}TIM2_CH2{slash}EVENTOUT{slash}ADC123_IN1-Pad24)") (class "Default")
      (node (ref "U16") (pin "24") (pinfunction "PA1/USART2_RTS/UART4_RX/ETH_RMII_REF_CLK/ETH_MII_RX_CLK/TIM5_CH2/TIM2_CH2/EVENTOUT/ADC123_IN1_24") (pintype "bidirectional"))
    )
    (net (code "1245") (name "unconnected-(U16A-PA2{slash}USART2_TX{slash}TIM5_CH3{slash}TIM9_CH1{slash}TIM2_CH3{slash}ETH_MDIO{slash}EVENTOUT{slash}ADC123_IN2-Pad25)") (class "Default")
      (node (ref "U16") (pin "25") (pinfunction "PA2/USART2_TX/TIM5_CH3/TIM9_CH1/TIM2_CH3/ETH_MDIO/EVENTOUT/ADC123_IN2_25") (pintype "bidirectional"))
    )
    (net (code "1246") (name "unconnected-(U16A-PA3{slash}USART2_RX{slash}TIM5_CH4{slash}TIM9_CH2{slash}TIM2_CH4{slash}OTG_HS_ULPI_D0{slash}ETH_MII_COL{slash}EVENTOUT{slash}ADC123_IN3-Pad26)") (class "Default")
      (node (ref "U16") (pin "26") (pinfunction "PA3/USART2_RX/TIM5_CH4/TIM9_CH2/TIM2_CH4/OTG_HS_ULPI_D0/ETH_MII_COL/EVENTOUT/ADC123_IN3_26") (pintype "bidirectional"))
    )
    (net (code "1247") (name "unconnected-(U16A-PA4{slash}SPI1_NSS{slash}SPI3_NSS{slash}USART2_CK{slash}DCMI_HSYNC{slash}OTG_HS_SOF{slash}I2S3_WS{slash}EVENTOUT{slash}ADC12_IN4{slash}DAC1_OUT-Pad29)") (class "Default")
      (node (ref "U16") (pin "29") (pinfunction "PA4/SPI1_NSS/SPI3_NSS/USART2_CK/DCMI_HSYNC/OTG_HS_SOF/I2S3_WS/EVENTOUT/ADC12_IN4/DAC1_OUT_29") (pintype "bidirectional"))
    )
    (net (code "1248") (name "unconnected-(U16A-PA5{slash}SPI1_SCK{slash}OTG_HS_ULPI_CK{slash}TIM2_CH1_ETR{slash}TIM8_CHIN{slash}EVENTOUT{slash}ADC12_IN5{slash}DAC2_OUT-Pad30)") (class "Default")
      (node (ref "U16") (pin "30") (pinfunction "PA5/SPI1_SCK/OTG_HS_ULPI_CK/TIM2_CH1_ETR/TIM8_CHIN/EVENTOUT/ADC12_IN5/DAC2_OUT_30") (pintype "bidirectional"))
    )
    (net (code "1249") (name "unconnected-(U16A-PA6{slash}SPI1_MISO{slash}TIM8_BKIN{slash}TIM13_CH1{slash}DCMI_PIXCLK{slash}TIM3_CH1{slash}TIM1_BKIN{slash}EVENTOUT{slash}ADC12_IN6-Pad31)") (class "Default")
      (node (ref "U16") (pin "31") (pinfunction "PA6/SPI1_MISO/TIM8_BKIN/TIM13_CH1/DCMI_PIXCLK/TIM3_CH1/TIM1_BKIN/EVENTOUT/ADC12_IN6_31") (pintype "bidirectional"))
    )
    (net (code "1250") (name "unconnected-(U16A-PA7{slash}SPI1_MOSI{slash}TIM8_CH1N{slash}TIM14_CH1{slash}TIM3_CH2{slash}ETH_MII_RX_DV{slash}TIM1_CH1N{slash}RMII_CRS_DV{slash}EVENTOUT{slash}ADC12_IN7-Pad32)") (class "Default")
      (node (ref "U16") (pin "32") (pinfunction "PA7/SPI1_MOSI/TIM8_CH1N/TIM14_CH1/TIM3_CH2/ETH_MII_RX_DV/TIM1_CH1N/RMII_CRS_DV/EVENTOUT/ADC12_IN7_32") (pintype "bidirectional"))
    )
    (net (code "1251") (name "unconnected-(U16A-PA8{slash}MCO1{slash}USART1_CK{slash}TIM1_CH1{slash}I2C3_SCL{slash}OTG_FS_SOF{slash}EVENTOUT-Pad67)") (class "Default")
      (node (ref "U16") (pin "67") (pinfunction "PA8/MCO1/USART1_CK/TIM1_CH1/I2C3_SCL/OTG_FS_SOF/EVENTOUT_67") (pintype "bidirectional"))
    )
    (net (code "1252") (name "unconnected-(U16A-PA9{slash}USART1_TX{slash}TIM1_CH2{slash}I2C3_SMBA{slash}DCMI_D0{slash}EVENTOUT{slash}OTG_FS_VBUS-Pad68)") (class "Default")
      (node (ref "U16") (pin "68") (pinfunction "PA9/USART1_TX/TIM1_CH2/I2C3_SMBA/DCMI_D0/EVENTOUT/OTG_FS_VBUS_68") (pintype "bidirectional"))
    )
    (net (code "1253") (name "unconnected-(U16A-PA10{slash}USART1_RX{slash}TIM1_CH3{slash}OTG_FS_ID{slash}DCMI_D1{slash}EVENTOUT-Pad69)") (class "Default")
      (node (ref "U16") (pin "69") (pinfunction "PA10/USART1_RX/TIM1_CH3/OTG_FS_ID/DCMI_D1/EVENTOUT_69") (pintype "bidirectional"))
    )
    (net (code "1254") (name "unconnected-(U16A-PA11{slash}USART1_CTS{slash}CAN1_RX{slash}TIM1_CH4{slash}OTG_FS_DM{slash}EVENTOUT-Pad70)") (class "Default")
      (node (ref "U16") (pin "70") (pinfunction "PA11/USART1_CTS/CAN1_RX/TIM1_CH4/OTG_FS_DM/EVENTOUT_70") (pintype "bidirectional"))
    )
    (net (code "1255") (name "unconnected-(U16A-PA12{slash}USART1_RTS{slash}CAN1_TX{slash}TIM1_ETR{slash}OTG_FS_DP{slash}EVENTOUT-Pad71)") (class "Default")
      (node (ref "U16") (pin "71") (pinfunction "PA12/USART1_RTS/CAN1_TX/TIM1_ETR/OTG_FS_DP/EVENTOUT_71") (pintype "bidirectional"))
    )
    (net (code "1256") (name "unconnected-(U16A-PA13(JTMS-SWDIO){slash}JTMS-SWDIO{slash}EVENTOUT-Pad72)") (class "Default")
      (node (ref "U16") (pin "72") (pinfunction "PA13(JTMS-SWDIO)/JTMS-SWDIO/EVENTOUT_72") (pintype "bidirectional"))
    )
    (net (code "1257") (name "unconnected-(U16A-PA14(JTCK-SWCLK){slash}JTCK-SWCLK{slash}EVENTOUT-Pad76)") (class "Default")
      (node (ref "U16") (pin "76") (pinfunction "PA14(JTCK-SWCLK)/JTCK-SWCLK/EVENTOUT_76") (pintype "bidirectional"))
    )
    (net (code "1258") (name "unconnected-(U16A-PA15(JTDI){slash}JTDI{slash}SPI3_NSS{slash}I2S3_WS{slash}TIM2_CH1_ETR{slash}SPI1_NSS{slash}EVENTOUT-Pad77)") (class "Default")
      (node (ref "U16") (pin "77") (pinfunction "PA15(JTDI)/JTDI/SPI3_NSS/I2S3_WS/TIM2_CH1_ETR/SPI1_NSS/EVENTOUT_77") (pintype "bidirectional"))
    )
    (net (code "1259") (name "unconnected-(U16A-PB0{slash}TIM3_CH3{slash}TIM8_CH2N{slash}OTG_HS_ULPI_D1{slash}ETH_MII_RXD2{slash}TIM1_CH2N{slash}EVENTOUT{slash}ADC12_IN8-Pad35)") (class "Default")
      (node (ref "U16") (pin "35") (pinfunction "PB0/TIM3_CH3/TIM8_CH2N/OTG_HS_ULPI_D1/ETH_MII_RXD2/TIM1_CH2N/EVENTOUT/ADC12_IN8_35") (pintype "bidirectional"))
    )
    (net (code "1260") (name "unconnected-(U16A-PB1{slash}TIM3_CH4{slash}TIM8_CH3N{slash}OTG_HS_ULPI_D2{slash}ETH_MII_RXD3{slash}OTG_HS_INTN{slash}TIM1_CH3N{slash}EVENTOUT{slash}ADC12_IN9-Pad36)") (class "Default")
      (node (ref "U16") (pin "36") (pinfunction "PB1/TIM3_CH4/TIM8_CH3N/OTG_HS_ULPI_D2/ETH_MII_RXD3/OTG_HS_INTN/TIM1_CH3N/EVENTOUT/ADC12_IN9_36") (pintype "bidirectional"))
    )
    (net (code "1261") (name "unconnected-(U16A-PB3(JTDO{slash}TRACESWO){slash}JTDO{slash}TRACESWO{slash}SPI3_SCK{slash}I2S3_CK{slash}TIM2_CH2{slash}SPI1_SCK{slash}EVENTOUT-Pad89)") (class "Default")
      (node (ref "U16") (pin "89") (pinfunction "PB3(JTDO/TRACESWO)/JTDO/TRACESWO/SPI3_SCK/I2S3_CK/TIM2_CH2/SPI1_SCK/EVENTOUT_89") (pintype "bidirectional"))
    )
    (net (code "1262") (name "unconnected-(U16A-PB4(NJTRST){slash}NJTRST{slash}SPI3_MISO{slash}TIM3_CH1{slash}SPI1_MISO{slash}I2S3ext_SD{slash}EVENTOUT-Pad90)") (class "Default")
      (node (ref "U16") (pin "90") (pinfunction "PB4(NJTRST)/NJTRST/SPI3_MISO/TIM3_CH1/SPI1_MISO/I2S3ext_SD/EVENTOUT_90") (pintype "bidirectional"))
    )
    (net (code "1263") (name "unconnected-(U16A-PB5{slash}I2C1_SMBA{slash}CAN2_RX{slash}OTG_HS_ULPI_D7{slash}ETH_PPS_OUT{slash}TIM3_CH2{slash}SPI1_MOSI{slash}SPI3_MOSI{slash}DCMI_D10{slash}I2S3_SD{slash}EVENTOUT-Pad91)") (class "Default")
      (node (ref "U16") (pin "91") (pinfunction "PB5/I2C1_SMBA/CAN2_RX/OTG_HS_ULPI_D7/ETH_PPS_OUT/TIM3_CH2/SPI1_MOSI/SPI3_MOSI/DCMI_D10/I2S3_SD/EVENTOUT_91") (pintype "bidirectional"))
    )
    (net (code "1264") (name "unconnected-(U16A-PB6{slash}I2C1_SCL{slash}TIM4_CH1{slash}CAN2_TX{slash}DCMI_D5{slash}USART1_TX{slash}EVENTOUT-Pad92)") (class "Default")
      (node (ref "U16") (pin "92") (pinfunction "PB6/I2C1_SCL/TIM4_CH1/CAN2_TX/DCMI_D5/USART1_TX/EVENTOUT_92") (pintype "bidirectional"))
    )
    (net (code "1265") (name "unconnected-(U16A-PB7{slash}I2C1_SDA{slash}FSMC_NL{slash}DCMI_VSYNC{slash}USART1_RX{slash}TIM4_CH2{slash}EVENTOUT-Pad93)") (class "Default")
      (node (ref "U16") (pin "93") (pinfunction "PB7/I2C1_SDA/FSMC_NL/DCMI_VSYNC/USART1_RX/TIM4_CH2/EVENTOUT_93") (pintype "bidirectional"))
    )
    (net (code "1266") (name "unconnected-(U16A-PB8{slash}TIM4_CH3{slash}SDIO_D4{slash}TIM10_CH1{slash}DCMI_D6{slash}ETH_MII_TXD3{slash}I2C1_SCL{slash}CAN1_RX{slash}EVENTOUT-Pad95)") (class "Default")
      (node (ref "U16") (pin "95") (pinfunction "PB8/TIM4_CH3/SDIO_D4/TIM10_CH1/DCMI_D6/ETH_MII_TXD3/I2C1_SCL/CAN1_RX/EVENTOUT_95") (pintype "bidirectional"))
    )
    (net (code "1267") (name "unconnected-(U16A-PB9{slash}SPI2_NSS{slash}I2S2_WS{slash}TIM4_CH4{slash}TIM11_CH1{slash}SDIO_D5{slash}DCMI_D7{slash}I2C1_SDA{slash}CAN1_TX{slash}EVENTOUT-Pad96)") (class "Default")
      (node (ref "U16") (pin "96") (pinfunction "PB9/SPI2_NSS/I2S2_WS/TIM4_CH4/TIM11_CH1/SDIO_D5/DCMI_D7/I2C1_SDA/CAN1_TX/EVENTOUT_96") (pintype "bidirectional"))
    )
    (net (code "1268") (name "unconnected-(U16A-PB10{slash}SPI2_SCK{slash}I2S2_CK{slash}I2C2_SCL{slash}USART3_TX{slash}OTG_HS_ULPI_D3{slash}ETH_MII_RX_ER{slash}TIM2_CH3{slash}EVENTOUT-Pad47)") (class "Default")
      (node (ref "U16") (pin "47") (pinfunction "PB10/SPI2_SCK/I2S2_CK/I2C2_SCL/USART3_TX/OTG_HS_ULPI_D3/ETH_MII_RX_ER/TIM2_CH3/EVENTOUT_47") (pintype "bidirectional"))
    )
    (net (code "1269") (name "unconnected-(U16A-PB11{slash}I2C2_SDA{slash}USART3_RX{slash}OTG_HS_ULPI_D4{slash}ETH_RMII_TX_EN{slash}ETH_MII_TX_EN{slash}TIM2_CH4{slash}EVENTOUT-Pad48)") (class "Default")
      (node (ref "U16") (pin "48") (pinfunction "PB11/I2C2_SDA/USART3_RX/OTG_HS_ULPI_D4/ETH_RMII_TX_EN/ETH_MII_TX_EN/TIM2_CH4/EVENTOUT_48") (pintype "bidirectional"))
    )
    (net (code "1270") (name "unconnected-(U16A-PB12{slash}SPI2_NSS{slash}I2S2_WS{slash}I2C2_SMBA{slash}USART3_CK{slash}TIM1_BKIN{slash}CAN2_RX{slash}OTG_HS_ULPI_D5{slash}ETH_RMII_TXD0{slash}ETH_MII_TXD0{slash}OTG_HS_ID{slash}EVENTOUT-Pad51)") (class "Default")
      (node (ref "U16") (pin "51") (pinfunction "PB12/SPI2_NSS/I2S2_WS/I2C2_SMBA/USART3_CK/TIM1_BKIN/CAN2_RX/OTG_HS_ULPI_D5/ETH_RMII_TXD0/ETH_MII_TXD0/OTG_HS_ID/EVENTOUT_51") (pintype "bidirectional"))
    )
    (net (code "1271") (name "unconnected-(U16A-PB13{slash}SPI2_SCK{slash}I2S2_CK{slash}USART3_CTS{slash}TIM1_CH1N{slash}CAN2_TX{slash}OTG_HS_ULPI_D6{slash}ETH_RMII_TXD1{slash}ETH_MII_TXD1{slash}EVENTOUT{slash}OTG_HS_VBUS-Pad52)") (class "Default")
      (node (ref "U16") (pin "52") (pinfunction "PB13/SPI2_SCK/I2S2_CK/USART3_CTS/TIM1_CH1N/CAN2_TX/OTG_HS_ULPI_D6/ETH_RMII_TXD1/ETH_MII_TXD1/EVENTOUT/OTG_HS_VBUS_52") (pintype "bidirectional"))
    )
    (net (code "1272") (name "unconnected-(U16A-PB14{slash}SPI2_MISO{slash}TIM1_CH2N{slash}TIM12_CH1{slash}OTG_HS_DM{slash}USART3_RTS{slash}TIM8_CH2N{slash}I2S2ext_SD{slash}EVENTOUT-Pad53)") (class "Default")
      (node (ref "U16") (pin "53") (pinfunction "PB14/SPI2_MISO/TIM1_CH2N/TIM12_CH1/OTG_HS_DM/USART3_RTS/TIM8_CH2N/I2S2ext_SD/EVENTOUT_53") (pintype "bidirectional"))
    )
    (net (code "1273") (name "unconnected-(U16A-PB15{slash}SPI2_MOSI{slash}I2S2_SD{slash}TIM1_CH3N{slash}TIM8_CH3N{slash}TIM12_CH2{slash}OTG_HS_DP{slash}EVENTOUT-Pad54)") (class "Default")
      (node (ref "U16") (pin "54") (pinfunction "PB15/SPI2_MOSI/I2S2_SD/TIM1_CH3N/TIM8_CH3N/TIM12_CH2/OTG_HS_DP/EVENTOUT_54") (pintype "bidirectional"))
    )
    (net (code "1274") (name "unconnected-(U17-SPI_MISO{slash}(HS)PC7-Pad24)") (class "Default")
      (node (ref "U17") (pin "24") (pinfunction "SPI_MISO/(HS)PC7_24") (pintype "bidirectional"))
    )
    (net (code "1275") (name "unconnected-(U17-SPI_MOSI{slash}(HS)PC6-Pad23)") (class "Default")
      (node (ref "U17") (pin "23") (pinfunction "SPI_MOSI/(HS)PC6_23") (pintype "bidirectional"))
    )
    (net (code "1276") (name "unconnected-(U17-SPI_NSS{slash}(HS)PE5-Pad17)") (class "Default")
      (node (ref "U17") (pin "17") (pinfunction "SPI_NSS/(HS)PE5_17") (pintype "bidirectional"))
    )
    (net (code "1277") (name "unconnected-(U17-SPI_SCK{slash}(HS)PC5-Pad22)") (class "Default")
      (node (ref "U17") (pin "22") (pinfunction "SPI_SCK/(HS)PC5_22") (pintype "bidirectional"))
    )
    (net (code "1278") (name "unconnected-(U17-SWIM{slash}(HS)PD1-Pad26)") (class "Default")
      (node (ref "U17") (pin "26") (pinfunction "SWIM/(HS)PD1_26") (pintype "bidirectional"))
    )
    (net (code "1279") (name "unconnected-(U17-TIM1_CH2{slash}(HS)PC2-Pad19)") (class "Default")
      (node (ref "U17") (pin "19") (pinfunction "TIM1_CH2/(HS)PC2_19") (pintype "bidirectional"))
    )
    (net (code "1280") (name "unconnected-(U17-TIM1_CH3{slash}(HS)PC3-Pad20)") (class "Default")
      (node (ref "U17") (pin "20") (pinfunction "TIM1_CH3/(HS)PC3_20") (pintype "bidirectional"))
    )
    (net (code "1281") (name "unconnected-(U17-TIM1_CH4]{slash}TL1[{slash}(HS)PD7-Pad32)") (class "Default")
      (node (ref "U17") (pin "32") (pinfunction "TIM1_CH4]/TL1[/(HS)PD7_32") (pintype "bidirectional"))
    )
    (net (code "1282") (name "unconnected-(U17-TIM1_CH4{slash}(HS)PC4-Pad21)") (class "Default")
      (node (ref "U17") (pin "21") (pinfunction "TIM1_CH4/(HS)PC4_21") (pintype "bidirectional"))
    )
    (net (code "1283") (name "unconnected-(U17-UART1_CK{slash}TIM1_CH1{slash}(HS)PC1-Pad18)") (class "Default")
      (node (ref "U17") (pin "18") (pinfunction "UART1_CK/TIM1_CH1/(HS)PC1_18") (pintype "bidirectional"))
    )
    (net (code "1284") (name "unconnected-(U17-UART2_RX{slash}(HS)_PD6-Pad31)") (class "Default")
      (node (ref "U17") (pin "31") (pinfunction "UART2_RX/(HS)_PD6_31") (pintype "bidirectional"))
    )
    (net (code "1285") (name "unconnected-(U17-UART2_TX{slash}(HS)_PD5-Pad30)") (class "Default")
      (node (ref "U17") (pin "30") (pinfunction "UART2_TX/(HS)_PD5_30") (pintype "bidirectional"))
    )
    (net (code "1286") (name "unconnected-(U17-[ADC_ETR]TIM2_CH2{slash}(HS)PD3-Pad28)") (class "Default")
      (node (ref "U17") (pin "28") (pinfunction "[ADC_ETR]TIM2_CH2/(HS)PD3_28") (pintype "bidirectional"))
    )
    (net (code "1287") (name "unconnected-(U17-[BEEP]TIM2_CH1{slash}(HS)PD4-Pad29)") (class "Default")
      (node (ref "U17") (pin "29") (pinfunction "[BEEP]TIM2_CH1/(HS)PD4_29") (pintype "bidirectional"))
    )
    (net (code "1288") (name "unconnected-(U17-[CLK_CCO][TIM1_BKIN]TIM3_CH2{slash}(HS)PD0-Pad25)") (class "Default")
      (node (ref "U17") (pin "25") (pinfunction "[CLK_CCO][TIM1_BKIN]TIM3_CH2/(HS)PD0_25") (pintype "bidirectional"))
    )
    (net (code "1289") (name "unconnected-(U17-[TIM2_CH3]TIM3_CH1{slash}(HS)PD2-Pad27)") (class "Default")
      (node (ref "U17") (pin "27") (pinfunction "[TIM2_CH3]TIM3_CH1/(HS)PD2_27") (pintype "bidirectional"))
    )
    (net (code "1290") (name "unconnected-(U18-AVCC-Pad64)") (class "Default")
      (node (ref "U18") (pin "64") (pinfunction "AVCC_64") (pintype "passive"))
    )
    (net (code "1291") (name "unconnected-(U18-AVSS-Pad62)") (class "Default")
      (node (ref "U18") (pin "62") (pinfunction "AVSS_62") (pintype "passive"))
    )
    (net (code "1292") (name "unconnected-(U18-DVCC-Pad1)") (class "Default")
      (node (ref "U18") (pin "1") (pinfunction "DVCC_1") (pintype "passive"))
    )
    (net (code "1293") (name "unconnected-(U18-DVSS-Pad63)") (class "Default")
      (node (ref "U18") (pin "63") (pinfunction "DVSS_63") (pintype "passive"))
    )
    (net (code "1294") (name "unconnected-(U18-P1.0{slash}TACLK-Pad12)") (class "Default")
      (node (ref "U18") (pin "12") (pinfunction "P1.0/TACLK_12") (pintype "passive"))
    )
    (net (code "1295") (name "unconnected-(U18-P1.1{slash}TA0-Pad13)") (class "Default")
      (node (ref "U18") (pin "13") (pinfunction "P1.1/TA0_13") (pintype "passive"))
    )
    (net (code "1296") (name "unconnected-(U18-P1.2{slash}TA1-Pad14)") (class "Default")
      (node (ref "U18") (pin "14") (pinfunction "P1.2/TA1_14") (pintype "passive"))
    )
    (net (code "1297") (name "unconnected-(U18-P1.3{slash}TA2-Pad15)") (class "Default")
      (node (ref "U18") (pin "15") (pinfunction "P1.3/TA2_15") (pintype "passive"))
    )
    (net (code "1298") (name "unconnected-(U18-P1.4{slash}SMCLK-Pad16)") (class "Default")
      (node (ref "U18") (pin "16") (pinfunction "P1.4/SMCLK_16") (pintype "passive"))
    )
    (net (code "1299") (name "unconnected-(U18-P1.5{slash}TA0-Pad17)") (class "Default")
      (node (ref "U18") (pin "17") (pinfunction "P1.5/TA0_17") (pintype "passive"))
    )
    (net (code "1300") (name "unconnected-(U18-P1.6{slash}TA1-Pad18)") (class "Default")
      (node (ref "U18") (pin "18") (pinfunction "P1.6/TA1_18") (pintype "passive"))
    )
    (net (code "1301") (name "unconnected-(U18-P1.7TA2-Pad19)") (class "Default")
      (node (ref "U18") (pin "19") (pinfunction "P1.7TA2_19") (pintype "passive"))
    )
    (net (code "1302") (name "unconnected-(U18-P2.0{slash}ACLK-Pad20)") (class "Default")
      (node (ref "U18") (pin "20") (pinfunction "P2.0/ACLK_20") (pintype "passive"))
    )
    (net (code "1303") (name "unconnected-(U18-P2.1{slash}TACLK-Pad21)") (class "Default")
      (node (ref "U18") (pin "21") (pinfunction "P2.1/TACLK_21") (pintype "passive"))
    )
    (net (code "1304") (name "unconnected-(U18-P2.2{slash}CAOUT-Pad22)") (class "Default")
      (node (ref "U18") (pin "22") (pinfunction "P2.2/CAOUT_22") (pintype "passive"))
    )
    (net (code "1305") (name "unconnected-(U18-P2.3{slash}CA0-Pad23)") (class "Default")
      (node (ref "U18") (pin "23") (pinfunction "P2.3/CA0_23") (pintype "passive"))
    )
    (net (code "1306") (name "unconnected-(U18-P2.4{slash}CA1-Pad24)") (class "Default")
      (node (ref "U18") (pin "24") (pinfunction "P2.4/CA1_24") (pintype "passive"))
    )
    (net (code "1307") (name "unconnected-(U18-P2.5{slash}ROSC-Pad25)") (class "Default")
      (node (ref "U18") (pin "25") (pinfunction "P2.5/ROSC_25") (pintype "passive"))
    )
    (net (code "1308") (name "unconnected-(U18-P2.6{slash}ADCLK-Pad26)") (class "Default")
      (node (ref "U18") (pin "26") (pinfunction "P2.6/ADCLK_26") (pintype "passive"))
    )
    (net (code "1309") (name "unconnected-(U18-P2.7{slash}TA0-Pad27)") (class "Default")
      (node (ref "U18") (pin "27") (pinfunction "P2.7/TA0_27") (pintype "passive"))
    )
    (net (code "1310") (name "unconnected-(U18-P3.0{slash}STE0-Pad28)") (class "Default")
      (node (ref "U18") (pin "28") (pinfunction "P3.0/STE0_28") (pintype "passive"))
    )
    (net (code "1311") (name "unconnected-(U18-P3.1{slash}SIMO0-Pad29)") (class "Default")
      (node (ref "U18") (pin "29") (pinfunction "P3.1/SIMO0_29") (pintype "passive"))
    )
    (net (code "1312") (name "unconnected-(U18-P3.2{slash}SOMI0-Pad30)") (class "Default")
      (node (ref "U18") (pin "30") (pinfunction "P3.2/SOMI0_30") (pintype "passive"))
    )
    (net (code "1313") (name "unconnected-(U18-P3.3{slash}ULCK0-Pad31)") (class "Default")
      (node (ref "U18") (pin "31") (pinfunction "P3.3/ULCK0_31") (pintype "passive"))
    )
    (net (code "1314") (name "unconnected-(U18-P3.4{slash}UTXD0-Pad32)") (class "Default")
      (node (ref "U18") (pin "32") (pinfunction "P3.4/UTXD0_32") (pintype "passive"))
    )
    (net (code "1315") (name "unconnected-(U18-P3.5{slash}URXD0-Pad33)") (class "Default")
      (node (ref "U18") (pin "33") (pinfunction "P3.5/URXD0_33") (pintype "passive"))
    )
    (net (code "1316") (name "unconnected-(U18-P3.6{slash}UTXD1-Pad34)") (class "Default")
      (node (ref "U18") (pin "34") (pinfunction "P3.6/UTXD1_34") (pintype "passive"))
    )
    (net (code "1317") (name "unconnected-(U18-P3.7{slash}URXD1-Pad35)") (class "Default")
      (node (ref "U18") (pin "35") (pinfunction "P3.7/URXD1_35") (pintype "passive"))
    )
    (net (code "1318") (name "unconnected-(U18-P4.0{slash}TB0-Pad36)") (class "Default")
      (node (ref "U18") (pin "36") (pinfunction "P4.0/TB0_36") (pintype "passive"))
    )
    (net (code "1319") (name "unconnected-(U18-P4.1{slash}TB1-Pad37)") (class "Default")
      (node (ref "U18") (pin "37") (pinfunction "P4.1/TB1_37") (pintype "passive"))
    )
    (net (code "1320") (name "unconnected-(U18-P4.2{slash}TB2-Pad38)") (class "Default")
      (node (ref "U18") (pin "38") (pinfunction "P4.2/TB2_38") (pintype "passive"))
    )
    (net (code "1321") (name "unconnected-(U18-P4.3{slash}TB3-Pad39)") (class "Default")
      (node (ref "U18") (pin "39") (pinfunction "P4.3/TB3_39") (pintype "passive"))
    )
    (net (code "1322") (name "unconnected-(U18-P4.4{slash}TB4-Pad40)") (class "Default")
      (node (ref "U18") (pin "40") (pinfunction "P4.4/TB4_40") (pintype "passive"))
    )
    (net (code "1323") (name "unconnected-(U18-P4.5{slash}TB5-Pad41)") (class "Default")
      (node (ref "U18") (pin "41") (pinfunction "P4.5/TB5_41") (pintype "passive"))
    )
    (net (code "1324") (name "unconnected-(U18-P4.6{slash}TB6-Pad42)") (class "Default")
      (node (ref "U18") (pin "42") (pinfunction "P4.6/TB6_42") (pintype "passive"))
    )
    (net (code "1325") (name "unconnected-(U18-P4.7{slash}TBCLK-Pad43)") (class "Default")
      (node (ref "U18") (pin "43") (pinfunction "P4.7/TBCLK_43") (pintype "passive"))
    )
    (net (code "1326") (name "unconnected-(U18-P5.0{slash}STE1-Pad44)") (class "Default")
      (node (ref "U18") (pin "44") (pinfunction "P5.0/STE1_44") (pintype "passive"))
    )
    (net (code "1327") (name "unconnected-(U18-P5.1{slash}SIMO1-Pad45)") (class "Default")
      (node (ref "U18") (pin "45") (pinfunction "P5.1/SIMO1_45") (pintype "passive"))
    )
    (net (code "1328") (name "unconnected-(U18-P5.2{slash}SOMI1-Pad46)") (class "Default")
      (node (ref "U18") (pin "46") (pinfunction "P5.2/SOMI1_46") (pintype "passive"))
    )
    (net (code "1329") (name "unconnected-(U18-P5.3{slash}UCLK1-Pad47)") (class "Default")
      (node (ref "U18") (pin "47") (pinfunction "P5.3/UCLK1_47") (pintype "passive"))
    )
    (net (code "1330") (name "unconnected-(U18-P5.4{slash}MCLK-Pad48)") (class "Default")
      (node (ref "U18") (pin "48") (pinfunction "P5.4/MCLK_48") (pintype "passive"))
    )
    (net (code "1331") (name "unconnected-(U18-P5.5{slash}SMCLK-Pad49)") (class "Default")
      (node (ref "U18") (pin "49") (pinfunction "P5.5/SMCLK_49") (pintype "passive"))
    )
    (net (code "1332") (name "unconnected-(U18-P5.6{slash}ACLK-Pad50)") (class "Default")
      (node (ref "U18") (pin "50") (pinfunction "P5.6/ACLK_50") (pintype "passive"))
    )
    (net (code "1333") (name "unconnected-(U18-P5.7{slash}TH-Pad51)") (class "Default")
      (node (ref "U18") (pin "51") (pinfunction "P5.7/TH_51") (pintype "passive"))
    )
    (net (code "1334") (name "unconnected-(U18-P6.0{slash}A0-Pad59)") (class "Default")
      (node (ref "U18") (pin "59") (pinfunction "P6.0/A0_59") (pintype "passive"))
    )
    (net (code "1335") (name "unconnected-(U18-P6.1{slash}A1-Pad60)") (class "Default")
      (node (ref "U18") (pin "60") (pinfunction "P6.1/A1_60") (pintype "passive"))
    )
    (net (code "1336") (name "unconnected-(U18-P6.2{slash}A2-Pad61)") (class "Default")
      (node (ref "U18") (pin "61") (pinfunction "P6.2/A2_61") (pintype "passive"))
    )
    (net (code "1337") (name "unconnected-(U18-P6.3{slash}A3-Pad2)") (class "Default")
      (node (ref "U18") (pin "2") (pinfunction "P6.3/A3_2") (pintype "passive"))
    )
    (net (code "1338") (name "unconnected-(U18-P6.4{slash}A4-Pad3)") (class "Default")
      (node (ref "U18") (pin "3") (pinfunction "P6.4/A4_3") (pintype "passive"))
    )
    (net (code "1339") (name "unconnected-(U18-P6.5{slash}A5-Pad4)") (class "Default")
      (node (ref "U18") (pin "4") (pinfunction "P6.5/A5_4") (pintype "passive"))
    )
    (net (code "1340") (name "unconnected-(U18-P6.6{slash}A6-Pad5)") (class "Default")
      (node (ref "U18") (pin "5") (pinfunction "P6.6/A6_5") (pintype "passive"))
    )
    (net (code "1341") (name "unconnected-(U18-P6.7{slash}A7-Pad6)") (class "Default")
      (node (ref "U18") (pin "6") (pinfunction "P6.7/A7_6") (pintype "passive"))
    )
    (net (code "1342") (name "unconnected-(U18-RST{slash}NMI-Pad58)") (class "Default")
      (node (ref "U18") (pin "58") (pinfunction "RST/NMI_58") (pintype "passive"))
    )
    (net (code "1343") (name "unconnected-(U18-TCK-Pad57)") (class "Default")
      (node (ref "U18") (pin "57") (pinfunction "TCK_57") (pintype "passive"))
    )
    (net (code "1344") (name "unconnected-(U18-TDI-Pad55)") (class "Default")
      (node (ref "U18") (pin "55") (pinfunction "TDI_55") (pintype "passive"))
    )
    (net (code "1345") (name "unconnected-(U18-TDO{slash}TDI-Pad54)") (class "Default")
      (node (ref "U18") (pin "54") (pinfunction "TDO/TDI_54") (pintype "passive"))
    )
    (net (code "1346") (name "unconnected-(U18-TMS-Pad56)") (class "Default")
      (node (ref "U18") (pin "56") (pinfunction "TMS_56") (pintype "passive"))
    )
    (net (code "1347") (name "unconnected-(U18-VEREF+-Pad10)") (class "Default")
      (node (ref "U18") (pin "10") (pinfunction "VEREF+_10") (pintype "passive"))
    )
    (net (code "1348") (name "unconnected-(U18-VREF+-Pad7)") (class "Default")
      (node (ref "U18") (pin "7") (pinfunction "VREF+_7") (pintype "passive"))
    )
    (net (code "1349") (name "unconnected-(U18-VREF--Pad11)") (class "Default")
      (node (ref "U18") (pin "11") (pinfunction "VREF-_11") (pintype "passive"))
    )
    (net (code "1350") (name "unconnected-(U18-XIN-Pad8)") (class "Default")
      (node (ref "U18") (pin "8") (pinfunction "XIN_8") (pintype "passive"))
    )
    (net (code "1351") (name "unconnected-(U18-XOUT{slash}TCLK-Pad9)") (class "Default")
      (node (ref "U18") (pin "9") (pinfunction "XOUT/TCLK_9") (pintype "passive"))
    )
    (net (code "1352") (name "unconnected-(U18-XT2IN-Pad53)") (class "Default")
      (node (ref "U18") (pin "53") (pinfunction "XT2IN_53") (pintype "passive"))
    )
    (net (code "1353") (name "unconnected-(U18-XT2OUT-Pad52)") (class "Default")
      (node (ref "U18") (pin "52") (pinfunction "XT2OUT_52") (pintype "passive"))
    )
    (net (code "1354") (name "unconnected-(U19-ALE-Pad27)") (class "Default")
      (node (ref "U19") (pin "27") (pinfunction "ALE_27") (pintype "passive"))
    )
    (net (code "1355") (name "unconnected-(U19-P0.0-Pad37)") (class "Default")
      (node (ref "U19") (pin "37") (pinfunction "P0.0_37") (pintype "passive"))
    )
    (net (code "1356") (name "unconnected-(U19-P0.1-Pad36)") (class "Default")
      (node (ref "U19") (pin "36") (pinfunction "P0.1_36") (pintype "passive"))
    )
    (net (code "1357") (name "unconnected-(U19-P0.2-Pad35)") (class "Default")
      (node (ref "U19") (pin "35") (pinfunction "P0.2_35") (pintype "passive"))
    )
    (net (code "1358") (name "unconnected-(U19-P0.3-Pad34)") (class "Default")
      (node (ref "U19") (pin "34") (pinfunction "P0.3_34") (pintype "passive"))
    )
    (net (code "1359") (name "unconnected-(U19-P0.4-Pad33)") (class "Default")
      (node (ref "U19") (pin "33") (pinfunction "P0.4_33") (pintype "passive"))
    )
    (net (code "1360") (name "unconnected-(U19-P0.5-Pad32)") (class "Default")
      (node (ref "U19") (pin "32") (pinfunction "P0.5_32") (pintype "passive"))
    )
    (net (code "1361") (name "unconnected-(U19-P0.6-Pad31)") (class "Default")
      (node (ref "U19") (pin "31") (pinfunction "P0.6_31") (pintype "passive"))
    )
    (net (code "1362") (name "unconnected-(U19-P0.7-Pad30)") (class "Default")
      (node (ref "U19") (pin "30") (pinfunction "P0.7_30") (pintype "passive"))
    )
    (net (code "1363") (name "unconnected-(U19-P1.2-Pad42)") (class "Default")
      (node (ref "U19") (pin "42") (pinfunction "P1.2_42") (pintype "passive"))
    )
    (net (code "1364") (name "unconnected-(U19-P1.3-Pad43)") (class "Default")
      (node (ref "U19") (pin "43") (pinfunction "P1.3_43") (pintype "passive"))
    )
    (net (code "1365") (name "unconnected-(U19-P1.4-Pad44)") (class "Default")
      (node (ref "U19") (pin "44") (pinfunction "P1.4_44") (pintype "passive"))
    )
    (net (code "1366") (name "unconnected-(U19-P1.5-Pad1)") (class "Default")
      (node (ref "U19") (pin "1") (pinfunction "P1.5_1") (pintype "passive"))
    )
    (net (code "1367") (name "unconnected-(U19-P1.6-Pad2)") (class "Default")
      (node (ref "U19") (pin "2") (pinfunction "P1.6_2") (pintype "passive"))
    )
    (net (code "1368") (name "unconnected-(U19-P1.7-Pad3)") (class "Default")
      (node (ref "U19") (pin "3") (pinfunction "P1.7_3") (pintype "passive"))
    )
    (net (code "1369") (name "unconnected-(U19-P2.0-Pad18)") (class "Default")
      (node (ref "U19") (pin "18") (pinfunction "P2.0_18") (pintype "passive"))
    )
    (net (code "1370") (name "unconnected-(U19-P2.1-Pad19)") (class "Default")
      (node (ref "U19") (pin "19") (pinfunction "P2.1_19") (pintype "passive"))
    )
    (net (code "1371") (name "unconnected-(U19-P2.2-Pad20)") (class "Default")
      (node (ref "U19") (pin "20") (pinfunction "P2.2_20") (pintype "passive"))
    )
    (net (code "1372") (name "unconnected-(U19-P2.3-Pad21)") (class "Default")
      (node (ref "U19") (pin "21") (pinfunction "P2.3_21") (pintype "passive"))
    )
    (net (code "1373") (name "unconnected-(U19-P2.4-Pad22)") (class "Default")
      (node (ref "U19") (pin "22") (pinfunction "P2.4_22") (pintype "passive"))
    )
    (net (code "1374") (name "unconnected-(U19-P2.5-Pad23)") (class "Default")
      (node (ref "U19") (pin "23") (pinfunction "P2.5_23") (pintype "passive"))
    )
    (net (code "1375") (name "unconnected-(U19-P2.6-Pad24)") (class "Default")
      (node (ref "U19") (pin "24") (pinfunction "P2.6_24") (pintype "passive"))
    )
    (net (code "1376") (name "unconnected-(U19-P2.7-Pad25)") (class "Default")
      (node (ref "U19") (pin "25") (pinfunction "P2.7_25") (pintype "passive"))
    )
    (net (code "1377") (name "unconnected-(U19-P4.0-Pad17)") (class "Default")
      (node (ref "U19") (pin "17") (pinfunction "P4.0_17") (pintype "passive"))
    )
    (net (code "1378") (name "unconnected-(U19-P4.1-Pad28)") (class "Default")
      (node (ref "U19") (pin "28") (pinfunction "P4.1_28") (pintype "passive"))
    )
    (net (code "1379") (name "unconnected-(U19-RES-Pad4)") (class "Default")
      (node (ref "U19") (pin "4") (pinfunction "RES_4") (pintype "passive"))
    )
    (net (code "1380") (name "unconnected-(U19-RxD{slash}P3.0-Pad5)") (class "Default")
      (node (ref "U19") (pin "5") (pinfunction "RxD/P3.0_5") (pintype "passive"))
    )
    (net (code "1381") (name "unconnected-(U19-T0{slash}P3.4-Pad10)") (class "Default")
      (node (ref "U19") (pin "10") (pinfunction "T0/P3.4_10") (pintype "passive"))
    )
    (net (code "1382") (name "unconnected-(U19-T1{slash}P3.5-Pad11)") (class "Default")
      (node (ref "U19") (pin "11") (pinfunction "T1/P3.5_11") (pintype "passive"))
    )
    (net (code "1383") (name "unconnected-(U19-T2EX{slash}P1.1-Pad41)") (class "Default")
      (node (ref "U19") (pin "41") (pinfunction "T2EX/P1.1_41") (pintype "passive"))
    )
    (net (code "1384") (name "unconnected-(U19-T2{slash}P1.0-Pad40)") (class "Default")
      (node (ref "U19") (pin "40") (pinfunction "T2/P1.0_40") (pintype "passive"))
    )
    (net (code "1385") (name "unconnected-(U19-TxD{slash}P3.1-Pad7)") (class "Default")
      (node (ref "U19") (pin "7") (pinfunction "TxD/P3.1_7") (pintype "passive"))
    )
    (net (code "1386") (name "unconnected-(U19-VDD-Pad38)") (class "Default")
      (node (ref "U19") (pin "38") (pinfunction "VDD_38") (pintype "passive"))
    )
    (net (code "1387") (name "unconnected-(U19-VSS-Pad16)") (class "Default")
      (node (ref "U19") (pin "16") (pinfunction "VSS_16") (pintype "passive"))
    )
    (net (code "1388") (name "unconnected-(U19-X0-Pad14)") (class "Default")
      (node (ref "U19") (pin "14") (pinfunction "X0_14") (pintype "passive"))
    )
    (net (code "1389") (name "unconnected-(U19-X1-Pad15)") (class "Default")
      (node (ref "U19") (pin "15") (pinfunction "X1_15") (pintype "passive"))
    )
    (net (code "1390") (name "unconnected-(U19-~{EA}-Pad29)") (class "Default")
      (node (ref "U19") (pin "29") (pinfunction "~{EA}_29") (pintype "passive"))
    )
    (net (code "1391") (name "unconnected-(U19-~{INT0}{slash}P3.2-Pad8)") (class "Default")
      (node (ref "U19") (pin "8") (pinfunction "~{INT0}/P3.2_8") (pintype "passive"))
    )
    (net (code "1392") (name "unconnected-(U19-~{INT1}{slash}P3.3-Pad9)") (class "Default")
      (node (ref "U19") (pin "9") (pinfunction "~{INT1}/P3.3_9") (pintype "passive"))
    )
    (net (code "1393") (name "unconnected-(U19-~{INT2}{slash}P4.3-Pad6)") (class "Default")
      (node (ref "U19") (pin "6") (pinfunction "~{INT2}/P4.3_6") (pintype "passive"))
    )
    (net (code "1394") (name "unconnected-(U19-~{INT3}{slash}P4.2-Pad39)") (class "Default")
      (node (ref "U19") (pin "39") (pinfunction "~{INT3}/P4.2_39") (pintype "passive"))
    )
    (net (code "1395") (name "unconnected-(U19-~{PSEN}-Pad26)") (class "Default")
      (node (ref "U19") (pin "26") (pinfunction "~{PSEN}_26") (pintype "passive"))
    )
    (net (code "1396") (name "unconnected-(U19-~{RD}{slash}P3.7-Pad13)") (class "Default")
      (node (ref "U19") (pin "13") (pinfunction "~{RD}/P3.7_13") (pintype "passive"))
    )
    (net (code "1397") (name "unconnected-(U19-~{WR}{slash}P3.6-Pad12)") (class "Default")
      (node (ref "U19") (pin "12") (pinfunction "~{WR}/P3.6_12") (pintype "passive"))
    )
    (net (code "1398") (name "unconnected-(U20A-PA0-WKUP-Pad10)") (class "Default")
      (node (ref "U20") (pin "10") (pinfunction "PA0-WKUP_10") (pintype "bidirectional"))
    )
    (net (code "1399") (name "unconnected-(U20A-PA1-Pad11)") (class "Default")
      (node (ref "U20") (pin "11") (pinfunction "PA1_11") (pintype "bidirectional"))
    )
    (net (code "1400") (name "unconnected-(U20A-PA2-Pad12)") (class "Default")
      (node (ref "U20") (pin "12") (pinfunction "PA2_12") (pintype "bidirectional"))
    )
    (net (code "1401") (name "unconnected-(U20A-PA3-Pad13)") (class "Default")
      (node (ref "U20") (pin "13") (pinfunction "PA3_13") (pintype "bidirectional"))
    )
    (net (code "1402") (name "unconnected-(U20A-PA4-Pad14)") (class "Default")
      (node (ref "U20") (pin "14") (pinfunction "PA4_14") (pintype "bidirectional"))
    )
    (net (code "1403") (name "unconnected-(U20A-PA5-Pad15)") (class "Default")
      (node (ref "U20") (pin "15") (pinfunction "PA5_15") (pintype "bidirectional"))
    )
    (net (code "1404") (name "unconnected-(U20A-PA6-Pad16)") (class "Default")
      (node (ref "U20") (pin "16") (pinfunction "PA6_16") (pintype "bidirectional"))
    )
    (net (code "1405") (name "unconnected-(U20A-PA7-Pad17)") (class "Default")
      (node (ref "U20") (pin "17") (pinfunction "PA7_17") (pintype "bidirectional"))
    )
    (net (code "1406") (name "unconnected-(U20A-PA8-Pad29)") (class "Default")
      (node (ref "U20") (pin "29") (pinfunction "PA8_29") (pintype "bidirectional"))
    )
    (net (code "1407") (name "unconnected-(U20A-PA9-Pad30)") (class "Default")
      (node (ref "U20") (pin "30") (pinfunction "PA9_30") (pintype "bidirectional"))
    )
    (net (code "1408") (name "unconnected-(U20A-PA10-Pad31)") (class "Default")
      (node (ref "U20") (pin "31") (pinfunction "PA10_31") (pintype "bidirectional"))
    )
    (net (code "1409") (name "unconnected-(U20A-PA11-Pad32)") (class "Default")
      (node (ref "U20") (pin "32") (pinfunction "PA11_32") (pintype "bidirectional"))
    )
    (net (code "1410") (name "unconnected-(U20A-PA12-Pad33)") (class "Default")
      (node (ref "U20") (pin "33") (pinfunction "PA12_33") (pintype "bidirectional"))
    )
    (net (code "1411") (name "unconnected-(U20A-PA13-Pad34)") (class "Default")
      (node (ref "U20") (pin "34") (pinfunction "PA13_34") (pintype "bidirectional"))
    )
    (net (code "1412") (name "unconnected-(U20A-PA14-Pad37)") (class "Default")
      (node (ref "U20") (pin "37") (pinfunction "PA14_37") (pintype "bidirectional"))
    )
    (net (code "1413") (name "unconnected-(U20A-PA15-Pad38)") (class "Default")
      (node (ref "U20") (pin "38") (pinfunction "PA15_38") (pintype "bidirectional"))
    )
    (net (code "1414") (name "unconnected-(U20A-PB4-Pad40)") (class "Default")
      (node (ref "U20") (pin "40") (pinfunction "PB4_40") (pintype "bidirectional"))
    )
    (net (code "1415") (name "unconnected-(U20A-PB12-Pad25)") (class "Default")
      (node (ref "U20") (pin "25") (pinfunction "PB12_25") (pintype "bidirectional"))
    )
    (net (code "1416") (name "unconnected-(U20A-PC13-TAMPER-RTC-Pad2)") (class "Default")
      (node (ref "U20") (pin "2") (pinfunction "PC13-TAMPER-RTC_2") (pintype "bidirectional"))
    )
    (net (code "1417") (name "unconnected-(U20A-PC14-OSC32_IN-Pad3)") (class "Default")
      (node (ref "U20") (pin "3") (pinfunction "PC14-OSC32_IN_3") (pintype "bidirectional"))
    )
    (net (code "1418") (name "unconnected-(U20A-PC15-OSC32_OUT-Pad4)") (class "Default")
      (node (ref "U20") (pin "4") (pinfunction "PC15-OSC32_OUT_4") (pintype "bidirectional"))
    )
    (net (code "1419") (name "unconnected-(U21-BOOT0-Pad44)") (class "Default")
      (node (ref "U21") (pin "44") (pinfunction "BOOT0_44") (pintype "passive"))
    )
    (net (code "1420") (name "unconnected-(U21-NRST-Pad7)") (class "Default")
      (node (ref "U21") (pin "7") (pinfunction "NRST_7") (pintype "passive"))
    )
    (net (code "1421") (name "unconnected-(U21-PA0-Pad10)") (class "Default")
      (node (ref "U21") (pin "10") (pinfunction "PA0_10") (pintype "passive"))
    )
    (net (code "1422") (name "unconnected-(U21-PA1-Pad11)") (class "Default")
      (node (ref "U21") (pin "11") (pinfunction "PA1_11") (pintype "passive"))
    )
    (net (code "1423") (name "unconnected-(U21-PA2-Pad12)") (class "Default")
      (node (ref "U21") (pin "12") (pinfunction "PA2_12") (pintype "passive"))
    )
    (net (code "1424") (name "unconnected-(U21-PA3-Pad13)") (class "Default")
      (node (ref "U21") (pin "13") (pinfunction "PA3_13") (pintype "passive"))
    )
    (net (code "1425") (name "unconnected-(U21-PA4-Pad14)") (class "Default")
      (node (ref "U21") (pin "14") (pinfunction "PA4_14") (pintype "passive"))
    )
    (net (code "1426") (name "unconnected-(U21-PA5-Pad15)") (class "Default")
      (node (ref "U21") (pin "15") (pinfunction "PA5_15") (pintype "passive"))
    )
    (net (code "1427") (name "unconnected-(U21-PA6-Pad16)") (class "Default")
      (node (ref "U21") (pin "16") (pinfunction "PA6_16") (pintype "passive"))
    )
    (net (code "1428") (name "unconnected-(U21-PA7-Pad17)") (class "Default")
      (node (ref "U21") (pin "17") (pinfunction "PA7_17") (pintype "passive"))
    )
    (net (code "1429") (name "unconnected-(U21-PA8-Pad29)") (class "Default")
      (node (ref "U21") (pin "29") (pinfunction "PA8_29") (pintype "passive"))
    )
    (net (code "1430") (name "unconnected-(U21-PA9-Pad30)") (class "Default")
      (node (ref "U21") (pin "30") (pinfunction "PA9_30") (pintype "passive"))
    )
    (net (code "1431") (name "unconnected-(U21-PA10-Pad31)") (class "Default")
      (node (ref "U21") (pin "31") (pinfunction "PA10_31") (pintype "passive"))
    )
    (net (code "1432") (name "unconnected-(U21-PA11-Pad32)") (class "Default")
      (node (ref "U21") (pin "32") (pinfunction "PA11_32") (pintype "passive"))
    )
    (net (code "1433") (name "unconnected-(U21-PA12-Pad33)") (class "Default")
      (node (ref "U21") (pin "33") (pinfunction "PA12_33") (pintype "passive"))
    )
    (net (code "1434") (name "unconnected-(U21-PA13-Pad34)") (class "Default")
      (node (ref "U21") (pin "34") (pinfunction "PA13_34") (pintype "passive"))
    )
    (net (code "1435") (name "unconnected-(U21-PA14-Pad37)") (class "Default")
      (node (ref "U21") (pin "37") (pinfunction "PA14_37") (pintype "passive"))
    )
    (net (code "1436") (name "unconnected-(U21-PA15-Pad38)") (class "Default")
      (node (ref "U21") (pin "38") (pinfunction "PA15_38") (pintype "passive"))
    )
    (net (code "1437") (name "unconnected-(U21-PB0-Pad18)") (class "Default")
      (node (ref "U21") (pin "18") (pinfunction "PB0_18") (pintype "passive"))
    )
    (net (code "1438") (name "unconnected-(U21-PB1-Pad19)") (class "Default")
      (node (ref "U21") (pin "19") (pinfunction "PB1_19") (pintype "passive"))
    )
    (net (code "1439") (name "unconnected-(U21-PB2-Pad20)") (class "Default")
      (node (ref "U21") (pin "20") (pinfunction "PB2_20") (pintype "passive"))
    )
    (net (code "1440") (name "unconnected-(U21-PB3-Pad39)") (class "Default")
      (node (ref "U21") (pin "39") (pinfunction "PB3_39") (pintype "passive"))
    )
    (net (code "1441") (name "unconnected-(U21-PB4-Pad40)") (class "Default")
      (node (ref "U21") (pin "40") (pinfunction "PB4_40") (pintype "passive"))
    )
    (net (code "1442") (name "unconnected-(U21-PB5-Pad41)") (class "Default")
      (node (ref "U21") (pin "41") (pinfunction "PB5_41") (pintype "passive"))
    )
    (net (code "1443") (name "unconnected-(U21-PB6-Pad42)") (class "Default")
      (node (ref "U21") (pin "42") (pinfunction "PB6_42") (pintype "passive"))
    )
    (net (code "1444") (name "unconnected-(U21-PB7-Pad43)") (class "Default")
      (node (ref "U21") (pin "43") (pinfunction "PB7_43") (pintype "passive"))
    )
    (net (code "1445") (name "unconnected-(U21-PB8-Pad45)") (class "Default")
      (node (ref "U21") (pin "45") (pinfunction "PB8_45") (pintype "passive"))
    )
    (net (code "1446") (name "unconnected-(U21-PB9-Pad46)") (class "Default")
      (node (ref "U21") (pin "46") (pinfunction "PB9_46") (pintype "passive"))
    )
    (net (code "1447") (name "unconnected-(U21-PB10-Pad21)") (class "Default")
      (node (ref "U21") (pin "21") (pinfunction "PB10_21") (pintype "passive"))
    )
    (net (code "1448") (name "unconnected-(U21-PB11-Pad22)") (class "Default")
      (node (ref "U21") (pin "22") (pinfunction "PB11_22") (pintype "passive"))
    )
    (net (code "1449") (name "unconnected-(U21-PB12-Pad25)") (class "Default")
      (node (ref "U21") (pin "25") (pinfunction "PB12_25") (pintype "passive"))
    )
    (net (code "1450") (name "unconnected-(U21-PB13-Pad26)") (class "Default")
      (node (ref "U21") (pin "26") (pinfunction "PB13_26") (pintype "passive"))
    )
    (net (code "1451") (name "unconnected-(U21-PB14-Pad27)") (class "Default")
      (node (ref "U21") (pin "27") (pinfunction "PB14_27") (pintype "passive"))
    )
    (net (code "1452") (name "unconnected-(U21-PB15-Pad28)") (class "Default")
      (node (ref "U21") (pin "28") (pinfunction "PB15_28") (pintype "passive"))
    )
    (net (code "1453") (name "unconnected-(U21-PC13-Pad2)") (class "Default")
      (node (ref "U21") (pin "2") (pinfunction "PC13_2") (pintype "passive"))
    )
    (net (code "1454") (name "unconnected-(U21-PC14{slash}OSC32_IN-Pad3)") (class "Default")
      (node (ref "U21") (pin "3") (pinfunction "PC14/OSC32_IN_3") (pintype "passive"))
    )
    (net (code "1455") (name "unconnected-(U21-PC15{slash}OSC32_OUT-Pad4)") (class "Default")
      (node (ref "U21") (pin "4") (pinfunction "PC15/OSC32_OUT_4") (pintype "passive"))
    )
    (net (code "1456") (name "unconnected-(U21-PF0{slash}OSC_IN-Pad5)") (class "Default")
      (node (ref "U21") (pin "5") (pinfunction "PF0/OSC_IN_5") (pintype "passive"))
    )
    (net (code "1457") (name "unconnected-(U21-PF1{slash}OSC_OUT-Pad6)") (class "Default")
      (node (ref "U21") (pin "6") (pinfunction "PF1/OSC_OUT_6") (pintype "passive"))
    )
    (net (code "1458") (name "unconnected-(U21-PF6-Pad35)") (class "Default")
      (node (ref "U21") (pin "35") (pinfunction "PF6_35") (pintype "passive"))
    )
    (net (code "1459") (name "unconnected-(U21-PF7-Pad36)") (class "Default")
      (node (ref "U21") (pin "36") (pinfunction "PF7_36") (pintype "passive"))
    )
    (net (code "1460") (name "unconnected-(U21-VDD-Pad1)") (class "Default")
      (node (ref "U21") (pin "1") (pinfunction "VDD_1") (pintype "passive"))
    )
    (net (code "1461") (name "unconnected-(U21-VDD-Pad24)") (class "Default")
      (node (ref "U21") (pin "24") (pinfunction "VDD_24") (pintype "passive"))
    )
    (net (code "1462") (name "unconnected-(U21-VDD-Pad48)") (class "Default")
      (node (ref "U21") (pin "48") (pinfunction "VDD_48") (pintype "passive"))
    )
    (net (code "1463") (name "unconnected-(U21-VDDA-Pad9)") (class "Default")
      (node (ref "U21") (pin "9") (pinfunction "VDDA_9") (pintype "passive"))
    )
    (net (code "1464") (name "unconnected-(U21-VSS-Pad23)") (class "Default")
      (node (ref "U21") (pin "23") (pinfunction "VSS_23") (pintype "passive"))
    )
    (net (code "1465") (name "unconnected-(U21-VSS-Pad47)") (class "Default")
      (node (ref "U21") (pin "47") (pinfunction "VSS_47") (pintype "passive"))
    )
    (net (code "1466") (name "unconnected-(U21-VSSA-Pad8)") (class "Default")
      (node (ref "U21") (pin "8") (pinfunction "VSSA_8") (pintype "passive"))
    )
    (net (code "1467") (name "unconnected-(U22-ALE-Pad27)") (class "Default")
      (node (ref "U22") (pin "27") (pinfunction "ALE_27") (pintype "passive"))
    )
    (net (code "1468") (name "unconnected-(U22-EX_LVD-Pad29)") (class "Default")
      (node (ref "U22") (pin "29") (pinfunction "EX_LVD_29") (pintype "passive"))
    )
    (net (code "1469") (name "unconnected-(U22-GND-Pad16)") (class "Default")
      (node (ref "U22") (pin "16") (pinfunction "GND_16") (pintype "power_in"))
    )
    (net (code "1470") (name "unconnected-(U22-NA-Pad26)") (class "Default")
      (node (ref "U22") (pin "26") (pinfunction "NA_26") (pintype "passive"))
    )
    (net (code "1471") (name "unconnected-(U22-P0.0-Pad37)") (class "Default")
      (node (ref "U22") (pin "37") (pinfunction "P0.0_37") (pintype "passive"))
    )
    (net (code "1472") (name "unconnected-(U22-P0.1-Pad36)") (class "Default")
      (node (ref "U22") (pin "36") (pinfunction "P0.1_36") (pintype "passive"))
    )
    (net (code "1473") (name "unconnected-(U22-P0.2-Pad35)") (class "Default")
      (node (ref "U22") (pin "35") (pinfunction "P0.2_35") (pintype "passive"))
    )
    (net (code "1474") (name "unconnected-(U22-P0.3-Pad34)") (class "Default")
      (node (ref "U22") (pin "34") (pinfunction "P0.3_34") (pintype "passive"))
    )
    (net (code "1475") (name "unconnected-(U22-P0.4-Pad33)") (class "Default")
      (node (ref "U22") (pin "33") (pinfunction "P0.4_33") (pintype "passive"))
    )
    (net (code "1476") (name "unconnected-(U22-P0.5-Pad32)") (class "Default")
      (node (ref "U22") (pin "32") (pinfunction "P0.5_32") (pintype "passive"))
    )
    (net (code "1477") (name "unconnected-(U22-P0.6-Pad31)") (class "Default")
      (node (ref "U22") (pin "31") (pinfunction "P0.6_31") (pintype "passive"))
    )
    (net (code "1478") (name "unconnected-(U22-P0.7-Pad30)") (class "Default")
      (node (ref "U22") (pin "30") (pinfunction "P0.7_30") (pintype "passive"))
    )
    (net (code "1479") (name "unconnected-(U22-P1.0-Pad40)") (class "Default")
      (node (ref "U22") (pin "40") (pinfunction "P1.0_40") (pintype "passive"))
    )
    (net (code "1480") (name "unconnected-(U22-P1.1-Pad41)") (class "Default")
      (node (ref "U22") (pin "41") (pinfunction "P1.1_41") (pintype "passive"))
    )
    (net (code "1481") (name "unconnected-(U22-P1.2-Pad42)") (class "Default")
      (node (ref "U22") (pin "42") (pinfunction "P1.2_42") (pintype "passive"))
    )
    (net (code "1482") (name "unconnected-(U22-P1.3-Pad43)") (class "Default")
      (node (ref "U22") (pin "43") (pinfunction "P1.3_43") (pintype "passive"))
    )
    (net (code "1483") (name "unconnected-(U22-P1.4-Pad44)") (class "Default")
      (node (ref "U22") (pin "44") (pinfunction "P1.4_44") (pintype "passive"))
    )
    (net (code "1484") (name "unconnected-(U22-P1.5-Pad1)") (class "Default")
      (node (ref "U22") (pin "1") (pinfunction "P1.5_1") (pintype "passive"))
    )
    (net (code "1485") (name "unconnected-(U22-P1.6-Pad2)") (class "Default")
      (node (ref "U22") (pin "2") (pinfunction "P1.6_2") (pintype "passive"))
    )
    (net (code "1486") (name "unconnected-(U22-P1.7-Pad3)") (class "Default")
      (node (ref "U22") (pin "3") (pinfunction "P1.7_3") (pintype "passive"))
    )
    (net (code "1487") (name "unconnected-(U22-P2.0-Pad18)") (class "Default")
      (node (ref "U22") (pin "18") (pinfunction "P2.0_18") (pintype "passive"))
    )
    (net (code "1488") (name "unconnected-(U22-P2.1-Pad19)") (class "Default")
      (node (ref "U22") (pin "19") (pinfunction "P2.1_19") (pintype "passive"))
    )
    (net (code "1489") (name "unconnected-(U22-P2.2-Pad20)") (class "Default")
      (node (ref "U22") (pin "20") (pinfunction "P2.2_20") (pintype "passive"))
    )
    (net (code "1490") (name "unconnected-(U22-P2.3-Pad21)") (class "Default")
      (node (ref "U22") (pin "21") (pinfunction "P2.3_21") (pintype "passive"))
    )
    (net (code "1491") (name "unconnected-(U22-P2.4-Pad22)") (class "Default")
      (node (ref "U22") (pin "22") (pinfunction "P2.4_22") (pintype "passive"))
    )
    (net (code "1492") (name "unconnected-(U22-P2.5-Pad23)") (class "Default")
      (node (ref "U22") (pin "23") (pinfunction "P2.5_23") (pintype "passive"))
    )
    (net (code "1493") (name "unconnected-(U22-P2.6-Pad24)") (class "Default")
      (node (ref "U22") (pin "24") (pinfunction "P2.6_24") (pintype "passive"))
    )
    (net (code "1494") (name "unconnected-(U22-P2.7-Pad25)") (class "Default")
      (node (ref "U22") (pin "25") (pinfunction "P2.7_25") (pintype "passive"))
    )
    (net (code "1495") (name "unconnected-(U22-P3.0{slash}RXD-Pad5)") (class "Default")
      (node (ref "U22") (pin "5") (pinfunction "P3.0/RXD_5") (pintype "passive"))
    )
    (net (code "1496") (name "unconnected-(U22-P3.1{slash}TXD-Pad7)") (class "Default")
      (node (ref "U22") (pin "7") (pinfunction "P3.1/TXD_7") (pintype "passive"))
    )
    (net (code "1497") (name "unconnected-(U22-P3.2-Pad8)") (class "Default")
      (node (ref "U22") (pin "8") (pinfunction "P3.2_8") (pintype "passive"))
    )
    (net (code "1498") (name "unconnected-(U22-P3.3-Pad9)") (class "Default")
      (node (ref "U22") (pin "9") (pinfunction "P3.3_9") (pintype "passive"))
    )
    (net (code "1499") (name "unconnected-(U22-P3.4-Pad10)") (class "Default")
      (node (ref "U22") (pin "10") (pinfunction "P3.4_10") (pintype "passive"))
    )
    (net (code "1500") (name "unconnected-(U22-P3.5-Pad11)") (class "Default")
      (node (ref "U22") (pin "11") (pinfunction "P3.5_11") (pintype "passive"))
    )
    (net (code "1501") (name "unconnected-(U22-P3.6-Pad12)") (class "Default")
      (node (ref "U22") (pin "12") (pinfunction "P3.6_12") (pintype "passive"))
    )
    (net (code "1502") (name "unconnected-(U22-P3.7-Pad13)") (class "Default")
      (node (ref "U22") (pin "13") (pinfunction "P3.7_13") (pintype "passive"))
    )
    (net (code "1503") (name "unconnected-(U22-P4.0-Pad17)") (class "Default")
      (node (ref "U22") (pin "17") (pinfunction "P4.0_17") (pintype "passive"))
    )
    (net (code "1504") (name "unconnected-(U22-P4.1-Pad28)") (class "Default")
      (node (ref "U22") (pin "28") (pinfunction "P4.1_28") (pintype "passive"))
    )
    (net (code "1505") (name "unconnected-(U22-P4.2-Pad39)") (class "Default")
      (node (ref "U22") (pin "39") (pinfunction "P4.2_39") (pintype "passive"))
    )
    (net (code "1506") (name "unconnected-(U22-P4.3-Pad6)") (class "Default")
      (node (ref "U22") (pin "6") (pinfunction "P4.3_6") (pintype "passive"))
    )
    (net (code "1507") (name "unconnected-(U22-RST-Pad4)") (class "Default")
      (node (ref "U22") (pin "4") (pinfunction "RST_4") (pintype "passive"))
    )
    (net (code "1508") (name "unconnected-(U22-VCC-Pad38)") (class "Default")
      (node (ref "U22") (pin "38") (pinfunction "VCC_38") (pintype "power_in"))
    )
    (net (code "1509") (name "unconnected-(U22-XTAL1-Pad15)") (class "Default")
      (node (ref "U22") (pin "15") (pinfunction "XTAL1_15") (pintype "passive"))
    )
    (net (code "1510") (name "unconnected-(U22-XTAL2-Pad14)") (class "Default")
      (node (ref "U22") (pin "14") (pinfunction "XTAL2_14") (pintype "passive"))
    )
    (net (code "1511") (name "unconnected-(U23A-BOOT0-Pad44)") (class "Default")
      (node (ref "U23") (pin "44") (pinfunction "BOOT0_44") (pintype "input"))
    )
    (net (code "1512") (name "unconnected-(U23A-PA0-WKUP-Pad10)") (class "Default")
      (node (ref "U23") (pin "10") (pinfunction "PA0-WKUP_10") (pintype "bidirectional"))
    )
    (net (code "1513") (name "unconnected-(U23A-PA1-Pad11)") (class "Default")
      (node (ref "U23") (pin "11") (pinfunction "PA1_11") (pintype "bidirectional"))
    )
    (net (code "1514") (name "unconnected-(U23A-PA2-Pad12)") (class "Default")
      (node (ref "U23") (pin "12") (pinfunction "PA2_12") (pintype "bidirectional"))
    )
    (net (code "1515") (name "unconnected-(U23A-PA3-Pad13)") (class "Default")
      (node (ref "U23") (pin "13") (pinfunction "PA3_13") (pintype "bidirectional"))
    )
    (net (code "1516") (name "unconnected-(U23A-PA4-Pad14)") (class "Default")
      (node (ref "U23") (pin "14") (pinfunction "PA4_14") (pintype "bidirectional"))
    )
    (net (code "1517") (name "unconnected-(U23A-PA5-Pad15)") (class "Default")
      (node (ref "U23") (pin "15") (pinfunction "PA5_15") (pintype "bidirectional"))
    )
    (net (code "1518") (name "unconnected-(U23A-PA6-Pad16)") (class "Default")
      (node (ref "U23") (pin "16") (pinfunction "PA6_16") (pintype "bidirectional"))
    )
    (net (code "1519") (name "unconnected-(U23A-PA7-Pad17)") (class "Default")
      (node (ref "U23") (pin "17") (pinfunction "PA7_17") (pintype "bidirectional"))
    )
    (net (code "1520") (name "unconnected-(U23A-PA8-Pad29)") (class "Default")
      (node (ref "U23") (pin "29") (pinfunction "PA8_29") (pintype "bidirectional"))
    )
    (net (code "1521") (name "unconnected-(U23A-PA9-Pad30)") (class "Default")
      (node (ref "U23") (pin "30") (pinfunction "PA9_30") (pintype "bidirectional"))
    )
    (net (code "1522") (name "unconnected-(U23A-PA10-Pad31)") (class "Default")
      (node (ref "U23") (pin "31") (pinfunction "PA10_31") (pintype "bidirectional"))
    )
    (net (code "1523") (name "unconnected-(U23A-PA11-Pad32)") (class "Default")
      (node (ref "U23") (pin "32") (pinfunction "PA11_32") (pintype "bidirectional"))
    )
    (net (code "1524") (name "unconnected-(U23A-PA12-Pad33)") (class "Default")
      (node (ref "U23") (pin "33") (pinfunction "PA12_33") (pintype "bidirectional"))
    )
    (net (code "1525") (name "unconnected-(U23A-PA13-Pad34)") (class "Default")
      (node (ref "U23") (pin "34") (pinfunction "PA13_34") (pintype "bidirectional"))
    )
    (net (code "1526") (name "unconnected-(U23A-PA14-Pad37)") (class "Default")
      (node (ref "U23") (pin "37") (pinfunction "PA14_37") (pintype "bidirectional"))
    )
    (net (code "1527") (name "unconnected-(U23A-PA15-Pad38)") (class "Default")
      (node (ref "U23") (pin "38") (pinfunction "PA15_38") (pintype "bidirectional"))
    )
    (net (code "1528") (name "unconnected-(U23A-PB3-Pad39)") (class "Default")
      (node (ref "U23") (pin "39") (pinfunction "PB3_39") (pintype "bidirectional"))
    )
    (net (code "1529") (name "unconnected-(U23A-PB11-Pad22)") (class "Default")
      (node (ref "U23") (pin "22") (pinfunction "PB11_22") (pintype "bidirectional"))
    )
    (net (code "1530") (name "unconnected-(U23A-PC13-TAMPER-RTC-Pad2)") (class "Default")
      (node (ref "U23") (pin "2") (pinfunction "PC13-TAMPER-RTC_2") (pintype "bidirectional"))
    )
    (net (code "1531") (name "unconnected-(U23A-PC14-OSC32_IN-Pad3)") (class "Default")
      (node (ref "U23") (pin "3") (pinfunction "PC14-OSC32_IN_3") (pintype "bidirectional"))
    )
    (net (code "1532") (name "unconnected-(U23A-PC15-OSC32_OUT-Pad4)") (class "Default")
      (node (ref "U23") (pin "4") (pinfunction "PC15-OSC32_OUT_4") (pintype "bidirectional"))
    )
    (net (code "1533") (name "unconnected-(U24A-PA0-WKUP1-Pad10)") (class "Default")
      (node (ref "U24") (pin "10") (pinfunction "PA0-WKUP1_10") (pintype "bidirectional"))
    )
    (net (code "1534") (name "unconnected-(U24A-PA1-Pad11)") (class "Default")
      (node (ref "U24") (pin "11") (pinfunction "PA1_11") (pintype "bidirectional"))
    )
    (net (code "1535") (name "unconnected-(U24A-PA2-Pad12)") (class "Default")
      (node (ref "U24") (pin "12") (pinfunction "PA2_12") (pintype "bidirectional"))
    )
    (net (code "1536") (name "unconnected-(U24A-PA3-Pad13)") (class "Default")
      (node (ref "U24") (pin "13") (pinfunction "PA3_13") (pintype "bidirectional"))
    )
    (net (code "1537") (name "unconnected-(U24A-PA4-Pad14)") (class "Default")
      (node (ref "U24") (pin "14") (pinfunction "PA4_14") (pintype "bidirectional"))
    )
    (net (code "1538") (name "unconnected-(U24A-PA5-Pad15)") (class "Default")
      (node (ref "U24") (pin "15") (pinfunction "PA5_15") (pintype "bidirectional"))
    )
    (net (code "1539") (name "unconnected-(U24A-PA6-Pad16)") (class "Default")
      (node (ref "U24") (pin "16") (pinfunction "PA6_16") (pintype "bidirectional"))
    )
    (net (code "1540") (name "unconnected-(U24A-PA7-Pad17)") (class "Default")
      (node (ref "U24") (pin "17") (pinfunction "PA7_17") (pintype "bidirectional"))
    )
    (net (code "1541") (name "unconnected-(U24A-PA8-Pad29)") (class "Default")
      (node (ref "U24") (pin "29") (pinfunction "PA8_29") (pintype "bidirectional"))
    )
    (net (code "1542") (name "unconnected-(U24A-PA9-Pad30)") (class "Default")
      (node (ref "U24") (pin "30") (pinfunction "PA9_30") (pintype "bidirectional"))
    )
    (net (code "1543") (name "unconnected-(U24A-PA10-Pad31)") (class "Default")
      (node (ref "U24") (pin "31") (pinfunction "PA10_31") (pintype "bidirectional"))
    )
    (net (code "1544") (name "unconnected-(U24A-PA11-Pad32)") (class "Default")
      (node (ref "U24") (pin "32") (pinfunction "PA11_32") (pintype "bidirectional"))
    )
    (net (code "1545") (name "unconnected-(U24A-PA12-Pad33)") (class "Default")
      (node (ref "U24") (pin "33") (pinfunction "PA12_33") (pintype "bidirectional"))
    )
    (net (code "1546") (name "unconnected-(U24A-PA13-Pad34)") (class "Default")
      (node (ref "U24") (pin "34") (pinfunction "PA13_34") (pintype "bidirectional"))
    )
    (net (code "1547") (name "unconnected-(U24A-PA14-Pad37)") (class "Default")
      (node (ref "U24") (pin "37") (pinfunction "PA14_37") (pintype "bidirectional"))
    )
    (net (code "1548") (name "unconnected-(U24A-PA15-Pad38)") (class "Default")
      (node (ref "U24") (pin "38") (pinfunction "PA15_38") (pintype "bidirectional"))
    )
    (net (code "1549") (name "unconnected-(U24A-PB3-Pad39)") (class "Default")
      (node (ref "U24") (pin "39") (pinfunction "PB3_39") (pintype "bidirectional"))
    )
    (net (code "1550") (name "unconnected-(U24A-PC13-RTC_AF1-WKUP2-Pad2)") (class "Default")
      (node (ref "U24") (pin "2") (pinfunction "PC13-RTC_AF1-WKUP2_2") (pintype "bidirectional"))
    )
    (net (code "1551") (name "unconnected-(U24A-PC14-OSC32_IN-Pad3)") (class "Default")
      (node (ref "U24") (pin "3") (pinfunction "PC14-OSC32_IN_3") (pintype "bidirectional"))
    )
    (net (code "1552") (name "unconnected-(U24A-PC15-OSC32_OUT-Pad4)") (class "Default")
      (node (ref "U24") (pin "4") (pinfunction "PC15-OSC32_OUT_4") (pintype "bidirectional"))
    )
    (net (code "1553") (name "unconnected-(U25-NRST{slash}PA1-Pad4)") (class "Default")
      (node (ref "U25") (pin "4") (pinfunction "NRST/PA1_4") (pintype "bidirectional"))
    )
    (net (code "1554") (name "unconnected-(U25-PA0{slash}SWIM{slash}BEEP{slash}IR_TIM-Pad3)") (class "Default")
      (node (ref "U25") (pin "3") (pinfunction "PA0/SWIM/BEEP/IR_TIM_3") (pintype "bidirectional"))
    )
    (net (code "1555") (name "unconnected-(U25-PA2-Pad5)") (class "Default")
      (node (ref "U25") (pin "5") (pinfunction "PA2_5") (pintype "bidirectional"))
    )
    (net (code "1556") (name "unconnected-(U25-PA3-Pad6)") (class "Default")
      (node (ref "U25") (pin "6") (pinfunction "PA3_6") (pintype "bidirectional"))
    )
    (net (code "1557") (name "unconnected-(U25-PB0{slash}TIM2_CH1{slash}COMP1_CH1-Pad10)") (class "Default")
      (node (ref "U25") (pin "10") (pinfunction "PB0/TIM2_CH1/COMP1_CH1_10") (pintype "bidirectional"))
    )
    (net (code "1558") (name "unconnected-(U25-PB1{slash}TIM3_CH1{slash}COMP1_CH2-Pad11)") (class "Default")
      (node (ref "U25") (pin "11") (pinfunction "PB1/TIM3_CH1/COMP1_CH2_11") (pintype "bidirectional"))
    )
    (net (code "1559") (name "unconnected-(U25-PB2{slash}TIM2_CH2{slash}COMP2_CH1-Pad12)") (class "Default")
      (node (ref "U25") (pin "12") (pinfunction "PB2/TIM2_CH2/COMP2_CH1_12") (pintype "bidirectional"))
    )
    (net (code "1560") (name "unconnected-(U25-PB3{slash}TIM2_TRIG{slash}COMP2_CH2-Pad13)") (class "Default")
      (node (ref "U25") (pin "13") (pinfunction "PB3/TIM2_TRIG/COMP2_CH2_13") (pintype "bidirectional"))
    )
    (net (code "1561") (name "unconnected-(U25-PB4{slash}SPI_NSS-Pad14)") (class "Default")
      (node (ref "U25") (pin "14") (pinfunction "PB4/SPI_NSS_14") (pintype "bidirectional"))
    )
    (net (code "1562") (name "unconnected-(U25-PB5{slash}SPI_SCK-Pad15)") (class "Default")
      (node (ref "U25") (pin "15") (pinfunction "PB5/SPI_SCK_15") (pintype "bidirectional"))
    )
    (net (code "1563") (name "unconnected-(U25-PB6{slash}SPI_MOSI-Pad16)") (class "Default")
      (node (ref "U25") (pin "16") (pinfunction "PB6/SPI_MOSI_16") (pintype "bidirectional"))
    )
    (net (code "1564") (name "unconnected-(U25-PB7{slash}SPI_MISO-Pad17)") (class "Default")
      (node (ref "U25") (pin "17") (pinfunction "PB7/SPI_MISO_17") (pintype "bidirectional"))
    )
    (net (code "1565") (name "unconnected-(U25-PC1{slash}I2C_SCL-Pad19)") (class "Default")
      (node (ref "U25") (pin "19") (pinfunction "PC1/I2C_SCL_19") (pintype "bidirectional"))
    )
    (net (code "1566") (name "unconnected-(U25-PC2{slash}USART_RX-Pad20)") (class "Default")
      (node (ref "U25") (pin "20") (pinfunction "PC2/USART_RX_20") (pintype "bidirectional"))
    )
    (net (code "1567") (name "unconnected-(U25-PC3{slash}USART_TX-Pad1)") (class "Default")
      (node (ref "U25") (pin "1") (pinfunction "PC3/USART_TX_1") (pintype "bidirectional"))
    )
    (net (code "1568") (name "unconnected-(U25-PC4{slash}USART_CK{slash}CCO-Pad2)") (class "Default")
      (node (ref "U25") (pin "2") (pinfunction "PC4/USART_CK/CCO_2") (pintype "bidirectional"))
    )
    (net (code "1569") (name "unconnected-(U25-PD0{slash}TIM3_CH2{slash}COMP1_CH3-Pad9)") (class "Default")
      (node (ref "U25") (pin "9") (pinfunction "PD0/TIM3_CH2/COMP1_CH3_9") (pintype "bidirectional"))
    )
    (net (code "1570") (name "unconnected-(U25-VDD-Pad8)") (class "Default")
      (node (ref "U25") (pin "8") (pinfunction "VDD_8") (pintype "power_in"))
    )
    (net (code "1571") (name "unconnected-(U25-VSS-Pad7)") (class "Default")
      (node (ref "U25") (pin "7") (pinfunction "VSS_7") (pintype "power_in"))
    )
    (net (code "1572") (name "unconnected-(U26-BOOT0-Pad1)") (class "Default")
      (node (ref "U26") (pin "1") (pinfunction "BOOT0_1") (pintype "passive"))
    )
    (net (code "1573") (name "unconnected-(U26-NRST-Pad4)") (class "Default")
      (node (ref "U26") (pin "4") (pinfunction "NRST_4") (pintype "passive"))
    )
    (net (code "1574") (name "unconnected-(U26-PA0-Pad6)") (class "Default")
      (node (ref "U26") (pin "6") (pinfunction "PA0_6") (pintype "passive"))
    )
    (net (code "1575") (name "unconnected-(U26-PA1-Pad7)") (class "Default")
      (node (ref "U26") (pin "7") (pinfunction "PA1_7") (pintype "passive"))
    )
    (net (code "1576") (name "unconnected-(U26-PA2-Pad8)") (class "Default")
      (node (ref "U26") (pin "8") (pinfunction "PA2_8") (pintype "passive"))
    )
    (net (code "1577") (name "unconnected-(U26-PA3-Pad9)") (class "Default")
      (node (ref "U26") (pin "9") (pinfunction "PA3_9") (pintype "passive"))
    )
    (net (code "1578") (name "unconnected-(U26-PA4-Pad10)") (class "Default")
      (node (ref "U26") (pin "10") (pinfunction "PA4_10") (pintype "passive"))
    )
    (net (code "1579") (name "unconnected-(U26-PA13-Pad19)") (class "Default")
      (node (ref "U26") (pin "19") (pinfunction "PA13_19") (pintype "passive"))
    )
    (net (code "1580") (name "unconnected-(U26-PF0{slash}OSC_IN-Pad2)") (class "Default")
      (node (ref "U26") (pin "2") (pinfunction "PF0/OSC_IN_2") (pintype "passive"))
    )
    (net (code "1581") (name "unconnected-(U26-PF1{slash}OSC_OUT-Pad3)") (class "Default")
      (node (ref "U26") (pin "3") (pinfunction "PF1/OSC_OUT_3") (pintype "passive"))
    )
    (net (code "1582") (name "unconnected-(U26-VDDA-Pad5)") (class "Default")
      (node (ref "U26") (pin "5") (pinfunction "VDDA_5") (pintype "passive"))
    )
    (net (code "1583") (name "unconnected-(U27A-PA0-WKUP(PA0){slash}USART2_CTS{slash}UART4_TX{slash}ETH_MII_CRS{slash}TIM2_CH1_ETR{slash}TIM5_CH1{slash}TIM8_ETR{slash}EVENTOUT{slash}ADC123_IN0{slash}WKUP-Pad23)") (class "Default")
      (node (ref "U27") (pin "23") (pinfunction "PA0-WKUP(PA0)/USART2_CTS/UART4_TX/ETH_MII_CRS/TIM2_CH1_ETR/TIM5_CH1/TIM8_ETR/EVENTOUT/ADC123_IN0/WKUP_23") (pintype "bidirectional"))
    )
    (net (code "1584") (name "unconnected-(U27A-PA1{slash}USART2_RTS{slash}UART4_RX{slash}ETH_RMII_REF_CLK{slash}ETH_MII_RX_CLK{slash}TIM5_CH2{slash}TIM2_CH2{slash}EVENTOUT{slash}ADC123_IN1-Pad24)") (class "Default")
      (node (ref "U27") (pin "24") (pinfunction "PA1/USART2_RTS/UART4_RX/ETH_RMII_REF_CLK/ETH_MII_RX_CLK/TIM5_CH2/TIM2_CH2/EVENTOUT/ADC123_IN1_24") (pintype "bidirectional"))
    )
    (net (code "1585") (name "unconnected-(U27A-PA2{slash}USART2_TX{slash}TIM5_CH3{slash}TIM9_CH1{slash}TIM2_CH3{slash}ETH_MDIO{slash}EVENTOUT{slash}ADC123_IN2-Pad25)") (class "Default")
      (node (ref "U27") (pin "25") (pinfunction "PA2/USART2_TX/TIM5_CH3/TIM9_CH1/TIM2_CH3/ETH_MDIO/EVENTOUT/ADC123_IN2_25") (pintype "bidirectional"))
    )
    (net (code "1586") (name "unconnected-(U27A-PA3{slash}USART2_RX{slash}TIM5_CH4{slash}TIM9_CH2{slash}TIM2_CH4{slash}OTG_HS_ULPI_D0{slash}ETH_MII_COL{slash}EVENTOUT{slash}ADC123_IN3-Pad26)") (class "Default")
      (node (ref "U27") (pin "26") (pinfunction "PA3/USART2_RX/TIM5_CH4/TIM9_CH2/TIM2_CH4/OTG_HS_ULPI_D0/ETH_MII_COL/EVENTOUT/ADC123_IN3_26") (pintype "bidirectional"))
    )
    (net (code "1587") (name "unconnected-(U27A-PA4{slash}SPI1_NSS{slash}SPI3_NSS{slash}USART2_CK{slash}DCMI_HSYNC{slash}OTG_HS_SOF{slash}I2S3_WS{slash}EVENTOUT{slash}ADC12_IN4{slash}DAC1_OUT-Pad29)") (class "Default")
      (node (ref "U27") (pin "29") (pinfunction "PA4/SPI1_NSS/SPI3_NSS/USART2_CK/DCMI_HSYNC/OTG_HS_SOF/I2S3_WS/EVENTOUT/ADC12_IN4/DAC1_OUT_29") (pintype "bidirectional"))
    )
    (net (code "1588") (name "unconnected-(U27A-PA5{slash}SPI1_SCK{slash}OTG_HS_ULPI_CK{slash}TIM2_CH1_ETR{slash}TIM8_CHIN{slash}EVENTOUT{slash}ADC12_IN5{slash}DAC2_OUT-Pad30)") (class "Default")
      (node (ref "U27") (pin "30") (pinfunction "PA5/SPI1_SCK/OTG_HS_ULPI_CK/TIM2_CH1_ETR/TIM8_CHIN/EVENTOUT/ADC12_IN5/DAC2_OUT_30") (pintype "bidirectional"))
    )
    (net (code "1589") (name "unconnected-(U27A-PA6{slash}SPI1_MISO{slash}TIM8_BKIN{slash}TIM13_CH1{slash}DCMI_PIXCLK{slash}TIM3_CH1{slash}TIM1_BKIN{slash}EVENTOUT{slash}ADC12_IN6-Pad31)") (class "Default")
      (node (ref "U27") (pin "31") (pinfunction "PA6/SPI1_MISO/TIM8_BKIN/TIM13_CH1/DCMI_PIXCLK/TIM3_CH1/TIM1_BKIN/EVENTOUT/ADC12_IN6_31") (pintype "bidirectional"))
    )
    (net (code "1590") (name "unconnected-(U27A-PA7{slash}SPI1_MOSI{slash}TIM8_CH1N{slash}TIM14_CH1{slash}TIM3_CH2{slash}ETH_MII_RX_DV{slash}TIM1_CH1N{slash}RMII_CRS_DV{slash}EVENTOUT{slash}ADC12_IN7-Pad32)") (class "Default")
      (node (ref "U27") (pin "32") (pinfunction "PA7/SPI1_MOSI/TIM8_CH1N/TIM14_CH1/TIM3_CH2/ETH_MII_RX_DV/TIM1_CH1N/RMII_CRS_DV/EVENTOUT/ADC12_IN7_32") (pintype "bidirectional"))
    )
    (net (code "1591") (name "unconnected-(U27A-PA8{slash}MCO1{slash}USART1_CK{slash}TIM1_CH1{slash}I2C3_SCL{slash}OTG_FS_SOF{slash}EVENTOUT-Pad67)") (class "Default")
      (node (ref "U27") (pin "67") (pinfunction "PA8/MCO1/USART1_CK/TIM1_CH1/I2C3_SCL/OTG_FS_SOF/EVENTOUT_67") (pintype "bidirectional"))
    )
    (net (code "1592") (name "unconnected-(U27A-PA9{slash}USART1_TX{slash}TIM1_CH2{slash}I2C3_SMBA{slash}DCMI_D0{slash}EVENTOUT{slash}OTG_FS_VBUS-Pad68)") (class "Default")
      (node (ref "U27") (pin "68") (pinfunction "PA9/USART1_TX/TIM1_CH2/I2C3_SMBA/DCMI_D0/EVENTOUT/OTG_FS_VBUS_68") (pintype "bidirectional"))
    )
    (net (code "1593") (name "unconnected-(U27A-PA10{slash}USART1_RX{slash}TIM1_CH3{slash}OTG_FS_ID{slash}DCMI_D1{slash}EVENTOUT-Pad69)") (class "Default")
      (node (ref "U27") (pin "69") (pinfunction "PA10/USART1_RX/TIM1_CH3/OTG_FS_ID/DCMI_D1/EVENTOUT_69") (pintype "bidirectional"))
    )
    (net (code "1594") (name "unconnected-(U27A-PA11{slash}USART1_CTS{slash}CAN1_RX{slash}TIM1_CH4{slash}OTG_FS_DM{slash}EVENTOUT-Pad70)") (class "Default")
      (node (ref "U27") (pin "70") (pinfunction "PA11/USART1_CTS/CAN1_RX/TIM1_CH4/OTG_FS_DM/EVENTOUT_70") (pintype "bidirectional"))
    )
    (net (code "1595") (name "unconnected-(U27A-PA12{slash}USART1_RTS{slash}CAN1_TX{slash}TIM1_ETR{slash}OTG_FS_DP{slash}EVENTOUT-Pad71)") (class "Default")
      (node (ref "U27") (pin "71") (pinfunction "PA12/USART1_RTS/CAN1_TX/TIM1_ETR/OTG_FS_DP/EVENTOUT_71") (pintype "bidirectional"))
    )
    (net (code "1596") (name "unconnected-(U27A-PB0{slash}TIM3_CH3{slash}TIM8_CH2N{slash}OTG_HS_ULPI_D1{slash}ETH_MII_RXD2{slash}TIM1_CH2N{slash}EVENTOUT{slash}ADC12_IN8-Pad35)") (class "Default")
      (node (ref "U27") (pin "35") (pinfunction "PB0/TIM3_CH3/TIM8_CH2N/OTG_HS_ULPI_D1/ETH_MII_RXD2/TIM1_CH2N/EVENTOUT/ADC12_IN8_35") (pintype "bidirectional"))
    )
    (net (code "1597") (name "unconnected-(U27A-PB1{slash}TIM3_CH4{slash}TIM8_CH3N{slash}OTG_HS_ULPI_D2{slash}ETH_MII_RXD3{slash}OTG_HS_INTN{slash}TIM1_CH3N{slash}EVENTOUT{slash}ADC12_IN9-Pad36)") (class "Default")
      (node (ref "U27") (pin "36") (pinfunction "PB1/TIM3_CH4/TIM8_CH3N/OTG_HS_ULPI_D2/ETH_MII_RXD3/OTG_HS_INTN/TIM1_CH3N/EVENTOUT/ADC12_IN9_36") (pintype "bidirectional"))
    )
    (net (code "1598") (name "unconnected-(U27A-PB2-BOOT1(PB2){slash}EVENTOUT-Pad37)") (class "Default")
      (node (ref "U27") (pin "37") (pinfunction "PB2-BOOT1(PB2)/EVENTOUT_37") (pintype "bidirectional"))
    )
    (net (code "1599") (name "unconnected-(U27A-PB3(JTDO{slash}TRACESWO){slash}JTDO{slash}TRACESWO{slash}SPI3_SCK{slash}I2S3_CK{slash}TIM2_CH2{slash}SPI1_SCK{slash}EVENTOUT-Pad89)") (class "Default")
      (node (ref "U27") (pin "89") (pinfunction "PB3(JTDO/TRACESWO)/JTDO/TRACESWO/SPI3_SCK/I2S3_CK/TIM2_CH2/SPI1_SCK/EVENTOUT_89") (pintype "bidirectional"))
    )
    (net (code "1600") (name "unconnected-(U27A-PB4(NJTRST){slash}NJTRST{slash}SPI3_MISO{slash}TIM3_CH1{slash}SPI1_MISO{slash}I2S3ext_SD{slash}EVENTOUT-Pad90)") (class "Default")
      (node (ref "U27") (pin "90") (pinfunction "PB4(NJTRST)/NJTRST/SPI3_MISO/TIM3_CH1/SPI1_MISO/I2S3ext_SD/EVENTOUT_90") (pintype "bidirectional"))
    )
    (net (code "1601") (name "unconnected-(U27A-PB5{slash}I2C1_SMBA{slash}CAN2_RX{slash}OTG_HS_ULPI_D7{slash}ETH_PPS_OUT{slash}TIM3_CH2{slash}SPI1_MOSI{slash}SPI3_MOSI{slash}DCMI_D10{slash}I2S3_SD{slash}EVENTOUT-Pad91)") (class "Default")
      (node (ref "U27") (pin "91") (pinfunction "PB5/I2C1_SMBA/CAN2_RX/OTG_HS_ULPI_D7/ETH_PPS_OUT/TIM3_CH2/SPI1_MOSI/SPI3_MOSI/DCMI_D10/I2S3_SD/EVENTOUT_91") (pintype "bidirectional"))
    )
    (net (code "1602") (name "unconnected-(U27A-PB6{slash}I2C1_SCL{slash}TIM4_CH1{slash}CAN2_TX{slash}DCMI_D5{slash}USART1_TX{slash}EVENTOUT-Pad92)") (class "Default")
      (node (ref "U27") (pin "92") (pinfunction "PB6/I2C1_SCL/TIM4_CH1/CAN2_TX/DCMI_D5/USART1_TX/EVENTOUT_92") (pintype "bidirectional"))
    )
    (net (code "1603") (name "unconnected-(U27A-PB7{slash}I2C1_SDA{slash}FSMC_NL{slash}DCMI_VSYNC{slash}USART1_RX{slash}TIM4_CH2{slash}EVENTOUT-Pad93)") (class "Default")
      (node (ref "U27") (pin "93") (pinfunction "PB7/I2C1_SDA/FSMC_NL/DCMI_VSYNC/USART1_RX/TIM4_CH2/EVENTOUT_93") (pintype "bidirectional"))
    )
    (net (code "1604") (name "unconnected-(U27A-PB8{slash}TIM4_CH3{slash}SDIO_D4{slash}TIM10_CH1{slash}DCMI_D6{slash}ETH_MII_TXD3{slash}I2C1_SCL{slash}CAN1_RX{slash}EVENTOUT-Pad95)") (class "Default")
      (node (ref "U27") (pin "95") (pinfunction "PB8/TIM4_CH3/SDIO_D4/TIM10_CH1/DCMI_D6/ETH_MII_TXD3/I2C1_SCL/CAN1_RX/EVENTOUT_95") (pintype "bidirectional"))
    )
    (net (code "1605") (name "unconnected-(U27A-PB9{slash}SPI2_NSS{slash}I2S2_WS{slash}TIM4_CH4{slash}TIM11_CH1{slash}SDIO_D5{slash}DCMI_D7{slash}I2C1_SDA{slash}CAN1_TX{slash}EVENTOUT-Pad96)") (class "Default")
      (node (ref "U27") (pin "96") (pinfunction "PB9/SPI2_NSS/I2S2_WS/TIM4_CH4/TIM11_CH1/SDIO_D5/DCMI_D7/I2C1_SDA/CAN1_TX/EVENTOUT_96") (pintype "bidirectional"))
    )
    (net (code "1606") (name "unconnected-(U27A-PB10{slash}SPI2_SCK{slash}I2S2_CK{slash}I2C2_SCL{slash}USART3_TX{slash}OTG_HS_ULPI_D3{slash}ETH_MII_RX_ER{slash}TIM2_CH3{slash}EVENTOUT-Pad47)") (class "Default")
      (node (ref "U27") (pin "47") (pinfunction "PB10/SPI2_SCK/I2S2_CK/I2C2_SCL/USART3_TX/OTG_HS_ULPI_D3/ETH_MII_RX_ER/TIM2_CH3/EVENTOUT_47") (pintype "bidirectional"))
    )
    (net (code "1607") (name "unconnected-(U27A-PB11{slash}I2C2_SDA{slash}USART3_RX{slash}OTG_HS_ULPI_D4{slash}ETH_RMII_TX_EN{slash}ETH_MII_TX_EN{slash}TIM2_CH4{slash}EVENTOUT-Pad48)") (class "Default")
      (node (ref "U27") (pin "48") (pinfunction "PB11/I2C2_SDA/USART3_RX/OTG_HS_ULPI_D4/ETH_RMII_TX_EN/ETH_MII_TX_EN/TIM2_CH4/EVENTOUT_48") (pintype "bidirectional"))
    )
    (net (code "1608") (name "unconnected-(U27A-PB12{slash}SPI2_NSS{slash}I2S2_WS{slash}I2C2_SMBA{slash}USART3_CK{slash}TIM1_BKIN{slash}CAN2_RX{slash}OTG_HS_ULPI_D5{slash}ETH_RMII_TXD0{slash}ETH_MII_TXD0{slash}OTG_HS_ID{slash}EVENTOUT-Pad51)") (class "Default")
      (node (ref "U27") (pin "51") (pinfunction "PB12/SPI2_NSS/I2S2_WS/I2C2_SMBA/USART3_CK/TIM1_BKIN/CAN2_RX/OTG_HS_ULPI_D5/ETH_RMII_TXD0/ETH_MII_TXD0/OTG_HS_ID/EVENTOUT_51") (pintype "bidirectional"))
    )
    (net (code "1609") (name "unconnected-(U27A-PB13{slash}SPI2_SCK{slash}I2S2_CK{slash}USART3_CTS{slash}TIM1_CH1N{slash}CAN2_TX{slash}OTG_HS_ULPI_D6{slash}ETH_RMII_TXD1{slash}ETH_MII_TXD1{slash}EVENTOUT{slash}OTG_HS_VBUS-Pad52)") (class "Default")
      (node (ref "U27") (pin "52") (pinfunction "PB13/SPI2_SCK/I2S2_CK/USART3_CTS/TIM1_CH1N/CAN2_TX/OTG_HS_ULPI_D6/ETH_RMII_TXD1/ETH_MII_TXD1/EVENTOUT/OTG_HS_VBUS_52") (pintype "bidirectional"))
    )
    (net (code "1610") (name "unconnected-(U27A-PB14{slash}SPI2_MISO{slash}TIM1_CH2N{slash}TIM12_CH1{slash}OTG_HS_DM{slash}USART3_RTS{slash}TIM8_CH2N{slash}I2S2ext_SD{slash}EVENTOUT-Pad53)") (class "Default")
      (node (ref "U27") (pin "53") (pinfunction "PB14/SPI2_MISO/TIM1_CH2N/TIM12_CH1/OTG_HS_DM/USART3_RTS/TIM8_CH2N/I2S2ext_SD/EVENTOUT_53") (pintype "bidirectional"))
    )
    (net (code "1611") (name "unconnected-(U27A-PB15{slash}SPI2_MOSI{slash}I2S2_SD{slash}TIM1_CH3N{slash}TIM8_CH3N{slash}TIM12_CH2{slash}OTG_HS_DP{slash}EVENTOUT-Pad54)") (class "Default")
      (node (ref "U27") (pin "54") (pinfunction "PB15/SPI2_MOSI/I2S2_SD/TIM1_CH3N/TIM8_CH3N/TIM12_CH2/OTG_HS_DP/EVENTOUT_54") (pintype "bidirectional"))
    )
    (net (code "1612") (name "unconnected-(U28-ADC_ETR{slash}TIM2_CH2{slash}AIN4{slash}(HS)PD3-Pad20)") (class "Default")
      (node (ref "U28") (pin "20") (pinfunction "ADC_ETR/TIM2_CH2/AIN4/(HS)PD3_20") (pintype "bidirectional"))
    )
    (net (code "1613") (name "unconnected-(U28-OSCOUT{slash}PA2-Pad6)") (class "Default")
      (node (ref "U28") (pin "6") (pinfunction "OSCOUT/PA2_6") (pintype "bidirectional"))
    )
    (net (code "1614") (name "unconnected-(U28-PA3(HS){slash}TIM2_CH3{slash}[SPI_NSS]-Pad10)") (class "Default")
      (node (ref "U28") (pin "10") (pinfunction "PA3(HS)/TIM2_CH3/[SPI_NSS]_10") (pintype "bidirectional"))
    )
    (net (code "1615") (name "unconnected-(U28-SWIM{slash}(HS)PD1-Pad18)") (class "Default")
      (node (ref "U28") (pin "18") (pinfunction "SWIM/(HS)PD1_18") (pintype "bidirectional"))
    )
    (net (code "1616") (name "unconnected-(U28-VCAP-Pad8)") (class "Default")
      (node (ref "U28") (pin "8") (pinfunction "VCAP_8") (pintype "power_in"))
    )
    (net (code "1617") (name "unconnected-(U28-VDD-Pad9)") (class "Default")
      (node (ref "U28") (pin "9") (pinfunction "VDD_9") (pintype "power_in"))
    )
    (net (code "1618") (name "unconnected-(U28-VSS-Pad7)") (class "Default")
      (node (ref "U28") (pin "7") (pinfunction "VSS_7") (pintype "power_in"))
    )
    (net (code "1619") (name "unconnected-(U28-[ADC_ETR]I2C_SCL{slash}(T)PB4-Pad12)") (class "Default")
      (node (ref "U28") (pin "12") (pinfunction "[ADC_ETR]I2C_SCL/(T)PB4_12") (pintype "bidirectional"))
    )
    (net (code "1620") (name "unconnected-(U28-[TIM1_BKIN]I2C_SDA_{slash}(T)PB5-Pad11)") (class "Default")
      (node (ref "U28") (pin "11") (pinfunction "[TIM1_BKIN]I2C_SDA_/(T)PB5_11") (pintype "bidirectional"))
    )
    (net (code "1621") (name "unconnected-(U28-[TIM1_CH1N][TLI]{slash}TIM1_CH3{slash}(HS)PC3-Pad13)") (class "Default")
      (node (ref "U28") (pin "13") (pinfunction "[TIM1_CH1N][TLI]/TIM1_CH3/(HS)PC3_13") (pintype "bidirectional"))
    )
    (net (code "1622") (name "unconnected-(U28-[TIM1_CH1]{slash}SPI_MOSI{slash}(HS)PC6-Pad16)") (class "Default")
      (node (ref "U28") (pin "16") (pinfunction "[TIM1_CH1]/SPI_MOSI/(HS)PC6_16") (pintype "bidirectional"))
    )
    (net (code "1623") (name "unconnected-(U28-[TIM1_CH2N][AIN2]{slash}CLK_CCO{slash}TIM1_CH4{slash}(HS)PC4-Pad14)") (class "Default")
      (node (ref "U28") (pin "14") (pinfunction "[TIM1_CH2N][AIN2]/CLK_CCO/TIM1_CH4/(HS)PC4_14") (pintype "bidirectional"))
    )
    (net (code "1624") (name "unconnected-(U28-[TIM1_CH2]SPI_MISO{slash}(HS)PC7-Pad17)") (class "Default")
      (node (ref "U28") (pin "17") (pinfunction "[TIM1_CH2]SPI_MISO/(HS)PC7_17") (pintype "bidirectional"))
    )
    (net (code "1625") (name "unconnected-(U28-[TIM2_CH1]SPI_SCK{slash}(HS)PC5-Pad15)") (class "Default")
      (node (ref "U28") (pin "15") (pinfunction "[TIM2_CH1]SPI_SCK/(HS)PC5_15") (pintype "bidirectional"))
    )
    (net (code "1626") (name "unconnected-(U28-[TIM2_CH3][AIN3]{slash}(HS)PD2-Pad19)") (class "Default")
      (node (ref "U28") (pin "19") (pinfunction "[TIM2_CH3][AIN3]/(HS)PD2_19") (pintype "bidirectional"))
    )
    (net (code "1627") (name "unconnected-(U29-NRST{slash}PA1-Pad4)") (class "Default")
      (node (ref "U29") (pin "4") (pinfunction "NRST/PA1_4") (pintype "passive"))
    )
    (net (code "1628") (name "unconnected-(U29-PA3-Pad6)") (class "Default")
      (node (ref "U29") (pin "6") (pinfunction "PA3_6") (pintype "passive"))
    )
    (net (code "1629") (name "unconnected-(U29-PB0-Pad10)") (class "Default")
      (node (ref "U29") (pin "10") (pinfunction "PB0_10") (pintype "passive"))
    )
    (net (code "1630") (name "unconnected-(U29-PB1-Pad11)") (class "Default")
      (node (ref "U29") (pin "11") (pinfunction "PB1_11") (pintype "passive"))
    )
    (net (code "1631") (name "unconnected-(U29-PB2-Pad12)") (class "Default")
      (node (ref "U29") (pin "12") (pinfunction "PB2_12") (pintype "passive"))
    )
    (net (code "1632") (name "unconnected-(U29-PB3-Pad13)") (class "Default")
      (node (ref "U29") (pin "13") (pinfunction "PB3_13") (pintype "passive"))
    )
    (net (code "1633") (name "unconnected-(U29-PB4-Pad14)") (class "Default")
      (node (ref "U29") (pin "14") (pinfunction "PB4_14") (pintype "passive"))
    )
    (net (code "1634") (name "unconnected-(U29-PB5-Pad15)") (class "Default")
      (node (ref "U29") (pin "15") (pinfunction "PB5_15") (pintype "passive"))
    )
    (net (code "1635") (name "unconnected-(U29-PB6-Pad16)") (class "Default")
      (node (ref "U29") (pin "16") (pinfunction "PB6_16") (pintype "passive"))
    )
    (net (code "1636") (name "unconnected-(U29-PB7-Pad17)") (class "Default")
      (node (ref "U29") (pin "17") (pinfunction "PB7_17") (pintype "passive"))
    )
    (net (code "1637") (name "unconnected-(U29-PC0-Pad18)") (class "Default")
      (node (ref "U29") (pin "18") (pinfunction "PC0_18") (pintype "passive"))
    )
    (net (code "1638") (name "unconnected-(U29-PC1-Pad19)") (class "Default")
      (node (ref "U29") (pin "19") (pinfunction "PC1_19") (pintype "passive"))
    )
    (net (code "1639") (name "unconnected-(U29-PC4-Pad20)") (class "Default")
      (node (ref "U29") (pin "20") (pinfunction "PC4_20") (pintype "passive"))
    )
    (net (code "1640") (name "unconnected-(U29-PC6-Pad2)") (class "Default")
      (node (ref "U29") (pin "2") (pinfunction "PC6_2") (pintype "passive"))
    )
    (net (code "1641") (name "unconnected-(U29-VDD{slash}VDDA{slash}VREF+-Pad8)") (class "Default")
      (node (ref "U29") (pin "8") (pinfunction "VDD/VDDA/VREF+_8") (pintype "passive"))
    )
    (net (code "1642") (name "unconnected-(U30-NRST-Pad4)") (class "Default")
      (node (ref "U30") (pin "4") (pinfunction "NRST_4") (pintype "passive"))
    )
    (net (code "1643") (name "unconnected-(U30-OSCIN{slash}PA1-Pad5)") (class "Default")
      (node (ref "U30") (pin "5") (pinfunction "OSCIN/PA1_5") (pintype "passive"))
    )
    (net (code "1644") (name "unconnected-(U30-OSCOUT{slash}PA2-Pad6)") (class "Default")
      (node (ref "U30") (pin "6") (pinfunction "OSCOUT/PA2_6") (pintype "passive"))
    )
    (net (code "1645") (name "unconnected-(U30-PB4_(T){slash}I__2C_SCL_[ADC_ETR]-Pad12)") (class "Default")
      (node (ref "U30") (pin "12") (pinfunction "PB4_(T)/I__2C_SCL_[ADC_ETR]_12") (pintype "passive"))
    )
    (net (code "1646") (name "unconnected-(U30-PB5_(T){slash}I__2C_SDA_[TIM1_BKIN]-Pad11)") (class "Default")
      (node (ref "U30") (pin "11") (pinfunction "PB5_(T)/I__2C_SDA_[TIM1_BKIN]_11") (pintype "passive"))
    )
    (net (code "1647") (name "unconnected-(U30-PC3_(HS){slash}TIM1_CH3_[TLI]_[TIM1_CH1N]-Pad13)") (class "Default")
      (node (ref "U30") (pin "13") (pinfunction "PC3_(HS)/TIM1_CH3_[TLI]_[TIM1_CH1N]_13") (pintype "passive"))
    )
    (net (code "1648") (name "unconnected-(U30-PC5_(HS){slash}SPI_SCK_[TIM2_CH1]-Pad15)") (class "Default")
      (node (ref "U30") (pin "15") (pinfunction "PC5_(HS)/SPI_SCK_[TIM2_CH1]_15") (pintype "passive"))
    )
    (net (code "1649") (name "unconnected-(U30-PC6_(HS){slash}SPI_MOSI_[TIM1_CH1]-Pad16)") (class "Default")
      (node (ref "U30") (pin "16") (pinfunction "PC6_(HS)/SPI_MOSI_[TIM1_CH1]_16") (pintype "passive"))
    )
    (net (code "1650") (name "unconnected-(U30-PC7_(HS){slash}SPI_MISO_[TIM1_CH2]-Pad17)") (class "Default")
      (node (ref "U30") (pin "17") (pinfunction "PC7_(HS)/SPI_MISO_[TIM1_CH2]_17") (pintype "passive"))
    )
    (net (code "1651") (name "unconnected-(U30-PD1(HS){slash}SWIM-Pad18)") (class "Default")
      (node (ref "U30") (pin "18") (pinfunction "PD1(HS)/SWIM_18") (pintype "passive"))
    )
    (net (code "1652") (name "unconnected-(U30-PD2_(HS){slash}AIN3{slash}[TIM2_CH3]-Pad19)") (class "Default")
      (node (ref "U30") (pin "19") (pinfunction "PD2_(HS)/AIN3/[TIM2_CH3]_19") (pintype "passive"))
    )
    (net (code "1653") (name "unconnected-(U30-PD3_(HS){slash}AIN4{slash}TIM2_CH2{slash}ADC_ETR-Pad20)") (class "Default")
      (node (ref "U30") (pin "20") (pinfunction "PD3_(HS)/AIN4/TIM2_CH2/ADC_ETR_20") (pintype "passive"))
    )
    (net (code "1654") (name "unconnected-(U30-UART1_CK{slash}TIM2_CH1{slash}BEEP{slash}(HS)PD4-Pad1)") (class "Default")
      (node (ref "U30") (pin "1") (pinfunction "UART1_CK/TIM2_CH1/BEEP/(HS)PD4_1") (pintype "passive"))
    )
    (net (code "1655") (name "unconnected-(U30-UART1_RX{slash}AIN6{slash}(HS)_PD6-Pad3)") (class "Default")
      (node (ref "U30") (pin "3") (pinfunction "UART1_RX/AIN6/(HS)_PD6_3") (pintype "passive"))
    )
    (net (code "1656") (name "unconnected-(U30-UART1_TX{slash}AIN5{slash}(HS)_PD5-Pad2)") (class "Default")
      (node (ref "U30") (pin "2") (pinfunction "UART1_TX/AIN5/(HS)_PD5_2") (pintype "passive"))
    )
    (net (code "1657") (name "unconnected-(U30-VCAP-Pad8)") (class "Default")
      (node (ref "U30") (pin "8") (pinfunction "VCAP_8") (pintype "passive"))
    )
    (net (code "1658") (name "unconnected-(U30-VDD-Pad9)") (class "Default")
      (node (ref "U30") (pin "9") (pinfunction "VDD_9") (pintype "passive"))
    )
    (net (code "1659") (name "unconnected-(U30-VSS-Pad7)") (class "Default")
      (node (ref "U30") (pin "7") (pinfunction "VSS_7") (pintype "passive"))
    )
    (net (code "1660") (name "unconnected-(U30-[SPI_NSS]_TIM2_CH3{slash}(HS)_PA3-Pad10)") (class "Default")
      (node (ref "U30") (pin "10") (pinfunction "[SPI_NSS]_TIM2_CH3/(HS)_PA3_10") (pintype "passive"))
    )
    (net (code "1661") (name "unconnected-(VR1-GND-Pad1)") (class "Default")
      (node (ref "VR1") (pin "1") (pinfunction "GND_1") (pintype "passive"))
    )
    (net (code "1662") (name "unconnected-(VR1-Vin-Pad3)") (class "Default")
      (node (ref "VR1") (pin "3") (pinfunction "Vin_3") (pintype "passive"))
    )
    (net (code "1663") (name "unconnected-(VR2-GND-Pad1)") (class "Default")
      (node (ref "VR2") (pin "1") (pinfunction "GND_1") (pintype "passive"))
    )
    (net (code "1664") (name "unconnected-(VR2-Vin-Pad3)") (class "Default")
      (node (ref "VR2") (pin "3") (pinfunction "Vin_3") (pintype "passive"))
    )
    (net (code "1665") (name "unconnected-(VR2-Vout-Pad2)") (class "Default")
      (node (ref "VR2") (pin "2") (pinfunction "Vout_2") (pintype "passive"))
    )
    (net (code "1666") (name "unconnected-(VR3-GND-Pad1)") (class "Default")
      (node (ref "VR3") (pin "1") (pinfunction "GND_1") (pintype "passive"))
    )
    (net (code "1667") (name "unconnected-(VR3-Vout-Pad2)") (class "Default")
      (node (ref "VR3") (pin "2") (pinfunction "Vout_2") (pintype "passive"))
    )
    (net (code "1668") (name "unconnected-(VR4-GND-Pad2)") (class "Default")
      (node (ref "VR4") (pin "2") (pinfunction "GND_2") (pintype "passive"))
    )
    (net (code "1669") (name "unconnected-(VR4-Vin-Pad1)") (class "Default")
      (node (ref "VR4") (pin "1") (pinfunction "Vin_1") (pintype "passive"))
    )
    (net (code "1670") (name "unconnected-(VR4-Vout-Pad3)") (class "Default")
      (node (ref "VR4") (pin "3") (pinfunction "Vout_3") (pintype "passive"))
    )
    (net (code "1671") (name "unconnected-(VR5-GND-Pad2)") (class "Default")
      (node (ref "VR5") (pin "2") (pinfunction "GND_2") (pintype "passive"))
    )
    (net (code "1672") (name "unconnected-(VR5-Vin-Pad1)") (class "Default")
      (node (ref "VR5") (pin "1") (pinfunction "Vin_1") (pintype "passive"))
    )
    (net (code "1673") (name "unconnected-(VR5-Vout-Pad3)") (class "Default")
      (node (ref "VR5") (pin "3") (pinfunction "Vout_3") (pintype "passive"))
    )
    (net (code "1674") (name "unconnected-(VR6-GND-Pad1)") (class "Default")
      (node (ref "VR6") (pin "1") (pinfunction "GND_1") (pintype "passive"))
    )
    (net (code "1675") (name "unconnected-(VR6-Vin-Pad2)") (class "Default")
      (node (ref "VR6") (pin "2") (pinfunction "Vin_2") (pintype "passive"))
    )
    (net (code "1676") (name "unconnected-(VR6-Vout-Pad3)") (class "Default")
      (node (ref "VR6") (pin "3") (pinfunction "Vout_3") (pintype "passive"))
    )
    (net (code "1677") (name "unconnected-(VR7-GND-Pad1)") (class "Default")
      (node (ref "VR7") (pin "1") (pinfunction "GND_1") (pintype "passive"))
    )
    (net (code "1678") (name "unconnected-(VR7-Vin-Pad2)") (class "Default")
      (node (ref "VR7") (pin "2") (pinfunction "Vin_2") (pintype "passive"))
    )
    (net (code "1679") (name "unconnected-(VR7-Vout-Pad3)") (class "Default")
      (node (ref "VR7") (pin "3") (pinfunction "Vout_3") (pintype "passive"))
    )
    (net (code "1680") (name "unconnected-(VR8-GND-Pad2)") (class "Default")
      (node (ref "VR8") (pin "2") (pinfunction "GND_2") (pintype "passive"))
    )
    (net (code "1681") (name "unconnected-(VR8-Vin-Pad1)") (class "Default")
      (node (ref "VR8") (pin "1") (pinfunction "Vin_1") (pintype "passive"))
    )
    (net (code "1682") (name "unconnected-(VR8-Vout-Pad3)") (class "Default")
      (node (ref "VR8") (pin "3") (pinfunction "Vout_3") (pintype "passive"))
    )
    (net (code "1683") (name "unconnected-(VR9-GND-Pad1)") (class "Default")
      (node (ref "VR9") (pin "1") (pinfunction "GND_1") (pintype "passive"))
    )
    (net (code "1684") (name "unconnected-(VR9-Vin-Pad3)") (class "Default")
      (node (ref "VR9") (pin "3") (pinfunction "Vin_3") (pintype "passive"))
    )
  )
)
